# 63-00021_Worldcoin_Front_Unit_5_3.net
KiCad netlist of a schematic drawn in EAGLE
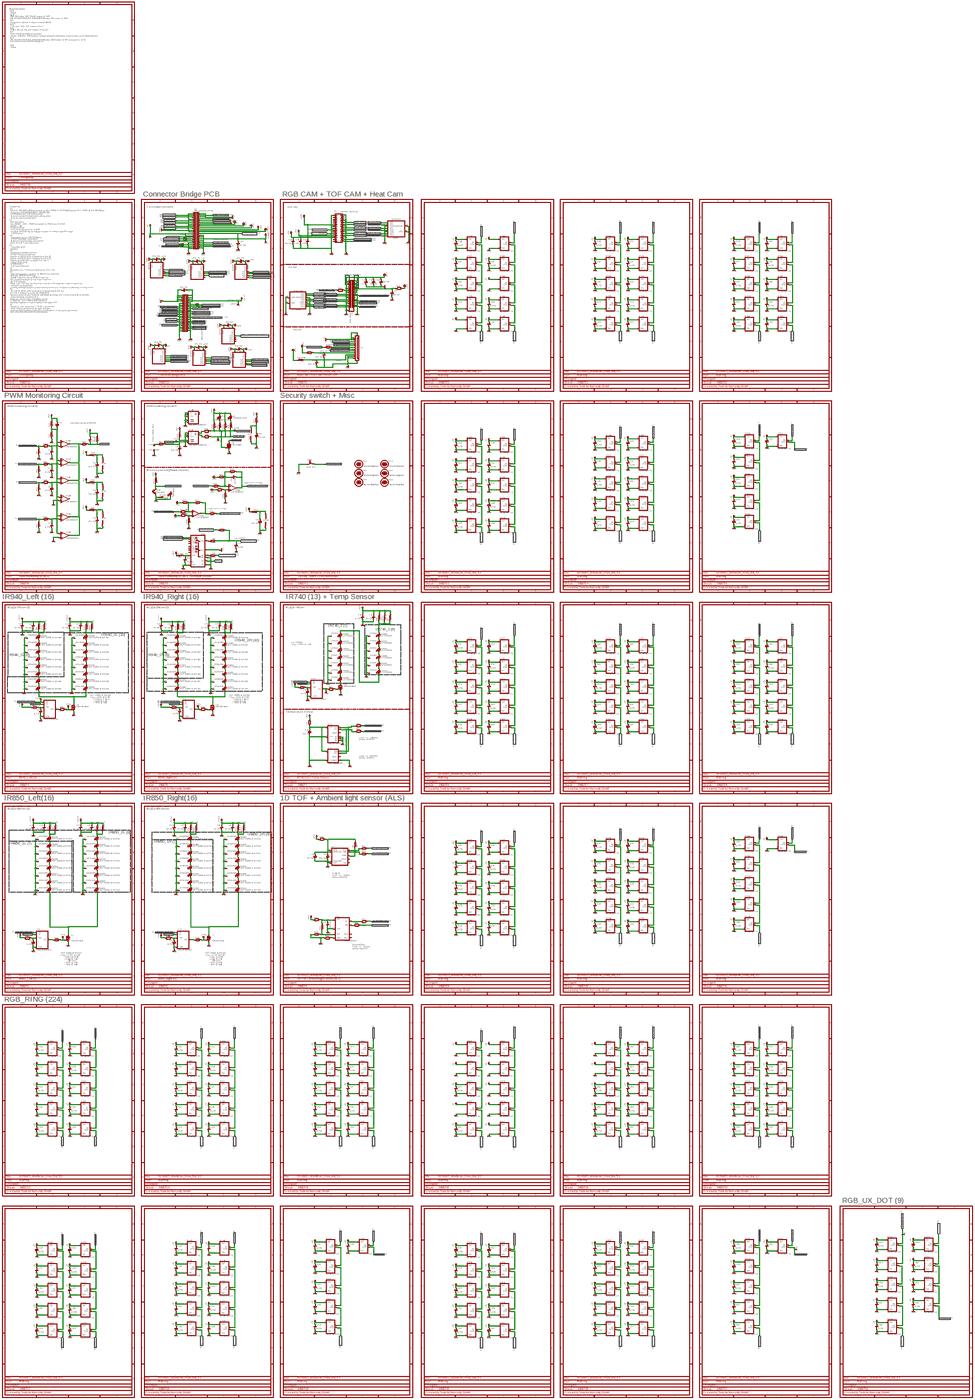
[diagram p0: schematic, sheet 1, overview]
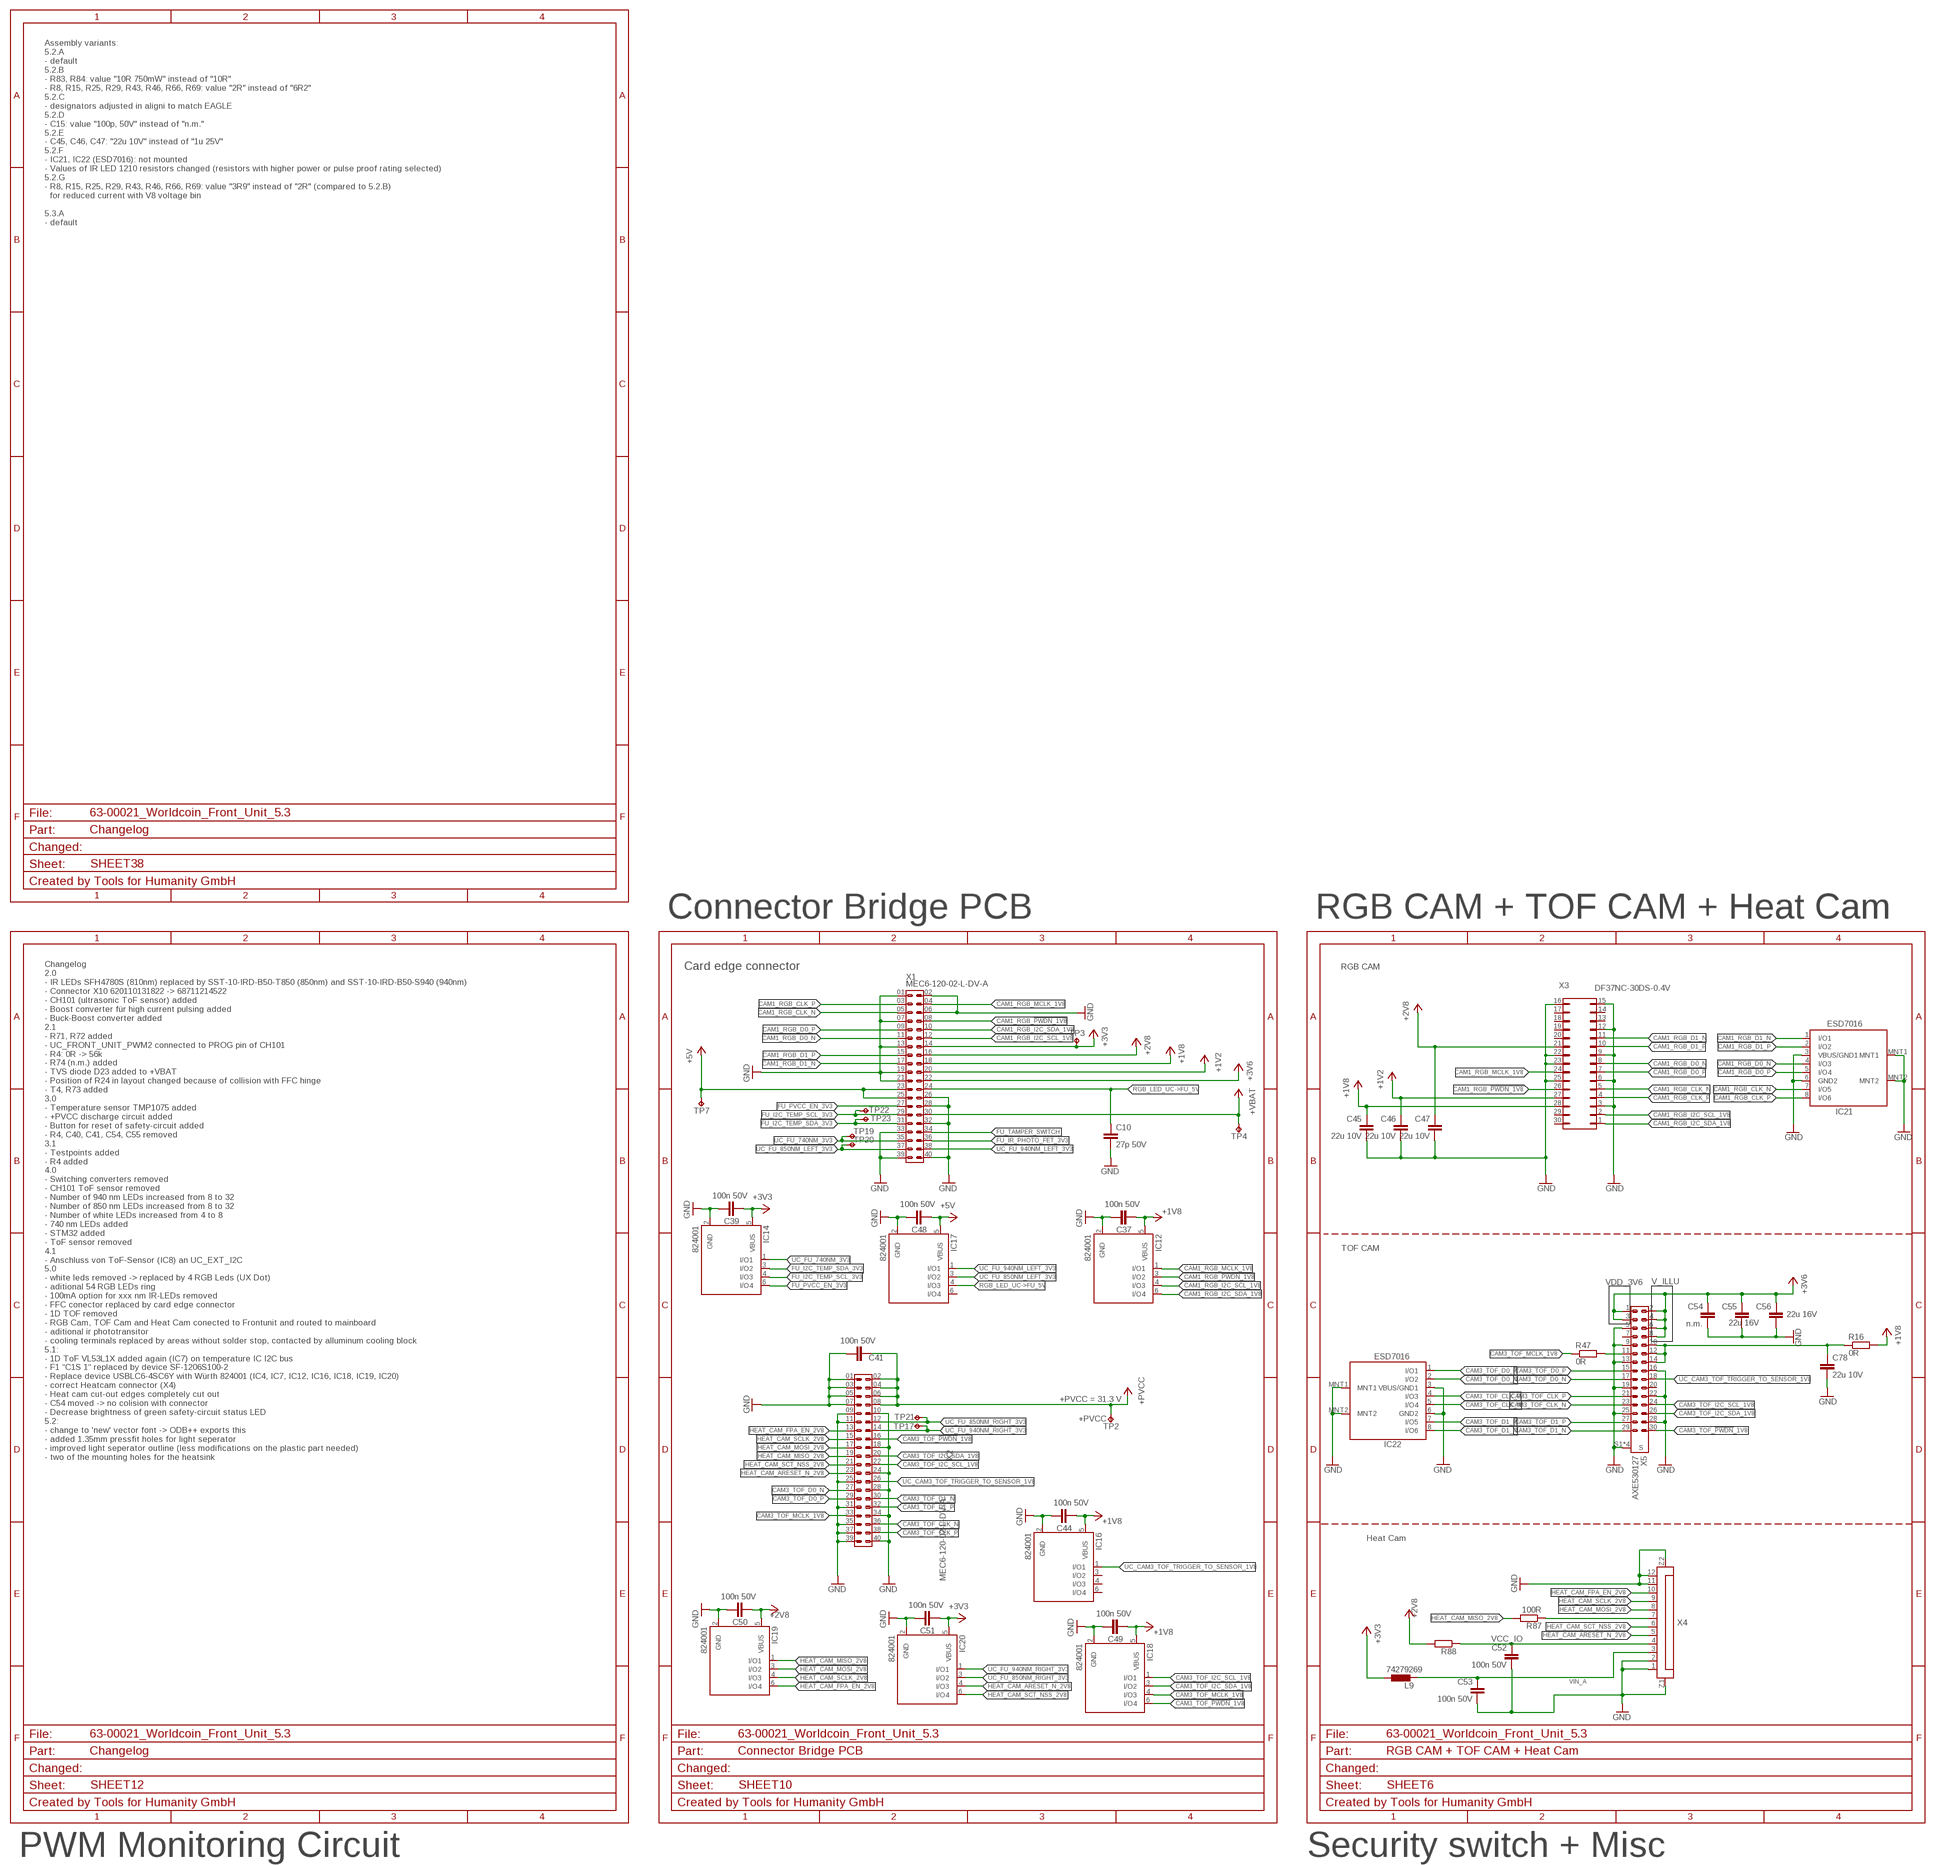
[diagram p1: schematic, sheet 1, part 1 of 8]
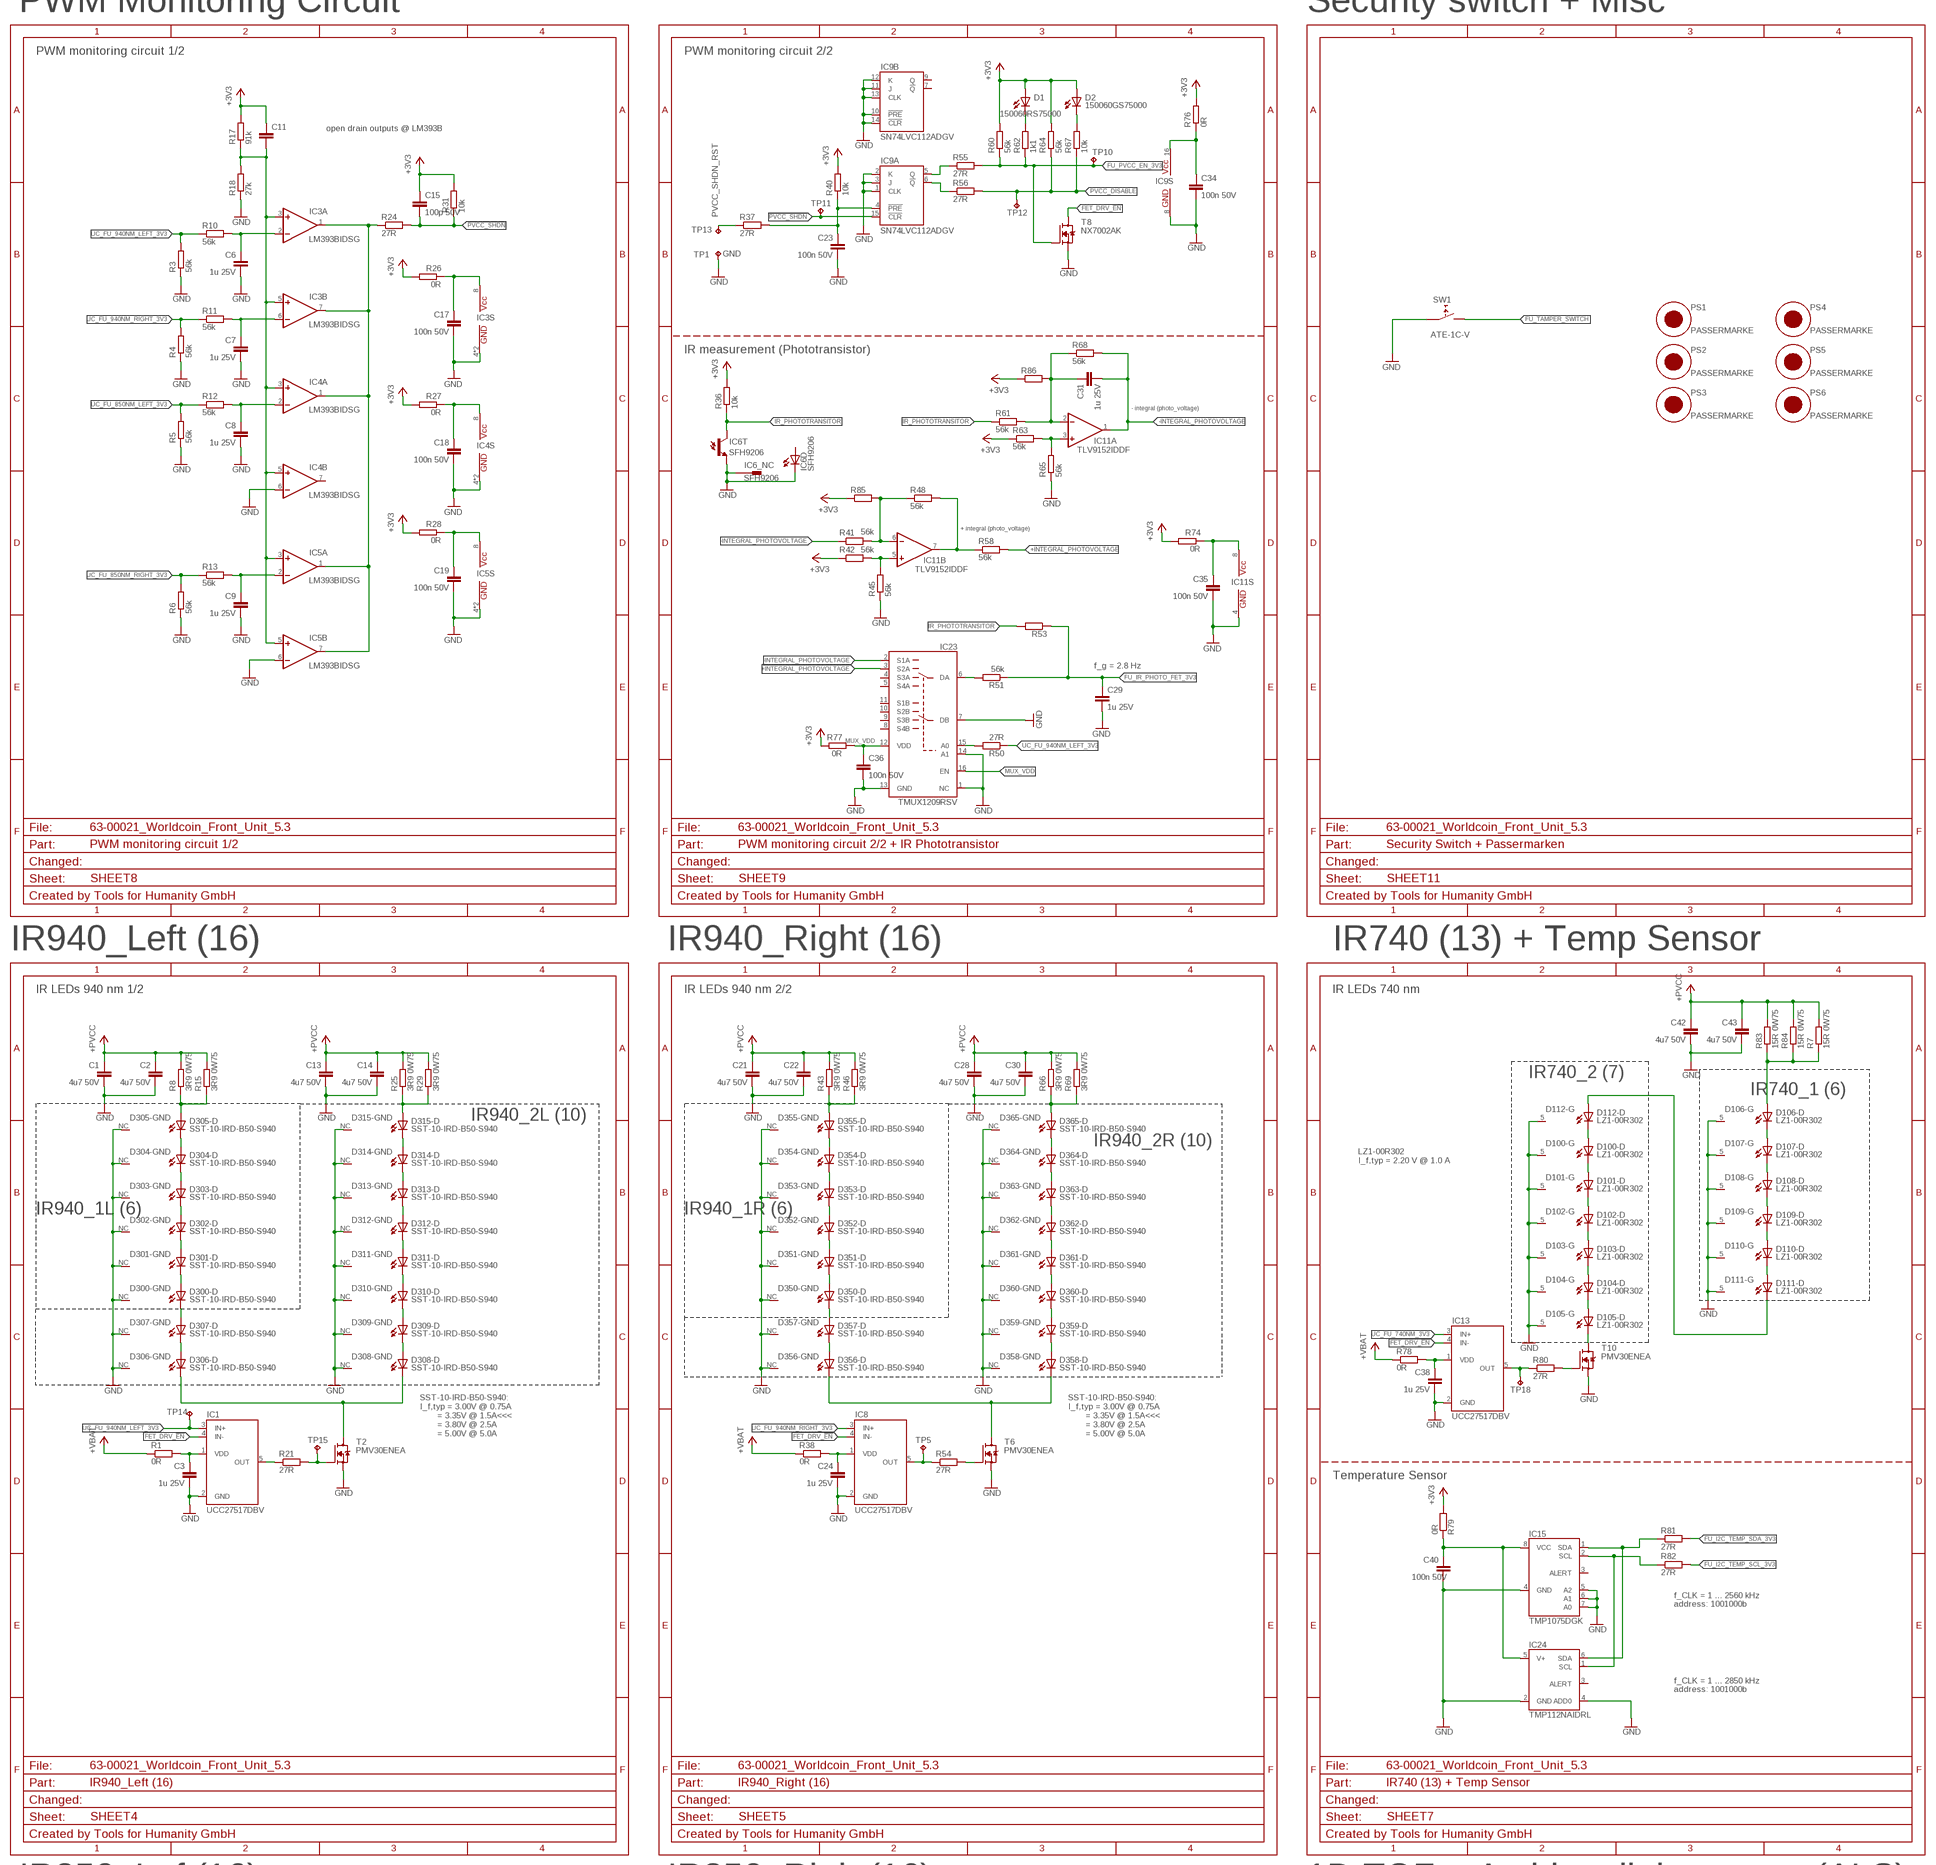
[diagram p2: schematic, sheet 1, part 2 of 8]
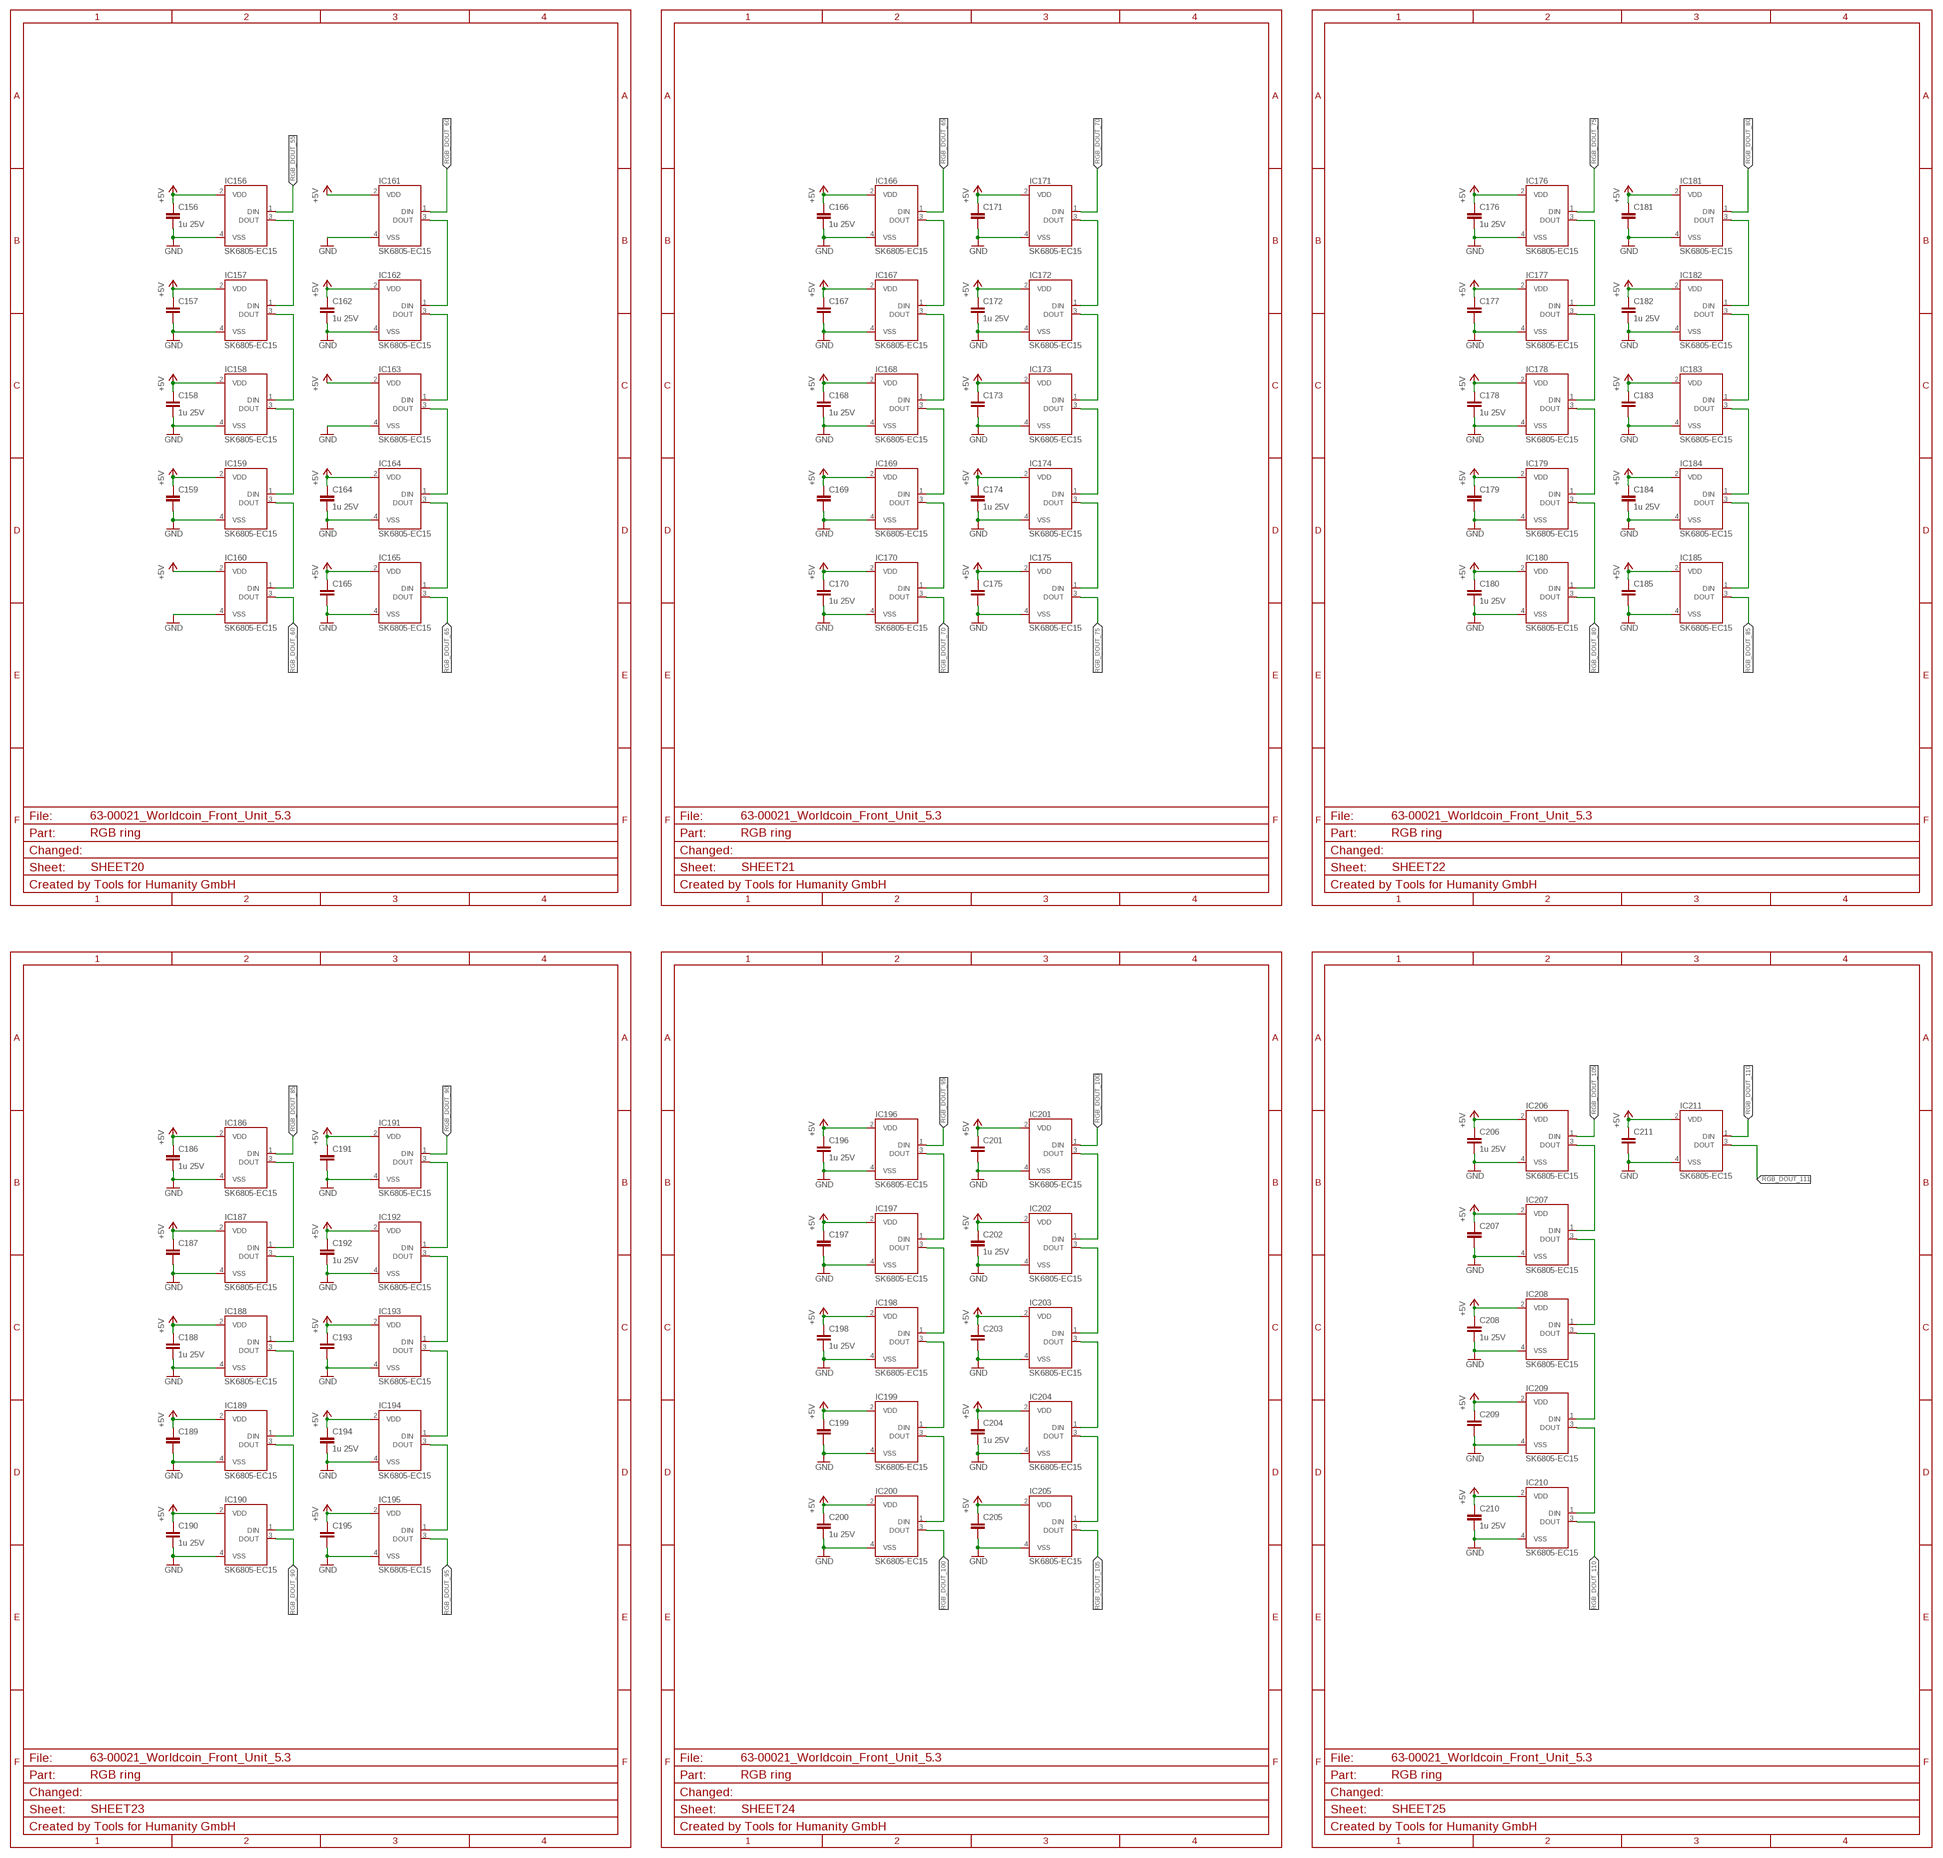
[diagram p3: schematic, sheet 1, part 3 of 8]
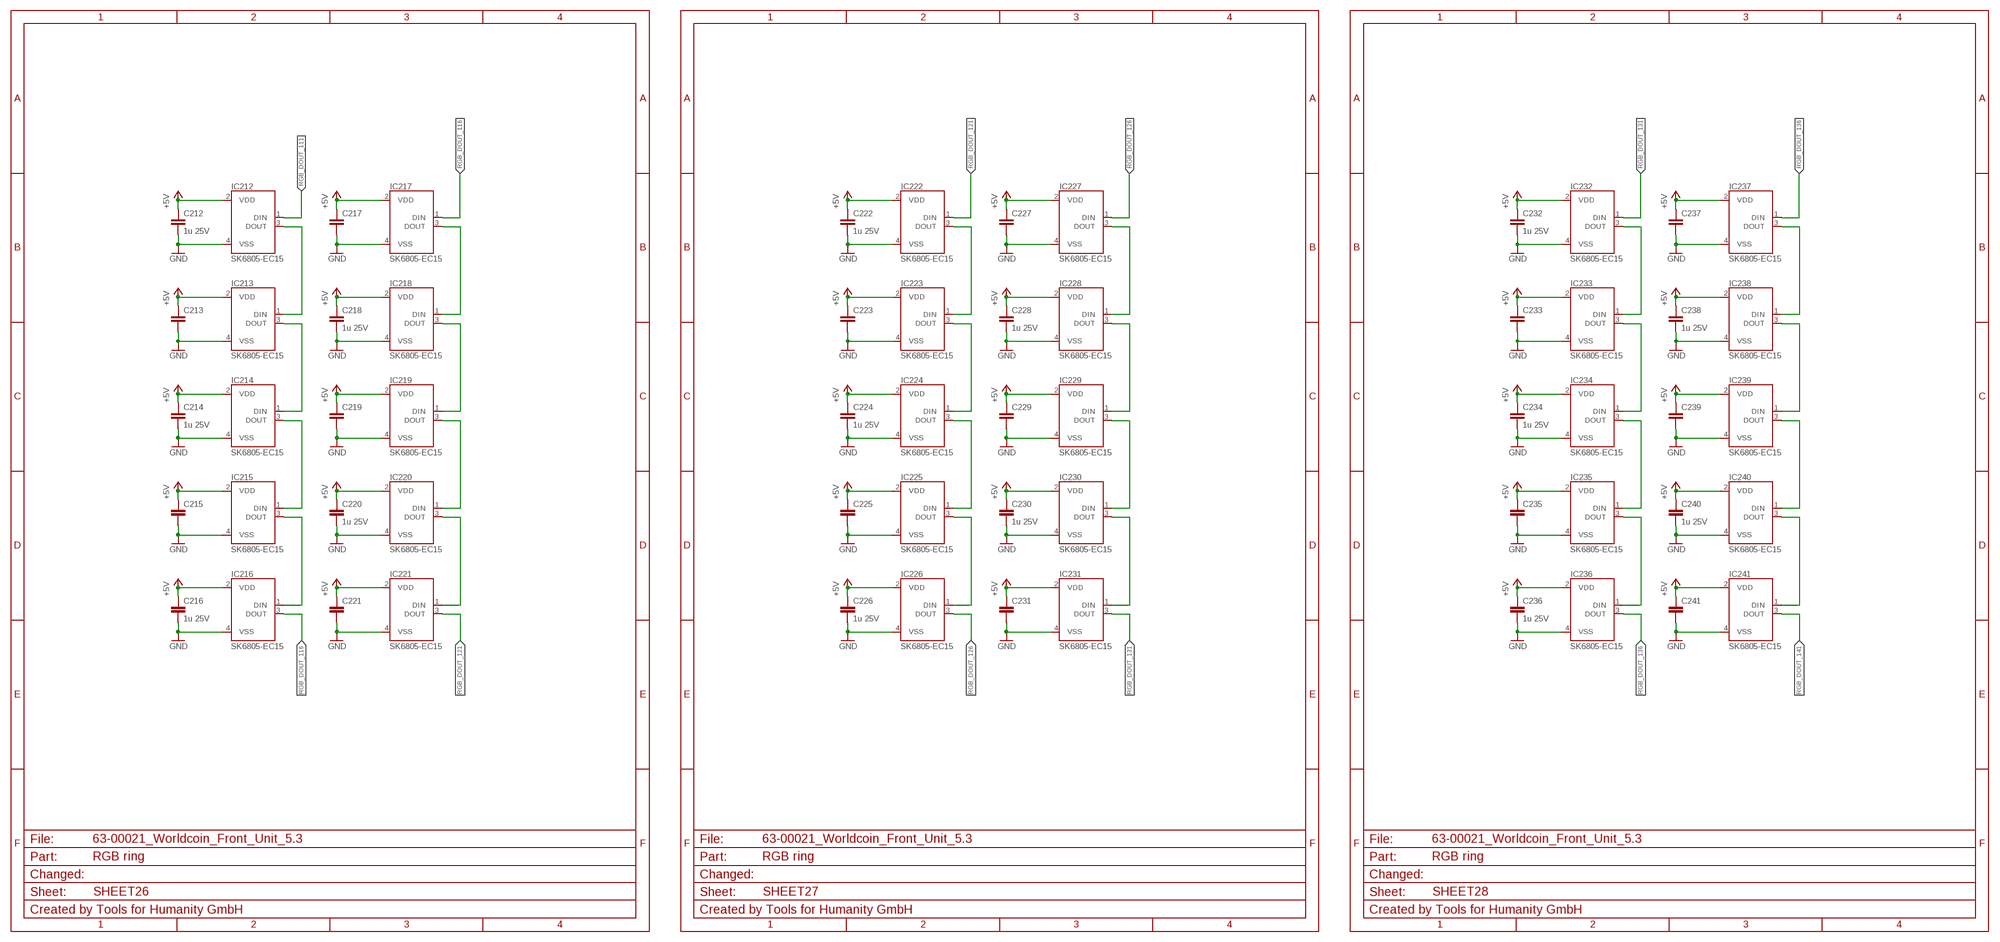
[diagram p4: schematic, sheet 1, part 4 of 8]
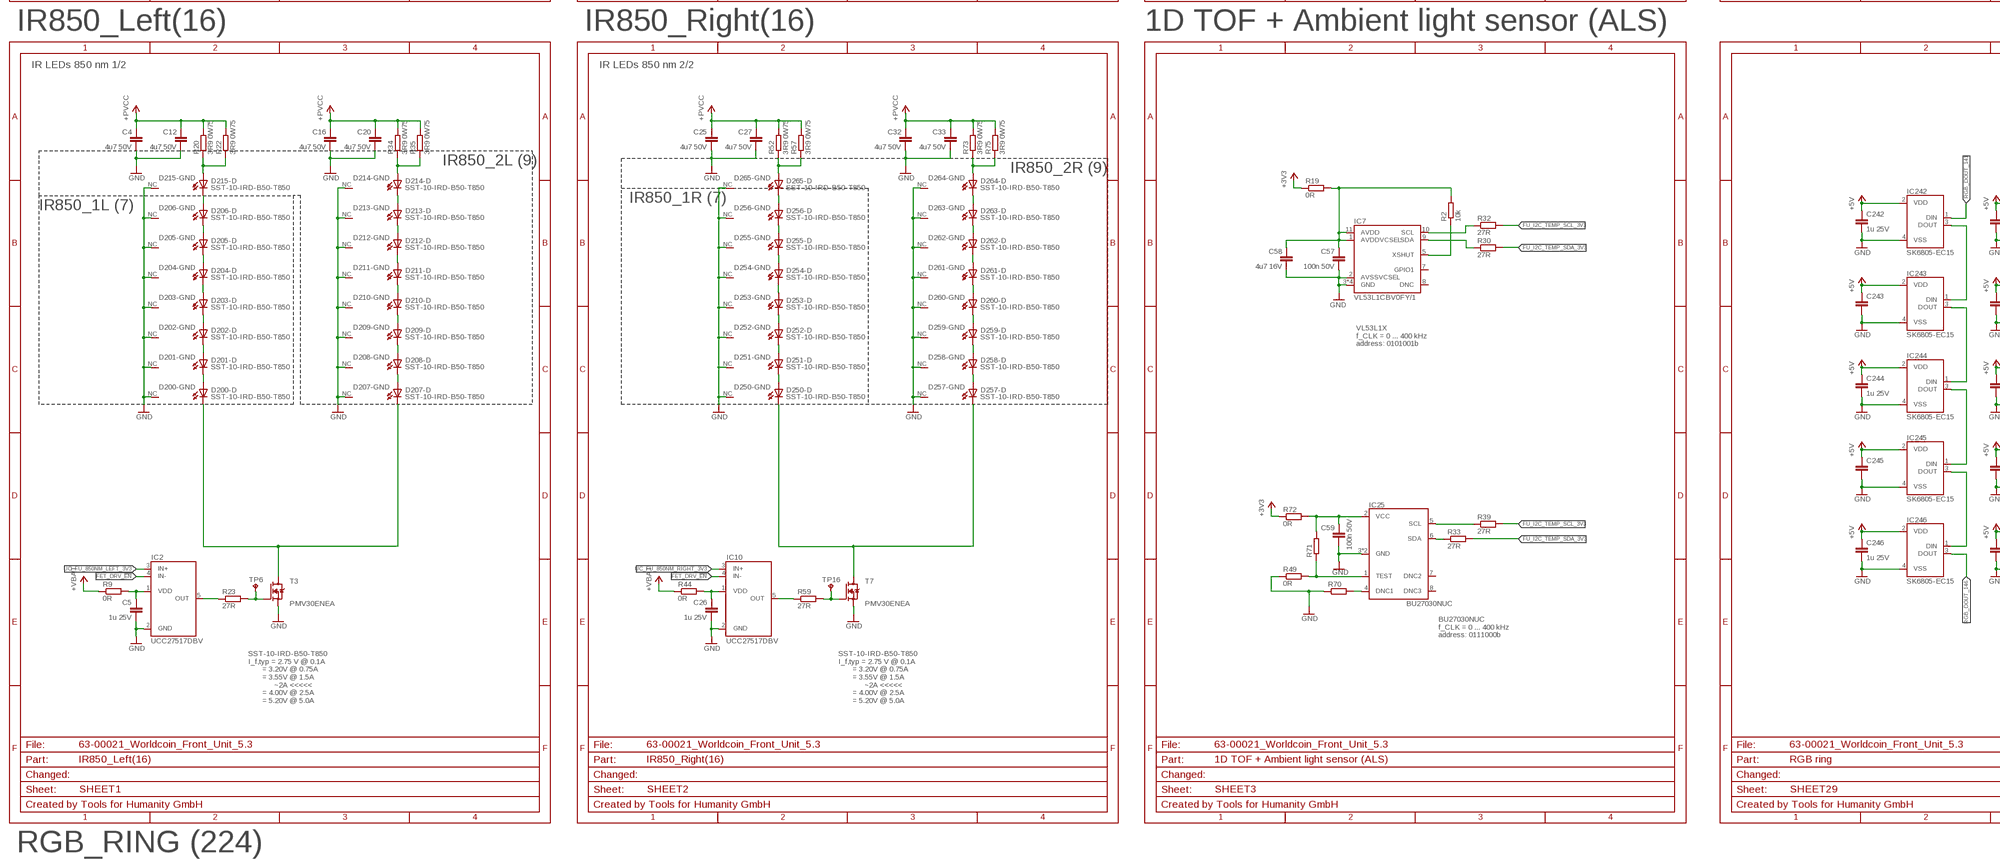
[diagram p5: schematic, sheet 1, part 5 of 8]
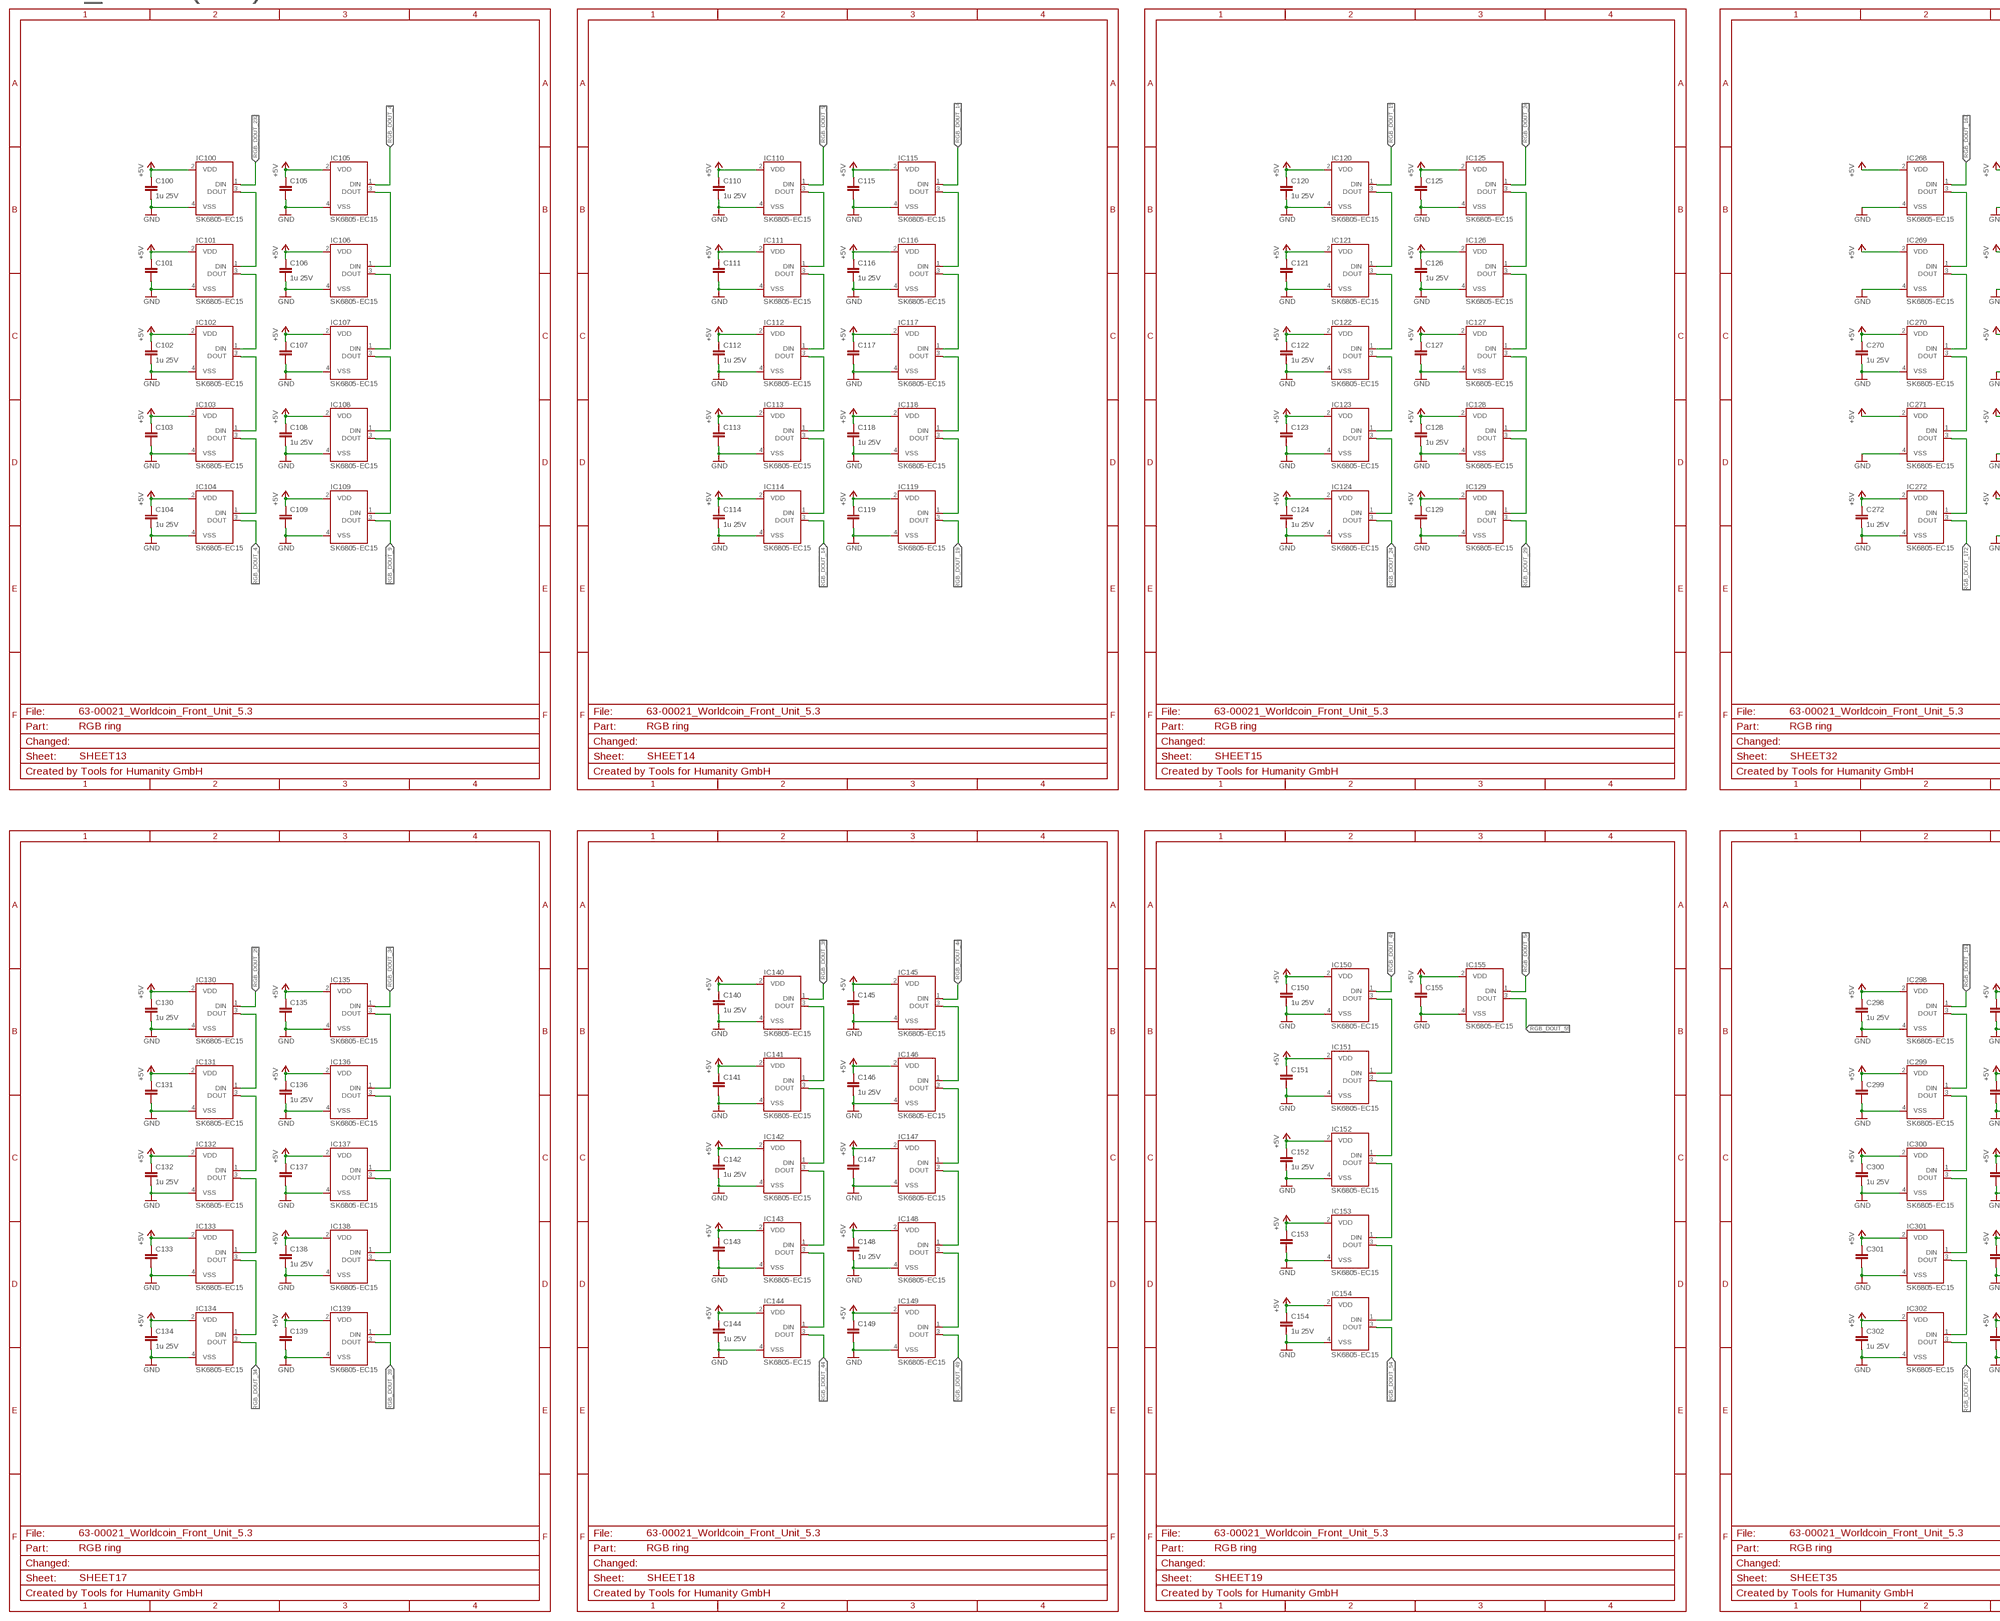
[diagram p6: schematic, sheet 1, part 6 of 8]
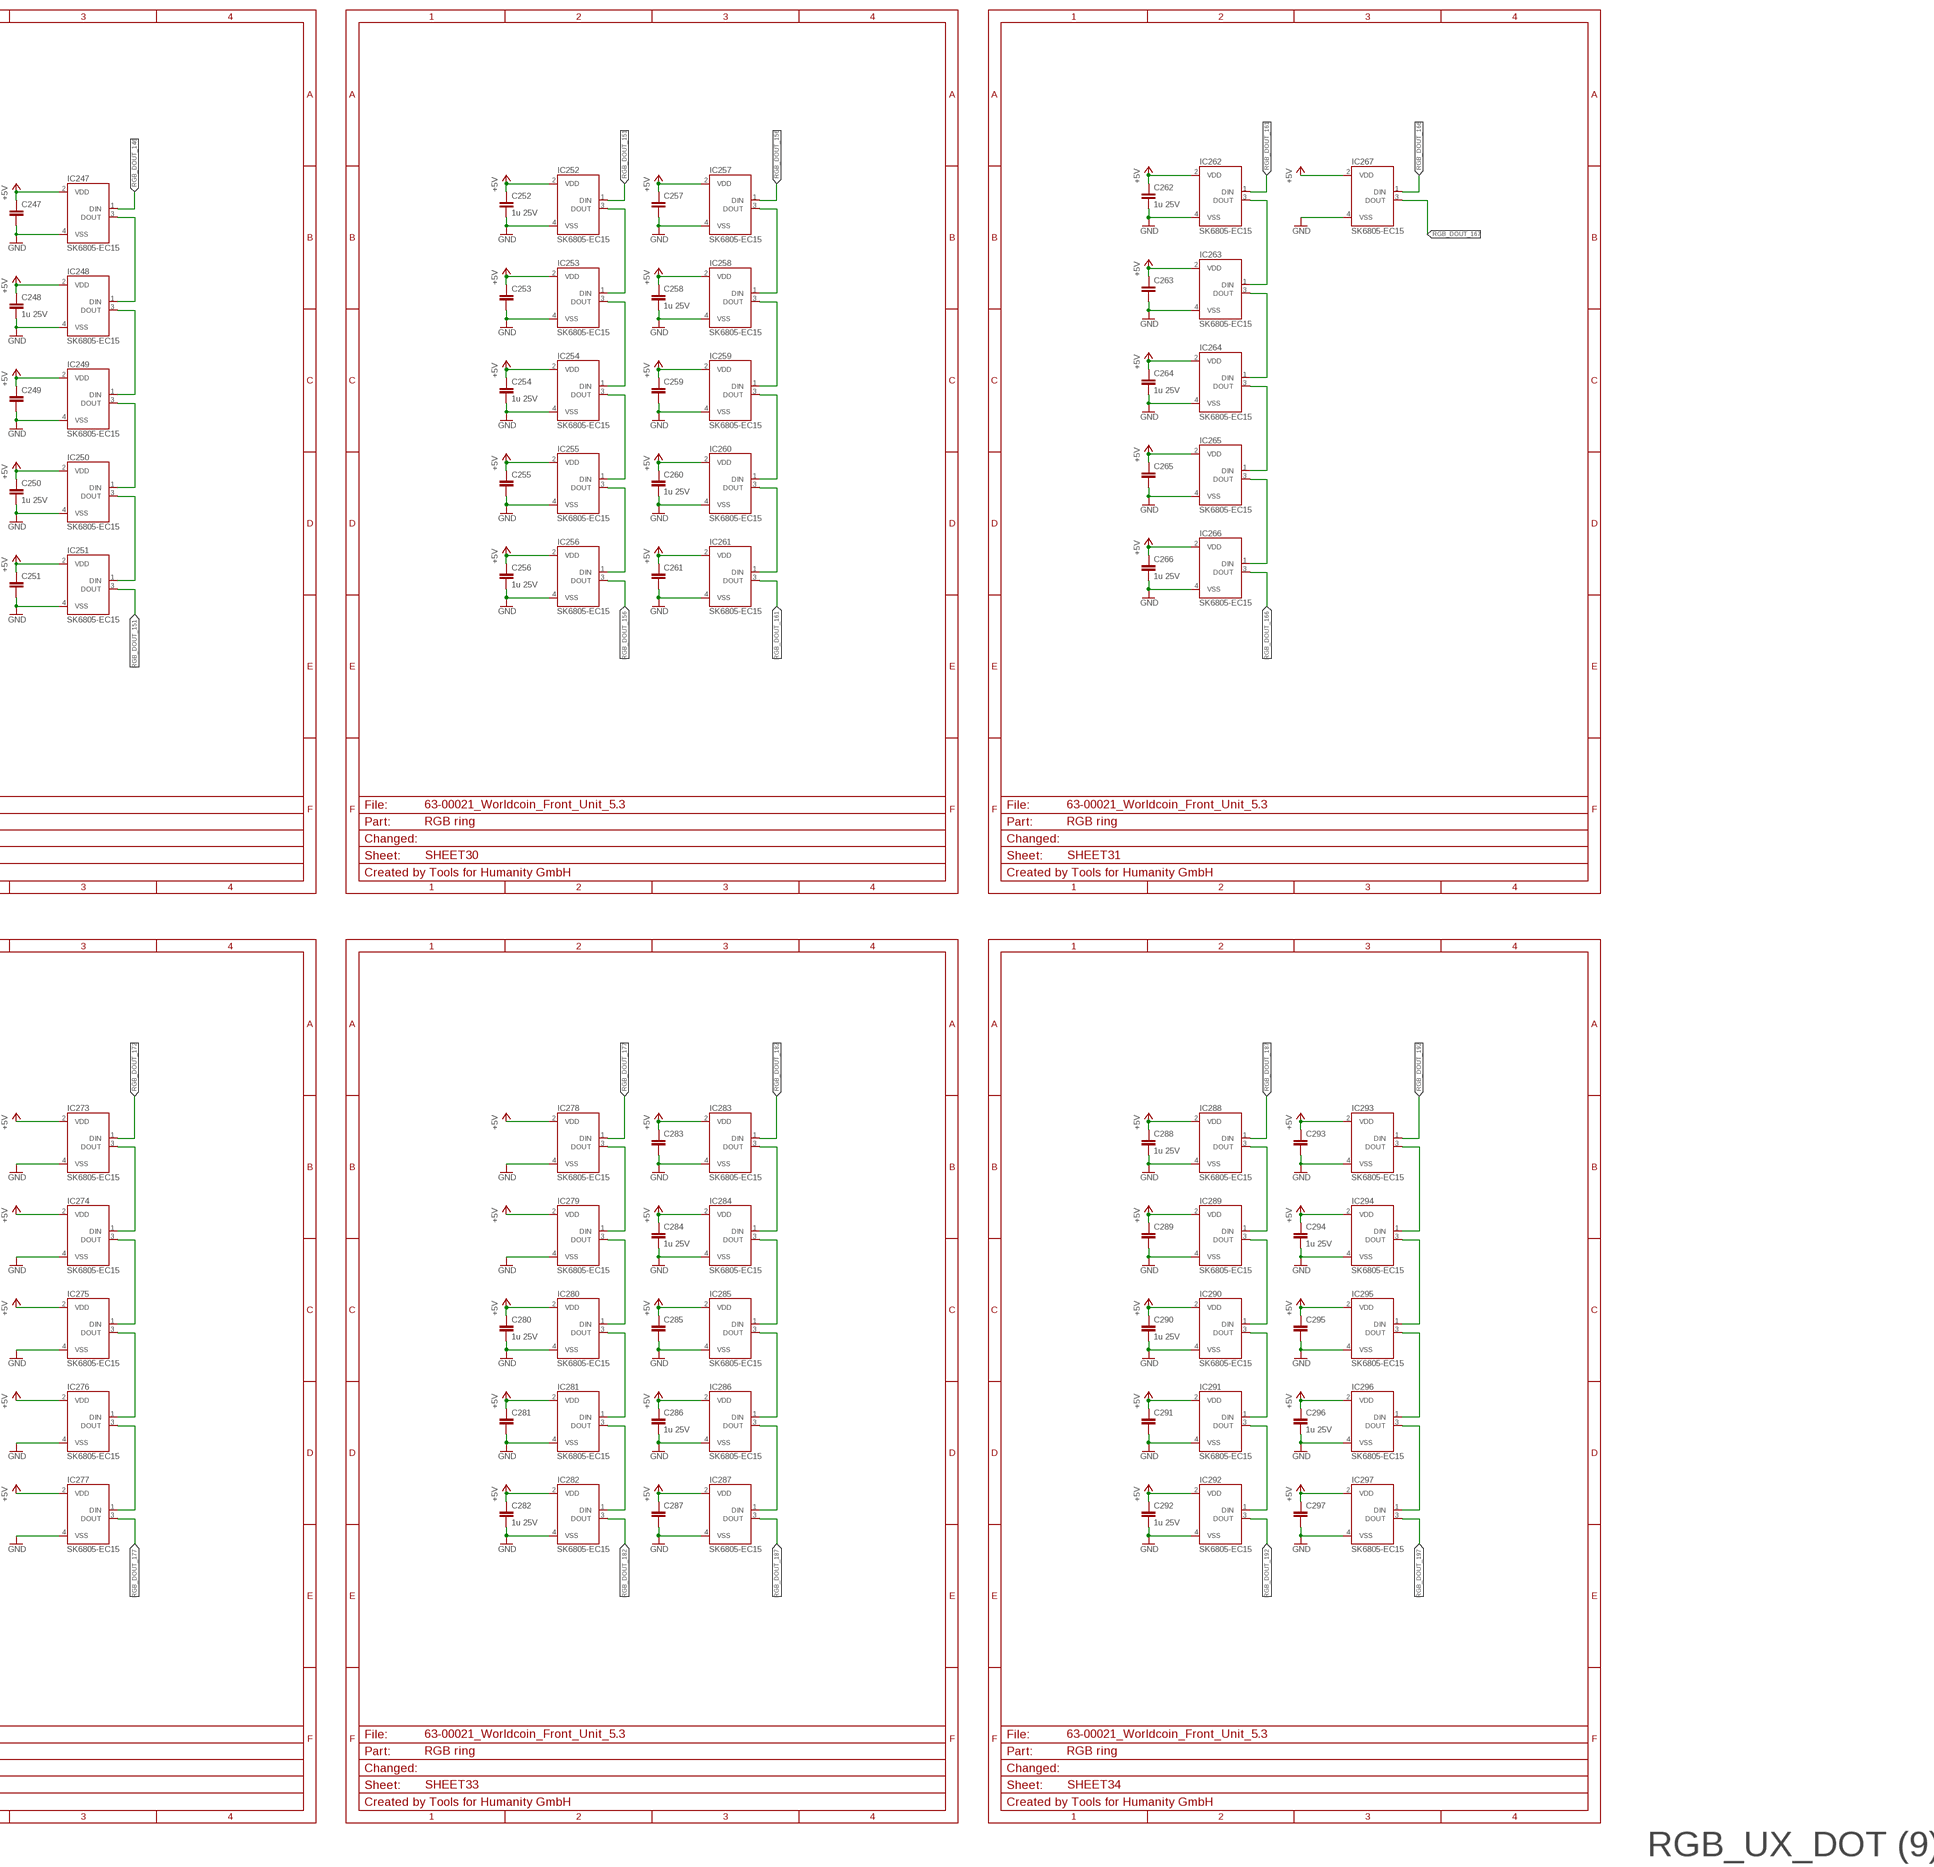
[diagram p7: schematic, sheet 1, part 7 of 8]
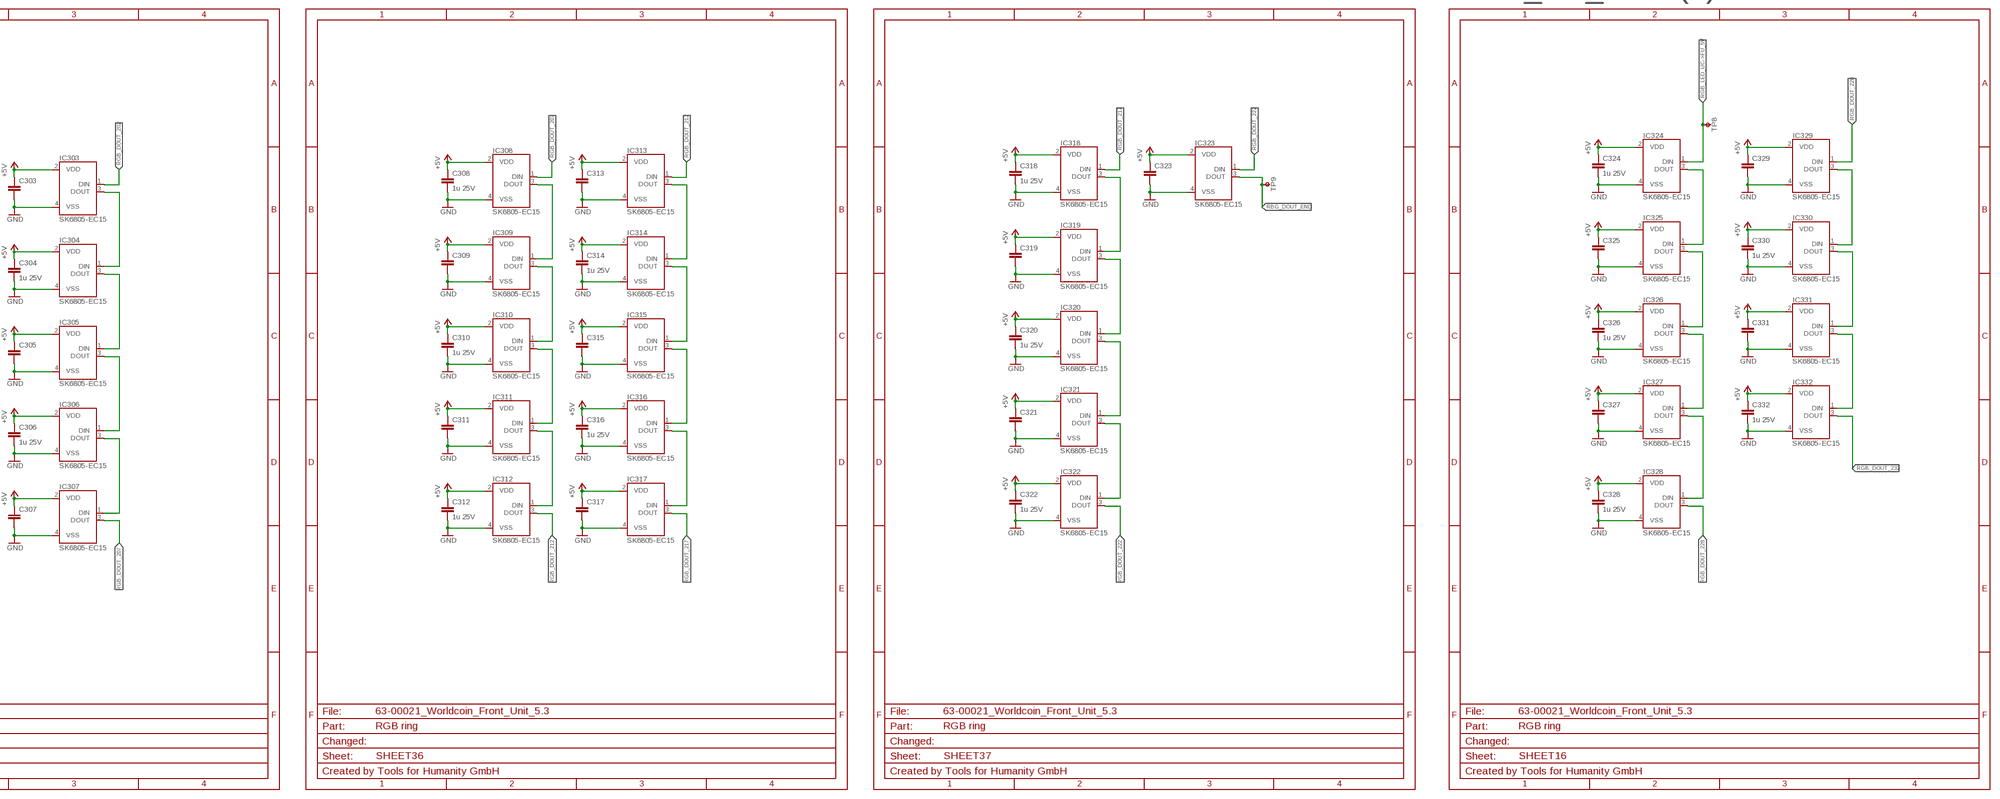
[diagram p8: schematic, sheet 1, part 8 of 8]

(export (version "E")
  (design (tool "Eeschema 10.0.6"))
  (components
    (comp (ref "C1")
      (value "4u7 50V")
      (footprint "eagle-import:C1210")
      (fields
        (field (name "MANUFACTURER") "free choice")
        (field (name "TOLERANCE") "±20 %")
        (field (name "VOLTAGE") "50.0 V")
      )
      (libsource (lib "eagle-import") (part "C-EU-C1210-4U7-50V"))
    )
    (comp (ref "C2")
      (value "4u7 50V")
      (footprint "eagle-import:C1210")
      (fields
        (field (name "MANUFACTURER") "free choice")
        (field (name "TOLERANCE") "±20 %")
        (field (name "VOLTAGE") "50.0 V")
      )
      (libsource (lib "eagle-import") (part "C-EU-C1210-4U7-50V"))
    )
    (comp (ref "C3")
      (value "1u 25V")
      (footprint "eagle-import:C0805")
      (fields
        (field (name "MANUFACTURER") "free choice")
        (field (name "TOLERANCE") "±20 %")
        (field (name "VOLTAGE") "25.0 V")
      )
      (libsource (lib "eagle-import") (part "C-EU-C0805-1U"))
    )
    (comp (ref "C4")
      (value "4u7 50V")
      (footprint "eagle-import:C1210")
      (fields
        (field (name "MANUFACTURER") "free choice")
        (field (name "TOLERANCE") "±20 %")
        (field (name "VOLTAGE") "50.0 V")
      )
      (libsource (lib "eagle-import") (part "C-EU-C1210-4U7-50V"))
    )
    (comp (ref "C5")
      (value "1u 25V")
      (footprint "eagle-import:C0805")
      (fields
        (field (name "MANUFACTURER") "free choice")
        (field (name "TOLERANCE") "±20 %")
        (field (name "VOLTAGE") "25.0 V")
      )
      (libsource (lib "eagle-import") (part "C-EU-C0805-1U"))
    )
    (comp (ref "C6")
      (value "1u 25V")
      (footprint "eagle-import:C0805")
      (fields
        (field (name "MANUFACTURER") "free choice")
        (field (name "TOLERANCE") "±20 %")
        (field (name "VOLTAGE") "25.0 V")
      )
      (libsource (lib "eagle-import") (part "C-EU-C0805-1U"))
    )
    (comp (ref "C7")
      (value "1u 25V")
      (footprint "eagle-import:C0805")
      (fields
        (field (name "MANUFACTURER") "free choice")
        (field (name "TOLERANCE") "±20 %")
        (field (name "VOLTAGE") "25.0 V")
      )
      (libsource (lib "eagle-import") (part "C-EU-C0805-1U"))
    )
    (comp (ref "C8")
      (value "1u 25V")
      (footprint "eagle-import:C0805")
      (fields
        (field (name "MANUFACTURER") "free choice")
        (field (name "TOLERANCE") "±20 %")
        (field (name "VOLTAGE") "25.0 V")
      )
      (libsource (lib "eagle-import") (part "C-EU-C0805-1U"))
    )
    (comp (ref "C9")
      (value "1u 25V")
      (footprint "eagle-import:C0805")
      (fields
        (field (name "MANUFACTURER") "free choice")
        (field (name "TOLERANCE") "±20 %")
        (field (name "VOLTAGE") "25.0 V")
      )
      (libsource (lib "eagle-import") (part "C-EU-C0805-1U"))
    )
    (comp (ref "C10")
      (value "27p 50V")
      (footprint "eagle-import:C0603")
      (fields
        (field (name "MANUFACTURER") "free choice")
        (field (name "TOLERANCE") "±20 %")
        (field (name "VOLTAGE") "50.0 V")
      )
      (libsource (lib "eagle-import") (part "C-EU-C0603-27P"))
    )
    (comp (ref "C11")
      (value "C-EU-C0603")
      (footprint "eagle-import:C0603")
      (fields (field (name "TOLERANCE") "±20 %") (field (name "VOLTAGE") "50.0 V"))
      (libsource (lib "eagle-import") (part "C-EU-C0603"))
    )
    (comp (ref "C12")
      (value "4u7 50V")
      (footprint "eagle-import:C1210")
      (fields
        (field (name "MANUFACTURER") "free choice")
        (field (name "TOLERANCE") "±20 %")
        (field (name "VOLTAGE") "50.0 V")
      )
      (libsource (lib "eagle-import") (part "C-EU-C1210-4U7-50V"))
    )
    (comp (ref "C13")
      (value "4u7 50V")
      (footprint "eagle-import:C1210")
      (fields
        (field (name "MANUFACTURER") "free choice")
        (field (name "TOLERANCE") "±20 %")
        (field (name "VOLTAGE") "50.0 V")
      )
      (libsource (lib "eagle-import") (part "C-EU-C1210-4U7-50V"))
    )
    (comp (ref "C14")
      (value "4u7 50V")
      (footprint "eagle-import:C1210")
      (fields
        (field (name "MANUFACTURER") "free choice")
        (field (name "TOLERANCE") "±20 %")
        (field (name "VOLTAGE") "50.0 V")
      )
      (libsource (lib "eagle-import") (part "C-EU-C1210-4U7-50V"))
    )
    (comp (ref "C15")
      (value "100p 50V")
      (footprint "eagle-import:C0603")
      (fields
        (field (name "MANUFACTURER") "free choice")
        (field (name "TOLERANCE") "±10 %")
        (field (name "VOLTAGE") "50.0 V")
      )
      (libsource (lib "eagle-import") (part "C-EU-C0603-100P"))
    )
    (comp (ref "C16")
      (value "4u7 50V")
      (footprint "eagle-import:C1210")
      (fields
        (field (name "MANUFACTURER") "free choice")
        (field (name "TOLERANCE") "±20 %")
        (field (name "VOLTAGE") "50.0 V")
      )
      (libsource (lib "eagle-import") (part "C-EU-C1210-4U7-50V"))
    )
    (comp (ref "C17")
      (value "100n 50V")
      (footprint "eagle-import:C0603")
      (fields
        (field (name "MANUFACTURER") "free choice")
        (field (name "TOLERANCE") "±20 %")
        (field (name "VOLTAGE") "50.0 V")
      )
      (libsource (lib "eagle-import") (part "C-EU-C0603-100N"))
    )
    (comp (ref "C18")
      (value "100n 50V")
      (footprint "eagle-import:C0603")
      (fields
        (field (name "MANUFACTURER") "free choice")
        (field (name "TOLERANCE") "±20 %")
        (field (name "VOLTAGE") "50.0 V")
      )
      (libsource (lib "eagle-import") (part "C-EU-C0603-100N"))
    )
    (comp (ref "C19")
      (value "100n 50V")
      (footprint "eagle-import:C0603")
      (fields
        (field (name "MANUFACTURER") "free choice")
        (field (name "TOLERANCE") "±20 %")
        (field (name "VOLTAGE") "50.0 V")
      )
      (libsource (lib "eagle-import") (part "C-EU-C0603-100N"))
    )
    (comp (ref "C20")
      (value "4u7 50V")
      (footprint "eagle-import:C1210")
      (fields
        (field (name "MANUFACTURER") "free choice")
        (field (name "TOLERANCE") "±20 %")
        (field (name "VOLTAGE") "50.0 V")
      )
      (libsource (lib "eagle-import") (part "C-EU-C1210-4U7-50V"))
    )
    (comp (ref "C21")
      (value "4u7 50V")
      (footprint "eagle-import:C1210")
      (fields
        (field (name "MANUFACTURER") "free choice")
        (field (name "TOLERANCE") "±20 %")
        (field (name "VOLTAGE") "50.0 V")
      )
      (libsource (lib "eagle-import") (part "C-EU-C1210-4U7-50V"))
    )
    (comp (ref "C22")
      (value "4u7 50V")
      (footprint "eagle-import:C1210")
      (fields
        (field (name "MANUFACTURER") "free choice")
        (field (name "TOLERANCE") "±20 %")
        (field (name "VOLTAGE") "50.0 V")
      )
      (libsource (lib "eagle-import") (part "C-EU-C1210-4U7-50V"))
    )
    (comp (ref "C23")
      (value "100n 50V")
      (footprint "eagle-import:C0603")
      (fields
        (field (name "MANUFACTURER") "free choice")
        (field (name "TOLERANCE") "±20 %")
        (field (name "VOLTAGE") "50.0 V")
      )
      (libsource (lib "eagle-import") (part "C-EU-C0603-100N"))
    )
    (comp (ref "C24")
      (value "1u 25V")
      (footprint "eagle-import:C0805")
      (fields
        (field (name "MANUFACTURER") "free choice")
        (field (name "TOLERANCE") "±20 %")
        (field (name "VOLTAGE") "25.0 V")
      )
      (libsource (lib "eagle-import") (part "C-EU-C0805-1U"))
    )
    (comp (ref "C25")
      (value "4u7 50V")
      (footprint "eagle-import:C1210")
      (fields
        (field (name "MANUFACTURER") "free choice")
        (field (name "TOLERANCE") "±20 %")
        (field (name "VOLTAGE") "50.0 V")
      )
      (libsource (lib "eagle-import") (part "C-EU-C1210-4U7-50V"))
    )
    (comp (ref "C26")
      (value "1u 25V")
      (footprint "eagle-import:C0805")
      (fields
        (field (name "MANUFACTURER") "free choice")
        (field (name "TOLERANCE") "±20 %")
        (field (name "VOLTAGE") "25.0 V")
      )
      (libsource (lib "eagle-import") (part "C-EU-C0805-1U"))
    )
    (comp (ref "C27")
      (value "4u7 50V")
      (footprint "eagle-import:C1210")
      (fields
        (field (name "MANUFACTURER") "free choice")
        (field (name "TOLERANCE") "±20 %")
        (field (name "VOLTAGE") "50.0 V")
      )
      (libsource (lib "eagle-import") (part "C-EU-C1210-4U7-50V"))
    )
    (comp (ref "C28")
      (value "4u7 50V")
      (footprint "eagle-import:C1210")
      (fields
        (field (name "MANUFACTURER") "free choice")
        (field (name "TOLERANCE") "±20 %")
        (field (name "VOLTAGE") "50.0 V")
      )
      (libsource (lib "eagle-import") (part "C-EU-C1210-4U7-50V"))
    )
    (comp (ref "C29")
      (value "1u 25V")
      (footprint "eagle-import:C0805")
      (fields
        (field (name "MANUFACTURER") "free choice")
        (field (name "TOLERANCE") "±20 %")
        (field (name "VOLTAGE") "25.0 V")
      )
      (libsource (lib "eagle-import") (part "C-EU-C0805-1U"))
    )
    (comp (ref "C30")
      (value "4u7 50V")
      (footprint "eagle-import:C1210")
      (fields
        (field (name "MANUFACTURER") "free choice")
        (field (name "TOLERANCE") "±20 %")
        (field (name "VOLTAGE") "50.0 V")
      )
      (libsource (lib "eagle-import") (part "C-EU-C1210-4U7-50V"))
    )
    (comp (ref "C31")
      (value "1u 25V")
      (footprint "eagle-import:C0805")
      (fields
        (field (name "MANUFACTURER") "free choice")
        (field (name "TOLERANCE") "±20 %")
        (field (name "VOLTAGE") "25.0 V")
      )
      (libsource (lib "eagle-import") (part "C-EU-C0805-1U"))
    )
    (comp (ref "C32")
      (value "4u7 50V")
      (footprint "eagle-import:C1210")
      (fields
        (field (name "MANUFACTURER") "free choice")
        (field (name "TOLERANCE") "±20 %")
        (field (name "VOLTAGE") "50.0 V")
      )
      (libsource (lib "eagle-import") (part "C-EU-C1210-4U7-50V"))
    )
    (comp (ref "C33")
      (value "4u7 50V")
      (footprint "eagle-import:C1210")
      (fields
        (field (name "MANUFACTURER") "free choice")
        (field (name "TOLERANCE") "±20 %")
        (field (name "VOLTAGE") "50.0 V")
      )
      (libsource (lib "eagle-import") (part "C-EU-C1210-4U7-50V"))
    )
    (comp (ref "C34")
      (value "100n 50V")
      (footprint "eagle-import:C0603")
      (fields
        (field (name "MANUFACTURER") "free choice")
        (field (name "TOLERANCE") "±20 %")
        (field (name "VOLTAGE") "50.0 V")
      )
      (libsource (lib "eagle-import") (part "C-EU-C0603-100N"))
    )
    (comp (ref "C35")
      (value "100n 50V")
      (footprint "eagle-import:C0603")
      (fields
        (field (name "MANUFACTURER") "free choice")
        (field (name "TOLERANCE") "±20 %")
        (field (name "VOLTAGE") "50.0 V")
      )
      (libsource (lib "eagle-import") (part "C-EU-C0603-100N"))
    )
    (comp (ref "C36")
      (value "100n 50V")
      (footprint "eagle-import:C0603")
      (fields
        (field (name "MANUFACTURER") "free choice")
        (field (name "TOLERANCE") "±20 %")
        (field (name "VOLTAGE") "50.0 V")
      )
      (libsource (lib "eagle-import") (part "C-EU-C0603-100N"))
    )
    (comp (ref "C37")
      (value "100n 50V")
      (footprint "eagle-import:C0603")
      (fields
        (field (name "MANUFACTURER") "free choice")
        (field (name "TOLERANCE") "±20 %")
        (field (name "VOLTAGE") "50.0 V")
      )
      (libsource (lib "eagle-import") (part "C-EU-C0603-100N"))
    )
    (comp (ref "C38")
      (value "1u 25V")
      (footprint "eagle-import:C0805")
      (fields
        (field (name "MANUFACTURER") "free choice")
        (field (name "TOLERANCE") "±20 %")
        (field (name "VOLTAGE") "25.0 V")
      )
      (libsource (lib "eagle-import") (part "C-EU-C0805-1U"))
    )
    (comp (ref "C39")
      (value "100n 50V")
      (footprint "eagle-import:C0603")
      (fields
        (field (name "MANUFACTURER") "free choice")
        (field (name "TOLERANCE") "±20 %")
        (field (name "VOLTAGE") "50.0 V")
      )
      (libsource (lib "eagle-import") (part "C-EU-C0603-100N"))
    )
    (comp (ref "C40")
      (value "100n 50V")
      (footprint "eagle-import:C0603")
      (fields
        (field (name "MANUFACTURER") "free choice")
        (field (name "TOLERANCE") "±20 %")
        (field (name "VOLTAGE") "50.0 V")
      )
      (libsource (lib "eagle-import") (part "C-EU-C0603-100N"))
    )
    (comp (ref "C41")
      (value "100n 50V")
      (footprint "eagle-import:C0603")
      (fields
        (field (name "MANUFACTURER") "free choice")
        (field (name "TOLERANCE") "±20 %")
        (field (name "VOLTAGE") "50.0 V")
      )
      (libsource (lib "eagle-import") (part "C-EU-C0603-100N"))
    )
    (comp (ref "C42")
      (value "4u7 50V")
      (footprint "eagle-import:C1210")
      (fields
        (field (name "MANUFACTURER") "free choice")
        (field (name "TOLERANCE") "±20 %")
        (field (name "VOLTAGE") "50.0 V")
      )
      (libsource (lib "eagle-import") (part "C-EU-C1210-4U7-50V"))
    )
    (comp (ref "C43")
      (value "4u7 50V")
      (footprint "eagle-import:C1210")
      (fields
        (field (name "MANUFACTURER") "free choice")
        (field (name "TOLERANCE") "±20 %")
        (field (name "VOLTAGE") "50.0 V")
      )
      (libsource (lib "eagle-import") (part "C-EU-C1210-4U7-50V"))
    )
    (comp (ref "C44")
      (value "100n 50V")
      (footprint "eagle-import:C0603")
      (fields
        (field (name "MANUFACTURER") "free choice")
        (field (name "TOLERANCE") "±20 %")
        (field (name "VOLTAGE") "50.0 V")
      )
      (libsource (lib "eagle-import") (part "C-EU-C0603-100N"))
    )
    (comp (ref "C45")
      (value "22u 10V")
      (footprint "eagle-import:C0805")
      (fields
        (field (name "MANUFACTURER") "free choice")
        (field (name "TOLERANCE") "±20 %")
        (field (name "VOLTAGE") "10.0 V")
      )
      (libsource (lib "eagle-import") (part "C-EU-C0805-22U"))
    )
    (comp (ref "C46")
      (value "22u 10V")
      (footprint "eagle-import:C0805")
      (fields
        (field (name "MANUFACTURER") "free choice")
        (field (name "TOLERANCE") "±20 %")
        (field (name "VOLTAGE") "10.0 V")
      )
      (libsource (lib "eagle-import") (part "C-EU-C0805-22U"))
    )
    (comp (ref "C47")
      (value "22u 10V")
      (footprint "eagle-import:C0805")
      (fields
        (field (name "MANUFACTURER") "free choice")
        (field (name "TOLERANCE") "±20 %")
        (field (name "VOLTAGE") "10.0 V")
      )
      (libsource (lib "eagle-import") (part "C-EU-C0805-22U"))
    )
    (comp (ref "C48")
      (value "100n 50V")
      (footprint "eagle-import:C0603")
      (fields
        (field (name "MANUFACTURER") "free choice")
        (field (name "TOLERANCE") "±20 %")
        (field (name "VOLTAGE") "50.0 V")
      )
      (libsource (lib "eagle-import") (part "C-EU-C0603-100N"))
    )
    (comp (ref "C49")
      (value "100n 50V")
      (footprint "eagle-import:C0603")
      (fields
        (field (name "MANUFACTURER") "free choice")
        (field (name "TOLERANCE") "±20 %")
        (field (name "VOLTAGE") "50.0 V")
      )
      (libsource (lib "eagle-import") (part "C-EU-C0603-100N"))
    )
    (comp (ref "C50")
      (value "100n 50V")
      (footprint "eagle-import:C0603")
      (fields
        (field (name "MANUFACTURER") "free choice")
        (field (name "TOLERANCE") "±20 %")
        (field (name "VOLTAGE") "50.0 V")
      )
      (libsource (lib "eagle-import") (part "C-EU-C0603-100N"))
    )
    (comp (ref "C51")
      (value "100n 50V")
      (footprint "eagle-import:C0603")
      (fields
        (field (name "MANUFACTURER") "free choice")
        (field (name "TOLERANCE") "±20 %")
        (field (name "VOLTAGE") "50.0 V")
      )
      (libsource (lib "eagle-import") (part "C-EU-C0603-100N"))
    )
    (comp (ref "C52")
      (value "100n 50V")
      (footprint "eagle-import:C0603")
      (fields
        (field (name "MANUFACTURER") "free choice")
        (field (name "TOLERANCE") "±20 %")
        (field (name "VOLTAGE") "50.0 V")
      )
      (libsource (lib "eagle-import") (part "C-EU-C0603-100N"))
    )
    (comp (ref "C53")
      (value "100n 50V")
      (footprint "eagle-import:C0603")
      (fields
        (field (name "MANUFACTURER") "free choice")
        (field (name "TOLERANCE") "±20 %")
        (field (name "VOLTAGE") "50.0 V")
      )
      (libsource (lib "eagle-import") (part "C-EU-C0603-100N"))
    )
    (comp (ref "C54")
      (value "n.m.")
      (footprint "eagle-import:C1206")
      (fields (field (name "TOLERANCE") "±20 %") (field (name "VOLTAGE") "6V3"))
      (libsource (lib "eagle-import") (part "C-EU-C1206"))
    )
    (comp (ref "C55")
      (value "22u 16V")
      (footprint "eagle-import:C1206")
      (fields
        (field (name "MANUFACTURER") "free choice")
        (field (name "TOLERANCE") "±20 %")
        (field (name "VOLTAGE") "16.0 V")
      )
      (libsource (lib "eagle-import") (part "C-EU-C1206-22U"))
    )
    (comp (ref "C56")
      (value "22u 16V")
      (footprint "eagle-import:C1206")
      (fields
        (field (name "MANUFACTURER") "free choice")
        (field (name "TOLERANCE") "±20 %")
        (field (name "VOLTAGE") "16.0 V")
      )
      (libsource (lib "eagle-import") (part "C-EU-C1206-22U"))
    )
    (comp (ref "C57")
      (value "100n 50V")
      (footprint "eagle-import:C0603")
      (fields
        (field (name "MANUFACTURER") "free choice")
        (field (name "TOLERANCE") "±20 %")
        (field (name "VOLTAGE") "50.0 V")
      )
      (libsource (lib "eagle-import") (part "C-EU-C0603-100N"))
    )
    (comp (ref "C58")
      (value "4u7 16V")
      (footprint "eagle-import:C0805")
      (fields
        (field (name "MANUFACTURER") "free choice")
        (field (name "TOLERANCE") "±20 %")
        (field (name "VOLTAGE") "16.0 V")
      )
      (libsource (lib "eagle-import") (part "C-EU-C0805-4U7"))
    )
    (comp (ref "C59")
      (value "100n 50V")
      (footprint "eagle-import:C0603")
      (fields
        (field (name "MANUFACTURER") "free choice")
        (field (name "TOLERANCE") "±20 %")
        (field (name "VOLTAGE") "50.0 V")
      )
      (libsource (lib "eagle-import") (part "C-EU-C0603-100N"))
    )
    (comp (ref "C78")
      (value "22u 10V")
      (footprint "eagle-import:C0805")
      (fields
        (field (name "MANUFACTURER") "free choice")
        (field (name "TOLERANCE") "±20 %")
        (field (name "VOLTAGE") "10.0 V")
      )
      (libsource (lib "eagle-import") (part "C-EU-C0805-22U"))
    )
    (comp (ref "C100")
      (value "1u 25V")
      (footprint "eagle-import:C0603")
      (fields
        (field (name "MANUFACTURER") "free choice")
        (field (name "TOLERANCE") "±20 %")
        (field (name "VOLTAGE") "25.0 V")
      )
      (libsource (lib "eagle-import") (part "C-EU-C0603-1U"))
    )
    (comp (ref "C101")
      (value "C-EU-C0603")
      (footprint "eagle-import:C0603")
      (fields (field (name "TOLERANCE") "±20 %") (field (name "VOLTAGE") "25.0 V"))
      (libsource (lib "eagle-import") (part "C-EU-C0603"))
    )
    (comp (ref "C102")
      (value "1u 25V")
      (footprint "eagle-import:C0603")
      (fields
        (field (name "MANUFACTURER") "free choice")
        (field (name "TOLERANCE") "±20 %")
        (field (name "VOLTAGE") "25.0 V")
      )
      (libsource (lib "eagle-import") (part "C-EU-C0603-1U"))
    )
    (comp (ref "C103")
      (value "C-EU-C0603")
      (footprint "eagle-import:C0603")
      (fields (field (name "TOLERANCE") "±20 %") (field (name "VOLTAGE") "25.0 V"))
      (libsource (lib "eagle-import") (part "C-EU-C0603"))
    )
    (comp (ref "C104")
      (value "1u 25V")
      (footprint "eagle-import:C0603")
      (fields
        (field (name "MANUFACTURER") "free choice")
        (field (name "TOLERANCE") "±20 %")
        (field (name "VOLTAGE") "25.0 V")
      )
      (libsource (lib "eagle-import") (part "C-EU-C0603-1U"))
    )
    (comp (ref "C105")
      (value "C-EU-C0603")
      (footprint "eagle-import:C0603")
      (fields (field (name "TOLERANCE") "±20 %") (field (name "VOLTAGE") "25.0 V"))
      (libsource (lib "eagle-import") (part "C-EU-C0603"))
    )
    (comp (ref "C106")
      (value "1u 25V")
      (footprint "eagle-import:C0603")
      (fields
        (field (name "MANUFACTURER") "free choice")
        (field (name "TOLERANCE") "±20 %")
        (field (name "VOLTAGE") "25.0 V")
      )
      (libsource (lib "eagle-import") (part "C-EU-C0603-1U"))
    )
    (comp (ref "C107")
      (value "C-EU-C0603")
      (footprint "eagle-import:C0603")
      (fields (field (name "TOLERANCE") "±20 %") (field (name "VOLTAGE") "25.0 V"))
      (libsource (lib "eagle-import") (part "C-EU-C0603"))
    )
    (comp (ref "C108")
      (value "1u 25V")
      (footprint "eagle-import:C0603")
      (fields
        (field (name "MANUFACTURER") "free choice")
        (field (name "TOLERANCE") "±20 %")
        (field (name "VOLTAGE") "25.0 V")
      )
      (libsource (lib "eagle-import") (part "C-EU-C0603-1U"))
    )
    (comp (ref "C109")
      (value "C-EU-C0603")
      (footprint "eagle-import:C0603")
      (fields (field (name "TOLERANCE") "±20 %") (field (name "VOLTAGE") "25.0 V"))
      (libsource (lib "eagle-import") (part "C-EU-C0603"))
    )
    (comp (ref "C110")
      (value "1u 25V")
      (footprint "eagle-import:C0603")
      (fields
        (field (name "MANUFACTURER") "free choice")
        (field (name "TOLERANCE") "±20 %")
        (field (name "VOLTAGE") "25.0 V")
      )
      (libsource (lib "eagle-import") (part "C-EU-C0603-1U"))
    )
    (comp (ref "C111")
      (value "C-EU-C0603")
      (footprint "eagle-import:C0603")
      (fields (field (name "TOLERANCE") "±20 %") (field (name "VOLTAGE") "25.0 V"))
      (libsource (lib "eagle-import") (part "C-EU-C0603"))
    )
    (comp (ref "C112")
      (value "1u 25V")
      (footprint "eagle-import:C0603")
      (fields
        (field (name "MANUFACTURER") "free choice")
        (field (name "TOLERANCE") "±20 %")
        (field (name "VOLTAGE") "25.0 V")
      )
      (libsource (lib "eagle-import") (part "C-EU-C0603-1U"))
    )
    (comp (ref "C113")
      (value "C-EU-C0603")
      (footprint "eagle-import:C0603")
      (fields (field (name "TOLERANCE") "±20 %") (field (name "VOLTAGE") "25.0 V"))
      (libsource (lib "eagle-import") (part "C-EU-C0603"))
    )
    (comp (ref "C114")
      (value "1u 25V")
      (footprint "eagle-import:C0603")
      (fields
        (field (name "MANUFACTURER") "free choice")
        (field (name "TOLERANCE") "±20 %")
        (field (name "VOLTAGE") "25.0 V")
      )
      (libsource (lib "eagle-import") (part "C-EU-C0603-1U"))
    )
    (comp (ref "C115")
      (value "C-EU-C0603")
      (footprint "eagle-import:C0603")
      (fields (field (name "TOLERANCE") "±20 %") (field (name "VOLTAGE") "25.0 V"))
      (libsource (lib "eagle-import") (part "C-EU-C0603"))
    )
    (comp (ref "C116")
      (value "1u 25V")
      (footprint "eagle-import:C0603")
      (fields
        (field (name "MANUFACTURER") "free choice")
        (field (name "TOLERANCE") "±20 %")
        (field (name "VOLTAGE") "25.0 V")
      )
      (libsource (lib "eagle-import") (part "C-EU-C0603-1U"))
    )
    (comp (ref "C117")
      (value "C-EU-C0603")
      (footprint "eagle-import:C0603")
      (fields (field (name "TOLERANCE") "±20 %") (field (name "VOLTAGE") "25.0 V"))
      (libsource (lib "eagle-import") (part "C-EU-C0603"))
    )
    (comp (ref "C118")
      (value "1u 25V")
      (footprint "eagle-import:C0603")
      (fields
        (field (name "MANUFACTURER") "free choice")
        (field (name "TOLERANCE") "±20 %")
        (field (name "VOLTAGE") "25.0 V")
      )
      (libsource (lib "eagle-import") (part "C-EU-C0603-1U"))
    )
    (comp (ref "C119")
      (value "C-EU-C0603")
      (footprint "eagle-import:C0603")
      (fields (field (name "TOLERANCE") "±20 %") (field (name "VOLTAGE") "25.0 V"))
      (libsource (lib "eagle-import") (part "C-EU-C0603"))
    )
    (comp (ref "C120")
      (value "1u 25V")
      (footprint "eagle-import:C0603")
      (fields
        (field (name "MANUFACTURER") "free choice")
        (field (name "TOLERANCE") "±20 %")
        (field (name "VOLTAGE") "25.0 V")
      )
      (libsource (lib "eagle-import") (part "C-EU-C0603-1U"))
    )
    (comp (ref "C121")
      (value "C-EU-C0603")
      (footprint "eagle-import:C0603")
      (fields (field (name "TOLERANCE") "±20 %") (field (name "VOLTAGE") "25.0 V"))
      (libsource (lib "eagle-import") (part "C-EU-C0603"))
    )
    (comp (ref "C122")
      (value "1u 25V")
      (footprint "eagle-import:C0603")
      (fields
        (field (name "MANUFACTURER") "free choice")
        (field (name "TOLERANCE") "±20 %")
        (field (name "VOLTAGE") "25.0 V")
      )
      (libsource (lib "eagle-import") (part "C-EU-C0603-1U"))
    )
    (comp (ref "C123")
      (value "C-EU-C0603")
      (footprint "eagle-import:C0603")
      (fields (field (name "TOLERANCE") "±20 %") (field (name "VOLTAGE") "25.0 V"))
      (libsource (lib "eagle-import") (part "C-EU-C0603"))
    )
    (comp (ref "C124")
      (value "1u 25V")
      (footprint "eagle-import:C0603")
      (fields
        (field (name "MANUFACTURER") "free choice")
        (field (name "TOLERANCE") "±20 %")
        (field (name "VOLTAGE") "25.0 V")
      )
      (libsource (lib "eagle-import") (part "C-EU-C0603-1U"))
    )
    (comp (ref "C125")
      (value "C-EU-C0603")
      (footprint "eagle-import:C0603")
      (fields (field (name "TOLERANCE") "±20 %") (field (name "VOLTAGE") "25.0 V"))
      (libsource (lib "eagle-import") (part "C-EU-C0603"))
    )
    (comp (ref "C126")
      (value "1u 25V")
      (footprint "eagle-import:C0603")
      (fields
        (field (name "MANUFACTURER") "free choice")
        (field (name "TOLERANCE") "±20 %")
        (field (name "VOLTAGE") "25.0 V")
      )
      (libsource (lib "eagle-import") (part "C-EU-C0603-1U"))
    )
    (comp (ref "C127")
      (value "C-EU-C0603")
      (footprint "eagle-import:C0603")
      (fields (field (name "TOLERANCE") "±20 %") (field (name "VOLTAGE") "25.0 V"))
      (libsource (lib "eagle-import") (part "C-EU-C0603"))
    )
    (comp (ref "C128")
      (value "1u 25V")
      (footprint "eagle-import:C0603")
      (fields
        (field (name "MANUFACTURER") "free choice")
        (field (name "TOLERANCE") "±20 %")
        (field (name "VOLTAGE") "25.0 V")
      )
      (libsource (lib "eagle-import") (part "C-EU-C0603-1U"))
    )
    (comp (ref "C129")
      (value "C-EU-C0603")
      (footprint "eagle-import:C0603")
      (fields (field (name "TOLERANCE") "±20 %") (field (name "VOLTAGE") "25.0 V"))
      (libsource (lib "eagle-import") (part "C-EU-C0603"))
    )
    (comp (ref "C130")
      (value "1u 25V")
      (footprint "eagle-import:C0603")
      (fields
        (field (name "MANUFACTURER") "free choice")
        (field (name "TOLERANCE") "±20 %")
        (field (name "VOLTAGE") "25.0 V")
      )
      (libsource (lib "eagle-import") (part "C-EU-C0603-1U"))
    )
    (comp (ref "C131")
      (value "C-EU-C0603")
      (footprint "eagle-import:C0603")
      (fields (field (name "TOLERANCE") "±20 %") (field (name "VOLTAGE") "25.0 V"))
      (libsource (lib "eagle-import") (part "C-EU-C0603"))
    )
    (comp (ref "C132")
      (value "1u 25V")
      (footprint "eagle-import:C0603")
      (fields
        (field (name "MANUFACTURER") "free choice")
        (field (name "TOLERANCE") "±20 %")
        (field (name "VOLTAGE") "25.0 V")
      )
      (libsource (lib "eagle-import") (part "C-EU-C0603-1U"))
    )
    (comp (ref "C133")
      (value "C-EU-C0603")
      (footprint "eagle-import:C0603")
      (fields (field (name "TOLERANCE") "±20 %") (field (name "VOLTAGE") "25.0 V"))
      (libsource (lib "eagle-import") (part "C-EU-C0603"))
    )
    (comp (ref "C134")
      (value "1u 25V")
      (footprint "eagle-import:C0603")
      (fields
        (field (name "MANUFACTURER") "free choice")
        (field (name "TOLERANCE") "±20 %")
        (field (name "VOLTAGE") "25.0 V")
      )
      (libsource (lib "eagle-import") (part "C-EU-C0603-1U"))
    )
    (comp (ref "C135")
      (value "C-EU-C0603")
      (footprint "eagle-import:C0603")
      (fields (field (name "TOLERANCE") "±20 %") (field (name "VOLTAGE") "25.0 V"))
      (libsource (lib "eagle-import") (part "C-EU-C0603"))
    )
    (comp (ref "C136")
      (value "1u 25V")
      (footprint "eagle-import:C0603")
      (fields
        (field (name "MANUFACTURER") "free choice")
        (field (name "TOLERANCE") "±20 %")
        (field (name "VOLTAGE") "25.0 V")
      )
      (libsource (lib "eagle-import") (part "C-EU-C0603-1U"))
    )
    (comp (ref "C137")
      (value "C-EU-C0603")
      (footprint "eagle-import:C0603")
      (fields (field (name "TOLERANCE") "±20 %") (field (name "VOLTAGE") "25.0 V"))
      (libsource (lib "eagle-import") (part "C-EU-C0603"))
    )
    (comp (ref "C138")
      (value "1u 25V")
      (footprint "eagle-import:C0603")
      (fields
        (field (name "MANUFACTURER") "free choice")
        (field (name "TOLERANCE") "±20 %")
        (field (name "VOLTAGE") "25.0 V")
      )
      (libsource (lib "eagle-import") (part "C-EU-C0603-1U"))
    )
    (comp (ref "C139")
      (value "C-EU-C0603")
      (footprint "eagle-import:C0603")
      (fields (field (name "TOLERANCE") "±20 %") (field (name "VOLTAGE") "25.0 V"))
      (libsource (lib "eagle-import") (part "C-EU-C0603"))
    )
    (comp (ref "C140")
      (value "1u 25V")
      (footprint "eagle-import:C0603")
      (fields
        (field (name "MANUFACTURER") "free choice")
        (field (name "TOLERANCE") "±20 %")
        (field (name "VOLTAGE") "25.0 V")
      )
      (libsource (lib "eagle-import") (part "C-EU-C0603-1U"))
    )
    (comp (ref "C141")
      (value "C-EU-C0603")
      (footprint "eagle-import:C0603")
      (fields (field (name "TOLERANCE") "±20 %") (field (name "VOLTAGE") "25.0 V"))
      (libsource (lib "eagle-import") (part "C-EU-C0603"))
    )
    (comp (ref "C142")
      (value "1u 25V")
      (footprint "eagle-import:C0603")
      (fields
        (field (name "MANUFACTURER") "free choice")
        (field (name "TOLERANCE") "±20 %")
        (field (name "VOLTAGE") "25.0 V")
      )
      (libsource (lib "eagle-import") (part "C-EU-C0603-1U"))
    )
    (comp (ref "C143")
      (value "C-EU-C0603")
      (footprint "eagle-import:C0603")
      (fields (field (name "TOLERANCE") "±20 %") (field (name "VOLTAGE") "25.0 V"))
      (libsource (lib "eagle-import") (part "C-EU-C0603"))
    )
    (comp (ref "C144")
      (value "1u 25V")
      (footprint "eagle-import:C0603")
      (fields
        (field (name "MANUFACTURER") "free choice")
        (field (name "TOLERANCE") "±20 %")
        (field (name "VOLTAGE") "25.0 V")
      )
      (libsource (lib "eagle-import") (part "C-EU-C0603-1U"))
    )
    (comp (ref "C145")
      (value "C-EU-C0603")
      (footprint "eagle-import:C0603")
      (fields (field (name "TOLERANCE") "±20 %") (field (name "VOLTAGE") "25.0 V"))
      (libsource (lib "eagle-import") (part "C-EU-C0603"))
    )
    (comp (ref "C146")
      (value "1u 25V")
      (footprint "eagle-import:C0603")
      (fields
        (field (name "MANUFACTURER") "free choice")
        (field (name "TOLERANCE") "±20 %")
        (field (name "VOLTAGE") "25.0 V")
      )
      (libsource (lib "eagle-import") (part "C-EU-C0603-1U"))
    )
    (comp (ref "C147")
      (value "C-EU-C0603")
      (footprint "eagle-import:C0603")
      (fields (field (name "TOLERANCE") "±20 %") (field (name "VOLTAGE") "25.0 V"))
      (libsource (lib "eagle-import") (part "C-EU-C0603"))
    )
    (comp (ref "C148")
      (value "1u 25V")
      (footprint "eagle-import:C0603")
      (fields
        (field (name "MANUFACTURER") "free choice")
        (field (name "TOLERANCE") "±20 %")
        (field (name "VOLTAGE") "25.0 V")
      )
      (libsource (lib "eagle-import") (part "C-EU-C0603-1U"))
    )
    (comp (ref "C149")
      (value "C-EU-C0603")
      (footprint "eagle-import:C0603")
      (fields (field (name "TOLERANCE") "±20 %") (field (name "VOLTAGE") "25.0 V"))
      (libsource (lib "eagle-import") (part "C-EU-C0603"))
    )
    (comp (ref "C150")
      (value "1u 25V")
      (footprint "eagle-import:C0603")
      (fields
        (field (name "MANUFACTURER") "free choice")
        (field (name "TOLERANCE") "±20 %")
        (field (name "VOLTAGE") "25.0 V")
      )
      (libsource (lib "eagle-import") (part "C-EU-C0603-1U"))
    )
    (comp (ref "C151")
      (value "C-EU-C0603")
      (footprint "eagle-import:C0603")
      (fields (field (name "TOLERANCE") "±20 %") (field (name "VOLTAGE") "25.0 V"))
      (libsource (lib "eagle-import") (part "C-EU-C0603"))
    )
    (comp (ref "C152")
      (value "1u 25V")
      (footprint "eagle-import:C0603")
      (fields
        (field (name "MANUFACTURER") "free choice")
        (field (name "TOLERANCE") "±20 %")
        (field (name "VOLTAGE") "25.0 V")
      )
      (libsource (lib "eagle-import") (part "C-EU-C0603-1U"))
    )
    (comp (ref "C153")
      (value "C-EU-C0603")
      (footprint "eagle-import:C0603")
      (fields (field (name "TOLERANCE") "±20 %") (field (name "VOLTAGE") "25.0 V"))
      (libsource (lib "eagle-import") (part "C-EU-C0603"))
    )
    (comp (ref "C154")
      (value "1u 25V")
      (footprint "eagle-import:C0603")
      (fields
        (field (name "MANUFACTURER") "free choice")
        (field (name "TOLERANCE") "±20 %")
        (field (name "VOLTAGE") "25.0 V")
      )
      (libsource (lib "eagle-import") (part "C-EU-C0603-1U"))
    )
    (comp (ref "C155")
      (value "C-EU-C0603")
      (footprint "eagle-import:C0603")
      (fields (field (name "TOLERANCE") "±20 %") (field (name "VOLTAGE") "25.0 V"))
      (libsource (lib "eagle-import") (part "C-EU-C0603"))
    )
    (comp (ref "C156")
      (value "1u 25V")
      (footprint "eagle-import:C0603")
      (fields
        (field (name "MANUFACTURER") "free choice")
        (field (name "TOLERANCE") "±20 %")
        (field (name "VOLTAGE") "25.0 V")
      )
      (libsource (lib "eagle-import") (part "C-EU-C0603-1U"))
    )
    (comp (ref "C157")
      (value "C-EU-C0603")
      (footprint "eagle-import:C0603")
      (fields (field (name "TOLERANCE") "±20 %") (field (name "VOLTAGE") "25.0 V"))
      (libsource (lib "eagle-import") (part "C-EU-C0603"))
    )
    (comp (ref "C158")
      (value "1u 25V")
      (footprint "eagle-import:C0603")
      (fields
        (field (name "MANUFACTURER") "free choice")
        (field (name "TOLERANCE") "±20 %")
        (field (name "VOLTAGE") "25.0 V")
      )
      (libsource (lib "eagle-import") (part "C-EU-C0603-1U"))
    )
    (comp (ref "C159")
      (value "C-EU-C0603")
      (footprint "eagle-import:C0603")
      (fields (field (name "TOLERANCE") "±20 %") (field (name "VOLTAGE") "25.0 V"))
      (libsource (lib "eagle-import") (part "C-EU-C0603"))
    )
    (comp (ref "C162")
      (value "1u 25V")
      (footprint "eagle-import:C0603")
      (fields
        (field (name "MANUFACTURER") "free choice")
        (field (name "TOLERANCE") "±20 %")
        (field (name "VOLTAGE") "25.0 V")
      )
      (libsource (lib "eagle-import") (part "C-EU-C0603-1U"))
    )
    (comp (ref "C164")
      (value "1u 25V")
      (footprint "eagle-import:C0603")
      (fields
        (field (name "MANUFACTURER") "free choice")
        (field (name "TOLERANCE") "±20 %")
        (field (name "VOLTAGE") "25.0 V")
      )
      (libsource (lib "eagle-import") (part "C-EU-C0603-1U"))
    )
    (comp (ref "C165")
      (value "C-EU-C0603")
      (footprint "eagle-import:C0603")
      (fields (field (name "TOLERANCE") "±20 %") (field (name "VOLTAGE") "25.0 V"))
      (libsource (lib "eagle-import") (part "C-EU-C0603"))
    )
    (comp (ref "C166")
      (value "1u 25V")
      (footprint "eagle-import:C0603")
      (fields
        (field (name "MANUFACTURER") "free choice")
        (field (name "TOLERANCE") "±20 %")
        (field (name "VOLTAGE") "25.0 V")
      )
      (libsource (lib "eagle-import") (part "C-EU-C0603-1U"))
    )
    (comp (ref "C167")
      (value "C-EU-C0603")
      (footprint "eagle-import:C0603")
      (fields (field (name "TOLERANCE") "±20 %") (field (name "VOLTAGE") "25.0 V"))
      (libsource (lib "eagle-import") (part "C-EU-C0603"))
    )
    (comp (ref "C168")
      (value "1u 25V")
      (footprint "eagle-import:C0603")
      (fields
        (field (name "MANUFACTURER") "free choice")
        (field (name "TOLERANCE") "±20 %")
        (field (name "VOLTAGE") "25.0 V")
      )
      (libsource (lib "eagle-import") (part "C-EU-C0603-1U"))
    )
    (comp (ref "C169")
      (value "C-EU-C0603")
      (footprint "eagle-import:C0603")
      (fields (field (name "TOLERANCE") "±20 %") (field (name "VOLTAGE") "25.0 V"))
      (libsource (lib "eagle-import") (part "C-EU-C0603"))
    )
    (comp (ref "C170")
      (value "1u 25V")
      (footprint "eagle-import:C0603")
      (fields
        (field (name "MANUFACTURER") "free choice")
        (field (name "TOLERANCE") "±20 %")
        (field (name "VOLTAGE") "25.0 V")
      )
      (libsource (lib "eagle-import") (part "C-EU-C0603-1U"))
    )
    (comp (ref "C171")
      (value "C-EU-C0603")
      (footprint "eagle-import:C0603")
      (fields (field (name "TOLERANCE") "±20 %") (field (name "VOLTAGE") "25.0 V"))
      (libsource (lib "eagle-import") (part "C-EU-C0603"))
    )
    (comp (ref "C172")
      (value "1u 25V")
      (footprint "eagle-import:C0603")
      (fields
        (field (name "MANUFACTURER") "free choice")
        (field (name "TOLERANCE") "±20 %")
        (field (name "VOLTAGE") "25.0 V")
      )
      (libsource (lib "eagle-import") (part "C-EU-C0603-1U"))
    )
    (comp (ref "C173")
      (value "C-EU-C0603")
      (footprint "eagle-import:C0603")
      (fields (field (name "TOLERANCE") "±20 %") (field (name "VOLTAGE") "25.0 V"))
      (libsource (lib "eagle-import") (part "C-EU-C0603"))
    )
    (comp (ref "C174")
      (value "1u 25V")
      (footprint "eagle-import:C0603")
      (fields
        (field (name "MANUFACTURER") "free choice")
        (field (name "TOLERANCE") "±20 %")
        (field (name "VOLTAGE") "25.0 V")
      )
      (libsource (lib "eagle-import") (part "C-EU-C0603-1U"))
    )
    (comp (ref "C175")
      (value "C-EU-C0603")
      (footprint "eagle-import:C0603")
      (fields (field (name "TOLERANCE") "±20 %") (field (name "VOLTAGE") "25.0 V"))
      (libsource (lib "eagle-import") (part "C-EU-C0603"))
    )
    (comp (ref "C176")
      (value "1u 25V")
      (footprint "eagle-import:C0603")
      (fields
        (field (name "MANUFACTURER") "free choice")
        (field (name "TOLERANCE") "±20 %")
        (field (name "VOLTAGE") "25.0 V")
      )
      (libsource (lib "eagle-import") (part "C-EU-C0603-1U"))
    )
    (comp (ref "C177")
      (value "C-EU-C0603")
      (footprint "eagle-import:C0603")
      (fields (field (name "TOLERANCE") "±20 %") (field (name "VOLTAGE") "25.0 V"))
      (libsource (lib "eagle-import") (part "C-EU-C0603"))
    )
    (comp (ref "C178")
      (value "1u 25V")
      (footprint "eagle-import:C0603")
      (fields
        (field (name "MANUFACTURER") "free choice")
        (field (name "TOLERANCE") "±20 %")
        (field (name "VOLTAGE") "25.0 V")
      )
      (libsource (lib "eagle-import") (part "C-EU-C0603-1U"))
    )
    (comp (ref "C179")
      (value "C-EU-C0603")
      (footprint "eagle-import:C0603")
      (fields (field (name "TOLERANCE") "±20 %") (field (name "VOLTAGE") "25.0 V"))
      (libsource (lib "eagle-import") (part "C-EU-C0603"))
    )
    (comp (ref "C180")
      (value "1u 25V")
      (footprint "eagle-import:C0603")
      (fields
        (field (name "MANUFACTURER") "free choice")
        (field (name "TOLERANCE") "±20 %")
        (field (name "VOLTAGE") "25.0 V")
      )
      (libsource (lib "eagle-import") (part "C-EU-C0603-1U"))
    )
    (comp (ref "C181")
      (value "C-EU-C0603")
      (footprint "eagle-import:C0603")
      (fields (field (name "TOLERANCE") "±20 %") (field (name "VOLTAGE") "25.0 V"))
      (libsource (lib "eagle-import") (part "C-EU-C0603"))
    )
    (comp (ref "C182")
      (value "1u 25V")
      (footprint "eagle-import:C0603")
      (fields
        (field (name "MANUFACTURER") "free choice")
        (field (name "TOLERANCE") "±20 %")
        (field (name "VOLTAGE") "25.0 V")
      )
      (libsource (lib "eagle-import") (part "C-EU-C0603-1U"))
    )
    (comp (ref "C183")
      (value "C-EU-C0603")
      (footprint "eagle-import:C0603")
      (fields (field (name "TOLERANCE") "±20 %") (field (name "VOLTAGE") "25.0 V"))
      (libsource (lib "eagle-import") (part "C-EU-C0603"))
    )
    (comp (ref "C184")
      (value "1u 25V")
      (footprint "eagle-import:C0603")
      (fields
        (field (name "MANUFACTURER") "free choice")
        (field (name "TOLERANCE") "±20 %")
        (field (name "VOLTAGE") "25.0 V")
      )
      (libsource (lib "eagle-import") (part "C-EU-C0603-1U"))
    )
    (comp (ref "C185")
      (value "C-EU-C0603")
      (footprint "eagle-import:C0603")
      (fields (field (name "TOLERANCE") "±20 %") (field (name "VOLTAGE") "25.0 V"))
      (libsource (lib "eagle-import") (part "C-EU-C0603"))
    )
    (comp (ref "C186")
      (value "1u 25V")
      (footprint "eagle-import:C0603")
      (fields
        (field (name "MANUFACTURER") "free choice")
        (field (name "TOLERANCE") "±20 %")
        (field (name "VOLTAGE") "25.0 V")
      )
      (libsource (lib "eagle-import") (part "C-EU-C0603-1U"))
    )
    (comp (ref "C187")
      (value "C-EU-C0603")
      (footprint "eagle-import:C0603")
      (fields (field (name "TOLERANCE") "±20 %") (field (name "VOLTAGE") "25.0 V"))
      (libsource (lib "eagle-import") (part "C-EU-C0603"))
    )
    (comp (ref "C188")
      (value "1u 25V")
      (footprint "eagle-import:C0603")
      (fields
        (field (name "MANUFACTURER") "free choice")
        (field (name "TOLERANCE") "±20 %")
        (field (name "VOLTAGE") "25.0 V")
      )
      (libsource (lib "eagle-import") (part "C-EU-C0603-1U"))
    )
    (comp (ref "C189")
      (value "C-EU-C0603")
      (footprint "eagle-import:C0603")
      (fields (field (name "TOLERANCE") "±20 %") (field (name "VOLTAGE") "25.0 V"))
      (libsource (lib "eagle-import") (part "C-EU-C0603"))
    )
    (comp (ref "C190")
      (value "1u 25V")
      (footprint "eagle-import:C0603")
      (fields
        (field (name "MANUFACTURER") "free choice")
        (field (name "TOLERANCE") "±20 %")
        (field (name "VOLTAGE") "25.0 V")
      )
      (libsource (lib "eagle-import") (part "C-EU-C0603-1U"))
    )
    (comp (ref "C191")
      (value "C-EU-C0603")
      (footprint "eagle-import:C0603")
      (fields (field (name "TOLERANCE") "±20 %") (field (name "VOLTAGE") "25.0 V"))
      (libsource (lib "eagle-import") (part "C-EU-C0603"))
    )
    (comp (ref "C192")
      (value "1u 25V")
      (footprint "eagle-import:C0603")
      (fields
        (field (name "MANUFACTURER") "free choice")
        (field (name "TOLERANCE") "±20 %")
        (field (name "VOLTAGE") "25.0 V")
      )
      (libsource (lib "eagle-import") (part "C-EU-C0603-1U"))
    )
    (comp (ref "C193")
      (value "C-EU-C0603")
      (footprint "eagle-import:C0603")
      (fields (field (name "TOLERANCE") "±20 %") (field (name "VOLTAGE") "25.0 V"))
      (libsource (lib "eagle-import") (part "C-EU-C0603"))
    )
    (comp (ref "C194")
      (value "1u 25V")
      (footprint "eagle-import:C0603")
      (fields
        (field (name "MANUFACTURER") "free choice")
        (field (name "TOLERANCE") "±20 %")
        (field (name "VOLTAGE") "25.0 V")
      )
      (libsource (lib "eagle-import") (part "C-EU-C0603-1U"))
    )
    (comp (ref "C195")
      (value "C-EU-C0603")
      (footprint "eagle-import:C0603")
      (fields (field (name "TOLERANCE") "±20 %") (field (name "VOLTAGE") "25.0 V"))
      (libsource (lib "eagle-import") (part "C-EU-C0603"))
    )
    (comp (ref "C196")
      (value "1u 25V")
      (footprint "eagle-import:C0603")
      (fields
        (field (name "MANUFACTURER") "free choice")
        (field (name "TOLERANCE") "±20 %")
        (field (name "VOLTAGE") "25.0 V")
      )
      (libsource (lib "eagle-import") (part "C-EU-C0603-1U"))
    )
    (comp (ref "C197")
      (value "C-EU-C0603")
      (footprint "eagle-import:C0603")
      (fields (field (name "TOLERANCE") "±20 %") (field (name "VOLTAGE") "25.0 V"))
      (libsource (lib "eagle-import") (part "C-EU-C0603"))
    )
    (comp (ref "C198")
      (value "1u 25V")
      (footprint "eagle-import:C0603")
      (fields
        (field (name "MANUFACTURER") "free choice")
        (field (name "TOLERANCE") "±20 %")
        (field (name "VOLTAGE") "25.0 V")
      )
      (libsource (lib "eagle-import") (part "C-EU-C0603-1U"))
    )
    (comp (ref "C199")
      (value "C-EU-C0603")
      (footprint "eagle-import:C0603")
      (fields (field (name "TOLERANCE") "±20 %") (field (name "VOLTAGE") "25.0 V"))
      (libsource (lib "eagle-import") (part "C-EU-C0603"))
    )
    (comp (ref "C200")
      (value "1u 25V")
      (footprint "eagle-import:C0603")
      (fields
        (field (name "MANUFACTURER") "free choice")
        (field (name "TOLERANCE") "±20 %")
        (field (name "VOLTAGE") "25.0 V")
      )
      (libsource (lib "eagle-import") (part "C-EU-C0603-1U"))
    )
    (comp (ref "C201")
      (value "C-EU-C0603")
      (footprint "eagle-import:C0603")
      (fields (field (name "TOLERANCE") "±20 %") (field (name "VOLTAGE") "25.0 V"))
      (libsource (lib "eagle-import") (part "C-EU-C0603"))
    )
    (comp (ref "C202")
      (value "1u 25V")
      (footprint "eagle-import:C0603")
      (fields
        (field (name "MANUFACTURER") "free choice")
        (field (name "TOLERANCE") "±20 %")
        (field (name "VOLTAGE") "25.0 V")
      )
      (libsource (lib "eagle-import") (part "C-EU-C0603-1U"))
    )
    (comp (ref "C203")
      (value "C-EU-C0603")
      (footprint "eagle-import:C0603")
      (fields (field (name "TOLERANCE") "±20 %") (field (name "VOLTAGE") "25.0 V"))
      (libsource (lib "eagle-import") (part "C-EU-C0603"))
    )
    (comp (ref "C204")
      (value "1u 25V")
      (footprint "eagle-import:C0603")
      (fields
        (field (name "MANUFACTURER") "free choice")
        (field (name "TOLERANCE") "±20 %")
        (field (name "VOLTAGE") "25.0 V")
      )
      (libsource (lib "eagle-import") (part "C-EU-C0603-1U"))
    )
    (comp (ref "C205")
      (value "C-EU-C0603")
      (footprint "eagle-import:C0603")
      (fields (field (name "TOLERANCE") "±20 %") (field (name "VOLTAGE") "25.0 V"))
      (libsource (lib "eagle-import") (part "C-EU-C0603"))
    )
    (comp (ref "C206")
      (value "1u 25V")
      (footprint "eagle-import:C0603")
      (fields
        (field (name "MANUFACTURER") "free choice")
        (field (name "TOLERANCE") "±20 %")
        (field (name "VOLTAGE") "25.0 V")
      )
      (libsource (lib "eagle-import") (part "C-EU-C0603-1U"))
    )
    (comp (ref "C207")
      (value "C-EU-C0603")
      (footprint "eagle-import:C0603")
      (fields (field (name "TOLERANCE") "±20 %") (field (name "VOLTAGE") "25.0 V"))
      (libsource (lib "eagle-import") (part "C-EU-C0603"))
    )
    (comp (ref "C208")
      (value "1u 25V")
      (footprint "eagle-import:C0603")
      (fields
        (field (name "MANUFACTURER") "free choice")
        (field (name "TOLERANCE") "±20 %")
        (field (name "VOLTAGE") "25.0 V")
      )
      (libsource (lib "eagle-import") (part "C-EU-C0603-1U"))
    )
    (comp (ref "C209")
      (value "C-EU-C0603")
      (footprint "eagle-import:C0603")
      (fields (field (name "TOLERANCE") "±20 %") (field (name "VOLTAGE") "25.0 V"))
      (libsource (lib "eagle-import") (part "C-EU-C0603"))
    )
    (comp (ref "C210")
      (value "1u 25V")
      (footprint "eagle-import:C0603")
      (fields
        (field (name "MANUFACTURER") "free choice")
        (field (name "TOLERANCE") "±20 %")
        (field (name "VOLTAGE") "25.0 V")
      )
      (libsource (lib "eagle-import") (part "C-EU-C0603-1U"))
    )
    (comp (ref "C211")
      (value "C-EU-C0603")
      (footprint "eagle-import:C0603")
      (fields (field (name "TOLERANCE") "±20 %") (field (name "VOLTAGE") "25.0 V"))
      (libsource (lib "eagle-import") (part "C-EU-C0603"))
    )
    (comp (ref "C212")
      (value "1u 25V")
      (footprint "eagle-import:C0603")
      (fields
        (field (name "MANUFACTURER") "free choice")
        (field (name "TOLERANCE") "±20 %")
        (field (name "VOLTAGE") "25.0 V")
      )
      (libsource (lib "eagle-import") (part "C-EU-C0603-1U"))
    )
    (comp (ref "C213")
      (value "C-EU-C0603")
      (footprint "eagle-import:C0603")
      (fields (field (name "TOLERANCE") "±20 %") (field (name "VOLTAGE") "25.0 V"))
      (libsource (lib "eagle-import") (part "C-EU-C0603"))
    )
    (comp (ref "C214")
      (value "1u 25V")
      (footprint "eagle-import:C0603")
      (fields
        (field (name "MANUFACTURER") "free choice")
        (field (name "TOLERANCE") "±20 %")
        (field (name "VOLTAGE") "25.0 V")
      )
      (libsource (lib "eagle-import") (part "C-EU-C0603-1U"))
    )
    (comp (ref "C215")
      (value "C-EU-C0603")
      (footprint "eagle-import:C0603")
      (fields (field (name "TOLERANCE") "±20 %") (field (name "VOLTAGE") "25.0 V"))
      (libsource (lib "eagle-import") (part "C-EU-C0603"))
    )
    (comp (ref "C216")
      (value "1u 25V")
      (footprint "eagle-import:C0603")
      (fields
        (field (name "MANUFACTURER") "free choice")
        (field (name "TOLERANCE") "±20 %")
        (field (name "VOLTAGE") "25.0 V")
      )
      (libsource (lib "eagle-import") (part "C-EU-C0603-1U"))
    )
    (comp (ref "C217")
      (value "C-EU-C0603")
      (footprint "eagle-import:C0603")
      (fields (field (name "TOLERANCE") "±20 %") (field (name "VOLTAGE") "25.0 V"))
      (libsource (lib "eagle-import") (part "C-EU-C0603"))
    )
    (comp (ref "C218")
      (value "1u 25V")
      (footprint "eagle-import:C0603")
      (fields
        (field (name "MANUFACTURER") "free choice")
        (field (name "TOLERANCE") "±20 %")
        (field (name "VOLTAGE") "25.0 V")
      )
      (libsource (lib "eagle-import") (part "C-EU-C0603-1U"))
    )
    (comp (ref "C219")
      (value "C-EU-C0603")
      (footprint "eagle-import:C0603")
      (fields (field (name "TOLERANCE") "±20 %") (field (name "VOLTAGE") "25.0 V"))
      (libsource (lib "eagle-import") (part "C-EU-C0603"))
    )
    (comp (ref "C220")
      (value "1u 25V")
      (footprint "eagle-import:C0603")
      (fields
        (field (name "MANUFACTURER") "free choice")
        (field (name "TOLERANCE") "±20 %")
        (field (name "VOLTAGE") "25.0 V")
      )
      (libsource (lib "eagle-import") (part "C-EU-C0603-1U"))
    )
    (comp (ref "C221")
      (value "C-EU-C0603")
      (footprint "eagle-import:C0603")
      (fields (field (name "TOLERANCE") "±20 %") (field (name "VOLTAGE") "25.0 V"))
      (libsource (lib "eagle-import") (part "C-EU-C0603"))
    )
    (comp (ref "C222")
      (value "1u 25V")
      (footprint "eagle-import:C0603")
      (fields
        (field (name "MANUFACTURER") "free choice")
        (field (name "TOLERANCE") "±20 %")
        (field (name "VOLTAGE") "25.0 V")
      )
      (libsource (lib "eagle-import") (part "C-EU-C0603-1U"))
    )
    (comp (ref "C223")
      (value "C-EU-C0603")
      (footprint "eagle-import:C0603")
      (fields (field (name "TOLERANCE") "±20 %") (field (name "VOLTAGE") "25.0 V"))
      (libsource (lib "eagle-import") (part "C-EU-C0603"))
    )
    (comp (ref "C224")
      (value "1u 25V")
      (footprint "eagle-import:C0603")
      (fields
        (field (name "MANUFACTURER") "free choice")
        (field (name "TOLERANCE") "±20 %")
        (field (name "VOLTAGE") "25.0 V")
      )
      (libsource (lib "eagle-import") (part "C-EU-C0603-1U"))
    )
    (comp (ref "C225")
      (value "C-EU-C0603")
      (footprint "eagle-import:C0603")
      (fields (field (name "TOLERANCE") "±20 %") (field (name "VOLTAGE") "25.0 V"))
      (libsource (lib "eagle-import") (part "C-EU-C0603"))
    )
    (comp (ref "C226")
      (value "1u 25V")
      (footprint "eagle-import:C0603")
      (fields
        (field (name "MANUFACTURER") "free choice")
        (field (name "TOLERANCE") "±20 %")
        (field (name "VOLTAGE") "25.0 V")
      )
      (libsource (lib "eagle-import") (part "C-EU-C0603-1U"))
    )
    (comp (ref "C227")
      (value "C-EU-C0603")
      (footprint "eagle-import:C0603")
      (fields (field (name "TOLERANCE") "±20 %") (field (name "VOLTAGE") "25.0 V"))
      (libsource (lib "eagle-import") (part "C-EU-C0603"))
    )
    (comp (ref "C228")
      (value "1u 25V")
      (footprint "eagle-import:C0603")
      (fields
        (field (name "MANUFACTURER") "free choice")
        (field (name "TOLERANCE") "±20 %")
        (field (name "VOLTAGE") "25.0 V")
      )
      (libsource (lib "eagle-import") (part "C-EU-C0603-1U"))
    )
    (comp (ref "C229")
      (value "C-EU-C0603")
      (footprint "eagle-import:C0603")
      (fields (field (name "TOLERANCE") "±20 %") (field (name "VOLTAGE") "25.0 V"))
      (libsource (lib "eagle-import") (part "C-EU-C0603"))
    )
    (comp (ref "C230")
      (value "1u 25V")
      (footprint "eagle-import:C0603")
      (fields
        (field (name "MANUFACTURER") "free choice")
        (field (name "TOLERANCE") "±20 %")
        (field (name "VOLTAGE") "25.0 V")
      )
      (libsource (lib "eagle-import") (part "C-EU-C0603-1U"))
    )
    (comp (ref "C231")
      (value "C-EU-C0603")
      (footprint "eagle-import:C0603")
      (fields (field (name "TOLERANCE") "±20 %") (field (name "VOLTAGE") "25.0 V"))
      (libsource (lib "eagle-import") (part "C-EU-C0603"))
    )
    (comp (ref "C232")
      (value "1u 25V")
      (footprint "eagle-import:C0603")
      (fields
        (field (name "MANUFACTURER") "free choice")
        (field (name "TOLERANCE") "±20 %")
        (field (name "VOLTAGE") "25.0 V")
      )
      (libsource (lib "eagle-import") (part "C-EU-C0603-1U"))
    )
    (comp (ref "C233")
      (value "C-EU-C0603")
      (footprint "eagle-import:C0603")
      (fields (field (name "TOLERANCE") "±20 %") (field (name "VOLTAGE") "25.0 V"))
      (libsource (lib "eagle-import") (part "C-EU-C0603"))
    )
    (comp (ref "C234")
      (value "1u 25V")
      (footprint "eagle-import:C0603")
      (fields
        (field (name "MANUFACTURER") "free choice")
        (field (name "TOLERANCE") "±20 %")
        (field (name "VOLTAGE") "25.0 V")
      )
      (libsource (lib "eagle-import") (part "C-EU-C0603-1U"))
    )
    (comp (ref "C235")
      (value "C-EU-C0603")
      (footprint "eagle-import:C0603")
      (fields (field (name "TOLERANCE") "±20 %") (field (name "VOLTAGE") "25.0 V"))
      (libsource (lib "eagle-import") (part "C-EU-C0603"))
    )
    (comp (ref "C236")
      (value "1u 25V")
      (footprint "eagle-import:C0603")
      (fields
        (field (name "MANUFACTURER") "free choice")
        (field (name "TOLERANCE") "±20 %")
        (field (name "VOLTAGE") "25.0 V")
      )
      (libsource (lib "eagle-import") (part "C-EU-C0603-1U"))
    )
    (comp (ref "C237")
      (value "C-EU-C0603")
      (footprint "eagle-import:C0603")
      (fields (field (name "TOLERANCE") "±20 %") (field (name "VOLTAGE") "25.0 V"))
      (libsource (lib "eagle-import") (part "C-EU-C0603"))
    )
    (comp (ref "C238")
      (value "1u 25V")
      (footprint "eagle-import:C0603")
      (fields
        (field (name "MANUFACTURER") "free choice")
        (field (name "TOLERANCE") "±20 %")
        (field (name "VOLTAGE") "25.0 V")
      )
      (libsource (lib "eagle-import") (part "C-EU-C0603-1U"))
    )
    (comp (ref "C239")
      (value "C-EU-C0603")
      (footprint "eagle-import:C0603")
      (fields (field (name "TOLERANCE") "±20 %") (field (name "VOLTAGE") "25.0 V"))
      (libsource (lib "eagle-import") (part "C-EU-C0603"))
    )
    (comp (ref "C240")
      (value "1u 25V")
      (footprint "eagle-import:C0603")
      (fields
        (field (name "MANUFACTURER") "free choice")
        (field (name "TOLERANCE") "±20 %")
        (field (name "VOLTAGE") "25.0 V")
      )
      (libsource (lib "eagle-import") (part "C-EU-C0603-1U"))
    )
    (comp (ref "C241")
      (value "C-EU-C0603")
      (footprint "eagle-import:C0603")
      (fields (field (name "TOLERANCE") "±20 %") (field (name "VOLTAGE") "25.0 V"))
      (libsource (lib "eagle-import") (part "C-EU-C0603"))
    )
    (comp (ref "C242")
      (value "1u 25V")
      (footprint "eagle-import:C0603")
      (fields
        (field (name "MANUFACTURER") "free choice")
        (field (name "TOLERANCE") "±20 %")
        (field (name "VOLTAGE") "25.0 V")
      )
      (libsource (lib "eagle-import") (part "C-EU-C0603-1U"))
    )
    (comp (ref "C243")
      (value "C-EU-C0603")
      (footprint "eagle-import:C0603")
      (fields (field (name "TOLERANCE") "±20 %") (field (name "VOLTAGE") "25.0 V"))
      (libsource (lib "eagle-import") (part "C-EU-C0603"))
    )
    (comp (ref "C244")
      (value "1u 25V")
      (footprint "eagle-import:C0603")
      (fields
        (field (name "MANUFACTURER") "free choice")
        (field (name "TOLERANCE") "±20 %")
        (field (name "VOLTAGE") "25.0 V")
      )
      (libsource (lib "eagle-import") (part "C-EU-C0603-1U"))
    )
    (comp (ref "C245")
      (value "C-EU-C0603")
      (footprint "eagle-import:C0603")
      (fields (field (name "TOLERANCE") "±20 %") (field (name "VOLTAGE") "25.0 V"))
      (libsource (lib "eagle-import") (part "C-EU-C0603"))
    )
    (comp (ref "C246")
      (value "1u 25V")
      (footprint "eagle-import:C0603")
      (fields
        (field (name "MANUFACTURER") "free choice")
        (field (name "TOLERANCE") "±20 %")
        (field (name "VOLTAGE") "25.0 V")
      )
      (libsource (lib "eagle-import") (part "C-EU-C0603-1U"))
    )
    (comp (ref "C247")
      (value "C-EU-C0603")
      (footprint "eagle-import:C0603")
      (fields (field (name "TOLERANCE") "±20 %") (field (name "VOLTAGE") "25.0 V"))
      (libsource (lib "eagle-import") (part "C-EU-C0603"))
    )
    (comp (ref "C248")
      (value "1u 25V")
      (footprint "eagle-import:C0603")
      (fields
        (field (name "MANUFACTURER") "free choice")
        (field (name "TOLERANCE") "±20 %")
        (field (name "VOLTAGE") "25.0 V")
      )
      (libsource (lib "eagle-import") (part "C-EU-C0603-1U"))
    )
    (comp (ref "C249")
      (value "C-EU-C0603")
      (footprint "eagle-import:C0603")
      (fields (field (name "TOLERANCE") "±20 %") (field (name "VOLTAGE") "25.0 V"))
      (libsource (lib "eagle-import") (part "C-EU-C0603"))
    )
    (comp (ref "C250")
      (value "1u 25V")
      (footprint "eagle-import:C0603")
      (fields
        (field (name "MANUFACTURER") "free choice")
        (field (name "TOLERANCE") "±20 %")
        (field (name "VOLTAGE") "25.0 V")
      )
      (libsource (lib "eagle-import") (part "C-EU-C0603-1U"))
    )
    (comp (ref "C251")
      (value "C-EU-C0603")
      (footprint "eagle-import:C0603")
      (fields (field (name "TOLERANCE") "±20 %") (field (name "VOLTAGE") "25.0 V"))
      (libsource (lib "eagle-import") (part "C-EU-C0603"))
    )
    (comp (ref "C252")
      (value "1u 25V")
      (footprint "eagle-import:C0603")
      (fields
        (field (name "MANUFACTURER") "free choice")
        (field (name "TOLERANCE") "±20 %")
        (field (name "VOLTAGE") "25.0 V")
      )
      (libsource (lib "eagle-import") (part "C-EU-C0603-1U"))
    )
    (comp (ref "C253")
      (value "C-EU-C0603")
      (footprint "eagle-import:C0603")
      (fields (field (name "TOLERANCE") "±20 %") (field (name "VOLTAGE") "25.0 V"))
      (libsource (lib "eagle-import") (part "C-EU-C0603"))
    )
    (comp (ref "C254")
      (value "1u 25V")
      (footprint "eagle-import:C0603")
      (fields
        (field (name "MANUFACTURER") "free choice")
        (field (name "TOLERANCE") "±20 %")
        (field (name "VOLTAGE") "25.0 V")
      )
      (libsource (lib "eagle-import") (part "C-EU-C0603-1U"))
    )
    (comp (ref "C255")
      (value "C-EU-C0603")
      (footprint "eagle-import:C0603")
      (fields (field (name "TOLERANCE") "±20 %") (field (name "VOLTAGE") "25.0 V"))
      (libsource (lib "eagle-import") (part "C-EU-C0603"))
    )
    (comp (ref "C256")
      (value "1u 25V")
      (footprint "eagle-import:C0603")
      (fields
        (field (name "MANUFACTURER") "free choice")
        (field (name "TOLERANCE") "±20 %")
        (field (name "VOLTAGE") "25.0 V")
      )
      (libsource (lib "eagle-import") (part "C-EU-C0603-1U"))
    )
    (comp (ref "C257")
      (value "C-EU-C0603")
      (footprint "eagle-import:C0603")
      (fields (field (name "TOLERANCE") "±20 %") (field (name "VOLTAGE") "25.0 V"))
      (libsource (lib "eagle-import") (part "C-EU-C0603"))
    )
    (comp (ref "C258")
      (value "1u 25V")
      (footprint "eagle-import:C0603")
      (fields
        (field (name "MANUFACTURER") "free choice")
        (field (name "TOLERANCE") "±20 %")
        (field (name "VOLTAGE") "25.0 V")
      )
      (libsource (lib "eagle-import") (part "C-EU-C0603-1U"))
    )
    (comp (ref "C259")
      (value "C-EU-C0603")
      (footprint "eagle-import:C0603")
      (fields (field (name "TOLERANCE") "±20 %") (field (name "VOLTAGE") "25.0 V"))
      (libsource (lib "eagle-import") (part "C-EU-C0603"))
    )
    (comp (ref "C260")
      (value "1u 25V")
      (footprint "eagle-import:C0603")
      (fields
        (field (name "MANUFACTURER") "free choice")
        (field (name "TOLERANCE") "±20 %")
        (field (name "VOLTAGE") "25.0 V")
      )
      (libsource (lib "eagle-import") (part "C-EU-C0603-1U"))
    )
    (comp (ref "C261")
      (value "C-EU-C0603")
      (footprint "eagle-import:C0603")
      (fields (field (name "TOLERANCE") "±20 %") (field (name "VOLTAGE") "25.0 V"))
      (libsource (lib "eagle-import") (part "C-EU-C0603"))
    )
    (comp (ref "C262")
      (value "1u 25V")
      (footprint "eagle-import:C0603")
      (fields
        (field (name "MANUFACTURER") "free choice")
        (field (name "TOLERANCE") "±20 %")
        (field (name "VOLTAGE") "25.0 V")
      )
      (libsource (lib "eagle-import") (part "C-EU-C0603-1U"))
    )
    (comp (ref "C263")
      (value "C-EU-C0603")
      (footprint "eagle-import:C0603")
      (fields (field (name "TOLERANCE") "±20 %") (field (name "VOLTAGE") "25.0 V"))
      (libsource (lib "eagle-import") (part "C-EU-C0603"))
    )
    (comp (ref "C264")
      (value "1u 25V")
      (footprint "eagle-import:C0603")
      (fields
        (field (name "MANUFACTURER") "free choice")
        (field (name "TOLERANCE") "±20 %")
        (field (name "VOLTAGE") "25.0 V")
      )
      (libsource (lib "eagle-import") (part "C-EU-C0603-1U"))
    )
    (comp (ref "C265")
      (value "C-EU-C0603")
      (footprint "eagle-import:C0603")
      (fields (field (name "TOLERANCE") "±20 %") (field (name "VOLTAGE") "25.0 V"))
      (libsource (lib "eagle-import") (part "C-EU-C0603"))
    )
    (comp (ref "C266")
      (value "1u 25V")
      (footprint "eagle-import:C0603")
      (fields
        (field (name "MANUFACTURER") "free choice")
        (field (name "TOLERANCE") "±20 %")
        (field (name "VOLTAGE") "25.0 V")
      )
      (libsource (lib "eagle-import") (part "C-EU-C0603-1U"))
    )
    (comp (ref "C270")
      (value "1u 25V")
      (footprint "eagle-import:C0603")
      (fields
        (field (name "MANUFACTURER") "free choice")
        (field (name "TOLERANCE") "±20 %")
        (field (name "VOLTAGE") "25.0 V")
      )
      (libsource (lib "eagle-import") (part "C-EU-C0603-1U"))
    )
    (comp (ref "C272")
      (value "1u 25V")
      (footprint "eagle-import:C0603")
      (fields
        (field (name "MANUFACTURER") "free choice")
        (field (name "TOLERANCE") "±20 %")
        (field (name "VOLTAGE") "25.0 V")
      )
      (libsource (lib "eagle-import") (part "C-EU-C0603-1U"))
    )
    (comp (ref "C280")
      (value "1u 25V")
      (footprint "eagle-import:C0603")
      (fields
        (field (name "MANUFACTURER") "free choice")
        (field (name "TOLERANCE") "±20 %")
        (field (name "VOLTAGE") "25.0 V")
      )
      (libsource (lib "eagle-import") (part "C-EU-C0603-1U"))
    )
    (comp (ref "C281")
      (value "C-EU-C0603")
      (footprint "eagle-import:C0603")
      (fields (field (name "TOLERANCE") "±20 %") (field (name "VOLTAGE") "25.0 V"))
      (libsource (lib "eagle-import") (part "C-EU-C0603"))
    )
    (comp (ref "C282")
      (value "1u 25V")
      (footprint "eagle-import:C0603")
      (fields
        (field (name "MANUFACTURER") "free choice")
        (field (name "TOLERANCE") "±20 %")
        (field (name "VOLTAGE") "25.0 V")
      )
      (libsource (lib "eagle-import") (part "C-EU-C0603-1U"))
    )
    (comp (ref "C283")
      (value "C-EU-C0603")
      (footprint "eagle-import:C0603")
      (fields (field (name "TOLERANCE") "±20 %") (field (name "VOLTAGE") "25.0 V"))
      (libsource (lib "eagle-import") (part "C-EU-C0603"))
    )
    (comp (ref "C284")
      (value "1u 25V")
      (footprint "eagle-import:C0603")
      (fields
        (field (name "MANUFACTURER") "free choice")
        (field (name "TOLERANCE") "±20 %")
        (field (name "VOLTAGE") "25.0 V")
      )
      (libsource (lib "eagle-import") (part "C-EU-C0603-1U"))
    )
    (comp (ref "C285")
      (value "C-EU-C0603")
      (footprint "eagle-import:C0603")
      (fields (field (name "TOLERANCE") "±20 %") (field (name "VOLTAGE") "25.0 V"))
      (libsource (lib "eagle-import") (part "C-EU-C0603"))
    )
    (comp (ref "C286")
      (value "1u 25V")
      (footprint "eagle-import:C0603")
      (fields
        (field (name "MANUFACTURER") "free choice")
        (field (name "TOLERANCE") "±20 %")
        (field (name "VOLTAGE") "25.0 V")
      )
      (libsource (lib "eagle-import") (part "C-EU-C0603-1U"))
    )
    (comp (ref "C287")
      (value "C-EU-C0603")
      (footprint "eagle-import:C0603")
      (fields (field (name "TOLERANCE") "±20 %") (field (name "VOLTAGE") "25.0 V"))
      (libsource (lib "eagle-import") (part "C-EU-C0603"))
    )
    (comp (ref "C288")
      (value "1u 25V")
      (footprint "eagle-import:C0603")
      (fields
        (field (name "MANUFACTURER") "free choice")
        (field (name "TOLERANCE") "±20 %")
        (field (name "VOLTAGE") "25.0 V")
      )
      (libsource (lib "eagle-import") (part "C-EU-C0603-1U"))
    )
    (comp (ref "C289")
      (value "C-EU-C0603")
      (footprint "eagle-import:C0603")
      (fields (field (name "TOLERANCE") "±20 %") (field (name "VOLTAGE") "25.0 V"))
      (libsource (lib "eagle-import") (part "C-EU-C0603"))
    )
    (comp (ref "C290")
      (value "1u 25V")
      (footprint "eagle-import:C0603")
      (fields
        (field (name "MANUFACTURER") "free choice")
        (field (name "TOLERANCE") "±20 %")
        (field (name "VOLTAGE") "25.0 V")
      )
      (libsource (lib "eagle-import") (part "C-EU-C0603-1U"))
    )
    (comp (ref "C291")
      (value "C-EU-C0603")
      (footprint "eagle-import:C0603")
      (fields (field (name "TOLERANCE") "±20 %") (field (name "VOLTAGE") "25.0 V"))
      (libsource (lib "eagle-import") (part "C-EU-C0603"))
    )
    (comp (ref "C292")
      (value "1u 25V")
      (footprint "eagle-import:C0603")
      (fields
        (field (name "MANUFACTURER") "free choice")
        (field (name "TOLERANCE") "±20 %")
        (field (name "VOLTAGE") "25.0 V")
      )
      (libsource (lib "eagle-import") (part "C-EU-C0603-1U"))
    )
    (comp (ref "C293")
      (value "C-EU-C0603")
      (footprint "eagle-import:C0603")
      (fields (field (name "TOLERANCE") "±20 %") (field (name "VOLTAGE") "25.0 V"))
      (libsource (lib "eagle-import") (part "C-EU-C0603"))
    )
    (comp (ref "C294")
      (value "1u 25V")
      (footprint "eagle-import:C0603")
      (fields
        (field (name "MANUFACTURER") "free choice")
        (field (name "TOLERANCE") "±20 %")
        (field (name "VOLTAGE") "25.0 V")
      )
      (libsource (lib "eagle-import") (part "C-EU-C0603-1U"))
    )
    (comp (ref "C295")
      (value "C-EU-C0603")
      (footprint "eagle-import:C0603")
      (fields (field (name "TOLERANCE") "±20 %") (field (name "VOLTAGE") "25.0 V"))
      (libsource (lib "eagle-import") (part "C-EU-C0603"))
    )
    (comp (ref "C296")
      (value "1u 25V")
      (footprint "eagle-import:C0603")
      (fields
        (field (name "MANUFACTURER") "free choice")
        (field (name "TOLERANCE") "±20 %")
        (field (name "VOLTAGE") "25.0 V")
      )
      (libsource (lib "eagle-import") (part "C-EU-C0603-1U"))
    )
    (comp (ref "C297")
      (value "C-EU-C0603")
      (footprint "eagle-import:C0603")
      (fields (field (name "TOLERANCE") "±20 %") (field (name "VOLTAGE") "25.0 V"))
      (libsource (lib "eagle-import") (part "C-EU-C0603"))
    )
    (comp (ref "C298")
      (value "1u 25V")
      (footprint "eagle-import:C0603")
      (fields
        (field (name "MANUFACTURER") "free choice")
        (field (name "TOLERANCE") "±20 %")
        (field (name "VOLTAGE") "25.0 V")
      )
      (libsource (lib "eagle-import") (part "C-EU-C0603-1U"))
    )
    (comp (ref "C299")
      (value "C-EU-C0603")
      (footprint "eagle-import:C0603")
      (fields (field (name "TOLERANCE") "±20 %") (field (name "VOLTAGE") "25.0 V"))
      (libsource (lib "eagle-import") (part "C-EU-C0603"))
    )
    (comp (ref "C300")
      (value "1u 25V")
      (footprint "eagle-import:C0603")
      (fields
        (field (name "MANUFACTURER") "free choice")
        (field (name "TOLERANCE") "±20 %")
        (field (name "VOLTAGE") "25.0 V")
      )
      (libsource (lib "eagle-import") (part "C-EU-C0603-1U"))
    )
    (comp (ref "C301")
      (value "C-EU-C0603")
      (footprint "eagle-import:C0603")
      (fields (field (name "TOLERANCE") "±20 %") (field (name "VOLTAGE") "25.0 V"))
      (libsource (lib "eagle-import") (part "C-EU-C0603"))
    )
    (comp (ref "C302")
      (value "1u 25V")
      (footprint "eagle-import:C0603")
      (fields
        (field (name "MANUFACTURER") "free choice")
        (field (name "TOLERANCE") "±20 %")
        (field (name "VOLTAGE") "25.0 V")
      )
      (libsource (lib "eagle-import") (part "C-EU-C0603-1U"))
    )
    (comp (ref "C303")
      (value "C-EU-C0603")
      (footprint "eagle-import:C0603")
      (fields (field (name "TOLERANCE") "±20 %") (field (name "VOLTAGE") "25.0 V"))
      (libsource (lib "eagle-import") (part "C-EU-C0603"))
    )
    (comp (ref "C304")
      (value "1u 25V")
      (footprint "eagle-import:C0603")
      (fields
        (field (name "MANUFACTURER") "free choice")
        (field (name "TOLERANCE") "±20 %")
        (field (name "VOLTAGE") "25.0 V")
      )
      (libsource (lib "eagle-import") (part "C-EU-C0603-1U"))
    )
    (comp (ref "C305")
      (value "C-EU-C0603")
      (footprint "eagle-import:C0603")
      (fields (field (name "TOLERANCE") "±20 %") (field (name "VOLTAGE") "25.0 V"))
      (libsource (lib "eagle-import") (part "C-EU-C0603"))
    )
    (comp (ref "C306")
      (value "1u 25V")
      (footprint "eagle-import:C0603")
      (fields
        (field (name "MANUFACTURER") "free choice")
        (field (name "TOLERANCE") "±20 %")
        (field (name "VOLTAGE") "25.0 V")
      )
      (libsource (lib "eagle-import") (part "C-EU-C0603-1U"))
    )
    (comp (ref "C307")
      (value "C-EU-C0603")
      (footprint "eagle-import:C0603")
      (fields (field (name "TOLERANCE") "±20 %") (field (name "VOLTAGE") "25.0 V"))
      (libsource (lib "eagle-import") (part "C-EU-C0603"))
    )
    (comp (ref "C308")
      (value "1u 25V")
      (footprint "eagle-import:C0603")
      (fields
        (field (name "MANUFACTURER") "free choice")
        (field (name "TOLERANCE") "±20 %")
        (field (name "VOLTAGE") "25.0 V")
      )
      (libsource (lib "eagle-import") (part "C-EU-C0603-1U"))
    )
    (comp (ref "C309")
      (value "C-EU-C0603")
      (footprint "eagle-import:C0603")
      (fields (field (name "TOLERANCE") "±20 %") (field (name "VOLTAGE") "25.0 V"))
      (libsource (lib "eagle-import") (part "C-EU-C0603"))
    )
    (comp (ref "C310")
      (value "1u 25V")
      (footprint "eagle-import:C0603")
      (fields
        (field (name "MANUFACTURER") "free choice")
        (field (name "TOLERANCE") "±20 %")
        (field (name "VOLTAGE") "25.0 V")
      )
      (libsource (lib "eagle-import") (part "C-EU-C0603-1U"))
    )
    (comp (ref "C311")
      (value "C-EU-C0603")
      (footprint "eagle-import:C0603")
      (fields (field (name "TOLERANCE") "±20 %") (field (name "VOLTAGE") "25.0 V"))
      (libsource (lib "eagle-import") (part "C-EU-C0603"))
    )
    (comp (ref "C312")
      (value "1u 25V")
      (footprint "eagle-import:C0603")
      (fields
        (field (name "MANUFACTURER") "free choice")
        (field (name "TOLERANCE") "±20 %")
        (field (name "VOLTAGE") "25.0 V")
      )
      (libsource (lib "eagle-import") (part "C-EU-C0603-1U"))
    )
    (comp (ref "C313")
      (value "C-EU-C0603")
      (footprint "eagle-import:C0603")
      (fields (field (name "TOLERANCE") "±20 %") (field (name "VOLTAGE") "25.0 V"))
      (libsource (lib "eagle-import") (part "C-EU-C0603"))
    )
    (comp (ref "C314")
      (value "1u 25V")
      (footprint "eagle-import:C0603")
      (fields
        (field (name "MANUFACTURER") "free choice")
        (field (name "TOLERANCE") "±20 %")
        (field (name "VOLTAGE") "25.0 V")
      )
      (libsource (lib "eagle-import") (part "C-EU-C0603-1U"))
    )
    (comp (ref "C315")
      (value "C-EU-C0603")
      (footprint "eagle-import:C0603")
      (fields (field (name "TOLERANCE") "±20 %") (field (name "VOLTAGE") "25.0 V"))
      (libsource (lib "eagle-import") (part "C-EU-C0603"))
    )
    (comp (ref "C316")
      (value "1u 25V")
      (footprint "eagle-import:C0603")
      (fields
        (field (name "MANUFACTURER") "free choice")
        (field (name "TOLERANCE") "±20 %")
        (field (name "VOLTAGE") "25.0 V")
      )
      (libsource (lib "eagle-import") (part "C-EU-C0603-1U"))
    )
    (comp (ref "C317")
      (value "C-EU-C0603")
      (footprint "eagle-import:C0603")
      (fields (field (name "TOLERANCE") "±20 %") (field (name "VOLTAGE") "25.0 V"))
      (libsource (lib "eagle-import") (part "C-EU-C0603"))
    )
    (comp (ref "C318")
      (value "1u 25V")
      (footprint "eagle-import:C0603")
      (fields
        (field (name "MANUFACTURER") "free choice")
        (field (name "TOLERANCE") "±20 %")
        (field (name "VOLTAGE") "25.0 V")
      )
      (libsource (lib "eagle-import") (part "C-EU-C0603-1U"))
    )
    (comp (ref "C319")
      (value "C-EU-C0603")
      (footprint "eagle-import:C0603")
      (fields (field (name "TOLERANCE") "±20 %") (field (name "VOLTAGE") "25.0 V"))
      (libsource (lib "eagle-import") (part "C-EU-C0603"))
    )
    (comp (ref "C320")
      (value "1u 25V")
      (footprint "eagle-import:C0603")
      (fields
        (field (name "MANUFACTURER") "free choice")
        (field (name "TOLERANCE") "±20 %")
        (field (name "VOLTAGE") "25.0 V")
      )
      (libsource (lib "eagle-import") (part "C-EU-C0603-1U"))
    )
    (comp (ref "C321")
      (value "C-EU-C0603")
      (footprint "eagle-import:C0603")
      (fields (field (name "TOLERANCE") "±20 %") (field (name "VOLTAGE") "25.0 V"))
      (libsource (lib "eagle-import") (part "C-EU-C0603"))
    )
    (comp (ref "C322")
      (value "1u 25V")
      (footprint "eagle-import:C0603")
      (fields
        (field (name "MANUFACTURER") "free choice")
        (field (name "TOLERANCE") "±20 %")
        (field (name "VOLTAGE") "25.0 V")
      )
      (libsource (lib "eagle-import") (part "C-EU-C0603-1U"))
    )
    (comp (ref "C323")
      (value "C-EU-C0603")
      (footprint "eagle-import:C0603")
      (fields (field (name "TOLERANCE") "±20 %") (field (name "VOLTAGE") "25.0 V"))
      (libsource (lib "eagle-import") (part "C-EU-C0603"))
    )
    (comp (ref "C324")
      (value "1u 25V")
      (footprint "eagle-import:C0603")
      (fields
        (field (name "MANUFACTURER") "free choice")
        (field (name "TOLERANCE") "±20 %")
        (field (name "VOLTAGE") "25.0 V")
      )
      (libsource (lib "eagle-import") (part "C-EU-C0603-1U"))
    )
    (comp (ref "C325")
      (value "C-EU-C0603")
      (footprint "eagle-import:C0603")
      (fields (field (name "TOLERANCE") "±20 %") (field (name "VOLTAGE") "25.0 V"))
      (libsource (lib "eagle-import") (part "C-EU-C0603"))
    )
    (comp (ref "C326")
      (value "1u 25V")
      (footprint "eagle-import:C0603")
      (fields
        (field (name "MANUFACTURER") "free choice")
        (field (name "TOLERANCE") "±20 %")
        (field (name "VOLTAGE") "25.0 V")
      )
      (libsource (lib "eagle-import") (part "C-EU-C0603-1U"))
    )
    (comp (ref "C327")
      (value "C-EU-C0603")
      (footprint "eagle-import:C0603")
      (fields (field (name "TOLERANCE") "±20 %") (field (name "VOLTAGE") "25.0 V"))
      (libsource (lib "eagle-import") (part "C-EU-C0603"))
    )
    (comp (ref "C328")
      (value "1u 25V")
      (footprint "eagle-import:C0603")
      (fields
        (field (name "MANUFACTURER") "free choice")
        (field (name "TOLERANCE") "±20 %")
        (field (name "VOLTAGE") "25.0 V")
      )
      (libsource (lib "eagle-import") (part "C-EU-C0603-1U"))
    )
    (comp (ref "C329")
      (value "C-EU-C0603")
      (footprint "eagle-import:C0603")
      (fields (field (name "TOLERANCE") "±20 %") (field (name "VOLTAGE") "25.0 V"))
      (libsource (lib "eagle-import") (part "C-EU-C0603"))
    )
    (comp (ref "C330")
      (value "1u 25V")
      (footprint "eagle-import:C0603")
      (fields
        (field (name "MANUFACTURER") "free choice")
        (field (name "TOLERANCE") "±20 %")
        (field (name "VOLTAGE") "25.0 V")
      )
      (libsource (lib "eagle-import") (part "C-EU-C0603-1U"))
    )
    (comp (ref "C331")
      (value "C-EU-C0603")
      (footprint "eagle-import:C0603")
      (fields (field (name "TOLERANCE") "±20 %") (field (name "VOLTAGE") "25.0 V"))
      (libsource (lib "eagle-import") (part "C-EU-C0603"))
    )
    (comp (ref "C332")
      (value "1u 25V")
      (footprint "eagle-import:C0603")
      (fields
        (field (name "MANUFACTURER") "free choice")
        (field (name "TOLERANCE") "±20 %")
        (field (name "VOLTAGE") "25.0 V")
      )
      (libsource (lib "eagle-import") (part "C-EU-C0603-1U"))
    )
    (comp (ref "D1")
      (value "150060RS75000")
      (footprint "eagle-import:WL-SMCW_0603_WE")
      (fields (field (name "MANUFACTURER") "Wuerth") (field (name "VOLTAGE") "5.0 V"))
      (libsource (lib "eagle-import") (part "150060RS75000"))
    )
    (comp (ref "D2")
      (value "150060GS75000")
      (footprint "eagle-import:WL-SMCW_0603_WE")
      (fields (field (name "MANUFACTURER") "Wuerth") (field (name "VOLTAGE") "5.0 V"))
      (libsource (lib "eagle-import") (part "150060GS75000"))
    )
    (comp (ref "D100")
      (value "LZ1-00R302")
      (footprint "eagle-import:LZ1_SMALL_LEDENGIN")
      (fields (field (name "MANUFACTURER") "Osram"))
      (libsource (lib "eagle-import") (part "LZ1-00R302-SMALL"))
    )
    (comp (ref "D101")
      (value "LZ1-00R302")
      (footprint "eagle-import:LZ1_SMALL_LEDENGIN")
      (fields (field (name "MANUFACTURER") "Osram"))
      (libsource (lib "eagle-import") (part "LZ1-00R302-SMALL"))
    )
    (comp (ref "D102")
      (value "LZ1-00R302")
      (footprint "eagle-import:LZ1_SMALL_LEDENGIN")
      (fields (field (name "MANUFACTURER") "Osram"))
      (libsource (lib "eagle-import") (part "LZ1-00R302-SMALL"))
    )
    (comp (ref "D103")
      (value "LZ1-00R302")
      (footprint "eagle-import:LZ1_SMALL_LEDENGIN")
      (fields (field (name "MANUFACTURER") "Osram"))
      (libsource (lib "eagle-import") (part "LZ1-00R302-SMALL"))
    )
    (comp (ref "D104")
      (value "LZ1-00R302")
      (footprint "eagle-import:LZ1_SMALL_LEDENGIN")
      (fields (field (name "MANUFACTURER") "Osram"))
      (libsource (lib "eagle-import") (part "LZ1-00R302-SMALL"))
    )
    (comp (ref "D105")
      (value "LZ1-00R302")
      (footprint "eagle-import:LZ1_SMALL_LEDENGIN")
      (fields (field (name "MANUFACTURER") "Osram"))
      (libsource (lib "eagle-import") (part "LZ1-00R302-SMALL"))
    )
    (comp (ref "D106")
      (value "LZ1-00R302")
      (footprint "eagle-import:LZ1_SMALL_LEDENGIN")
      (fields (field (name "MANUFACTURER") "Osram"))
      (libsource (lib "eagle-import") (part "LZ1-00R302-SMALL"))
    )
    (comp (ref "D107")
      (value "LZ1-00R302")
      (footprint "eagle-import:LZ1_SMALL_LEDENGIN")
      (fields (field (name "MANUFACTURER") "Osram"))
      (libsource (lib "eagle-import") (part "LZ1-00R302-SMALL"))
    )
    (comp (ref "D108")
      (value "LZ1-00R302")
      (footprint "eagle-import:LZ1_SMALL_LEDENGIN")
      (fields (field (name "MANUFACTURER") "Osram"))
      (libsource (lib "eagle-import") (part "LZ1-00R302-SMALL"))
    )
    (comp (ref "D109")
      (value "LZ1-00R302")
      (footprint "eagle-import:LZ1_SMALL_LEDENGIN")
      (fields (field (name "MANUFACTURER") "Osram"))
      (libsource (lib "eagle-import") (part "LZ1-00R302-SMALL"))
    )
    (comp (ref "D110")
      (value "LZ1-00R302")
      (footprint "eagle-import:LZ1_SMALL_LEDENGIN")
      (fields (field (name "MANUFACTURER") "Osram"))
      (libsource (lib "eagle-import") (part "LZ1-00R302-SMALL"))
    )
    (comp (ref "D111")
      (value "LZ1-00R302")
      (footprint "eagle-import:LZ1_SMALL_LEDENGIN")
      (fields (field (name "MANUFACTURER") "Osram"))
      (libsource (lib "eagle-import") (part "LZ1-00R302-SMALL"))
    )
    (comp (ref "D112")
      (value "LZ1-00R302")
      (footprint "eagle-import:LZ1_SMALL_LEDENGIN")
      (fields (field (name "MANUFACTURER") "Osram"))
      (libsource (lib "eagle-import") (part "LZ1-00R302-SMALL"))
    )
    (comp (ref "D200")
      (value "SST-10-IRD-B50-T850")
      (footprint "eagle-import:B50_LUMINUS")
      (fields (field (name "MANUFACTURER") "Luminus") (field (name "VOLTAGE") "5.0 V"))
      (libsource (lib "eagle-import") (part "SST-10-IRD-B50-T850"))
    )
    (comp (ref "D201")
      (value "SST-10-IRD-B50-T850")
      (footprint "eagle-import:B50_LUMINUS")
      (fields (field (name "MANUFACTURER") "Luminus") (field (name "VOLTAGE") "5.0 V"))
      (libsource (lib "eagle-import") (part "SST-10-IRD-B50-T850"))
    )
    (comp (ref "D202")
      (value "SST-10-IRD-B50-T850")
      (footprint "eagle-import:B50_LUMINUS")
      (fields (field (name "MANUFACTURER") "Luminus") (field (name "VOLTAGE") "5.0 V"))
      (libsource (lib "eagle-import") (part "SST-10-IRD-B50-T850"))
    )
    (comp (ref "D203")
      (value "SST-10-IRD-B50-T850")
      (footprint "eagle-import:B50_LUMINUS")
      (fields (field (name "MANUFACTURER") "Luminus") (field (name "VOLTAGE") "5.0 V"))
      (libsource (lib "eagle-import") (part "SST-10-IRD-B50-T850"))
    )
    (comp (ref "D204")
      (value "SST-10-IRD-B50-T850")
      (footprint "eagle-import:B50_LUMINUS")
      (fields (field (name "MANUFACTURER") "Luminus") (field (name "VOLTAGE") "5.0 V"))
      (libsource (lib "eagle-import") (part "SST-10-IRD-B50-T850"))
    )
    (comp (ref "D205")
      (value "SST-10-IRD-B50-T850")
      (footprint "eagle-import:B50_LUMINUS")
      (fields (field (name "MANUFACTURER") "Luminus") (field (name "VOLTAGE") "5.0 V"))
      (libsource (lib "eagle-import") (part "SST-10-IRD-B50-T850"))
    )
    (comp (ref "D206")
      (value "SST-10-IRD-B50-T850")
      (footprint "eagle-import:B50_LUMINUS")
      (fields (field (name "MANUFACTURER") "Luminus") (field (name "VOLTAGE") "5.0 V"))
      (libsource (lib "eagle-import") (part "SST-10-IRD-B50-T850"))
    )
    (comp (ref "D207")
      (value "SST-10-IRD-B50-T850")
      (footprint "eagle-import:B50_LUMINUS")
      (fields (field (name "MANUFACTURER") "Luminus") (field (name "VOLTAGE") "5.0 V"))
      (libsource (lib "eagle-import") (part "SST-10-IRD-B50-T850"))
    )
    (comp (ref "D208")
      (value "SST-10-IRD-B50-T850")
      (footprint "eagle-import:B50_LUMINUS")
      (fields (field (name "MANUFACTURER") "Luminus") (field (name "VOLTAGE") "5.0 V"))
      (libsource (lib "eagle-import") (part "SST-10-IRD-B50-T850"))
    )
    (comp (ref "D209")
      (value "SST-10-IRD-B50-T850")
      (footprint "eagle-import:B50_LUMINUS")
      (fields (field (name "MANUFACTURER") "Luminus") (field (name "VOLTAGE") "5.0 V"))
      (libsource (lib "eagle-import") (part "SST-10-IRD-B50-T850"))
    )
    (comp (ref "D210")
      (value "SST-10-IRD-B50-T850")
      (footprint "eagle-import:B50_LUMINUS")
      (fields (field (name "MANUFACTURER") "Luminus") (field (name "VOLTAGE") "5.0 V"))
      (libsource (lib "eagle-import") (part "SST-10-IRD-B50-T850"))
    )
    (comp (ref "D211")
      (value "SST-10-IRD-B50-T850")
      (footprint "eagle-import:B50_LUMINUS")
      (fields (field (name "MANUFACTURER") "Luminus") (field (name "VOLTAGE") "5.0 V"))
      (libsource (lib "eagle-import") (part "SST-10-IRD-B50-T850"))
    )
    (comp (ref "D212")
      (value "SST-10-IRD-B50-T850")
      (footprint "eagle-import:B50_LUMINUS")
      (fields (field (name "MANUFACTURER") "Luminus") (field (name "VOLTAGE") "5.0 V"))
      (libsource (lib "eagle-import") (part "SST-10-IRD-B50-T850"))
    )
    (comp (ref "D213")
      (value "SST-10-IRD-B50-T850")
      (footprint "eagle-import:B50_LUMINUS")
      (fields (field (name "MANUFACTURER") "Luminus") (field (name "VOLTAGE") "5.0 V"))
      (libsource (lib "eagle-import") (part "SST-10-IRD-B50-T850"))
    )
    (comp (ref "D214")
      (value "SST-10-IRD-B50-T850")
      (footprint "eagle-import:B50_LUMINUS")
      (fields (field (name "MANUFACTURER") "Luminus") (field (name "VOLTAGE") "5.0 V"))
      (libsource (lib "eagle-import") (part "SST-10-IRD-B50-T850"))
    )
    (comp (ref "D215")
      (value "SST-10-IRD-B50-T850")
      (footprint "eagle-import:B50_LUMINUS")
      (fields (field (name "MANUFACTURER") "Luminus") (field (name "VOLTAGE") "5.0 V"))
      (libsource (lib "eagle-import") (part "SST-10-IRD-B50-T850"))
    )
    (comp (ref "D250")
      (value "SST-10-IRD-B50-T850")
      (footprint "eagle-import:B50_LUMINUS")
      (fields (field (name "MANUFACTURER") "Luminus") (field (name "VOLTAGE") "5.0 V"))
      (libsource (lib "eagle-import") (part "SST-10-IRD-B50-T850"))
    )
    (comp (ref "D251")
      (value "SST-10-IRD-B50-T850")
      (footprint "eagle-import:B50_LUMINUS")
      (fields (field (name "MANUFACTURER") "Luminus") (field (name "VOLTAGE") "5.0 V"))
      (libsource (lib "eagle-import") (part "SST-10-IRD-B50-T850"))
    )
    (comp (ref "D252")
      (value "SST-10-IRD-B50-T850")
      (footprint "eagle-import:B50_LUMINUS")
      (fields (field (name "MANUFACTURER") "Luminus") (field (name "VOLTAGE") "5.0 V"))
      (libsource (lib "eagle-import") (part "SST-10-IRD-B50-T850"))
    )
    (comp (ref "D253")
      (value "SST-10-IRD-B50-T850")
      (footprint "eagle-import:B50_LUMINUS")
      (fields (field (name "MANUFACTURER") "Luminus") (field (name "VOLTAGE") "5.0 V"))
      (libsource (lib "eagle-import") (part "SST-10-IRD-B50-T850"))
    )
    (comp (ref "D254")
      (value "SST-10-IRD-B50-T850")
      (footprint "eagle-import:B50_LUMINUS")
      (fields (field (name "MANUFACTURER") "Luminus") (field (name "VOLTAGE") "5.0 V"))
      (libsource (lib "eagle-import") (part "SST-10-IRD-B50-T850"))
    )
    (comp (ref "D255")
      (value "SST-10-IRD-B50-T850")
      (footprint "eagle-import:B50_LUMINUS")
      (fields (field (name "MANUFACTURER") "Luminus") (field (name "VOLTAGE") "5.0 V"))
      (libsource (lib "eagle-import") (part "SST-10-IRD-B50-T850"))
    )
    (comp (ref "D256")
      (value "SST-10-IRD-B50-T850")
      (footprint "eagle-import:B50_LUMINUS")
      (fields (field (name "MANUFACTURER") "Luminus") (field (name "VOLTAGE") "5.0 V"))
      (libsource (lib "eagle-import") (part "SST-10-IRD-B50-T850"))
    )
    (comp (ref "D257")
      (value "SST-10-IRD-B50-T850")
      (footprint "eagle-import:B50_LUMINUS")
      (fields (field (name "MANUFACTURER") "Luminus") (field (name "VOLTAGE") "5.0 V"))
      (libsource (lib "eagle-import") (part "SST-10-IRD-B50-T850"))
    )
    (comp (ref "D258")
      (value "SST-10-IRD-B50-T850")
      (footprint "eagle-import:B50_LUMINUS")
      (fields (field (name "MANUFACTURER") "Luminus") (field (name "VOLTAGE") "5.0 V"))
      (libsource (lib "eagle-import") (part "SST-10-IRD-B50-T850"))
    )
    (comp (ref "D259")
      (value "SST-10-IRD-B50-T850")
      (footprint "eagle-import:B50_LUMINUS")
      (fields (field (name "MANUFACTURER") "Luminus") (field (name "VOLTAGE") "5.0 V"))
      (libsource (lib "eagle-import") (part "SST-10-IRD-B50-T850"))
    )
    (comp (ref "D260")
      (value "SST-10-IRD-B50-T850")
      (footprint "eagle-import:B50_LUMINUS")
      (fields (field (name "MANUFACTURER") "Luminus") (field (name "VOLTAGE") "5.0 V"))
      (libsource (lib "eagle-import") (part "SST-10-IRD-B50-T850"))
    )
    (comp (ref "D261")
      (value "SST-10-IRD-B50-T850")
      (footprint "eagle-import:B50_LUMINUS")
      (fields (field (name "MANUFACTURER") "Luminus") (field (name "VOLTAGE") "5.0 V"))
      (libsource (lib "eagle-import") (part "SST-10-IRD-B50-T850"))
    )
    (comp (ref "D262")
      (value "SST-10-IRD-B50-T850")
      (footprint "eagle-import:B50_LUMINUS")
      (fields (field (name "MANUFACTURER") "Luminus") (field (name "VOLTAGE") "5.0 V"))
      (libsource (lib "eagle-import") (part "SST-10-IRD-B50-T850"))
    )
    (comp (ref "D263")
      (value "SST-10-IRD-B50-T850")
      (footprint "eagle-import:B50_LUMINUS")
      (fields (field (name "MANUFACTURER") "Luminus") (field (name "VOLTAGE") "5.0 V"))
      (libsource (lib "eagle-import") (part "SST-10-IRD-B50-T850"))
    )
    (comp (ref "D264")
      (value "SST-10-IRD-B50-T850")
      (footprint "eagle-import:B50_LUMINUS")
      (fields (field (name "MANUFACTURER") "Luminus") (field (name "VOLTAGE") "5.0 V"))
      (libsource (lib "eagle-import") (part "SST-10-IRD-B50-T850"))
    )
    (comp (ref "D265")
      (value "SST-10-IRD-B50-T850")
      (footprint "eagle-import:B50_LUMINUS")
      (fields (field (name "MANUFACTURER") "Luminus") (field (name "VOLTAGE") "5.0 V"))
      (libsource (lib "eagle-import") (part "SST-10-IRD-B50-T850"))
    )
    (comp (ref "D300")
      (value "SST-10-IRD-B50-S940")
      (footprint "eagle-import:B50_LUMINUS")
      (fields (field (name "MANUFACTURER") "Luminus") (field (name "VOLTAGE") "5.0 V"))
      (libsource (lib "eagle-import") (part "SST-10-IRD-B50-S940"))
    )
    (comp (ref "D301")
      (value "SST-10-IRD-B50-S940")
      (footprint "eagle-import:B50_LUMINUS")
      (fields (field (name "MANUFACTURER") "Luminus") (field (name "VOLTAGE") "5.0 V"))
      (libsource (lib "eagle-import") (part "SST-10-IRD-B50-S940"))
    )
    (comp (ref "D302")
      (value "SST-10-IRD-B50-S940")
      (footprint "eagle-import:B50_LUMINUS")
      (fields (field (name "MANUFACTURER") "Luminus") (field (name "VOLTAGE") "5.0 V"))
      (libsource (lib "eagle-import") (part "SST-10-IRD-B50-S940"))
    )
    (comp (ref "D303")
      (value "SST-10-IRD-B50-S940")
      (footprint "eagle-import:B50_LUMINUS")
      (fields (field (name "MANUFACTURER") "Luminus") (field (name "VOLTAGE") "5.0 V"))
      (libsource (lib "eagle-import") (part "SST-10-IRD-B50-S940"))
    )
    (comp (ref "D304")
      (value "SST-10-IRD-B50-S940")
      (footprint "eagle-import:B50_LUMINUS")
      (fields (field (name "MANUFACTURER") "Luminus") (field (name "VOLTAGE") "5.0 V"))
      (libsource (lib "eagle-import") (part "SST-10-IRD-B50-S940"))
    )
    (comp (ref "D305")
      (value "SST-10-IRD-B50-S940")
      (footprint "eagle-import:B50_LUMINUS")
      (fields (field (name "MANUFACTURER") "Luminus") (field (name "VOLTAGE") "5.0 V"))
      (libsource (lib "eagle-import") (part "SST-10-IRD-B50-S940"))
    )
    (comp (ref "D306")
      (value "SST-10-IRD-B50-S940")
      (footprint "eagle-import:B50_LUMINUS")
      (fields (field (name "MANUFACTURER") "Luminus") (field (name "VOLTAGE") "5.0 V"))
      (libsource (lib "eagle-import") (part "SST-10-IRD-B50-S940"))
    )
    (comp (ref "D307")
      (value "SST-10-IRD-B50-S940")
      (footprint "eagle-import:B50_LUMINUS")
      (fields (field (name "MANUFACTURER") "Luminus") (field (name "VOLTAGE") "5.0 V"))
      (libsource (lib "eagle-import") (part "SST-10-IRD-B50-S940"))
    )
    (comp (ref "D308")
      (value "SST-10-IRD-B50-S940")
      (footprint "eagle-import:B50_LUMINUS")
      (fields (field (name "MANUFACTURER") "Luminus") (field (name "VOLTAGE") "5.0 V"))
      (libsource (lib "eagle-import") (part "SST-10-IRD-B50-S940"))
    )
    (comp (ref "D309")
      (value "SST-10-IRD-B50-S940")
      (footprint "eagle-import:B50_LUMINUS")
      (fields (field (name "MANUFACTURER") "Luminus") (field (name "VOLTAGE") "5.0 V"))
      (libsource (lib "eagle-import") (part "SST-10-IRD-B50-S940"))
    )
    (comp (ref "D310")
      (value "SST-10-IRD-B50-S940")
      (footprint "eagle-import:B50_LUMINUS")
      (fields (field (name "MANUFACTURER") "Luminus") (field (name "VOLTAGE") "5.0 V"))
      (libsource (lib "eagle-import") (part "SST-10-IRD-B50-S940"))
    )
    (comp (ref "D311")
      (value "SST-10-IRD-B50-S940")
      (footprint "eagle-import:B50_LUMINUS")
      (fields (field (name "MANUFACTURER") "Luminus") (field (name "VOLTAGE") "5.0 V"))
      (libsource (lib "eagle-import") (part "SST-10-IRD-B50-S940"))
    )
    (comp (ref "D312")
      (value "SST-10-IRD-B50-S940")
      (footprint "eagle-import:B50_LUMINUS")
      (fields (field (name "MANUFACTURER") "Luminus") (field (name "VOLTAGE") "5.0 V"))
      (libsource (lib "eagle-import") (part "SST-10-IRD-B50-S940"))
    )
    (comp (ref "D313")
      (value "SST-10-IRD-B50-S940")
      (footprint "eagle-import:B50_LUMINUS")
      (fields (field (name "MANUFACTURER") "Luminus") (field (name "VOLTAGE") "5.0 V"))
      (libsource (lib "eagle-import") (part "SST-10-IRD-B50-S940"))
    )
    (comp (ref "D314")
      (value "SST-10-IRD-B50-S940")
      (footprint "eagle-import:B50_LUMINUS")
      (fields (field (name "MANUFACTURER") "Luminus") (field (name "VOLTAGE") "5.0 V"))
      (libsource (lib "eagle-import") (part "SST-10-IRD-B50-S940"))
    )
    (comp (ref "D315")
      (value "SST-10-IRD-B50-S940")
      (footprint "eagle-import:B50_LUMINUS")
      (fields (field (name "MANUFACTURER") "Luminus") (field (name "VOLTAGE") "5.0 V"))
      (libsource (lib "eagle-import") (part "SST-10-IRD-B50-S940"))
    )
    (comp (ref "D350")
      (value "SST-10-IRD-B50-S940")
      (footprint "eagle-import:B50_LUMINUS")
      (fields (field (name "MANUFACTURER") "Luminus") (field (name "VOLTAGE") "5.0 V"))
      (libsource (lib "eagle-import") (part "SST-10-IRD-B50-S940"))
    )
    (comp (ref "D351")
      (value "SST-10-IRD-B50-S940")
      (footprint "eagle-import:B50_LUMINUS")
      (fields (field (name "MANUFACTURER") "Luminus") (field (name "VOLTAGE") "5.0 V"))
      (libsource (lib "eagle-import") (part "SST-10-IRD-B50-S940"))
    )
    (comp (ref "D352")
      (value "SST-10-IRD-B50-S940")
      (footprint "eagle-import:B50_LUMINUS")
      (fields (field (name "MANUFACTURER") "Luminus") (field (name "VOLTAGE") "5.0 V"))
      (libsource (lib "eagle-import") (part "SST-10-IRD-B50-S940"))
    )
    (comp (ref "D353")
      (value "SST-10-IRD-B50-S940")
      (footprint "eagle-import:B50_LUMINUS")
      (fields (field (name "MANUFACTURER") "Luminus") (field (name "VOLTAGE") "5.0 V"))
      (libsource (lib "eagle-import") (part "SST-10-IRD-B50-S940"))
    )
    (comp (ref "D354")
      (value "SST-10-IRD-B50-S940")
      (footprint "eagle-import:B50_LUMINUS")
      (fields (field (name "MANUFACTURER") "Luminus") (field (name "VOLTAGE") "5.0 V"))
      (libsource (lib "eagle-import") (part "SST-10-IRD-B50-S940"))
    )
    (comp (ref "D355")
      (value "SST-10-IRD-B50-S940")
      (footprint "eagle-import:B50_LUMINUS")
      (fields (field (name "MANUFACTURER") "Luminus") (field (name "VOLTAGE") "5.0 V"))
      (libsource (lib "eagle-import") (part "SST-10-IRD-B50-S940"))
    )
    (comp (ref "D356")
      (value "SST-10-IRD-B50-S940")
      (footprint "eagle-import:B50_LUMINUS")
      (fields (field (name "MANUFACTURER") "Luminus") (field (name "VOLTAGE") "5.0 V"))
      (libsource (lib "eagle-import") (part "SST-10-IRD-B50-S940"))
    )
    (comp (ref "D357")
      (value "SST-10-IRD-B50-S940")
      (footprint "eagle-import:B50_LUMINUS")
      (fields (field (name "MANUFACTURER") "Luminus") (field (name "VOLTAGE") "5.0 V"))
      (libsource (lib "eagle-import") (part "SST-10-IRD-B50-S940"))
    )
    (comp (ref "D358")
      (value "SST-10-IRD-B50-S940")
      (footprint "eagle-import:B50_LUMINUS")
      (fields (field (name "MANUFACTURER") "Luminus") (field (name "VOLTAGE") "5.0 V"))
      (libsource (lib "eagle-import") (part "SST-10-IRD-B50-S940"))
    )
    (comp (ref "D359")
      (value "SST-10-IRD-B50-S940")
      (footprint "eagle-import:B50_LUMINUS")
      (fields (field (name "MANUFACTURER") "Luminus") (field (name "VOLTAGE") "5.0 V"))
      (libsource (lib "eagle-import") (part "SST-10-IRD-B50-S940"))
    )
    (comp (ref "D360")
      (value "SST-10-IRD-B50-S940")
      (footprint "eagle-import:B50_LUMINUS")
      (fields (field (name "MANUFACTURER") "Luminus") (field (name "VOLTAGE") "5.0 V"))
      (libsource (lib "eagle-import") (part "SST-10-IRD-B50-S940"))
    )
    (comp (ref "D361")
      (value "SST-10-IRD-B50-S940")
      (footprint "eagle-import:B50_LUMINUS")
      (fields (field (name "MANUFACTURER") "Luminus") (field (name "VOLTAGE") "5.0 V"))
      (libsource (lib "eagle-import") (part "SST-10-IRD-B50-S940"))
    )
    (comp (ref "D362")
      (value "SST-10-IRD-B50-S940")
      (footprint "eagle-import:B50_LUMINUS")
      (fields (field (name "MANUFACTURER") "Luminus") (field (name "VOLTAGE") "5.0 V"))
      (libsource (lib "eagle-import") (part "SST-10-IRD-B50-S940"))
    )
    (comp (ref "D363")
      (value "SST-10-IRD-B50-S940")
      (footprint "eagle-import:B50_LUMINUS")
      (fields (field (name "MANUFACTURER") "Luminus") (field (name "VOLTAGE") "5.0 V"))
      (libsource (lib "eagle-import") (part "SST-10-IRD-B50-S940"))
    )
    (comp (ref "D364")
      (value "SST-10-IRD-B50-S940")
      (footprint "eagle-import:B50_LUMINUS")
      (fields (field (name "MANUFACTURER") "Luminus") (field (name "VOLTAGE") "5.0 V"))
      (libsource (lib "eagle-import") (part "SST-10-IRD-B50-S940"))
    )
    (comp (ref "D365")
      (value "SST-10-IRD-B50-S940")
      (footprint "eagle-import:B50_LUMINUS")
      (fields (field (name "MANUFACTURER") "Luminus") (field (name "VOLTAGE") "5.0 V"))
      (libsource (lib "eagle-import") (part "SST-10-IRD-B50-S940"))
    )
    (comp (ref "IC1")
      (value "UCC27517DBV")
      (footprint "eagle-import:DBV0005A_TI")
      (fields (field (name "MANUFACTURER") "TI") (field (name "VOLTAGE") "18.0 V"))
      (libsource (lib "eagle-import") (part "UCC27517DBV"))
    )
    (comp (ref "IC2")
      (value "UCC27517DBV")
      (footprint "eagle-import:DBV0005A_TI")
      (fields (field (name "MANUFACTURER") "TI") (field (name "VOLTAGE") "18.0 V"))
      (libsource (lib "eagle-import") (part "UCC27517DBV"))
    )
    (comp (ref "IC3")
      (value "LM393BIDSG")
      (footprint "eagle-import:DSG0008A_WSON_TI_NO_VIA")
      (fields (field (name "MANUFACTURER") "TI") (field (name "VOLTAGE") "36.0 V"))
      (libsource (lib "eagle-import") (part "LM393BIDSG_NO_VIA"))
    )
    (comp (ref "IC4")
      (value "LM393BIDSG")
      (footprint "eagle-import:DSG0008A_WSON_TI_NO_VIA")
      (fields (field (name "MANUFACTURER") "TI") (field (name "VOLTAGE") "36.0 V"))
      (libsource (lib "eagle-import") (part "LM393BIDSG_NO_VIA"))
    )
    (comp (ref "IC5")
      (value "LM393BIDSG")
      (footprint "eagle-import:DSG0008A_WSON_TI_NO_VIA")
      (fields (field (name "MANUFACTURER") "TI") (field (name "VOLTAGE") "36.0 V"))
      (libsource (lib "eagle-import") (part "LM393BIDSG_NO_VIA"))
    )
    (comp (ref "IC6")
      (value "SFH9206")
      (footprint "eagle-import:SO6_OSRAM")
      (fields (field (name "MANUFACTURER") "Osram"))
      (libsource (lib "eagle-import") (part "SFH9206"))
    )
    (comp (ref "IC7")
      (value "VL53L1CBV0FY/1")
      (footprint "eagle-import:VL53L1X_STM")
      (fields (field (name "MANUFACTURER") "STM") (field (name "VOLTAGE") "3.5 V"))
      (libsource (lib "eagle-import") (part "VL53L1CBV0FY/1"))
    )
    (comp (ref "IC8")
      (value "UCC27517DBV")
      (footprint "eagle-import:DBV0005A_TI")
      (fields (field (name "MANUFACTURER") "TI") (field (name "VOLTAGE") "18.0 V"))
      (libsource (lib "eagle-import") (part "UCC27517DBV"))
    )
    (comp (ref "IC9")
      (value "SN74LVC112ADGV")
      (footprint "eagle-import:TVSOP-16_TI")
      (fields (field (name "MANUFACTURER") "TI") (field (name "VOLTAGE") "3.6 V"))
      (libsource (lib "eagle-import") (part "SN74LVC112ADGV"))
    )
    (comp (ref "IC10")
      (value "UCC27517DBV")
      (footprint "eagle-import:DBV0005A_TI")
      (fields (field (name "MANUFACTURER") "TI") (field (name "VOLTAGE") "18.0 V"))
      (libsource (lib "eagle-import") (part "UCC27517DBV"))
    )
    (comp (ref "IC11")
      (value "TLV9152IDDF")
      (footprint "eagle-import:DDF0008A_TI")
      (fields (field (name "MANUFACTURER") "TI") (field (name "VOLTAGE") "16.0 V"))
      (libsource (lib "eagle-import") (part "TLV9152DDFI"))
    )
    (comp (ref "IC12")
      (value "824001")
      (footprint "eagle-import:SOT23-6L_WE")
      (fields (field (name "MANUFACTURER") "Wuerth") (field (name "VOLTAGE") "5.0 V"))
      (libsource (lib "eagle-import") (part "824001"))
    )
    (comp (ref "IC13")
      (value "UCC27517DBV")
      (footprint "eagle-import:DBV0005A_TI")
      (fields (field (name "MANUFACTURER") "TI") (field (name "VOLTAGE") "18.0 V"))
      (libsource (lib "eagle-import") (part "UCC27517DBV"))
    )
    (comp (ref "IC14")
      (value "824001")
      (footprint "eagle-import:SOT23-6L_WE")
      (fields (field (name "MANUFACTURER") "Wuerth") (field (name "VOLTAGE") "5.0 V"))
      (libsource (lib "eagle-import") (part "824001"))
    )
    (comp (ref "IC15")
      (value "TMP1075DGK")
      (footprint "eagle-import:S-PDSO-G8_DGK_VSSOP_TI")
      (fields (field (name "MANUFACTURER") "TI") (field (name "VOLTAGE") "5.5 V"))
      (libsource (lib "eagle-import") (part "TMP1075DGK"))
    )
    (comp (ref "IC16")
      (value "824001")
      (footprint "eagle-import:SOT23-6L_WE")
      (fields (field (name "MANUFACTURER") "Wuerth") (field (name "VOLTAGE") "5.0 V"))
      (libsource (lib "eagle-import") (part "824001"))
    )
    (comp (ref "IC17")
      (value "824001")
      (footprint "eagle-import:SOT23-6L_WE")
      (fields (field (name "MANUFACTURER") "Wuerth") (field (name "VOLTAGE") "5.0 V"))
      (libsource (lib "eagle-import") (part "824001"))
    )
    (comp (ref "IC18")
      (value "824001")
      (footprint "eagle-import:SOT23-6L_WE")
      (fields (field (name "MANUFACTURER") "Wuerth") (field (name "VOLTAGE") "5.0 V"))
      (libsource (lib "eagle-import") (part "824001"))
    )
    (comp (ref "IC19")
      (value "824001")
      (footprint "eagle-import:SOT23-6L_WE")
      (fields (field (name "MANUFACTURER") "Wuerth") (field (name "VOLTAGE") "5.0 V"))
      (libsource (lib "eagle-import") (part "824001"))
    )
    (comp (ref "IC20")
      (value "824001")
      (footprint "eagle-import:SOT23-6L_WE")
      (fields (field (name "MANUFACTURER") "Wuerth") (field (name "VOLTAGE") "5.0 V"))
      (libsource (lib "eagle-import") (part "824001"))
    )
    (comp (ref "IC21")
      (value "ESD7016")
      (footprint "eagle-import:UDFN8_3.3X1.0_0.4_ONSEMI")
      (fields (field (name "MANUFACTURER") "Onsemi"))
      (libsource (lib "eagle-import") (part "ESD7016"))
    )
    (comp (ref "IC22")
      (value "ESD7016")
      (footprint "eagle-import:UDFN8_3.3X1.0_0.4_ONSEMI")
      (fields (field (name "MANUFACTURER") "Onsemi"))
      (libsource (lib "eagle-import") (part "ESD7016"))
    )
    (comp (ref "IC23")
      (value "TMUX1209RSV")
      (footprint "eagle-import:RSV0016A_TI")
      (fields (field (name "MANUFACTURER") "TI") (field (name "VOLTAGE") "5.5 V"))
      (libsource (lib "eagle-import") (part "TMUX1209RSV"))
    )
    (comp (ref "IC24")
      (value "TMP112NAIDRL")
      (footprint "eagle-import:DRL0006A_TI")
      (fields (field (name "MANUFACTURER") "TI") (field (name "VOLTAGE") "3.6 V"))
      (libsource (lib "eagle-import") (part "TMP112DRLNAI"))
    )
    (comp (ref "IC25")
      (value "BU27030NUC")
      (footprint "eagle-import:WSON008X2120_ROHM")
      (fields (field (name "MANUFACTURER") "Rohm") (field (name "VOLTAGE") "3.6 V"))
      (libsource (lib "eagle-import") (part "BU27030NUC"))
    )
    (comp (ref "IC100")
      (value "SK6805-EC15")
      (footprint "eagle-import:SK6805-EC_IPIXEL")
      (fields (field (name "MANUFACTURER") "iPixel") (field (name "VOLTAGE") "5.5 V"))
      (libsource (lib "eagle-import") (part "SK6805-EC15"))
    )
    (comp (ref "IC101")
      (value "SK6805-EC15")
      (footprint "eagle-import:SK6805-EC_IPIXEL")
      (fields (field (name "MANUFACTURER") "iPixel") (field (name "VOLTAGE") "5.5 V"))
      (libsource (lib "eagle-import") (part "SK6805-EC15"))
    )
    (comp (ref "IC102")
      (value "SK6805-EC15")
      (footprint "eagle-import:SK6805-EC_IPIXEL")
      (fields (field (name "MANUFACTURER") "iPixel") (field (name "VOLTAGE") "5.5 V"))
      (libsource (lib "eagle-import") (part "SK6805-EC15"))
    )
    (comp (ref "IC103")
      (value "SK6805-EC15")
      (footprint "eagle-import:SK6805-EC_IPIXEL")
      (fields (field (name "MANUFACTURER") "iPixel") (field (name "VOLTAGE") "5.5 V"))
      (libsource (lib "eagle-import") (part "SK6805-EC15"))
    )
    (comp (ref "IC104")
      (value "SK6805-EC15")
      (footprint "eagle-import:SK6805-EC_IPIXEL")
      (fields (field (name "MANUFACTURER") "iPixel") (field (name "VOLTAGE") "5.5 V"))
      (libsource (lib "eagle-import") (part "SK6805-EC15"))
    )
    (comp (ref "IC105")
      (value "SK6805-EC15")
      (footprint "eagle-import:SK6805-EC_IPIXEL")
      (fields (field (name "MANUFACTURER") "iPixel") (field (name "VOLTAGE") "5.5 V"))
      (libsource (lib "eagle-import") (part "SK6805-EC15"))
    )
    (comp (ref "IC106")
      (value "SK6805-EC15")
      (footprint "eagle-import:SK6805-EC_IPIXEL")
      (fields (field (name "MANUFACTURER") "iPixel") (field (name "VOLTAGE") "5.5 V"))
      (libsource (lib "eagle-import") (part "SK6805-EC15"))
    )
    (comp (ref "IC107")
      (value "SK6805-EC15")
      (footprint "eagle-import:SK6805-EC_IPIXEL")
      (fields (field (name "MANUFACTURER") "iPixel") (field (name "VOLTAGE") "5.5 V"))
      (libsource (lib "eagle-import") (part "SK6805-EC15"))
    )
    (comp (ref "IC108")
      (value "SK6805-EC15")
      (footprint "eagle-import:SK6805-EC_IPIXEL")
      (fields (field (name "MANUFACTURER") "iPixel") (field (name "VOLTAGE") "5.5 V"))
      (libsource (lib "eagle-import") (part "SK6805-EC15"))
    )
    (comp (ref "IC109")
      (value "SK6805-EC15")
      (footprint "eagle-import:SK6805-EC_IPIXEL")
      (fields (field (name "MANUFACTURER") "iPixel") (field (name "VOLTAGE") "5.5 V"))
      (libsource (lib "eagle-import") (part "SK6805-EC15"))
    )
    (comp (ref "IC110")
      (value "SK6805-EC15")
      (footprint "eagle-import:SK6805-EC_IPIXEL")
      (fields (field (name "MANUFACTURER") "iPixel") (field (name "VOLTAGE") "5.5 V"))
      (libsource (lib "eagle-import") (part "SK6805-EC15"))
    )
    (comp (ref "IC111")
      (value "SK6805-EC15")
      (footprint "eagle-import:SK6805-EC_IPIXEL")
      (fields (field (name "MANUFACTURER") "iPixel") (field (name "VOLTAGE") "5.5 V"))
      (libsource (lib "eagle-import") (part "SK6805-EC15"))
    )
    (comp (ref "IC112")
      (value "SK6805-EC15")
      (footprint "eagle-import:SK6805-EC_IPIXEL")
      (fields (field (name "MANUFACTURER") "iPixel") (field (name "VOLTAGE") "5.5 V"))
      (libsource (lib "eagle-import") (part "SK6805-EC15"))
    )
    (comp (ref "IC113")
      (value "SK6805-EC15")
      (footprint "eagle-import:SK6805-EC_IPIXEL")
      (fields (field (name "MANUFACTURER") "iPixel") (field (name "VOLTAGE") "5.5 V"))
      (libsource (lib "eagle-import") (part "SK6805-EC15"))
    )
    (comp (ref "IC114")
      (value "SK6805-EC15")
      (footprint "eagle-import:SK6805-EC_IPIXEL")
      (fields (field (name "MANUFACTURER") "iPixel") (field (name "VOLTAGE") "5.5 V"))
      (libsource (lib "eagle-import") (part "SK6805-EC15"))
    )
    (comp (ref "IC115")
      (value "SK6805-EC15")
      (footprint "eagle-import:SK6805-EC_IPIXEL")
      (fields (field (name "MANUFACTURER") "iPixel") (field (name "VOLTAGE") "5.5 V"))
      (libsource (lib "eagle-import") (part "SK6805-EC15"))
    )
    (comp (ref "IC116")
      (value "SK6805-EC15")
      (footprint "eagle-import:SK6805-EC_IPIXEL")
      (fields (field (name "MANUFACTURER") "iPixel") (field (name "VOLTAGE") "5.5 V"))
      (libsource (lib "eagle-import") (part "SK6805-EC15"))
    )
    (comp (ref "IC117")
      (value "SK6805-EC15")
      (footprint "eagle-import:SK6805-EC_IPIXEL")
      (fields (field (name "MANUFACTURER") "iPixel") (field (name "VOLTAGE") "5.5 V"))
      (libsource (lib "eagle-import") (part "SK6805-EC15"))
    )
    (comp (ref "IC118")
      (value "SK6805-EC15")
      (footprint "eagle-import:SK6805-EC_IPIXEL")
      (fields (field (name "MANUFACTURER") "iPixel") (field (name "VOLTAGE") "5.5 V"))
      (libsource (lib "eagle-import") (part "SK6805-EC15"))
    )
    (comp (ref "IC119")
      (value "SK6805-EC15")
      (footprint "eagle-import:SK6805-EC_IPIXEL")
      (fields (field (name "MANUFACTURER") "iPixel") (field (name "VOLTAGE") "5.5 V"))
      (libsource (lib "eagle-import") (part "SK6805-EC15"))
    )
    (comp (ref "IC120")
      (value "SK6805-EC15")
      (footprint "eagle-import:SK6805-EC_IPIXEL")
      (fields (field (name "MANUFACTURER") "iPixel") (field (name "VOLTAGE") "5.5 V"))
      (libsource (lib "eagle-import") (part "SK6805-EC15"))
    )
    (comp (ref "IC121")
      (value "SK6805-EC15")
      (footprint "eagle-import:SK6805-EC_IPIXEL")
      (fields (field (name "MANUFACTURER") "iPixel") (field (name "VOLTAGE") "5.5 V"))
      (libsource (lib "eagle-import") (part "SK6805-EC15"))
    )
    (comp (ref "IC122")
      (value "SK6805-EC15")
      (footprint "eagle-import:SK6805-EC_IPIXEL")
      (fields (field (name "MANUFACTURER") "iPixel") (field (name "VOLTAGE") "5.5 V"))
      (libsource (lib "eagle-import") (part "SK6805-EC15"))
    )
    (comp (ref "IC123")
      (value "SK6805-EC15")
      (footprint "eagle-import:SK6805-EC_IPIXEL")
      (fields (field (name "MANUFACTURER") "iPixel") (field (name "VOLTAGE") "5.5 V"))
      (libsource (lib "eagle-import") (part "SK6805-EC15"))
    )
    (comp (ref "IC124")
      (value "SK6805-EC15")
      (footprint "eagle-import:SK6805-EC_IPIXEL")
      (fields (field (name "MANUFACTURER") "iPixel") (field (name "VOLTAGE") "5.5 V"))
      (libsource (lib "eagle-import") (part "SK6805-EC15"))
    )
    (comp (ref "IC125")
      (value "SK6805-EC15")
      (footprint "eagle-import:SK6805-EC_IPIXEL")
      (fields (field (name "MANUFACTURER") "iPixel") (field (name "VOLTAGE") "5.5 V"))
      (libsource (lib "eagle-import") (part "SK6805-EC15"))
    )
    (comp (ref "IC126")
      (value "SK6805-EC15")
      (footprint "eagle-import:SK6805-EC_IPIXEL")
      (fields (field (name "MANUFACTURER") "iPixel") (field (name "VOLTAGE") "5.5 V"))
      (libsource (lib "eagle-import") (part "SK6805-EC15"))
    )
    (comp (ref "IC127")
      (value "SK6805-EC15")
      (footprint "eagle-import:SK6805-EC_IPIXEL")
      (fields (field (name "MANUFACTURER") "iPixel") (field (name "VOLTAGE") "5.5 V"))
      (libsource (lib "eagle-import") (part "SK6805-EC15"))
    )
    (comp (ref "IC128")
      (value "SK6805-EC15")
      (footprint "eagle-import:SK6805-EC_IPIXEL")
      (fields (field (name "MANUFACTURER") "iPixel") (field (name "VOLTAGE") "5.5 V"))
      (libsource (lib "eagle-import") (part "SK6805-EC15"))
    )
    (comp (ref "IC129")
      (value "SK6805-EC15")
      (footprint "eagle-import:SK6805-EC_IPIXEL")
      (fields (field (name "MANUFACTURER") "iPixel") (field (name "VOLTAGE") "5.5 V"))
      (libsource (lib "eagle-import") (part "SK6805-EC15"))
    )
    (comp (ref "IC130")
      (value "SK6805-EC15")
      (footprint "eagle-import:SK6805-EC_IPIXEL")
      (fields (field (name "MANUFACTURER") "iPixel") (field (name "VOLTAGE") "5.5 V"))
      (libsource (lib "eagle-import") (part "SK6805-EC15"))
    )
    (comp (ref "IC131")
      (value "SK6805-EC15")
      (footprint "eagle-import:SK6805-EC_IPIXEL")
      (fields (field (name "MANUFACTURER") "iPixel") (field (name "VOLTAGE") "5.5 V"))
      (libsource (lib "eagle-import") (part "SK6805-EC15"))
    )
    (comp (ref "IC132")
      (value "SK6805-EC15")
      (footprint "eagle-import:SK6805-EC_IPIXEL")
      (fields (field (name "MANUFACTURER") "iPixel") (field (name "VOLTAGE") "5.5 V"))
      (libsource (lib "eagle-import") (part "SK6805-EC15"))
    )
    (comp (ref "IC133")
      (value "SK6805-EC15")
      (footprint "eagle-import:SK6805-EC_IPIXEL")
      (fields (field (name "MANUFACTURER") "iPixel") (field (name "VOLTAGE") "5.5 V"))
      (libsource (lib "eagle-import") (part "SK6805-EC15"))
    )
    (comp (ref "IC134")
      (value "SK6805-EC15")
      (footprint "eagle-import:SK6805-EC_IPIXEL")
      (fields (field (name "MANUFACTURER") "iPixel") (field (name "VOLTAGE") "5.5 V"))
      (libsource (lib "eagle-import") (part "SK6805-EC15"))
    )
    (comp (ref "IC135")
      (value "SK6805-EC15")
      (footprint "eagle-import:SK6805-EC_IPIXEL")
      (fields (field (name "MANUFACTURER") "iPixel") (field (name "VOLTAGE") "5.5 V"))
      (libsource (lib "eagle-import") (part "SK6805-EC15"))
    )
    (comp (ref "IC136")
      (value "SK6805-EC15")
      (footprint "eagle-import:SK6805-EC_IPIXEL")
      (fields (field (name "MANUFACTURER") "iPixel") (field (name "VOLTAGE") "5.5 V"))
      (libsource (lib "eagle-import") (part "SK6805-EC15"))
    )
    (comp (ref "IC137")
      (value "SK6805-EC15")
      (footprint "eagle-import:SK6805-EC_IPIXEL")
      (fields (field (name "MANUFACTURER") "iPixel") (field (name "VOLTAGE") "5.5 V"))
      (libsource (lib "eagle-import") (part "SK6805-EC15"))
    )
    (comp (ref "IC138")
      (value "SK6805-EC15")
      (footprint "eagle-import:SK6805-EC_IPIXEL")
      (fields (field (name "MANUFACTURER") "iPixel") (field (name "VOLTAGE") "5.5 V"))
      (libsource (lib "eagle-import") (part "SK6805-EC15"))
    )
    (comp (ref "IC139")
      (value "SK6805-EC15")
      (footprint "eagle-import:SK6805-EC_IPIXEL")
      (fields (field (name "MANUFACTURER") "iPixel") (field (name "VOLTAGE") "5.5 V"))
      (libsource (lib "eagle-import") (part "SK6805-EC15"))
    )
    (comp (ref "IC140")
      (value "SK6805-EC15")
      (footprint "eagle-import:SK6805-EC_IPIXEL")
      (fields (field (name "MANUFACTURER") "iPixel") (field (name "VOLTAGE") "5.5 V"))
      (libsource (lib "eagle-import") (part "SK6805-EC15"))
    )
    (comp (ref "IC141")
      (value "SK6805-EC15")
      (footprint "eagle-import:SK6805-EC_IPIXEL")
      (fields (field (name "MANUFACTURER") "iPixel") (field (name "VOLTAGE") "5.5 V"))
      (libsource (lib "eagle-import") (part "SK6805-EC15"))
    )
    (comp (ref "IC142")
      (value "SK6805-EC15")
      (footprint "eagle-import:SK6805-EC_IPIXEL")
      (fields (field (name "MANUFACTURER") "iPixel") (field (name "VOLTAGE") "5.5 V"))
      (libsource (lib "eagle-import") (part "SK6805-EC15"))
    )
    (comp (ref "IC143")
      (value "SK6805-EC15")
      (footprint "eagle-import:SK6805-EC_IPIXEL")
      (fields (field (name "MANUFACTURER") "iPixel") (field (name "VOLTAGE") "5.5 V"))
      (libsource (lib "eagle-import") (part "SK6805-EC15"))
    )
    (comp (ref "IC144")
      (value "SK6805-EC15")
      (footprint "eagle-import:SK6805-EC_IPIXEL")
      (fields (field (name "MANUFACTURER") "iPixel") (field (name "VOLTAGE") "5.5 V"))
      (libsource (lib "eagle-import") (part "SK6805-EC15"))
    )
    (comp (ref "IC145")
      (value "SK6805-EC15")
      (footprint "eagle-import:SK6805-EC_IPIXEL")
      (fields (field (name "MANUFACTURER") "iPixel") (field (name "VOLTAGE") "5.5 V"))
      (libsource (lib "eagle-import") (part "SK6805-EC15"))
    )
    (comp (ref "IC146")
      (value "SK6805-EC15")
      (footprint "eagle-import:SK6805-EC_IPIXEL")
      (fields (field (name "MANUFACTURER") "iPixel") (field (name "VOLTAGE") "5.5 V"))
      (libsource (lib "eagle-import") (part "SK6805-EC15"))
    )
    (comp (ref "IC147")
      (value "SK6805-EC15")
      (footprint "eagle-import:SK6805-EC_IPIXEL")
      (fields (field (name "MANUFACTURER") "iPixel") (field (name "VOLTAGE") "5.5 V"))
      (libsource (lib "eagle-import") (part "SK6805-EC15"))
    )
    (comp (ref "IC148")
      (value "SK6805-EC15")
      (footprint "eagle-import:SK6805-EC_IPIXEL")
      (fields (field (name "MANUFACTURER") "iPixel") (field (name "VOLTAGE") "5.5 V"))
      (libsource (lib "eagle-import") (part "SK6805-EC15"))
    )
    (comp (ref "IC149")
      (value "SK6805-EC15")
      (footprint "eagle-import:SK6805-EC_IPIXEL")
      (fields (field (name "MANUFACTURER") "iPixel") (field (name "VOLTAGE") "5.5 V"))
      (libsource (lib "eagle-import") (part "SK6805-EC15"))
    )
    (comp (ref "IC150")
      (value "SK6805-EC15")
      (footprint "eagle-import:SK6805-EC_IPIXEL")
      (fields (field (name "MANUFACTURER") "iPixel") (field (name "VOLTAGE") "5.5 V"))
      (libsource (lib "eagle-import") (part "SK6805-EC15"))
    )
    (comp (ref "IC151")
      (value "SK6805-EC15")
      (footprint "eagle-import:SK6805-EC_IPIXEL")
      (fields (field (name "MANUFACTURER") "iPixel") (field (name "VOLTAGE") "5.5 V"))
      (libsource (lib "eagle-import") (part "SK6805-EC15"))
    )
    (comp (ref "IC152")
      (value "SK6805-EC15")
      (footprint "eagle-import:SK6805-EC_IPIXEL")
      (fields (field (name "MANUFACTURER") "iPixel") (field (name "VOLTAGE") "5.5 V"))
      (libsource (lib "eagle-import") (part "SK6805-EC15"))
    )
    (comp (ref "IC153")
      (value "SK6805-EC15")
      (footprint "eagle-import:SK6805-EC_IPIXEL")
      (fields (field (name "MANUFACTURER") "iPixel") (field (name "VOLTAGE") "5.5 V"))
      (libsource (lib "eagle-import") (part "SK6805-EC15"))
    )
    (comp (ref "IC154")
      (value "SK6805-EC15")
      (footprint "eagle-import:SK6805-EC_IPIXEL")
      (fields (field (name "MANUFACTURER") "iPixel") (field (name "VOLTAGE") "5.5 V"))
      (libsource (lib "eagle-import") (part "SK6805-EC15"))
    )
    (comp (ref "IC155")
      (value "SK6805-EC15")
      (footprint "eagle-import:SK6805-EC_IPIXEL")
      (fields (field (name "MANUFACTURER") "iPixel") (field (name "VOLTAGE") "5.5 V"))
      (libsource (lib "eagle-import") (part "SK6805-EC15"))
    )
    (comp (ref "IC156")
      (value "SK6805-EC15")
      (footprint "eagle-import:SK6805-EC_IPIXEL")
      (fields (field (name "MANUFACTURER") "iPixel") (field (name "VOLTAGE") "5.5 V"))
      (libsource (lib "eagle-import") (part "SK6805-EC15"))
    )
    (comp (ref "IC157")
      (value "SK6805-EC15")
      (footprint "eagle-import:SK6805-EC_IPIXEL")
      (fields (field (name "MANUFACTURER") "iPixel") (field (name "VOLTAGE") "5.5 V"))
      (libsource (lib "eagle-import") (part "SK6805-EC15"))
    )
    (comp (ref "IC158")
      (value "SK6805-EC15")
      (footprint "eagle-import:SK6805-EC_IPIXEL")
      (fields (field (name "MANUFACTURER") "iPixel") (field (name "VOLTAGE") "5.5 V"))
      (libsource (lib "eagle-import") (part "SK6805-EC15"))
    )
    (comp (ref "IC159")
      (value "SK6805-EC15")
      (footprint "eagle-import:SK6805-EC_IPIXEL")
      (fields (field (name "MANUFACTURER") "iPixel") (field (name "VOLTAGE") "5.5 V"))
      (libsource (lib "eagle-import") (part "SK6805-EC15"))
    )
    (comp (ref "IC160")
      (value "SK6805-EC15")
      (footprint "eagle-import:SK6805-EC_IPIXEL")
      (fields (field (name "MANUFACTURER") "iPixel") (field (name "VOLTAGE") "5.5 V"))
      (libsource (lib "eagle-import") (part "SK6805-EC15"))
    )
    (comp (ref "IC161")
      (value "SK6805-EC15")
      (footprint "eagle-import:SK6805-EC_IPIXEL")
      (fields (field (name "MANUFACTURER") "iPixel") (field (name "VOLTAGE") "5.5 V"))
      (libsource (lib "eagle-import") (part "SK6805-EC15"))
    )
    (comp (ref "IC162")
      (value "SK6805-EC15")
      (footprint "eagle-import:SK6805-EC_IPIXEL")
      (fields (field (name "MANUFACTURER") "iPixel") (field (name "VOLTAGE") "5.5 V"))
      (libsource (lib "eagle-import") (part "SK6805-EC15"))
    )
    (comp (ref "IC163")
      (value "SK6805-EC15")
      (footprint "eagle-import:SK6805-EC_IPIXEL")
      (fields (field (name "MANUFACTURER") "iPixel") (field (name "VOLTAGE") "5.5 V"))
      (libsource (lib "eagle-import") (part "SK6805-EC15"))
    )
    (comp (ref "IC164")
      (value "SK6805-EC15")
      (footprint "eagle-import:SK6805-EC_IPIXEL")
      (fields (field (name "MANUFACTURER") "iPixel") (field (name "VOLTAGE") "5.5 V"))
      (libsource (lib "eagle-import") (part "SK6805-EC15"))
    )
    (comp (ref "IC165")
      (value "SK6805-EC15")
      (footprint "eagle-import:SK6805-EC_IPIXEL")
      (fields (field (name "MANUFACTURER") "iPixel") (field (name "VOLTAGE") "5.5 V"))
      (libsource (lib "eagle-import") (part "SK6805-EC15"))
    )
    (comp (ref "IC166")
      (value "SK6805-EC15")
      (footprint "eagle-import:SK6805-EC_IPIXEL")
      (fields (field (name "MANUFACTURER") "iPixel") (field (name "VOLTAGE") "5.5 V"))
      (libsource (lib "eagle-import") (part "SK6805-EC15"))
    )
    (comp (ref "IC167")
      (value "SK6805-EC15")
      (footprint "eagle-import:SK6805-EC_IPIXEL")
      (fields (field (name "MANUFACTURER") "iPixel") (field (name "VOLTAGE") "5.5 V"))
      (libsource (lib "eagle-import") (part "SK6805-EC15"))
    )
    (comp (ref "IC168")
      (value "SK6805-EC15")
      (footprint "eagle-import:SK6805-EC_IPIXEL")
      (fields (field (name "MANUFACTURER") "iPixel") (field (name "VOLTAGE") "5.5 V"))
      (libsource (lib "eagle-import") (part "SK6805-EC15"))
    )
    (comp (ref "IC169")
      (value "SK6805-EC15")
      (footprint "eagle-import:SK6805-EC_IPIXEL")
      (fields (field (name "MANUFACTURER") "iPixel") (field (name "VOLTAGE") "5.5 V"))
      (libsource (lib "eagle-import") (part "SK6805-EC15"))
    )
    (comp (ref "IC170")
      (value "SK6805-EC15")
      (footprint "eagle-import:SK6805-EC_IPIXEL")
      (fields (field (name "MANUFACTURER") "iPixel") (field (name "VOLTAGE") "5.5 V"))
      (libsource (lib "eagle-import") (part "SK6805-EC15"))
    )
    (comp (ref "IC171")
      (value "SK6805-EC15")
      (footprint "eagle-import:SK6805-EC_IPIXEL")
      (fields (field (name "MANUFACTURER") "iPixel") (field (name "VOLTAGE") "5.5 V"))
      (libsource (lib "eagle-import") (part "SK6805-EC15"))
    )
    (comp (ref "IC172")
      (value "SK6805-EC15")
      (footprint "eagle-import:SK6805-EC_IPIXEL")
      (fields (field (name "MANUFACTURER") "iPixel") (field (name "VOLTAGE") "5.5 V"))
      (libsource (lib "eagle-import") (part "SK6805-EC15"))
    )
    (comp (ref "IC173")
      (value "SK6805-EC15")
      (footprint "eagle-import:SK6805-EC_IPIXEL")
      (fields (field (name "MANUFACTURER") "iPixel") (field (name "VOLTAGE") "5.5 V"))
      (libsource (lib "eagle-import") (part "SK6805-EC15"))
    )
    (comp (ref "IC174")
      (value "SK6805-EC15")
      (footprint "eagle-import:SK6805-EC_IPIXEL")
      (fields (field (name "MANUFACTURER") "iPixel") (field (name "VOLTAGE") "5.5 V"))
      (libsource (lib "eagle-import") (part "SK6805-EC15"))
    )
    (comp (ref "IC175")
      (value "SK6805-EC15")
      (footprint "eagle-import:SK6805-EC_IPIXEL")
      (fields (field (name "MANUFACTURER") "iPixel") (field (name "VOLTAGE") "5.5 V"))
      (libsource (lib "eagle-import") (part "SK6805-EC15"))
    )
    (comp (ref "IC176")
      (value "SK6805-EC15")
      (footprint "eagle-import:SK6805-EC_IPIXEL")
      (fields (field (name "MANUFACTURER") "iPixel") (field (name "VOLTAGE") "5.5 V"))
      (libsource (lib "eagle-import") (part "SK6805-EC15"))
    )
    (comp (ref "IC177")
      (value "SK6805-EC15")
      (footprint "eagle-import:SK6805-EC_IPIXEL")
      (fields (field (name "MANUFACTURER") "iPixel") (field (name "VOLTAGE") "5.5 V"))
      (libsource (lib "eagle-import") (part "SK6805-EC15"))
    )
    (comp (ref "IC178")
      (value "SK6805-EC15")
      (footprint "eagle-import:SK6805-EC_IPIXEL")
      (fields (field (name "MANUFACTURER") "iPixel") (field (name "VOLTAGE") "5.5 V"))
      (libsource (lib "eagle-import") (part "SK6805-EC15"))
    )
    (comp (ref "IC179")
      (value "SK6805-EC15")
      (footprint "eagle-import:SK6805-EC_IPIXEL")
      (fields (field (name "MANUFACTURER") "iPixel") (field (name "VOLTAGE") "5.5 V"))
      (libsource (lib "eagle-import") (part "SK6805-EC15"))
    )
    (comp (ref "IC180")
      (value "SK6805-EC15")
      (footprint "eagle-import:SK6805-EC_IPIXEL")
      (fields (field (name "MANUFACTURER") "iPixel") (field (name "VOLTAGE") "5.5 V"))
      (libsource (lib "eagle-import") (part "SK6805-EC15"))
    )
    (comp (ref "IC181")
      (value "SK6805-EC15")
      (footprint "eagle-import:SK6805-EC_IPIXEL")
      (fields (field (name "MANUFACTURER") "iPixel") (field (name "VOLTAGE") "5.5 V"))
      (libsource (lib "eagle-import") (part "SK6805-EC15"))
    )
    (comp (ref "IC182")
      (value "SK6805-EC15")
      (footprint "eagle-import:SK6805-EC_IPIXEL")
      (fields (field (name "MANUFACTURER") "iPixel") (field (name "VOLTAGE") "5.5 V"))
      (libsource (lib "eagle-import") (part "SK6805-EC15"))
    )
    (comp (ref "IC183")
      (value "SK6805-EC15")
      (footprint "eagle-import:SK6805-EC_IPIXEL")
      (fields (field (name "MANUFACTURER") "iPixel") (field (name "VOLTAGE") "5.5 V"))
      (libsource (lib "eagle-import") (part "SK6805-EC15"))
    )
    (comp (ref "IC184")
      (value "SK6805-EC15")
      (footprint "eagle-import:SK6805-EC_IPIXEL")
      (fields (field (name "MANUFACTURER") "iPixel") (field (name "VOLTAGE") "5.5 V"))
      (libsource (lib "eagle-import") (part "SK6805-EC15"))
    )
    (comp (ref "IC185")
      (value "SK6805-EC15")
      (footprint "eagle-import:SK6805-EC_IPIXEL")
      (fields (field (name "MANUFACTURER") "iPixel") (field (name "VOLTAGE") "5.5 V"))
      (libsource (lib "eagle-import") (part "SK6805-EC15"))
    )
    (comp (ref "IC186")
      (value "SK6805-EC15")
      (footprint "eagle-import:SK6805-EC_IPIXEL")
      (fields (field (name "MANUFACTURER") "iPixel") (field (name "VOLTAGE") "5.5 V"))
      (libsource (lib "eagle-import") (part "SK6805-EC15"))
    )
    (comp (ref "IC187")
      (value "SK6805-EC15")
      (footprint "eagle-import:SK6805-EC_IPIXEL")
      (fields (field (name "MANUFACTURER") "iPixel") (field (name "VOLTAGE") "5.5 V"))
      (libsource (lib "eagle-import") (part "SK6805-EC15"))
    )
    (comp (ref "IC188")
      (value "SK6805-EC15")
      (footprint "eagle-import:SK6805-EC_IPIXEL")
      (fields (field (name "MANUFACTURER") "iPixel") (field (name "VOLTAGE") "5.5 V"))
      (libsource (lib "eagle-import") (part "SK6805-EC15"))
    )
    (comp (ref "IC189")
      (value "SK6805-EC15")
      (footprint "eagle-import:SK6805-EC_IPIXEL")
      (fields (field (name "MANUFACTURER") "iPixel") (field (name "VOLTAGE") "5.5 V"))
      (libsource (lib "eagle-import") (part "SK6805-EC15"))
    )
    (comp (ref "IC190")
      (value "SK6805-EC15")
      (footprint "eagle-import:SK6805-EC_IPIXEL")
      (fields (field (name "MANUFACTURER") "iPixel") (field (name "VOLTAGE") "5.5 V"))
      (libsource (lib "eagle-import") (part "SK6805-EC15"))
    )
    (comp (ref "IC191")
      (value "SK6805-EC15")
      (footprint "eagle-import:SK6805-EC_IPIXEL")
      (fields (field (name "MANUFACTURER") "iPixel") (field (name "VOLTAGE") "5.5 V"))
      (libsource (lib "eagle-import") (part "SK6805-EC15"))
    )
    (comp (ref "IC192")
      (value "SK6805-EC15")
      (footprint "eagle-import:SK6805-EC_IPIXEL")
      (fields (field (name "MANUFACTURER") "iPixel") (field (name "VOLTAGE") "5.5 V"))
      (libsource (lib "eagle-import") (part "SK6805-EC15"))
    )
    (comp (ref "IC193")
      (value "SK6805-EC15")
      (footprint "eagle-import:SK6805-EC_IPIXEL")
      (fields (field (name "MANUFACTURER") "iPixel") (field (name "VOLTAGE") "5.5 V"))
      (libsource (lib "eagle-import") (part "SK6805-EC15"))
    )
    (comp (ref "IC194")
      (value "SK6805-EC15")
      (footprint "eagle-import:SK6805-EC_IPIXEL")
      (fields (field (name "MANUFACTURER") "iPixel") (field (name "VOLTAGE") "5.5 V"))
      (libsource (lib "eagle-import") (part "SK6805-EC15"))
    )
    (comp (ref "IC195")
      (value "SK6805-EC15")
      (footprint "eagle-import:SK6805-EC_IPIXEL")
      (fields (field (name "MANUFACTURER") "iPixel") (field (name "VOLTAGE") "5.5 V"))
      (libsource (lib "eagle-import") (part "SK6805-EC15"))
    )
    (comp (ref "IC196")
      (value "SK6805-EC15")
      (footprint "eagle-import:SK6805-EC_IPIXEL")
      (fields (field (name "MANUFACTURER") "iPixel") (field (name "VOLTAGE") "5.5 V"))
      (libsource (lib "eagle-import") (part "SK6805-EC15"))
    )
    (comp (ref "IC197")
      (value "SK6805-EC15")
      (footprint "eagle-import:SK6805-EC_IPIXEL")
      (fields (field (name "MANUFACTURER") "iPixel") (field (name "VOLTAGE") "5.5 V"))
      (libsource (lib "eagle-import") (part "SK6805-EC15"))
    )
    (comp (ref "IC198")
      (value "SK6805-EC15")
      (footprint "eagle-import:SK6805-EC_IPIXEL")
      (fields (field (name "MANUFACTURER") "iPixel") (field (name "VOLTAGE") "5.5 V"))
      (libsource (lib "eagle-import") (part "SK6805-EC15"))
    )
    (comp (ref "IC199")
      (value "SK6805-EC15")
      (footprint "eagle-import:SK6805-EC_IPIXEL")
      (fields (field (name "MANUFACTURER") "iPixel") (field (name "VOLTAGE") "5.5 V"))
      (libsource (lib "eagle-import") (part "SK6805-EC15"))
    )
    (comp (ref "IC200")
      (value "SK6805-EC15")
      (footprint "eagle-import:SK6805-EC_IPIXEL")
      (fields (field (name "MANUFACTURER") "iPixel") (field (name "VOLTAGE") "5.5 V"))
      (libsource (lib "eagle-import") (part "SK6805-EC15"))
    )
    (comp (ref "IC201")
      (value "SK6805-EC15")
      (footprint "eagle-import:SK6805-EC_IPIXEL")
      (fields (field (name "MANUFACTURER") "iPixel") (field (name "VOLTAGE") "5.5 V"))
      (libsource (lib "eagle-import") (part "SK6805-EC15"))
    )
    (comp (ref "IC202")
      (value "SK6805-EC15")
      (footprint "eagle-import:SK6805-EC_IPIXEL")
      (fields (field (name "MANUFACTURER") "iPixel") (field (name "VOLTAGE") "5.5 V"))
      (libsource (lib "eagle-import") (part "SK6805-EC15"))
    )
    (comp (ref "IC203")
      (value "SK6805-EC15")
      (footprint "eagle-import:SK6805-EC_IPIXEL")
      (fields (field (name "MANUFACTURER") "iPixel") (field (name "VOLTAGE") "5.5 V"))
      (libsource (lib "eagle-import") (part "SK6805-EC15"))
    )
    (comp (ref "IC204")
      (value "SK6805-EC15")
      (footprint "eagle-import:SK6805-EC_IPIXEL")
      (fields (field (name "MANUFACTURER") "iPixel") (field (name "VOLTAGE") "5.5 V"))
      (libsource (lib "eagle-import") (part "SK6805-EC15"))
    )
    (comp (ref "IC205")
      (value "SK6805-EC15")
      (footprint "eagle-import:SK6805-EC_IPIXEL")
      (fields (field (name "MANUFACTURER") "iPixel") (field (name "VOLTAGE") "5.5 V"))
      (libsource (lib "eagle-import") (part "SK6805-EC15"))
    )
    (comp (ref "IC206")
      (value "SK6805-EC15")
      (footprint "eagle-import:SK6805-EC_IPIXEL")
      (fields (field (name "MANUFACTURER") "iPixel") (field (name "VOLTAGE") "5.5 V"))
      (libsource (lib "eagle-import") (part "SK6805-EC15"))
    )
    (comp (ref "IC207")
      (value "SK6805-EC15")
      (footprint "eagle-import:SK6805-EC_IPIXEL")
      (fields (field (name "MANUFACTURER") "iPixel") (field (name "VOLTAGE") "5.5 V"))
      (libsource (lib "eagle-import") (part "SK6805-EC15"))
    )
    (comp (ref "IC208")
      (value "SK6805-EC15")
      (footprint "eagle-import:SK6805-EC_IPIXEL")
      (fields (field (name "MANUFACTURER") "iPixel") (field (name "VOLTAGE") "5.5 V"))
      (libsource (lib "eagle-import") (part "SK6805-EC15"))
    )
    (comp (ref "IC209")
      (value "SK6805-EC15")
      (footprint "eagle-import:SK6805-EC_IPIXEL")
      (fields (field (name "MANUFACTURER") "iPixel") (field (name "VOLTAGE") "5.5 V"))
      (libsource (lib "eagle-import") (part "SK6805-EC15"))
    )
    (comp (ref "IC210")
      (value "SK6805-EC15")
      (footprint "eagle-import:SK6805-EC_IPIXEL")
      (fields (field (name "MANUFACTURER") "iPixel") (field (name "VOLTAGE") "5.5 V"))
      (libsource (lib "eagle-import") (part "SK6805-EC15"))
    )
    (comp (ref "IC211")
      (value "SK6805-EC15")
      (footprint "eagle-import:SK6805-EC_IPIXEL")
      (fields (field (name "MANUFACTURER") "iPixel") (field (name "VOLTAGE") "5.5 V"))
      (libsource (lib "eagle-import") (part "SK6805-EC15"))
    )
    (comp (ref "IC212")
      (value "SK6805-EC15")
      (footprint "eagle-import:SK6805-EC_IPIXEL")
      (fields (field (name "MANUFACTURER") "iPixel") (field (name "VOLTAGE") "5.5 V"))
      (libsource (lib "eagle-import") (part "SK6805-EC15"))
    )
    (comp (ref "IC213")
      (value "SK6805-EC15")
      (footprint "eagle-import:SK6805-EC_IPIXEL")
      (fields (field (name "MANUFACTURER") "iPixel") (field (name "VOLTAGE") "5.5 V"))
      (libsource (lib "eagle-import") (part "SK6805-EC15"))
    )
    (comp (ref "IC214")
      (value "SK6805-EC15")
      (footprint "eagle-import:SK6805-EC_IPIXEL")
      (fields (field (name "MANUFACTURER") "iPixel") (field (name "VOLTAGE") "5.5 V"))
      (libsource (lib "eagle-import") (part "SK6805-EC15"))
    )
    (comp (ref "IC215")
      (value "SK6805-EC15")
      (footprint "eagle-import:SK6805-EC_IPIXEL")
      (fields (field (name "MANUFACTURER") "iPixel") (field (name "VOLTAGE") "5.5 V"))
      (libsource (lib "eagle-import") (part "SK6805-EC15"))
    )
    (comp (ref "IC216")
      (value "SK6805-EC15")
      (footprint "eagle-import:SK6805-EC_IPIXEL")
      (fields (field (name "MANUFACTURER") "iPixel") (field (name "VOLTAGE") "5.5 V"))
      (libsource (lib "eagle-import") (part "SK6805-EC15"))
    )
    (comp (ref "IC217")
      (value "SK6805-EC15")
      (footprint "eagle-import:SK6805-EC_IPIXEL")
      (fields (field (name "MANUFACTURER") "iPixel") (field (name "VOLTAGE") "5.5 V"))
      (libsource (lib "eagle-import") (part "SK6805-EC15"))
    )
    (comp (ref "IC218")
      (value "SK6805-EC15")
      (footprint "eagle-import:SK6805-EC_IPIXEL")
      (fields (field (name "MANUFACTURER") "iPixel") (field (name "VOLTAGE") "5.5 V"))
      (libsource (lib "eagle-import") (part "SK6805-EC15"))
    )
    (comp (ref "IC219")
      (value "SK6805-EC15")
      (footprint "eagle-import:SK6805-EC_IPIXEL")
      (fields (field (name "MANUFACTURER") "iPixel") (field (name "VOLTAGE") "5.5 V"))
      (libsource (lib "eagle-import") (part "SK6805-EC15"))
    )
    (comp (ref "IC220")
      (value "SK6805-EC15")
      (footprint "eagle-import:SK6805-EC_IPIXEL")
      (fields (field (name "MANUFACTURER") "iPixel") (field (name "VOLTAGE") "5.5 V"))
      (libsource (lib "eagle-import") (part "SK6805-EC15"))
    )
    (comp (ref "IC221")
      (value "SK6805-EC15")
      (footprint "eagle-import:SK6805-EC_IPIXEL")
      (fields (field (name "MANUFACTURER") "iPixel") (field (name "VOLTAGE") "5.5 V"))
      (libsource (lib "eagle-import") (part "SK6805-EC15"))
    )
    (comp (ref "IC222")
      (value "SK6805-EC15")
      (footprint "eagle-import:SK6805-EC_IPIXEL")
      (fields (field (name "MANUFACTURER") "iPixel") (field (name "VOLTAGE") "5.5 V"))
      (libsource (lib "eagle-import") (part "SK6805-EC15"))
    )
    (comp (ref "IC223")
      (value "SK6805-EC15")
      (footprint "eagle-import:SK6805-EC_IPIXEL")
      (fields (field (name "MANUFACTURER") "iPixel") (field (name "VOLTAGE") "5.5 V"))
      (libsource (lib "eagle-import") (part "SK6805-EC15"))
    )
    (comp (ref "IC224")
      (value "SK6805-EC15")
      (footprint "eagle-import:SK6805-EC_IPIXEL")
      (fields (field (name "MANUFACTURER") "iPixel") (field (name "VOLTAGE") "5.5 V"))
      (libsource (lib "eagle-import") (part "SK6805-EC15"))
    )
    (comp (ref "IC225")
      (value "SK6805-EC15")
      (footprint "eagle-import:SK6805-EC_IPIXEL")
      (fields (field (name "MANUFACTURER") "iPixel") (field (name "VOLTAGE") "5.5 V"))
      (libsource (lib "eagle-import") (part "SK6805-EC15"))
    )
    (comp (ref "IC226")
      (value "SK6805-EC15")
      (footprint "eagle-import:SK6805-EC_IPIXEL")
      (fields (field (name "MANUFACTURER") "iPixel") (field (name "VOLTAGE") "5.5 V"))
      (libsource (lib "eagle-import") (part "SK6805-EC15"))
    )
    (comp (ref "IC227")
      (value "SK6805-EC15")
      (footprint "eagle-import:SK6805-EC_IPIXEL")
      (fields (field (name "MANUFACTURER") "iPixel") (field (name "VOLTAGE") "5.5 V"))
      (libsource (lib "eagle-import") (part "SK6805-EC15"))
    )
    (comp (ref "IC228")
      (value "SK6805-EC15")
      (footprint "eagle-import:SK6805-EC_IPIXEL")
      (fields (field (name "MANUFACTURER") "iPixel") (field (name "VOLTAGE") "5.5 V"))
      (libsource (lib "eagle-import") (part "SK6805-EC15"))
    )
    (comp (ref "IC229")
      (value "SK6805-EC15")
      (footprint "eagle-import:SK6805-EC_IPIXEL")
      (fields (field (name "MANUFACTURER") "iPixel") (field (name "VOLTAGE") "5.5 V"))
      (libsource (lib "eagle-import") (part "SK6805-EC15"))
    )
    (comp (ref "IC230")
      (value "SK6805-EC15")
      (footprint "eagle-import:SK6805-EC_IPIXEL")
      (fields (field (name "MANUFACTURER") "iPixel") (field (name "VOLTAGE") "5.5 V"))
      (libsource (lib "eagle-import") (part "SK6805-EC15"))
    )
    (comp (ref "IC231")
      (value "SK6805-EC15")
      (footprint "eagle-import:SK6805-EC_IPIXEL")
      (fields (field (name "MANUFACTURER") "iPixel") (field (name "VOLTAGE") "5.5 V"))
      (libsource (lib "eagle-import") (part "SK6805-EC15"))
    )
    (comp (ref "IC232")
      (value "SK6805-EC15")
      (footprint "eagle-import:SK6805-EC_IPIXEL")
      (fields (field (name "MANUFACTURER") "iPixel") (field (name "VOLTAGE") "5.5 V"))
      (libsource (lib "eagle-import") (part "SK6805-EC15"))
    )
    (comp (ref "IC233")
      (value "SK6805-EC15")
      (footprint "eagle-import:SK6805-EC_IPIXEL")
      (fields (field (name "MANUFACTURER") "iPixel") (field (name "VOLTAGE") "5.5 V"))
      (libsource (lib "eagle-import") (part "SK6805-EC15"))
    )
    (comp (ref "IC234")
      (value "SK6805-EC15")
      (footprint "eagle-import:SK6805-EC_IPIXEL")
      (fields (field (name "MANUFACTURER") "iPixel") (field (name "VOLTAGE") "5.5 V"))
      (libsource (lib "eagle-import") (part "SK6805-EC15"))
    )
    (comp (ref "IC235")
      (value "SK6805-EC15")
      (footprint "eagle-import:SK6805-EC_IPIXEL")
      (fields (field (name "MANUFACTURER") "iPixel") (field (name "VOLTAGE") "5.5 V"))
      (libsource (lib "eagle-import") (part "SK6805-EC15"))
    )
    (comp (ref "IC236")
      (value "SK6805-EC15")
      (footprint "eagle-import:SK6805-EC_IPIXEL")
      (fields (field (name "MANUFACTURER") "iPixel") (field (name "VOLTAGE") "5.5 V"))
      (libsource (lib "eagle-import") (part "SK6805-EC15"))
    )
    (comp (ref "IC237")
      (value "SK6805-EC15")
      (footprint "eagle-import:SK6805-EC_IPIXEL")
      (fields (field (name "MANUFACTURER") "iPixel") (field (name "VOLTAGE") "5.5 V"))
      (libsource (lib "eagle-import") (part "SK6805-EC15"))
    )
    (comp (ref "IC238")
      (value "SK6805-EC15")
      (footprint "eagle-import:SK6805-EC_IPIXEL")
      (fields (field (name "MANUFACTURER") "iPixel") (field (name "VOLTAGE") "5.5 V"))
      (libsource (lib "eagle-import") (part "SK6805-EC15"))
    )
    (comp (ref "IC239")
      (value "SK6805-EC15")
      (footprint "eagle-import:SK6805-EC_IPIXEL")
      (fields (field (name "MANUFACTURER") "iPixel") (field (name "VOLTAGE") "5.5 V"))
      (libsource (lib "eagle-import") (part "SK6805-EC15"))
    )
    (comp (ref "IC240")
      (value "SK6805-EC15")
      (footprint "eagle-import:SK6805-EC_IPIXEL")
      (fields (field (name "MANUFACTURER") "iPixel") (field (name "VOLTAGE") "5.5 V"))
      (libsource (lib "eagle-import") (part "SK6805-EC15"))
    )
    (comp (ref "IC241")
      (value "SK6805-EC15")
      (footprint "eagle-import:SK6805-EC_IPIXEL")
      (fields (field (name "MANUFACTURER") "iPixel") (field (name "VOLTAGE") "5.5 V"))
      (libsource (lib "eagle-import") (part "SK6805-EC15"))
    )
    (comp (ref "IC242")
      (value "SK6805-EC15")
      (footprint "eagle-import:SK6805-EC_IPIXEL")
      (fields (field (name "MANUFACTURER") "iPixel") (field (name "VOLTAGE") "5.5 V"))
      (libsource (lib "eagle-import") (part "SK6805-EC15"))
    )
    (comp (ref "IC243")
      (value "SK6805-EC15")
      (footprint "eagle-import:SK6805-EC_IPIXEL")
      (fields (field (name "MANUFACTURER") "iPixel") (field (name "VOLTAGE") "5.5 V"))
      (libsource (lib "eagle-import") (part "SK6805-EC15"))
    )
    (comp (ref "IC244")
      (value "SK6805-EC15")
      (footprint "eagle-import:SK6805-EC_IPIXEL")
      (fields (field (name "MANUFACTURER") "iPixel") (field (name "VOLTAGE") "5.5 V"))
      (libsource (lib "eagle-import") (part "SK6805-EC15"))
    )
    (comp (ref "IC245")
      (value "SK6805-EC15")
      (footprint "eagle-import:SK6805-EC_IPIXEL")
      (fields (field (name "MANUFACTURER") "iPixel") (field (name "VOLTAGE") "5.5 V"))
      (libsource (lib "eagle-import") (part "SK6805-EC15"))
    )
    (comp (ref "IC246")
      (value "SK6805-EC15")
      (footprint "eagle-import:SK6805-EC_IPIXEL")
      (fields (field (name "MANUFACTURER") "iPixel") (field (name "VOLTAGE") "5.5 V"))
      (libsource (lib "eagle-import") (part "SK6805-EC15"))
    )
    (comp (ref "IC247")
      (value "SK6805-EC15")
      (footprint "eagle-import:SK6805-EC_IPIXEL")
      (fields (field (name "MANUFACTURER") "iPixel") (field (name "VOLTAGE") "5.5 V"))
      (libsource (lib "eagle-import") (part "SK6805-EC15"))
    )
    (comp (ref "IC248")
      (value "SK6805-EC15")
      (footprint "eagle-import:SK6805-EC_IPIXEL")
      (fields (field (name "MANUFACTURER") "iPixel") (field (name "VOLTAGE") "5.5 V"))
      (libsource (lib "eagle-import") (part "SK6805-EC15"))
    )
    (comp (ref "IC249")
      (value "SK6805-EC15")
      (footprint "eagle-import:SK6805-EC_IPIXEL")
      (fields (field (name "MANUFACTURER") "iPixel") (field (name "VOLTAGE") "5.5 V"))
      (libsource (lib "eagle-import") (part "SK6805-EC15"))
    )
    (comp (ref "IC250")
      (value "SK6805-EC15")
      (footprint "eagle-import:SK6805-EC_IPIXEL")
      (fields (field (name "MANUFACTURER") "iPixel") (field (name "VOLTAGE") "5.5 V"))
      (libsource (lib "eagle-import") (part "SK6805-EC15"))
    )
    (comp (ref "IC251")
      (value "SK6805-EC15")
      (footprint "eagle-import:SK6805-EC_IPIXEL")
      (fields (field (name "MANUFACTURER") "iPixel") (field (name "VOLTAGE") "5.5 V"))
      (libsource (lib "eagle-import") (part "SK6805-EC15"))
    )
    (comp (ref "IC252")
      (value "SK6805-EC15")
      (footprint "eagle-import:SK6805-EC_IPIXEL")
      (fields (field (name "MANUFACTURER") "iPixel") (field (name "VOLTAGE") "5.5 V"))
      (libsource (lib "eagle-import") (part "SK6805-EC15"))
    )
    (comp (ref "IC253")
      (value "SK6805-EC15")
      (footprint "eagle-import:SK6805-EC_IPIXEL")
      (fields (field (name "MANUFACTURER") "iPixel") (field (name "VOLTAGE") "5.5 V"))
      (libsource (lib "eagle-import") (part "SK6805-EC15"))
    )
    (comp (ref "IC254")
      (value "SK6805-EC15")
      (footprint "eagle-import:SK6805-EC_IPIXEL")
      (fields (field (name "MANUFACTURER") "iPixel") (field (name "VOLTAGE") "5.5 V"))
      (libsource (lib "eagle-import") (part "SK6805-EC15"))
    )
    (comp (ref "IC255")
      (value "SK6805-EC15")
      (footprint "eagle-import:SK6805-EC_IPIXEL")
      (fields (field (name "MANUFACTURER") "iPixel") (field (name "VOLTAGE") "5.5 V"))
      (libsource (lib "eagle-import") (part "SK6805-EC15"))
    )
    (comp (ref "IC256")
      (value "SK6805-EC15")
      (footprint "eagle-import:SK6805-EC_IPIXEL")
      (fields (field (name "MANUFACTURER") "iPixel") (field (name "VOLTAGE") "5.5 V"))
      (libsource (lib "eagle-import") (part "SK6805-EC15"))
    )
    (comp (ref "IC257")
      (value "SK6805-EC15")
      (footprint "eagle-import:SK6805-EC_IPIXEL")
      (fields (field (name "MANUFACTURER") "iPixel") (field (name "VOLTAGE") "5.5 V"))
      (libsource (lib "eagle-import") (part "SK6805-EC15"))
    )
    (comp (ref "IC258")
      (value "SK6805-EC15")
      (footprint "eagle-import:SK6805-EC_IPIXEL")
      (fields (field (name "MANUFACTURER") "iPixel") (field (name "VOLTAGE") "5.5 V"))
      (libsource (lib "eagle-import") (part "SK6805-EC15"))
    )
    (comp (ref "IC259")
      (value "SK6805-EC15")
      (footprint "eagle-import:SK6805-EC_IPIXEL")
      (fields (field (name "MANUFACTURER") "iPixel") (field (name "VOLTAGE") "5.5 V"))
      (libsource (lib "eagle-import") (part "SK6805-EC15"))
    )
    (comp (ref "IC260")
      (value "SK6805-EC15")
      (footprint "eagle-import:SK6805-EC_IPIXEL")
      (fields (field (name "MANUFACTURER") "iPixel") (field (name "VOLTAGE") "5.5 V"))
      (libsource (lib "eagle-import") (part "SK6805-EC15"))
    )
    (comp (ref "IC261")
      (value "SK6805-EC15")
      (footprint "eagle-import:SK6805-EC_IPIXEL")
      (fields (field (name "MANUFACTURER") "iPixel") (field (name "VOLTAGE") "5.5 V"))
      (libsource (lib "eagle-import") (part "SK6805-EC15"))
    )
    (comp (ref "IC262")
      (value "SK6805-EC15")
      (footprint "eagle-import:SK6805-EC_IPIXEL")
      (fields (field (name "MANUFACTURER") "iPixel") (field (name "VOLTAGE") "5.5 V"))
      (libsource (lib "eagle-import") (part "SK6805-EC15"))
    )
    (comp (ref "IC263")
      (value "SK6805-EC15")
      (footprint "eagle-import:SK6805-EC_IPIXEL")
      (fields (field (name "MANUFACTURER") "iPixel") (field (name "VOLTAGE") "5.5 V"))
      (libsource (lib "eagle-import") (part "SK6805-EC15"))
    )
    (comp (ref "IC264")
      (value "SK6805-EC15")
      (footprint "eagle-import:SK6805-EC_IPIXEL")
      (fields (field (name "MANUFACTURER") "iPixel") (field (name "VOLTAGE") "5.5 V"))
      (libsource (lib "eagle-import") (part "SK6805-EC15"))
    )
    (comp (ref "IC265")
      (value "SK6805-EC15")
      (footprint "eagle-import:SK6805-EC_IPIXEL")
      (fields (field (name "MANUFACTURER") "iPixel") (field (name "VOLTAGE") "5.5 V"))
      (libsource (lib "eagle-import") (part "SK6805-EC15"))
    )
    (comp (ref "IC266")
      (value "SK6805-EC15")
      (footprint "eagle-import:SK6805-EC_IPIXEL")
      (fields (field (name "MANUFACTURER") "iPixel") (field (name "VOLTAGE") "5.5 V"))
      (libsource (lib "eagle-import") (part "SK6805-EC15"))
    )
    (comp (ref "IC267")
      (value "SK6805-EC15")
      (footprint "eagle-import:SK6805-EC_IPIXEL")
      (fields (field (name "MANUFACTURER") "iPixel") (field (name "VOLTAGE") "5.5 V"))
      (libsource (lib "eagle-import") (part "SK6805-EC15"))
    )
    (comp (ref "IC268")
      (value "SK6805-EC15")
      (footprint "eagle-import:SK6805-EC_IPIXEL")
      (fields (field (name "MANUFACTURER") "iPixel") (field (name "VOLTAGE") "5.5 V"))
      (libsource (lib "eagle-import") (part "SK6805-EC15"))
    )
    (comp (ref "IC269")
      (value "SK6805-EC15")
      (footprint "eagle-import:SK6805-EC_IPIXEL")
      (fields (field (name "MANUFACTURER") "iPixel") (field (name "VOLTAGE") "5.5 V"))
      (libsource (lib "eagle-import") (part "SK6805-EC15"))
    )
    (comp (ref "IC270")
      (value "SK6805-EC15")
      (footprint "eagle-import:SK6805-EC_IPIXEL")
      (fields (field (name "MANUFACTURER") "iPixel") (field (name "VOLTAGE") "5.5 V"))
      (libsource (lib "eagle-import") (part "SK6805-EC15"))
    )
    (comp (ref "IC271")
      (value "SK6805-EC15")
      (footprint "eagle-import:SK6805-EC_IPIXEL")
      (fields (field (name "MANUFACTURER") "iPixel") (field (name "VOLTAGE") "5.5 V"))
      (libsource (lib "eagle-import") (part "SK6805-EC15"))
    )
    (comp (ref "IC272")
      (value "SK6805-EC15")
      (footprint "eagle-import:SK6805-EC_IPIXEL")
      (fields (field (name "MANUFACTURER") "iPixel") (field (name "VOLTAGE") "5.5 V"))
      (libsource (lib "eagle-import") (part "SK6805-EC15"))
    )
    (comp (ref "IC273")
      (value "SK6805-EC15")
      (footprint "eagle-import:SK6805-EC_IPIXEL")
      (fields (field (name "MANUFACTURER") "iPixel") (field (name "VOLTAGE") "5.5 V"))
      (libsource (lib "eagle-import") (part "SK6805-EC15"))
    )
    (comp (ref "IC274")
      (value "SK6805-EC15")
      (footprint "eagle-import:SK6805-EC_IPIXEL")
      (fields (field (name "MANUFACTURER") "iPixel") (field (name "VOLTAGE") "5.5 V"))
      (libsource (lib "eagle-import") (part "SK6805-EC15"))
    )
    (comp (ref "IC275")
      (value "SK6805-EC15")
      (footprint "eagle-import:SK6805-EC_IPIXEL")
      (fields (field (name "MANUFACTURER") "iPixel") (field (name "VOLTAGE") "5.5 V"))
      (libsource (lib "eagle-import") (part "SK6805-EC15"))
    )
    (comp (ref "IC276")
      (value "SK6805-EC15")
      (footprint "eagle-import:SK6805-EC_IPIXEL")
      (fields (field (name "MANUFACTURER") "iPixel") (field (name "VOLTAGE") "5.5 V"))
      (libsource (lib "eagle-import") (part "SK6805-EC15"))
    )
    (comp (ref "IC277")
      (value "SK6805-EC15")
      (footprint "eagle-import:SK6805-EC_IPIXEL")
      (fields (field (name "MANUFACTURER") "iPixel") (field (name "VOLTAGE") "5.5 V"))
      (libsource (lib "eagle-import") (part "SK6805-EC15"))
    )
    (comp (ref "IC278")
      (value "SK6805-EC15")
      (footprint "eagle-import:SK6805-EC_IPIXEL")
      (fields (field (name "MANUFACTURER") "iPixel") (field (name "VOLTAGE") "5.5 V"))
      (libsource (lib "eagle-import") (part "SK6805-EC15"))
    )
    (comp (ref "IC279")
      (value "SK6805-EC15")
      (footprint "eagle-import:SK6805-EC_IPIXEL")
      (fields (field (name "MANUFACTURER") "iPixel") (field (name "VOLTAGE") "5.5 V"))
      (libsource (lib "eagle-import") (part "SK6805-EC15"))
    )
    (comp (ref "IC280")
      (value "SK6805-EC15")
      (footprint "eagle-import:SK6805-EC_IPIXEL")
      (fields (field (name "MANUFACTURER") "iPixel") (field (name "VOLTAGE") "5.5 V"))
      (libsource (lib "eagle-import") (part "SK6805-EC15"))
    )
    (comp (ref "IC281")
      (value "SK6805-EC15")
      (footprint "eagle-import:SK6805-EC_IPIXEL")
      (fields (field (name "MANUFACTURER") "iPixel") (field (name "VOLTAGE") "5.5 V"))
      (libsource (lib "eagle-import") (part "SK6805-EC15"))
    )
    (comp (ref "IC282")
      (value "SK6805-EC15")
      (footprint "eagle-import:SK6805-EC_IPIXEL")
      (fields (field (name "MANUFACTURER") "iPixel") (field (name "VOLTAGE") "5.5 V"))
      (libsource (lib "eagle-import") (part "SK6805-EC15"))
    )
    (comp (ref "IC283")
      (value "SK6805-EC15")
      (footprint "eagle-import:SK6805-EC_IPIXEL")
      (fields (field (name "MANUFACTURER") "iPixel") (field (name "VOLTAGE") "5.5 V"))
      (libsource (lib "eagle-import") (part "SK6805-EC15"))
    )
    (comp (ref "IC284")
      (value "SK6805-EC15")
      (footprint "eagle-import:SK6805-EC_IPIXEL")
      (fields (field (name "MANUFACTURER") "iPixel") (field (name "VOLTAGE") "5.5 V"))
      (libsource (lib "eagle-import") (part "SK6805-EC15"))
    )
    (comp (ref "IC285")
      (value "SK6805-EC15")
      (footprint "eagle-import:SK6805-EC_IPIXEL")
      (fields (field (name "MANUFACTURER") "iPixel") (field (name "VOLTAGE") "5.5 V"))
      (libsource (lib "eagle-import") (part "SK6805-EC15"))
    )
    (comp (ref "IC286")
      (value "SK6805-EC15")
      (footprint "eagle-import:SK6805-EC_IPIXEL")
      (fields (field (name "MANUFACTURER") "iPixel") (field (name "VOLTAGE") "5.5 V"))
      (libsource (lib "eagle-import") (part "SK6805-EC15"))
    )
    (comp (ref "IC287")
      (value "SK6805-EC15")
      (footprint "eagle-import:SK6805-EC_IPIXEL")
      (fields (field (name "MANUFACTURER") "iPixel") (field (name "VOLTAGE") "5.5 V"))
      (libsource (lib "eagle-import") (part "SK6805-EC15"))
    )
    (comp (ref "IC288")
      (value "SK6805-EC15")
      (footprint "eagle-import:SK6805-EC_IPIXEL")
      (fields (field (name "MANUFACTURER") "iPixel") (field (name "VOLTAGE") "5.5 V"))
      (libsource (lib "eagle-import") (part "SK6805-EC15"))
    )
    (comp (ref "IC289")
      (value "SK6805-EC15")
      (footprint "eagle-import:SK6805-EC_IPIXEL")
      (fields (field (name "MANUFACTURER") "iPixel") (field (name "VOLTAGE") "5.5 V"))
      (libsource (lib "eagle-import") (part "SK6805-EC15"))
    )
    (comp (ref "IC290")
      (value "SK6805-EC15")
      (footprint "eagle-import:SK6805-EC_IPIXEL")
      (fields (field (name "MANUFACTURER") "iPixel") (field (name "VOLTAGE") "5.5 V"))
      (libsource (lib "eagle-import") (part "SK6805-EC15"))
    )
    (comp (ref "IC291")
      (value "SK6805-EC15")
      (footprint "eagle-import:SK6805-EC_IPIXEL")
      (fields (field (name "MANUFACTURER") "iPixel") (field (name "VOLTAGE") "5.5 V"))
      (libsource (lib "eagle-import") (part "SK6805-EC15"))
    )
    (comp (ref "IC292")
      (value "SK6805-EC15")
      (footprint "eagle-import:SK6805-EC_IPIXEL")
      (fields (field (name "MANUFACTURER") "iPixel") (field (name "VOLTAGE") "5.5 V"))
      (libsource (lib "eagle-import") (part "SK6805-EC15"))
    )
    (comp (ref "IC293")
      (value "SK6805-EC15")
      (footprint "eagle-import:SK6805-EC_IPIXEL")
      (fields (field (name "MANUFACTURER") "iPixel") (field (name "VOLTAGE") "5.5 V"))
      (libsource (lib "eagle-import") (part "SK6805-EC15"))
    )
    (comp (ref "IC294")
      (value "SK6805-EC15")
      (footprint "eagle-import:SK6805-EC_IPIXEL")
      (fields (field (name "MANUFACTURER") "iPixel") (field (name "VOLTAGE") "5.5 V"))
      (libsource (lib "eagle-import") (part "SK6805-EC15"))
    )
    (comp (ref "IC295")
      (value "SK6805-EC15")
      (footprint "eagle-import:SK6805-EC_IPIXEL")
      (fields (field (name "MANUFACTURER") "iPixel") (field (name "VOLTAGE") "5.5 V"))
      (libsource (lib "eagle-import") (part "SK6805-EC15"))
    )
    (comp (ref "IC296")
      (value "SK6805-EC15")
      (footprint "eagle-import:SK6805-EC_IPIXEL")
      (fields (field (name "MANUFACTURER") "iPixel") (field (name "VOLTAGE") "5.5 V"))
      (libsource (lib "eagle-import") (part "SK6805-EC15"))
    )
    (comp (ref "IC297")
      (value "SK6805-EC15")
      (footprint "eagle-import:SK6805-EC_IPIXEL")
      (fields (field (name "MANUFACTURER") "iPixel") (field (name "VOLTAGE") "5.5 V"))
      (libsource (lib "eagle-import") (part "SK6805-EC15"))
    )
    (comp (ref "IC298")
      (value "SK6805-EC15")
      (footprint "eagle-import:SK6805-EC_IPIXEL")
      (fields (field (name "MANUFACTURER") "iPixel") (field (name "VOLTAGE") "5.5 V"))
      (libsource (lib "eagle-import") (part "SK6805-EC15"))
    )
    (comp (ref "IC299")
      (value "SK6805-EC15")
      (footprint "eagle-import:SK6805-EC_IPIXEL")
      (fields (field (name "MANUFACTURER") "iPixel") (field (name "VOLTAGE") "5.5 V"))
      (libsource (lib "eagle-import") (part "SK6805-EC15"))
    )
    (comp (ref "IC300")
      (value "SK6805-EC15")
      (footprint "eagle-import:SK6805-EC_IPIXEL")
      (fields (field (name "MANUFACTURER") "iPixel") (field (name "VOLTAGE") "5.5 V"))
      (libsource (lib "eagle-import") (part "SK6805-EC15"))
    )
    (comp (ref "IC301")
      (value "SK6805-EC15")
      (footprint "eagle-import:SK6805-EC_IPIXEL")
      (fields (field (name "MANUFACTURER") "iPixel") (field (name "VOLTAGE") "5.5 V"))
      (libsource (lib "eagle-import") (part "SK6805-EC15"))
    )
    (comp (ref "IC302")
      (value "SK6805-EC15")
      (footprint "eagle-import:SK6805-EC_IPIXEL")
      (fields (field (name "MANUFACTURER") "iPixel") (field (name "VOLTAGE") "5.5 V"))
      (libsource (lib "eagle-import") (part "SK6805-EC15"))
    )
    (comp (ref "IC303")
      (value "SK6805-EC15")
      (footprint "eagle-import:SK6805-EC_IPIXEL")
      (fields (field (name "MANUFACTURER") "iPixel") (field (name "VOLTAGE") "5.5 V"))
      (libsource (lib "eagle-import") (part "SK6805-EC15"))
    )
    (comp (ref "IC304")
      (value "SK6805-EC15")
      (footprint "eagle-import:SK6805-EC_IPIXEL")
      (fields (field (name "MANUFACTURER") "iPixel") (field (name "VOLTAGE") "5.5 V"))
      (libsource (lib "eagle-import") (part "SK6805-EC15"))
    )
    (comp (ref "IC305")
      (value "SK6805-EC15")
      (footprint "eagle-import:SK6805-EC_IPIXEL")
      (fields (field (name "MANUFACTURER") "iPixel") (field (name "VOLTAGE") "5.5 V"))
      (libsource (lib "eagle-import") (part "SK6805-EC15"))
    )
    (comp (ref "IC306")
      (value "SK6805-EC15")
      (footprint "eagle-import:SK6805-EC_IPIXEL")
      (fields (field (name "MANUFACTURER") "iPixel") (field (name "VOLTAGE") "5.5 V"))
      (libsource (lib "eagle-import") (part "SK6805-EC15"))
    )
    (comp (ref "IC307")
      (value "SK6805-EC15")
      (footprint "eagle-import:SK6805-EC_IPIXEL")
      (fields (field (name "MANUFACTURER") "iPixel") (field (name "VOLTAGE") "5.5 V"))
      (libsource (lib "eagle-import") (part "SK6805-EC15"))
    )
    (comp (ref "IC308")
      (value "SK6805-EC15")
      (footprint "eagle-import:SK6805-EC_IPIXEL")
      (fields (field (name "MANUFACTURER") "iPixel") (field (name "VOLTAGE") "5.5 V"))
      (libsource (lib "eagle-import") (part "SK6805-EC15"))
    )
    (comp (ref "IC309")
      (value "SK6805-EC15")
      (footprint "eagle-import:SK6805-EC_IPIXEL")
      (fields (field (name "MANUFACTURER") "iPixel") (field (name "VOLTAGE") "5.5 V"))
      (libsource (lib "eagle-import") (part "SK6805-EC15"))
    )
    (comp (ref "IC310")
      (value "SK6805-EC15")
      (footprint "eagle-import:SK6805-EC_IPIXEL")
      (fields (field (name "MANUFACTURER") "iPixel") (field (name "VOLTAGE") "5.5 V"))
      (libsource (lib "eagle-import") (part "SK6805-EC15"))
    )
    (comp (ref "IC311")
      (value "SK6805-EC15")
      (footprint "eagle-import:SK6805-EC_IPIXEL")
      (fields (field (name "MANUFACTURER") "iPixel") (field (name "VOLTAGE") "5.5 V"))
      (libsource (lib "eagle-import") (part "SK6805-EC15"))
    )
    (comp (ref "IC312")
      (value "SK6805-EC15")
      (footprint "eagle-import:SK6805-EC_IPIXEL")
      (fields (field (name "MANUFACTURER") "iPixel") (field (name "VOLTAGE") "5.5 V"))
      (libsource (lib "eagle-import") (part "SK6805-EC15"))
    )
    (comp (ref "IC313")
      (value "SK6805-EC15")
      (footprint "eagle-import:SK6805-EC_IPIXEL")
      (fields (field (name "MANUFACTURER") "iPixel") (field (name "VOLTAGE") "5.5 V"))
      (libsource (lib "eagle-import") (part "SK6805-EC15"))
    )
    (comp (ref "IC314")
      (value "SK6805-EC15")
      (footprint "eagle-import:SK6805-EC_IPIXEL")
      (fields (field (name "MANUFACTURER") "iPixel") (field (name "VOLTAGE") "5.5 V"))
      (libsource (lib "eagle-import") (part "SK6805-EC15"))
    )
    (comp (ref "IC315")
      (value "SK6805-EC15")
      (footprint "eagle-import:SK6805-EC_IPIXEL")
      (fields (field (name "MANUFACTURER") "iPixel") (field (name "VOLTAGE") "5.5 V"))
      (libsource (lib "eagle-import") (part "SK6805-EC15"))
    )
    (comp (ref "IC316")
      (value "SK6805-EC15")
      (footprint "eagle-import:SK6805-EC_IPIXEL")
      (fields (field (name "MANUFACTURER") "iPixel") (field (name "VOLTAGE") "5.5 V"))
      (libsource (lib "eagle-import") (part "SK6805-EC15"))
    )
    (comp (ref "IC317")
      (value "SK6805-EC15")
      (footprint "eagle-import:SK6805-EC_IPIXEL")
      (fields (field (name "MANUFACTURER") "iPixel") (field (name "VOLTAGE") "5.5 V"))
      (libsource (lib "eagle-import") (part "SK6805-EC15"))
    )
    (comp (ref "IC318")
      (value "SK6805-EC15")
      (footprint "eagle-import:SK6805-EC_IPIXEL")
      (fields (field (name "MANUFACTURER") "iPixel") (field (name "VOLTAGE") "5.5 V"))
      (libsource (lib "eagle-import") (part "SK6805-EC15"))
    )
    (comp (ref "IC319")
      (value "SK6805-EC15")
      (footprint "eagle-import:SK6805-EC_IPIXEL")
      (fields (field (name "MANUFACTURER") "iPixel") (field (name "VOLTAGE") "5.5 V"))
      (libsource (lib "eagle-import") (part "SK6805-EC15"))
    )
    (comp (ref "IC320")
      (value "SK6805-EC15")
      (footprint "eagle-import:SK6805-EC_IPIXEL")
      (fields (field (name "MANUFACTURER") "iPixel") (field (name "VOLTAGE") "5.5 V"))
      (libsource (lib "eagle-import") (part "SK6805-EC15"))
    )
    (comp (ref "IC321")
      (value "SK6805-EC15")
      (footprint "eagle-import:SK6805-EC_IPIXEL")
      (fields (field (name "MANUFACTURER") "iPixel") (field (name "VOLTAGE") "5.5 V"))
      (libsource (lib "eagle-import") (part "SK6805-EC15"))
    )
    (comp (ref "IC322")
      (value "SK6805-EC15")
      (footprint "eagle-import:SK6805-EC_IPIXEL")
      (fields (field (name "MANUFACTURER") "iPixel") (field (name "VOLTAGE") "5.5 V"))
      (libsource (lib "eagle-import") (part "SK6805-EC15"))
    )
    (comp (ref "IC323")
      (value "SK6805-EC15")
      (footprint "eagle-import:SK6805-EC_IPIXEL")
      (fields (field (name "MANUFACTURER") "iPixel") (field (name "VOLTAGE") "5.5 V"))
      (libsource (lib "eagle-import") (part "SK6805-EC15"))
    )
    (comp (ref "IC324")
      (value "SK6805-EC15")
      (footprint "eagle-import:SK6805-EC_IPIXEL")
      (fields (field (name "MANUFACTURER") "iPixel") (field (name "VOLTAGE") "5.5 V"))
      (libsource (lib "eagle-import") (part "SK6805-EC15"))
    )
    (comp (ref "IC325")
      (value "SK6805-EC15")
      (footprint "eagle-import:SK6805-EC_IPIXEL")
      (fields (field (name "MANUFACTURER") "iPixel") (field (name "VOLTAGE") "5.5 V"))
      (libsource (lib "eagle-import") (part "SK6805-EC15"))
    )
    (comp (ref "IC326")
      (value "SK6805-EC15")
      (footprint "eagle-import:SK6805-EC_IPIXEL")
      (fields (field (name "MANUFACTURER") "iPixel") (field (name "VOLTAGE") "5.5 V"))
      (libsource (lib "eagle-import") (part "SK6805-EC15"))
    )
    (comp (ref "IC327")
      (value "SK6805-EC15")
      (footprint "eagle-import:SK6805-EC_IPIXEL")
      (fields (field (name "MANUFACTURER") "iPixel") (field (name "VOLTAGE") "5.5 V"))
      (libsource (lib "eagle-import") (part "SK6805-EC15"))
    )
    (comp (ref "IC328")
      (value "SK6805-EC15")
      (footprint "eagle-import:SK6805-EC_IPIXEL")
      (fields (field (name "MANUFACTURER") "iPixel") (field (name "VOLTAGE") "5.5 V"))
      (libsource (lib "eagle-import") (part "SK6805-EC15"))
    )
    (comp (ref "IC329")
      (value "SK6805-EC15")
      (footprint "eagle-import:SK6805-EC_IPIXEL")
      (fields (field (name "MANUFACTURER") "iPixel") (field (name "VOLTAGE") "5.5 V"))
      (libsource (lib "eagle-import") (part "SK6805-EC15"))
    )
    (comp (ref "IC330")
      (value "SK6805-EC15")
      (footprint "eagle-import:SK6805-EC_IPIXEL")
      (fields (field (name "MANUFACTURER") "iPixel") (field (name "VOLTAGE") "5.5 V"))
      (libsource (lib "eagle-import") (part "SK6805-EC15"))
    )
    (comp (ref "IC331")
      (value "SK6805-EC15")
      (footprint "eagle-import:SK6805-EC_IPIXEL")
      (fields (field (name "MANUFACTURER") "iPixel") (field (name "VOLTAGE") "5.5 V"))
      (libsource (lib "eagle-import") (part "SK6805-EC15"))
    )
    (comp (ref "IC332")
      (value "SK6805-EC15")
      (footprint "eagle-import:SK6805-EC_IPIXEL")
      (fields (field (name "MANUFACTURER") "iPixel") (field (name "VOLTAGE") "5.5 V"))
      (libsource (lib "eagle-import") (part "SK6805-EC15"))
    )
    (comp (ref "L9")
      (value "74279269")
      (footprint "eagle-import:FERRIT_0603_WIDE_BAND_WUERTH")
      (fields (field (name "MANUFACTURER") "Wuerth"))
      (libsource (lib "eagle-import") (part "74279269"))
    )
    (comp (ref "PS1")
      (value "PASSERMARKE")
      (footprint "eagle-import:PASSERMARKE")
      (libsource (lib "eagle-import") (part "PASSERMARKE"))
    )
    (comp (ref "PS2")
      (value "PASSERMARKE")
      (footprint "eagle-import:PASSERMARKE")
      (libsource (lib "eagle-import") (part "PASSERMARKE"))
    )
    (comp (ref "PS3")
      (value "PASSERMARKE")
      (footprint "eagle-import:PASSERMARKE")
      (libsource (lib "eagle-import") (part "PASSERMARKE"))
    )
    (comp (ref "PS4")
      (value "PASSERMARKE")
      (footprint "eagle-import:PASSERMARKE")
      (libsource (lib "eagle-import") (part "PASSERMARKE"))
    )
    (comp (ref "PS5")
      (value "PASSERMARKE")
      (footprint "eagle-import:PASSERMARKE")
      (libsource (lib "eagle-import") (part "PASSERMARKE"))
    )
    (comp (ref "PS6")
      (value "PASSERMARKE")
      (footprint "eagle-import:PASSERMARKE")
      (libsource (lib "eagle-import") (part "PASSERMARKE"))
    )
    (comp (ref "R1")
      (value "0R")
      (footprint "eagle-import:R0603")
      (fields
        (field (name "MANUFACTURER") "free choice")
        (field (name "POWER") "63 mW")
        (field (name "VOLTAGE") "50.0 V")
      )
      (libsource (lib "eagle-import") (part "R-EU-R0603-0R"))
    )
    (comp (ref "R2")
      (value "10k")
      (footprint "eagle-import:R0603")
      (fields
        (field (name "MANUFACTURER") "free choice")
        (field (name "POWER") "63 mW")
        (field (name "TOLERANCE") "±1 %")
      )
      (libsource (lib "eagle-import") (part "R-EU-R0603-10K"))
    )
    (comp (ref "R3")
      (value "56k")
      (footprint "eagle-import:R0603")
      (fields
        (field (name "MANUFACTURER") "free choice")
        (field (name "POWER") "63 mW")
        (field (name "TOLERANCE") "±1 %")
      )
      (libsource (lib "eagle-import") (part "R-EU-R0603-56K"))
    )
    (comp (ref "R4")
      (value "56k")
      (footprint "eagle-import:R0603")
      (fields
        (field (name "MANUFACTURER") "free choice")
        (field (name "POWER") "63 mW")
        (field (name "TOLERANCE") "±1 %")
      )
      (libsource (lib "eagle-import") (part "R-EU-R0603-56K"))
    )
    (comp (ref "R5")
      (value "56k")
      (footprint "eagle-import:R0603")
      (fields
        (field (name "MANUFACTURER") "free choice")
        (field (name "POWER") "63 mW")
        (field (name "TOLERANCE") "±1 %")
      )
      (libsource (lib "eagle-import") (part "R-EU-R0603-56K"))
    )
    (comp (ref "R6")
      (value "56k")
      (footprint "eagle-import:R0603")
      (fields
        (field (name "MANUFACTURER") "free choice")
        (field (name "POWER") "63 mW")
        (field (name "TOLERANCE") "±1 %")
      )
      (libsource (lib "eagle-import") (part "R-EU-R0603-56K"))
    )
    (comp (ref "R7")
      (value "15R 0W75")
      (footprint "eagle-import:R1210")
      (fields
        (field (name "MANUFACTURER") "Vishay")
        (field (name "POWER") "750 mW")
        (field (name "TOLERANCE") "±1 %")
      )
      (libsource (lib "eagle-import") (part "R-EU-R1210-CRCW121015R0FKEAHP"))
    )
    (comp (ref "R8")
      (value "3R9 0W75")
      (footprint "eagle-import:R1210")
      (fields
        (field (name "MANUFACTURER") "Vishay")
        (field (name "POWER") "750 mW")
        (field (name "TOLERANCE") "±1 %")
      )
      (libsource (lib "eagle-import") (part "R-EU-R1210-CRCW12103R90FKEAHP"))
    )
    (comp (ref "R9")
      (value "0R")
      (footprint "eagle-import:R0603")
      (fields
        (field (name "MANUFACTURER") "free choice")
        (field (name "POWER") "63 mW")
        (field (name "VOLTAGE") "50.0 V")
      )
      (libsource (lib "eagle-import") (part "R-EU-R0603-0R"))
    )
    (comp (ref "R10")
      (value "56k")
      (footprint "eagle-import:R0603")
      (fields
        (field (name "MANUFACTURER") "free choice")
        (field (name "POWER") "63 mW")
        (field (name "TOLERANCE") "±1 %")
      )
      (libsource (lib "eagle-import") (part "R-EU-R0603-56K"))
    )
    (comp (ref "R11")
      (value "56k")
      (footprint "eagle-import:R0603")
      (fields
        (field (name "MANUFACTURER") "free choice")
        (field (name "POWER") "63 mW")
        (field (name "TOLERANCE") "±1 %")
      )
      (libsource (lib "eagle-import") (part "R-EU-R0603-56K"))
    )
    (comp (ref "R12")
      (value "56k")
      (footprint "eagle-import:R0603")
      (fields
        (field (name "MANUFACTURER") "free choice")
        (field (name "POWER") "63 mW")
        (field (name "TOLERANCE") "±1 %")
      )
      (libsource (lib "eagle-import") (part "R-EU-R0603-56K"))
    )
    (comp (ref "R13")
      (value "56k")
      (footprint "eagle-import:R0603")
      (fields
        (field (name "MANUFACTURER") "free choice")
        (field (name "POWER") "63 mW")
        (field (name "TOLERANCE") "±1 %")
      )
      (libsource (lib "eagle-import") (part "R-EU-R0603-56K"))
    )
    (comp (ref "R15")
      (value "3R9 0W75")
      (footprint "eagle-import:R1210")
      (fields
        (field (name "MANUFACTURER") "Vishay")
        (field (name "POWER") "750 mW")
        (field (name "TOLERANCE") "±1 %")
      )
      (libsource (lib "eagle-import") (part "R-EU-R1210-CRCW12103R90FKEAHP"))
    )
    (comp (ref "R16")
      (value "0R")
      (footprint "eagle-import:R0603")
      (fields
        (field (name "MANUFACTURER") "free choice")
        (field (name "POWER") "63 mW")
        (field (name "VOLTAGE") "50.0 V")
      )
      (libsource (lib "eagle-import") (part "R-EU-R0603-0R"))
    )
    (comp (ref "R17")
      (value "91k")
      (footprint "eagle-import:R0603")
      (fields
        (field (name "MANUFACTURER") "free choice")
        (field (name "POWER") "63 mW")
        (field (name "TOLERANCE") "±1 %")
      )
      (libsource (lib "eagle-import") (part "R-EU-R0603-91K"))
    )
    (comp (ref "R18")
      (value "27k")
      (footprint "eagle-import:R0603")
      (fields
        (field (name "MANUFACTURER") "free choice")
        (field (name "POWER") "63 mW")
        (field (name "TOLERANCE") "±1 %")
      )
      (libsource (lib "eagle-import") (part "R-EU-R0603-27K"))
    )
    (comp (ref "R19")
      (value "0R")
      (footprint "eagle-import:R0603")
      (fields
        (field (name "MANUFACTURER") "free choice")
        (field (name "POWER") "63 mW")
        (field (name "VOLTAGE") "50.0 V")
      )
      (libsource (lib "eagle-import") (part "R-EU-R0603-0R"))
    )
    (comp (ref "R20")
      (value "3R9 0W75")
      (footprint "eagle-import:R1210")
      (fields
        (field (name "MANUFACTURER") "Vishay")
        (field (name "POWER") "750 mW")
        (field (name "TOLERANCE") "±1 %")
      )
      (libsource (lib "eagle-import") (part "R-EU-R1210-CRCW12103R90FKEAHP"))
    )
    (comp (ref "R21")
      (value "27R")
      (footprint "eagle-import:R0603")
      (fields
        (field (name "MANUFACTURER") "free choice")
        (field (name "POWER") "63 mW")
        (field (name "TOLERANCE") "±1 %")
      )
      (libsource (lib "eagle-import") (part "R-EU-R0603-27R"))
    )
    (comp (ref "R22")
      (value "3R9 0W75")
      (footprint "eagle-import:R1210")
      (fields
        (field (name "MANUFACTURER") "Vishay")
        (field (name "POWER") "750 mW")
        (field (name "TOLERANCE") "±1 %")
      )
      (libsource (lib "eagle-import") (part "R-EU-R1210-CRCW12103R90FKEAHP"))
    )
    (comp (ref "R23")
      (value "27R")
      (footprint "eagle-import:R0603")
      (fields
        (field (name "MANUFACTURER") "free choice")
        (field (name "POWER") "63 mW")
        (field (name "TOLERANCE") "±1 %")
      )
      (libsource (lib "eagle-import") (part "R-EU-R0603-27R"))
    )
    (comp (ref "R24")
      (value "27R")
      (footprint "eagle-import:R0603")
      (fields
        (field (name "MANUFACTURER") "free choice")
        (field (name "POWER") "63 mW")
        (field (name "TOLERANCE") "±1 %")
      )
      (libsource (lib "eagle-import") (part "R-EU-R0603-27R"))
    )
    (comp (ref "R25")
      (value "3R9 0W75")
      (footprint "eagle-import:R1210")
      (fields
        (field (name "MANUFACTURER") "Vishay")
        (field (name "POWER") "750 mW")
        (field (name "TOLERANCE") "±1 %")
      )
      (libsource (lib "eagle-import") (part "R-EU-R1210-CRCW12103R90FKEAHP"))
    )
    (comp (ref "R26")
      (value "0R")
      (footprint "eagle-import:R0603")
      (fields
        (field (name "MANUFACTURER") "free choice")
        (field (name "POWER") "63 mW")
        (field (name "VOLTAGE") "50.0 V")
      )
      (libsource (lib "eagle-import") (part "R-EU-R0603-0R"))
    )
    (comp (ref "R27")
      (value "0R")
      (footprint "eagle-import:R0603")
      (fields
        (field (name "MANUFACTURER") "free choice")
        (field (name "POWER") "63 mW")
        (field (name "VOLTAGE") "50.0 V")
      )
      (libsource (lib "eagle-import") (part "R-EU-R0603-0R"))
    )
    (comp (ref "R28")
      (value "0R")
      (footprint "eagle-import:R0603")
      (fields
        (field (name "MANUFACTURER") "free choice")
        (field (name "POWER") "63 mW")
        (field (name "VOLTAGE") "50.0 V")
      )
      (libsource (lib "eagle-import") (part "R-EU-R0603-0R"))
    )
    (comp (ref "R29")
      (value "3R9 0W75")
      (footprint "eagle-import:R1210")
      (fields
        (field (name "MANUFACTURER") "Vishay")
        (field (name "POWER") "750 mW")
        (field (name "TOLERANCE") "±1 %")
      )
      (libsource (lib "eagle-import") (part "R-EU-R1210-CRCW12103R90FKEAHP"))
    )
    (comp (ref "R30")
      (value "27R")
      (footprint "eagle-import:R0603")
      (fields
        (field (name "MANUFACTURER") "free choice")
        (field (name "POWER") "63 mW")
        (field (name "TOLERANCE") "±1 %")
      )
      (libsource (lib "eagle-import") (part "R-EU-R0603-27R"))
    )
    (comp (ref "R31")
      (value "10k")
      (footprint "eagle-import:R0603")
      (fields
        (field (name "MANUFACTURER") "free choice")
        (field (name "POWER") "63 mW")
        (field (name "TOLERANCE") "±1 %")
      )
      (libsource (lib "eagle-import") (part "R-EU-R0603-10K"))
    )
    (comp (ref "R32")
      (value "27R")
      (footprint "eagle-import:R0603")
      (fields
        (field (name "MANUFACTURER") "free choice")
        (field (name "POWER") "63 mW")
        (field (name "TOLERANCE") "±1 %")
      )
      (libsource (lib "eagle-import") (part "R-EU-R0603-27R"))
    )
    (comp (ref "R33")
      (value "27R")
      (footprint "eagle-import:R0603")
      (fields
        (field (name "MANUFACTURER") "free choice")
        (field (name "POWER") "63 mW")
        (field (name "TOLERANCE") "±1 %")
      )
      (libsource (lib "eagle-import") (part "R-EU-R0603-27R"))
    )
    (comp (ref "R34")
      (value "3R9 0W75")
      (footprint "eagle-import:R1210")
      (fields
        (field (name "MANUFACTURER") "Vishay")
        (field (name "POWER") "750 mW")
        (field (name "TOLERANCE") "±1 %")
      )
      (libsource (lib "eagle-import") (part "R-EU-R1210-CRCW12103R90FKEAHP"))
    )
    (comp (ref "R35")
      (value "3R9 0W75")
      (footprint "eagle-import:R1210")
      (fields
        (field (name "MANUFACTURER") "Vishay")
        (field (name "POWER") "750 mW")
        (field (name "TOLERANCE") "±1 %")
      )
      (libsource (lib "eagle-import") (part "R-EU-R1210-CRCW12103R90FKEAHP"))
    )
    (comp (ref "R36")
      (value "10k")
      (footprint "eagle-import:R0603")
      (fields
        (field (name "MANUFACTURER") "free choice")
        (field (name "POWER") "63 mW")
        (field (name "TOLERANCE") "±1 %")
      )
      (libsource (lib "eagle-import") (part "R-EU-R0603-10K"))
    )
    (comp (ref "R37")
      (value "27R")
      (footprint "eagle-import:R0603")
      (fields
        (field (name "MANUFACTURER") "free choice")
        (field (name "POWER") "63 mW")
        (field (name "TOLERANCE") "±1 %")
      )
      (libsource (lib "eagle-import") (part "R-EU-R0603-27R"))
    )
    (comp (ref "R38")
      (value "0R")
      (footprint "eagle-import:R0603")
      (fields
        (field (name "MANUFACTURER") "free choice")
        (field (name "POWER") "63 mW")
        (field (name "VOLTAGE") "50.0 V")
      )
      (libsource (lib "eagle-import") (part "R-EU-R0603-0R"))
    )
    (comp (ref "R39")
      (value "27R")
      (footprint "eagle-import:R0603")
      (fields
        (field (name "MANUFACTURER") "free choice")
        (field (name "POWER") "63 mW")
        (field (name "TOLERANCE") "±1 %")
      )
      (libsource (lib "eagle-import") (part "R-EU-R0603-27R"))
    )
    (comp (ref "R40")
      (value "10k")
      (footprint "eagle-import:R0603")
      (fields
        (field (name "MANUFACTURER") "free choice")
        (field (name "POWER") "63 mW")
        (field (name "TOLERANCE") "±1 %")
      )
      (libsource (lib "eagle-import") (part "R-EU-R0603-10K"))
    )
    (comp (ref "R41")
      (value "56k")
      (footprint "eagle-import:R0603")
      (fields
        (field (name "MANUFACTURER") "free choice")
        (field (name "POWER") "63 mW")
        (field (name "TOLERANCE") "±1 %")
      )
      (libsource (lib "eagle-import") (part "R-EU-R0603-56K"))
    )
    (comp (ref "R42")
      (value "56k")
      (footprint "eagle-import:R0603")
      (fields
        (field (name "MANUFACTURER") "free choice")
        (field (name "POWER") "63 mW")
        (field (name "TOLERANCE") "±1 %")
      )
      (libsource (lib "eagle-import") (part "R-EU-R0603-56K"))
    )
    (comp (ref "R43")
      (value "3R9 0W75")
      (footprint "eagle-import:R1210")
      (fields
        (field (name "MANUFACTURER") "Vishay")
        (field (name "POWER") "750 mW")
        (field (name "TOLERANCE") "±1 %")
      )
      (libsource (lib "eagle-import") (part "R-EU-R1210-CRCW12103R90FKEAHP"))
    )
    (comp (ref "R44")
      (value "0R")
      (footprint "eagle-import:R0603")
      (fields
        (field (name "MANUFACTURER") "free choice")
        (field (name "POWER") "63 mW")
        (field (name "VOLTAGE") "50.0 V")
      )
      (libsource (lib "eagle-import") (part "R-EU-R0603-0R"))
    )
    (comp (ref "R45")
      (value "56k")
      (footprint "eagle-import:R0603")
      (fields
        (field (name "MANUFACTURER") "free choice")
        (field (name "POWER") "63 mW")
        (field (name "TOLERANCE") "±1 %")
      )
      (libsource (lib "eagle-import") (part "R-EU-R0603-56K"))
    )
    (comp (ref "R46")
      (value "3R9 0W75")
      (footprint "eagle-import:R1210")
      (fields
        (field (name "MANUFACTURER") "Vishay")
        (field (name "POWER") "750 mW")
        (field (name "TOLERANCE") "±1 %")
      )
      (libsource (lib "eagle-import") (part "R-EU-R1210-CRCW12103R90FKEAHP"))
    )
    (comp (ref "R47")
      (value "0R")
      (footprint "eagle-import:R0603")
      (fields
        (field (name "MANUFACTURER") "free choice")
        (field (name "POWER") "63 mW")
        (field (name "VOLTAGE") "50.0 V")
      )
      (libsource (lib "eagle-import") (part "R-EU-R0603-0R"))
    )
    (comp (ref "R48")
      (value "56k")
      (footprint "eagle-import:R0603")
      (fields
        (field (name "MANUFACTURER") "free choice")
        (field (name "POWER") "63 mW")
        (field (name "TOLERANCE") "±1 %")
      )
      (libsource (lib "eagle-import") (part "R-EU-R0603-56K"))
    )
    (comp (ref "R49")
      (value "0R")
      (footprint "eagle-import:R0603")
      (fields
        (field (name "MANUFACTURER") "free choice")
        (field (name "POWER") "63 mW")
        (field (name "VOLTAGE") "50.0 V")
      )
      (libsource (lib "eagle-import") (part "R-EU-R0603-0R"))
    )
    (comp (ref "R50")
      (value "27R")
      (footprint "eagle-import:R0603")
      (fields
        (field (name "MANUFACTURER") "free choice")
        (field (name "POWER") "63 mW")
        (field (name "TOLERANCE") "±1 %")
      )
      (libsource (lib "eagle-import") (part "R-EU-R0603-27R"))
    )
    (comp (ref "R51")
      (value "56k")
      (footprint "eagle-import:R0603")
      (fields
        (field (name "MANUFACTURER") "free choice")
        (field (name "POWER") "63 mW")
        (field (name "TOLERANCE") "±1 %")
      )
      (libsource (lib "eagle-import") (part "R-EU-R0603-56K"))
    )
    (comp (ref "R52")
      (value "3R9 0W75")
      (footprint "eagle-import:R1210")
      (fields
        (field (name "MANUFACTURER") "Vishay")
        (field (name "POWER") "750 mW")
        (field (name "TOLERANCE") "±1 %")
      )
      (libsource (lib "eagle-import") (part "R-EU-R1210-CRCW12103R90FKEAHP"))
    )
    (comp (ref "R53")
      (value "R-EU-R0603")
      (footprint "eagle-import:R0603")
      (fields
        (field (name "POWER") "63 mW")
        (field (name "TOLERANCE") "±1 %")
        (field (name "VOLTAGE") "50 V")
      )
      (libsource (lib "eagle-import") (part "R-EU-R0603"))
    )
    (comp (ref "R54")
      (value "27R")
      (footprint "eagle-import:R0603")
      (fields
        (field (name "MANUFACTURER") "free choice")
        (field (name "POWER") "63 mW")
        (field (name "TOLERANCE") "±1 %")
      )
      (libsource (lib "eagle-import") (part "R-EU-R0603-27R"))
    )
    (comp (ref "R55")
      (value "27R")
      (footprint "eagle-import:R0603")
      (fields
        (field (name "MANUFACTURER") "free choice")
        (field (name "POWER") "63 mW")
        (field (name "TOLERANCE") "±1 %")
      )
      (libsource (lib "eagle-import") (part "R-EU-R0603-27R"))
    )
    (comp (ref "R56")
      (value "27R")
      (footprint "eagle-import:R0603")
      (fields
        (field (name "MANUFACTURER") "free choice")
        (field (name "POWER") "63 mW")
        (field (name "TOLERANCE") "±1 %")
      )
      (libsource (lib "eagle-import") (part "R-EU-R0603-27R"))
    )
    (comp (ref "R57")
      (value "3R9 0W75")
      (footprint "eagle-import:R1210")
      (fields
        (field (name "MANUFACTURER") "Vishay")
        (field (name "POWER") "750 mW")
        (field (name "TOLERANCE") "±1 %")
      )
      (libsource (lib "eagle-import") (part "R-EU-R1210-CRCW12103R90FKEAHP"))
    )
    (comp (ref "R58")
      (value "56k")
      (footprint "eagle-import:R0603")
      (fields
        (field (name "MANUFACTURER") "free choice")
        (field (name "POWER") "63 mW")
        (field (name "TOLERANCE") "±1 %")
      )
      (libsource (lib "eagle-import") (part "R-EU-R0603-56K"))
    )
    (comp (ref "R59")
      (value "27R")
      (footprint "eagle-import:R0603")
      (fields
        (field (name "MANUFACTURER") "free choice")
        (field (name "POWER") "63 mW")
        (field (name "TOLERANCE") "±1 %")
      )
      (libsource (lib "eagle-import") (part "R-EU-R0603-27R"))
    )
    (comp (ref "R60")
      (value "56k")
      (footprint "eagle-import:R0603")
      (fields
        (field (name "MANUFACTURER") "free choice")
        (field (name "POWER") "63 mW")
        (field (name "TOLERANCE") "±1 %")
      )
      (libsource (lib "eagle-import") (part "R-EU-R0603-56K"))
    )
    (comp (ref "R61")
      (value "56k")
      (footprint "eagle-import:R0603")
      (fields
        (field (name "MANUFACTURER") "free choice")
        (field (name "POWER") "63 mW")
        (field (name "TOLERANCE") "±1 %")
      )
      (libsource (lib "eagle-import") (part "R-EU-R0603-56K"))
    )
    (comp (ref "R62")
      (value "1k1")
      (footprint "eagle-import:R0603")
      (fields
        (field (name "MANUFACTURER") "free choice")
        (field (name "POWER") "63 mW")
        (field (name "TOLERANCE") "±1 %")
      )
      (libsource (lib "eagle-import") (part "R-EU-R0603-1K1"))
    )
    (comp (ref "R63")
      (value "56k")
      (footprint "eagle-import:R0603")
      (fields
        (field (name "MANUFACTURER") "free choice")
        (field (name "POWER") "63 mW")
        (field (name "TOLERANCE") "±1 %")
      )
      (libsource (lib "eagle-import") (part "R-EU-R0603-56K"))
    )
    (comp (ref "R64")
      (value "56k")
      (footprint "eagle-import:R0603")
      (fields
        (field (name "MANUFACTURER") "free choice")
        (field (name "POWER") "63 mW")
        (field (name "TOLERANCE") "±1 %")
      )
      (libsource (lib "eagle-import") (part "R-EU-R0603-56K"))
    )
    (comp (ref "R65")
      (value "56k")
      (footprint "eagle-import:R0603")
      (fields
        (field (name "MANUFACTURER") "free choice")
        (field (name "POWER") "63 mW")
        (field (name "TOLERANCE") "±1 %")
      )
      (libsource (lib "eagle-import") (part "R-EU-R0603-56K"))
    )
    (comp (ref "R66")
      (value "3R9 0W75")
      (footprint "eagle-import:R1210")
      (fields
        (field (name "MANUFACTURER") "Vishay")
        (field (name "POWER") "750 mW")
        (field (name "TOLERANCE") "±1 %")
      )
      (libsource (lib "eagle-import") (part "R-EU-R1210-CRCW12103R90FKEAHP"))
    )
    (comp (ref "R67")
      (value "10k")
      (footprint "eagle-import:R0603")
      (fields
        (field (name "MANUFACTURER") "free choice")
        (field (name "POWER") "63 mW")
        (field (name "TOLERANCE") "±1 %")
      )
      (libsource (lib "eagle-import") (part "R-EU-R0603-10K"))
    )
    (comp (ref "R68")
      (value "56k")
      (footprint "eagle-import:R0603")
      (fields
        (field (name "MANUFACTURER") "free choice")
        (field (name "POWER") "63 mW")
        (field (name "TOLERANCE") "±1 %")
      )
      (libsource (lib "eagle-import") (part "R-EU-R0603-56K"))
    )
    (comp (ref "R69")
      (value "3R9 0W75")
      (footprint "eagle-import:R1210")
      (fields
        (field (name "MANUFACTURER") "Vishay")
        (field (name "POWER") "750 mW")
        (field (name "TOLERANCE") "±1 %")
      )
      (libsource (lib "eagle-import") (part "R-EU-R1210-CRCW12103R90FKEAHP"))
    )
    (comp (ref "R70")
      (value "R-EU-R0603")
      (footprint "eagle-import:R0603")
      (fields
        (field (name "POWER") "63 mW")
        (field (name "TOLERANCE") "±1 %")
        (field (name "VOLTAGE") "50 V")
      )
      (libsource (lib "eagle-import") (part "R-EU-R0603"))
    )
    (comp (ref "R71")
      (value "R-EU-R0603")
      (footprint "eagle-import:R0603")
      (fields
        (field (name "POWER") "63 mW")
        (field (name "TOLERANCE") "±1 %")
        (field (name "VOLTAGE") "50 V")
      )
      (libsource (lib "eagle-import") (part "R-EU-R0603"))
    )
    (comp (ref "R72")
      (value "0R")
      (footprint "eagle-import:R0603")
      (fields
        (field (name "MANUFACTURER") "free choice")
        (field (name "POWER") "63 mW")
        (field (name "VOLTAGE") "50.0 V")
      )
      (libsource (lib "eagle-import") (part "R-EU-R0603-0R"))
    )
    (comp (ref "R73")
      (value "3R9 0W75")
      (footprint "eagle-import:R1210")
      (fields
        (field (name "MANUFACTURER") "Vishay")
        (field (name "POWER") "750 mW")
        (field (name "TOLERANCE") "±1 %")
      )
      (libsource (lib "eagle-import") (part "R-EU-R1210-CRCW12103R90FKEAHP"))
    )
    (comp (ref "R74")
      (value "0R")
      (footprint "eagle-import:R0603")
      (fields
        (field (name "MANUFACTURER") "free choice")
        (field (name "POWER") "63 mW")
        (field (name "VOLTAGE") "50.0 V")
      )
      (libsource (lib "eagle-import") (part "R-EU-R0603-0R"))
    )
    (comp (ref "R75")
      (value "3R9 0W75")
      (footprint "eagle-import:R1210")
      (fields
        (field (name "MANUFACTURER") "Vishay")
        (field (name "POWER") "750 mW")
        (field (name "TOLERANCE") "±1 %")
      )
      (libsource (lib "eagle-import") (part "R-EU-R1210-CRCW12103R90FKEAHP"))
    )
    (comp (ref "R76")
      (value "0R")
      (footprint "eagle-import:R0603")
      (fields
        (field (name "MANUFACTURER") "free choice")
        (field (name "POWER") "63 mW")
        (field (name "VOLTAGE") "50.0 V")
      )
      (libsource (lib "eagle-import") (part "R-EU-R0603-0R"))
    )
    (comp (ref "R77")
      (value "0R")
      (footprint "eagle-import:R0603")
      (fields
        (field (name "MANUFACTURER") "free choice")
        (field (name "POWER") "63 mW")
        (field (name "VOLTAGE") "50.0 V")
      )
      (libsource (lib "eagle-import") (part "R-EU-R0603-0R"))
    )
    (comp (ref "R78")
      (value "0R")
      (footprint "eagle-import:R0603")
      (fields
        (field (name "MANUFACTURER") "free choice")
        (field (name "POWER") "63 mW")
        (field (name "VOLTAGE") "50.0 V")
      )
      (libsource (lib "eagle-import") (part "R-EU-R0603-0R"))
    )
    (comp (ref "R79")
      (value "0R")
      (footprint "eagle-import:R0603")
      (fields
        (field (name "MANUFACTURER") "free choice")
        (field (name "POWER") "63 mW")
        (field (name "VOLTAGE") "50.0 V")
      )
      (libsource (lib "eagle-import") (part "R-EU-R0603-0R"))
    )
    (comp (ref "R80")
      (value "27R")
      (footprint "eagle-import:R0603")
      (fields
        (field (name "MANUFACTURER") "free choice")
        (field (name "POWER") "63 mW")
        (field (name "TOLERANCE") "±1 %")
      )
      (libsource (lib "eagle-import") (part "R-EU-R0603-27R"))
    )
    (comp (ref "R81")
      (value "27R")
      (footprint "eagle-import:R0603")
      (fields
        (field (name "MANUFACTURER") "free choice")
        (field (name "POWER") "63 mW")
        (field (name "TOLERANCE") "±1 %")
      )
      (libsource (lib "eagle-import") (part "R-EU-R0603-27R"))
    )
    (comp (ref "R82")
      (value "27R")
      (footprint "eagle-import:R0603")
      (fields
        (field (name "MANUFACTURER") "free choice")
        (field (name "POWER") "63 mW")
        (field (name "TOLERANCE") "±1 %")
      )
      (libsource (lib "eagle-import") (part "R-EU-R0603-27R"))
    )
    (comp (ref "R83")
      (value "15R 0W75")
      (footprint "eagle-import:R1210")
      (fields
        (field (name "MANUFACTURER") "Vishay")
        (field (name "POWER") "750 mW")
        (field (name "TOLERANCE") "±1 %")
      )
      (libsource (lib "eagle-import") (part "R-EU-R1210-CRCW121015R0FKEAHP"))
    )
    (comp (ref "R84")
      (value "15R 0W75")
      (footprint "eagle-import:R1210")
      (fields
        (field (name "MANUFACTURER") "Vishay")
        (field (name "POWER") "750 mW")
        (field (name "TOLERANCE") "±1 %")
      )
      (libsource (lib "eagle-import") (part "R-EU-R1210-CRCW121015R0FKEAHP"))
    )
    (comp (ref "R85")
      (value "R-EU-R0603")
      (footprint "eagle-import:R0603")
      (fields
        (field (name "POWER") "63 mW")
        (field (name "TOLERANCE") "±1 %")
        (field (name "VOLTAGE") "50 V")
      )
      (libsource (lib "eagle-import") (part "R-EU-R0603"))
    )
    (comp (ref "R86")
      (value "R-EU-R0603")
      (footprint "eagle-import:R0603")
      (fields
        (field (name "POWER") "63 mW")
        (field (name "TOLERANCE") "±1 %")
        (field (name "VOLTAGE") "50 V")
      )
      (libsource (lib "eagle-import") (part "R-EU-R0603"))
    )
    (comp (ref "R87")
      (value "100R")
      (footprint "eagle-import:R0603")
      (fields
        (field (name "MANUFACTURER") "free choice")
        (field (name "POWER") "63 mW")
        (field (name "TOLERANCE") "±1 %")
      )
      (libsource (lib "eagle-import") (part "R-EU-R0603-100R"))
    )
    (comp (ref "R88")
      (value "R-EU-R0603")
      (footprint "eagle-import:R0603")
      (fields
        (field (name "POWER") "63 mW")
        (field (name "TOLERANCE") "±1 %")
        (field (name "VOLTAGE") "50 V")
      )
      (libsource (lib "eagle-import") (part "R-EU-R0603"))
    )
    (comp (ref "SW1")
      (value "ATE-1C-V")
      (footprint "eagle-import:ATE-1C_DIPTRONICS")
      (fields (field (name "MANUFACTURER") "Diptronics"))
      (libsource (lib "eagle-import") (part "ATE-1C-V"))
    )
    (comp (ref "T2")
      (value "PMV30ENEA")
      (footprint "eagle-import:SOT-23_NXP")
      (fields (field (name "MANUFACTURER") "Nexperia"))
      (libsource (lib "eagle-import") (part "PMV30ENEA"))
    )
    (comp (ref "T3")
      (value "PMV30ENEA")
      (footprint "eagle-import:SOT-23_NXP")
      (fields (field (name "MANUFACTURER") "Nexperia"))
      (libsource (lib "eagle-import") (part "PMV30ENEA"))
    )
    (comp (ref "T6")
      (value "PMV30ENEA")
      (footprint "eagle-import:SOT-23_NXP")
      (fields (field (name "MANUFACTURER") "Nexperia"))
      (libsource (lib "eagle-import") (part "PMV30ENEA"))
    )
    (comp (ref "T7")
      (value "PMV30ENEA")
      (footprint "eagle-import:SOT-23_NXP")
      (fields (field (name "MANUFACTURER") "Nexperia"))
      (libsource (lib "eagle-import") (part "PMV30ENEA"))
    )
    (comp (ref "T8")
      (value "NX7002AK")
      (footprint "eagle-import:SOT-23_NXP")
      (fields (field (name "MANUFACTURER") "Nexperia"))
      (libsource (lib "eagle-import") (part "NX7002AK"))
    )
    (comp (ref "T10")
      (value "PMV30ENEA")
      (footprint "eagle-import:SOT-23_NXP")
      (fields (field (name "MANUFACTURER") "Nexperia"))
      (libsource (lib "eagle-import") (part "PMV30ENEA"))
    )
    (comp (ref "TP1")
      (value "GND")
      (footprint "eagle-import:TESTPAD_ROUND_1.5MM")
      (libsource (lib "eagle-import") (part "TESTPOINT_ROUND_1.5MM"))
    )
    (comp (ref "TP2")
      (value "+PVCC")
      (footprint "eagle-import:TESTPAD_ROUND_1.5MM")
      (libsource (lib "eagle-import") (part "TESTPOINT_ROUND_1.5MM"))
    )
    (comp (ref "TP3")
      (value "TESTPOINT_ROUND_1.5MM")
      (footprint "eagle-import:TESTPAD_ROUND_1.5MM")
      (libsource (lib "eagle-import") (part "TESTPOINT_ROUND_1.5MM"))
    )
    (comp (ref "TP4")
      (value "TESTPOINT_ROUND_1.5MM")
      (footprint "eagle-import:TESTPAD_ROUND_1.5MM")
      (libsource (lib "eagle-import") (part "TESTPOINT_ROUND_1.5MM"))
    )
    (comp (ref "TP5")
      (value "TESTPOINT_ROUND_1.5MM")
      (footprint "eagle-import:TESTPAD_ROUND_1.5MM")
      (libsource (lib "eagle-import") (part "TESTPOINT_ROUND_1.5MM"))
    )
    (comp (ref "TP6")
      (value "TESTPOINT_ROUND_1.5MM")
      (footprint "eagle-import:TESTPAD_ROUND_1.5MM")
      (libsource (lib "eagle-import") (part "TESTPOINT_ROUND_1.5MM"))
    )
    (comp (ref "TP7")
      (value "TESTPOINT_ROUND_1.5MM")
      (footprint "eagle-import:TESTPAD_ROUND_1.5MM")
      (libsource (lib "eagle-import") (part "TESTPOINT_ROUND_1.5MM"))
    )
    (comp (ref "TP8")
      (value "TESTPOINT_ROUND_1.5MM")
      (footprint "eagle-import:TESTPAD_ROUND_1.5MM")
      (libsource (lib "eagle-import") (part "TESTPOINT_ROUND_1.5MM"))
    )
    (comp (ref "TP9")
      (value "TESTPOINT_ROUND_1.5MM")
      (footprint "eagle-import:TESTPAD_ROUND_1.5MM")
      (libsource (lib "eagle-import") (part "TESTPOINT_ROUND_1.5MM"))
    )
    (comp (ref "TP10")
      (value "TESTPOINT_ROUND_1.5MM")
      (footprint "eagle-import:TESTPAD_ROUND_1.5MM")
      (libsource (lib "eagle-import") (part "TESTPOINT_ROUND_1.5MM"))
    )
    (comp (ref "TP11")
      (value "TESTPOINT_ROUND_1.5MM")
      (footprint "eagle-import:TESTPAD_ROUND_1.5MM")
      (libsource (lib "eagle-import") (part "TESTPOINT_ROUND_1.5MM"))
    )
    (comp (ref "TP12")
      (value "TESTPOINT_ROUND_1.5MM")
      (footprint "eagle-import:TESTPAD_ROUND_1.5MM")
      (libsource (lib "eagle-import") (part "TESTPOINT_ROUND_1.5MM"))
    )
    (comp (ref "TP13")
      (value "SAFETY_SHDN_RST")
      (footprint "eagle-import:TESTPAD_ROUND_1.5MM")
      (libsource (lib "eagle-import") (part "TESTPOINT_ROUND_1.5MM"))
    )
    (comp (ref "TP14")
      (value "TESTPOINT_ROUND_1.5MM")
      (footprint "eagle-import:TESTPAD_ROUND_1.5MM")
      (libsource (lib "eagle-import") (part "TESTPOINT_ROUND_1.5MM"))
    )
    (comp (ref "TP15")
      (value "TESTPOINT_ROUND_1.5MM")
      (footprint "eagle-import:TESTPAD_ROUND_1.5MM")
      (libsource (lib "eagle-import") (part "TESTPOINT_ROUND_1.5MM"))
    )
    (comp (ref "TP16")
      (value "TESTPOINT_ROUND_1.5MM")
      (footprint "eagle-import:TESTPAD_ROUND_1.5MM")
      (libsource (lib "eagle-import") (part "TESTPOINT_ROUND_1.5MM"))
    )
    (comp (ref "TP17")
      (value "TESTPOINT_ROUND_1.5MM")
      (footprint "eagle-import:TESTPAD_ROUND_1.5MM")
      (libsource (lib "eagle-import") (part "TESTPOINT_ROUND_1.5MM"))
    )
    (comp (ref "TP18")
      (value "TESTPOINT_ROUND_1.5MM")
      (footprint "eagle-import:TESTPAD_ROUND_1.5MM")
      (libsource (lib "eagle-import") (part "TESTPOINT_ROUND_1.5MM"))
    )
    (comp (ref "TP19")
      (value "TESTPOINT_ROUND_1.5MM")
      (footprint "eagle-import:TESTPAD_ROUND_1.5MM")
      (libsource (lib "eagle-import") (part "TESTPOINT_ROUND_1.5MM"))
    )
    (comp (ref "TP20")
      (value "TESTPOINT_ROUND_1.5MM")
      (footprint "eagle-import:TESTPAD_ROUND_1.5MM")
      (libsource (lib "eagle-import") (part "TESTPOINT_ROUND_1.5MM"))
    )
    (comp (ref "TP21")
      (value "TESTPOINT_ROUND_1.5MM")
      (footprint "eagle-import:TESTPAD_ROUND_1.5MM")
      (libsource (lib "eagle-import") (part "TESTPOINT_ROUND_1.5MM"))
    )
    (comp (ref "TP22")
      (value "TESTPOINT_ROUND_1.5MM")
      (footprint "eagle-import:TESTPAD_ROUND_1.5MM")
      (libsource (lib "eagle-import") (part "TESTPOINT_ROUND_1.5MM"))
    )
    (comp (ref "TP23")
      (value "TESTPOINT_ROUND_1.5MM")
      (footprint "eagle-import:TESTPAD_ROUND_1.5MM")
      (libsource (lib "eagle-import") (part "TESTPOINT_ROUND_1.5MM"))
    )
    (comp (ref "X1")
      (value "MEC6-120-02-L-DV-A")
      (footprint "eagle-import:MEC6-120-02")
      (fields (field (name "MANUFACTURER") "Samtec"))
      (libsource (lib "eagle-import") (part "MEC6-120-02-L-DV-A"))
    )
    (comp (ref "X2")
      (value "MEC6-120-02-L-DV-A")
      (footprint "eagle-import:MEC6-120-02")
      (fields (field (name "MANUFACTURER") "Samtec"))
      (libsource (lib "eagle-import") (part "MEC6-120-02-L-DV-A"))
    )
    (comp (ref "X3")
      (value "DF37NC-30DS-0.4V")
      (footprint "eagle-import:DF37NC-30DS-0.4V")
      (fields (field (name "MANUFACTURER") "Hirose"))
      (libsource (lib "eagle-import") (part "DF37NC-30DS-0.4V"))
    )
    (comp (ref "X4")
      (value "687112182122")
      (footprint "eagle-import:687112182122_WUERTH")
      (fields (field (name "MANUFACTURER") "Wuerth"))
      (libsource (lib "eagle-import") (part "687112182122"))
    )
    (comp (ref "X5")
      (value "AXE530127")
      (footprint "eagle-import:AXE530127_PANASONIC")
      (fields (field (name "MANUFACTURER") "Panasonic") (field (name "VOLTAGE") "60.0 V"))
      (libsource (lib "eagle-import") (part "AXE530127"))
    )
  )
  (nets
    (net (code "1") (name "+1V2") (class "Default")
      (node (ref "C46") (pin "1") (pinfunction "1_1") (pintype "passive"))
      (node (ref "X1") (pin "20") (pinfunction "20_20") (pintype "passive"))
      (node (ref "X3") (pin "27") (pinfunction "27_27") (pintype "bidirectional"))
    )
    (net (code "2") (name "+1V8") (class "Default")
      (node (ref "C37") (pin "1") (pinfunction "1_1") (pintype "passive"))
      (node (ref "C44") (pin "1") (pinfunction "1_1") (pintype "passive"))
      (node (ref "C45") (pin "1") (pinfunction "1_1") (pintype "passive"))
      (node (ref "C49") (pin "1") (pinfunction "1_1") (pintype "passive"))
      (node (ref "IC12") (pin "5") (pinfunction "VBUS_5") (pintype "input"))
      (node (ref "IC16") (pin "5") (pinfunction "VBUS_5") (pintype "input"))
      (node (ref "IC18") (pin "5") (pinfunction "VBUS_5") (pintype "input"))
      (node (ref "R16") (pin "2") (pinfunction "2_2") (pintype "passive"))
      (node (ref "X1") (pin "18") (pinfunction "18_18") (pintype "passive"))
      (node (ref "X3") (pin "28") (pinfunction "28_28") (pintype "bidirectional"))
    )
    (net (code "3") (name "+2V8") (class "Default")
      (node (ref "C47") (pin "1") (pinfunction "1_1") (pintype "passive"))
      (node (ref "C50") (pin "1") (pinfunction "1_1") (pintype "passive"))
      (node (ref "IC19") (pin "5") (pinfunction "VBUS_5") (pintype "input"))
      (node (ref "R88") (pin "2") (pinfunction "2_2") (pintype "passive"))
      (node (ref "X1") (pin "16") (pinfunction "16_16") (pintype "passive"))
      (node (ref "X3") (pin "21") (pinfunction "21_21") (pintype "bidirectional"))
    )
    (net (code "4") (name "+3V3") (class "Default")
      (node (ref "C11") (pin "1") (pinfunction "1_1") (pintype "passive"))
      (node (ref "C15") (pin "1") (pinfunction "1_1") (pintype "passive"))
      (node (ref "C39") (pin "1") (pinfunction "1_1") (pintype "passive"))
      (node (ref "C51") (pin "1") (pinfunction "1_1") (pintype "passive"))
      (node (ref "D1") (pin "A") (pinfunction "A_A") (pintype "passive"))
      (node (ref "D2") (pin "A") (pinfunction "A_A") (pintype "passive"))
      (node (ref "IC14") (pin "5") (pinfunction "VBUS_5") (pintype "input"))
      (node (ref "IC20") (pin "5") (pinfunction "VBUS_5") (pintype "input"))
      (node (ref "L9") (pin "1") (pinfunction "1_1") (pintype "passive"))
      (node (ref "R17") (pin "2") (pinfunction "2_2") (pintype "passive"))
      (node (ref "R19") (pin "1") (pinfunction "1_1") (pintype "passive"))
      (node (ref "R26") (pin "2") (pinfunction "2_2") (pintype "passive"))
      (node (ref "R27") (pin "2") (pinfunction "2_2") (pintype "passive"))
      (node (ref "R28") (pin "2") (pinfunction "2_2") (pintype "passive"))
      (node (ref "R31") (pin "2") (pinfunction "2_2") (pintype "passive"))
      (node (ref "R36") (pin "2") (pinfunction "2_2") (pintype "passive"))
      (node (ref "R40") (pin "2") (pinfunction "2_2") (pintype "passive"))
      (node (ref "R42") (pin "1") (pinfunction "1_1") (pintype "passive"))
      (node (ref "R60") (pin "2") (pinfunction "2_2") (pintype "passive"))
      (node (ref "R63") (pin "1") (pinfunction "1_1") (pintype "passive"))
      (node (ref "R64") (pin "2") (pinfunction "2_2") (pintype "passive"))
      (node (ref "R72") (pin "1") (pinfunction "1_1") (pintype "passive"))
      (node (ref "R74") (pin "2") (pinfunction "2_2") (pintype "passive"))
      (node (ref "R76") (pin "2") (pinfunction "2_2") (pintype "passive"))
      (node (ref "R77") (pin "2") (pinfunction "2_2") (pintype "passive"))
      (node (ref "R79") (pin "2") (pinfunction "2_2") (pintype "passive"))
      (node (ref "R85") (pin "1") (pinfunction "1_1") (pintype "passive"))
      (node (ref "R86") (pin "1") (pinfunction "1_1") (pintype "passive"))
      (node (ref "TP3") (pin "TP") (pinfunction "TP_TP") (pintype "input"))
      (node (ref "X1") (pin "14") (pinfunction "14_14") (pintype "passive"))
    )
    (net (code "5") (name "+3V6") (class "Default")
      (node (ref "C54") (pin "1") (pinfunction "1_1") (pintype "passive"))
      (node (ref "C55") (pin "1") (pinfunction "1_1") (pintype "passive"))
      (node (ref "C56") (pin "1") (pinfunction "1_1") (pintype "passive"))
      (node (ref "X1") (pin "22") (pinfunction "22_22") (pintype "passive"))
      (node (ref "X5") (pin "1") (pinfunction "1_1") (pintype "passive"))
      (node (ref "X5") (pin "2") (pinfunction "2_2") (pintype "passive"))
      (node (ref "X5") (pin "3") (pinfunction "3_3") (pintype "passive"))
      (node (ref "X5") (pin "4") (pinfunction "4_4") (pintype "passive"))
      (node (ref "X5") (pin "6") (pinfunction "6_6") (pintype "passive"))
      (node (ref "X5") (pin "8") (pinfunction "8_8") (pintype "passive"))
    )
    (net (code "6") (name "+5V") (class "Default")
      (node (ref "C100") (pin "1") (pinfunction "1_1") (pintype "passive"))
      (node (ref "C101") (pin "1") (pinfunction "1_1") (pintype "passive"))
      (node (ref "C102") (pin "1") (pinfunction "1_1") (pintype "passive"))
      (node (ref "C103") (pin "1") (pinfunction "1_1") (pintype "passive"))
      (node (ref "C104") (pin "1") (pinfunction "1_1") (pintype "passive"))
      (node (ref "C105") (pin "1") (pinfunction "1_1") (pintype "passive"))
      (node (ref "C106") (pin "1") (pinfunction "1_1") (pintype "passive"))
      (node (ref "C107") (pin "1") (pinfunction "1_1") (pintype "passive"))
      (node (ref "C108") (pin "1") (pinfunction "1_1") (pintype "passive"))
      (node (ref "C109") (pin "1") (pinfunction "1_1") (pintype "passive"))
      (node (ref "C110") (pin "1") (pinfunction "1_1") (pintype "passive"))
      (node (ref "C111") (pin "1") (pinfunction "1_1") (pintype "passive"))
      (node (ref "C112") (pin "1") (pinfunction "1_1") (pintype "passive"))
      (node (ref "C113") (pin "1") (pinfunction "1_1") (pintype "passive"))
      (node (ref "C114") (pin "1") (pinfunction "1_1") (pintype "passive"))
      (node (ref "C115") (pin "1") (pinfunction "1_1") (pintype "passive"))
      (node (ref "C116") (pin "1") (pinfunction "1_1") (pintype "passive"))
      (node (ref "C117") (pin "1") (pinfunction "1_1") (pintype "passive"))
      (node (ref "C118") (pin "1") (pinfunction "1_1") (pintype "passive"))
      (node (ref "C119") (pin "1") (pinfunction "1_1") (pintype "passive"))
      (node (ref "C120") (pin "1") (pinfunction "1_1") (pintype "passive"))
      (node (ref "C121") (pin "1") (pinfunction "1_1") (pintype "passive"))
      (node (ref "C122") (pin "1") (pinfunction "1_1") (pintype "passive"))
      (node (ref "C123") (pin "1") (pinfunction "1_1") (pintype "passive"))
      (node (ref "C124") (pin "1") (pinfunction "1_1") (pintype "passive"))
      (node (ref "C125") (pin "1") (pinfunction "1_1") (pintype "passive"))
      (node (ref "C126") (pin "1") (pinfunction "1_1") (pintype "passive"))
      (node (ref "C127") (pin "1") (pinfunction "1_1") (pintype "passive"))
      (node (ref "C128") (pin "1") (pinfunction "1_1") (pintype "passive"))
      (node (ref "C129") (pin "1") (pinfunction "1_1") (pintype "passive"))
      (node (ref "C130") (pin "1") (pinfunction "1_1") (pintype "passive"))
      (node (ref "C131") (pin "1") (pinfunction "1_1") (pintype "passive"))
      (node (ref "C132") (pin "1") (pinfunction "1_1") (pintype "passive"))
      (node (ref "C133") (pin "1") (pinfunction "1_1") (pintype "passive"))
      (node (ref "C134") (pin "1") (pinfunction "1_1") (pintype "passive"))
      (node (ref "C135") (pin "1") (pinfunction "1_1") (pintype "passive"))
      (node (ref "C136") (pin "1") (pinfunction "1_1") (pintype "passive"))
      (node (ref "C137") (pin "1") (pinfunction "1_1") (pintype "passive"))
      (node (ref "C138") (pin "1") (pinfunction "1_1") (pintype "passive"))
      (node (ref "C139") (pin "1") (pinfunction "1_1") (pintype "passive"))
      (node (ref "C140") (pin "1") (pinfunction "1_1") (pintype "passive"))
      (node (ref "C141") (pin "1") (pinfunction "1_1") (pintype "passive"))
      (node (ref "C142") (pin "1") (pinfunction "1_1") (pintype "passive"))
      (node (ref "C143") (pin "1") (pinfunction "1_1") (pintype "passive"))
      (node (ref "C144") (pin "1") (pinfunction "1_1") (pintype "passive"))
      (node (ref "C145") (pin "1") (pinfunction "1_1") (pintype "passive"))
      (node (ref "C146") (pin "1") (pinfunction "1_1") (pintype "passive"))
      (node (ref "C147") (pin "1") (pinfunction "1_1") (pintype "passive"))
      (node (ref "C148") (pin "1") (pinfunction "1_1") (pintype "passive"))
      (node (ref "C149") (pin "1") (pinfunction "1_1") (pintype "passive"))
      (node (ref "C150") (pin "1") (pinfunction "1_1") (pintype "passive"))
      (node (ref "C151") (pin "1") (pinfunction "1_1") (pintype "passive"))
      (node (ref "C152") (pin "1") (pinfunction "1_1") (pintype "passive"))
      (node (ref "C153") (pin "1") (pinfunction "1_1") (pintype "passive"))
      (node (ref "C154") (pin "1") (pinfunction "1_1") (pintype "passive"))
      (node (ref "C155") (pin "1") (pinfunction "1_1") (pintype "passive"))
      (node (ref "C156") (pin "1") (pinfunction "1_1") (pintype "passive"))
      (node (ref "C157") (pin "1") (pinfunction "1_1") (pintype "passive"))
      (node (ref "C158") (pin "1") (pinfunction "1_1") (pintype "passive"))
      (node (ref "C159") (pin "1") (pinfunction "1_1") (pintype "passive"))
      (node (ref "C162") (pin "1") (pinfunction "1_1") (pintype "passive"))
      (node (ref "C164") (pin "1") (pinfunction "1_1") (pintype "passive"))
      (node (ref "C165") (pin "1") (pinfunction "1_1") (pintype "passive"))
      (node (ref "C166") (pin "1") (pinfunction "1_1") (pintype "passive"))
      (node (ref "C167") (pin "1") (pinfunction "1_1") (pintype "passive"))
      (node (ref "C168") (pin "1") (pinfunction "1_1") (pintype "passive"))
      (node (ref "C169") (pin "1") (pinfunction "1_1") (pintype "passive"))
      (node (ref "C170") (pin "1") (pinfunction "1_1") (pintype "passive"))
      (node (ref "C171") (pin "1") (pinfunction "1_1") (pintype "passive"))
      (node (ref "C172") (pin "1") (pinfunction "1_1") (pintype "passive"))
      (node (ref "C173") (pin "1") (pinfunction "1_1") (pintype "passive"))
      (node (ref "C174") (pin "1") (pinfunction "1_1") (pintype "passive"))
      (node (ref "C175") (pin "1") (pinfunction "1_1") (pintype "passive"))
      (node (ref "C176") (pin "1") (pinfunction "1_1") (pintype "passive"))
      (node (ref "C177") (pin "1") (pinfunction "1_1") (pintype "passive"))
      (node (ref "C178") (pin "1") (pinfunction "1_1") (pintype "passive"))
      (node (ref "C179") (pin "1") (pinfunction "1_1") (pintype "passive"))
      (node (ref "C180") (pin "1") (pinfunction "1_1") (pintype "passive"))
      (node (ref "C181") (pin "1") (pinfunction "1_1") (pintype "passive"))
      (node (ref "C182") (pin "1") (pinfunction "1_1") (pintype "passive"))
      (node (ref "C183") (pin "1") (pinfunction "1_1") (pintype "passive"))
      (node (ref "C184") (pin "1") (pinfunction "1_1") (pintype "passive"))
      (node (ref "C185") (pin "1") (pinfunction "1_1") (pintype "passive"))
      (node (ref "C186") (pin "1") (pinfunction "1_1") (pintype "passive"))
      (node (ref "C187") (pin "1") (pinfunction "1_1") (pintype "passive"))
      (node (ref "C188") (pin "1") (pinfunction "1_1") (pintype "passive"))
      (node (ref "C189") (pin "1") (pinfunction "1_1") (pintype "passive"))
      (node (ref "C190") (pin "1") (pinfunction "1_1") (pintype "passive"))
      (node (ref "C191") (pin "1") (pinfunction "1_1") (pintype "passive"))
      (node (ref "C192") (pin "1") (pinfunction "1_1") (pintype "passive"))
      (node (ref "C193") (pin "1") (pinfunction "1_1") (pintype "passive"))
      (node (ref "C194") (pin "1") (pinfunction "1_1") (pintype "passive"))
      (node (ref "C195") (pin "1") (pinfunction "1_1") (pintype "passive"))
      (node (ref "C196") (pin "1") (pinfunction "1_1") (pintype "passive"))
      (node (ref "C197") (pin "1") (pinfunction "1_1") (pintype "passive"))
      (node (ref "C198") (pin "1") (pinfunction "1_1") (pintype "passive"))
      (node (ref "C199") (pin "1") (pinfunction "1_1") (pintype "passive"))
      (node (ref "C200") (pin "1") (pinfunction "1_1") (pintype "passive"))
      (node (ref "C201") (pin "1") (pinfunction "1_1") (pintype "passive"))
      (node (ref "C202") (pin "1") (pinfunction "1_1") (pintype "passive"))
      (node (ref "C203") (pin "1") (pinfunction "1_1") (pintype "passive"))
      (node (ref "C204") (pin "1") (pinfunction "1_1") (pintype "passive"))
      (node (ref "C205") (pin "1") (pinfunction "1_1") (pintype "passive"))
      (node (ref "C206") (pin "1") (pinfunction "1_1") (pintype "passive"))
      (node (ref "C207") (pin "1") (pinfunction "1_1") (pintype "passive"))
      (node (ref "C208") (pin "1") (pinfunction "1_1") (pintype "passive"))
      (node (ref "C209") (pin "1") (pinfunction "1_1") (pintype "passive"))
      (node (ref "C210") (pin "1") (pinfunction "1_1") (pintype "passive"))
      (node (ref "C211") (pin "1") (pinfunction "1_1") (pintype "passive"))
      (node (ref "C212") (pin "1") (pinfunction "1_1") (pintype "passive"))
      (node (ref "C213") (pin "1") (pinfunction "1_1") (pintype "passive"))
      (node (ref "C214") (pin "1") (pinfunction "1_1") (pintype "passive"))
      (node (ref "C215") (pin "1") (pinfunction "1_1") (pintype "passive"))
      (node (ref "C216") (pin "1") (pinfunction "1_1") (pintype "passive"))
      (node (ref "C217") (pin "1") (pinfunction "1_1") (pintype "passive"))
      (node (ref "C218") (pin "1") (pinfunction "1_1") (pintype "passive"))
      (node (ref "C219") (pin "1") (pinfunction "1_1") (pintype "passive"))
      (node (ref "C220") (pin "1") (pinfunction "1_1") (pintype "passive"))
      (node (ref "C221") (pin "1") (pinfunction "1_1") (pintype "passive"))
      (node (ref "C222") (pin "1") (pinfunction "1_1") (pintype "passive"))
      (node (ref "C223") (pin "1") (pinfunction "1_1") (pintype "passive"))
      (node (ref "C224") (pin "1") (pinfunction "1_1") (pintype "passive"))
      (node (ref "C225") (pin "1") (pinfunction "1_1") (pintype "passive"))
      (node (ref "C226") (pin "1") (pinfunction "1_1") (pintype "passive"))
      (node (ref "C227") (pin "1") (pinfunction "1_1") (pintype "passive"))
      (node (ref "C228") (pin "1") (pinfunction "1_1") (pintype "passive"))
      (node (ref "C229") (pin "1") (pinfunction "1_1") (pintype "passive"))
      (node (ref "C230") (pin "1") (pinfunction "1_1") (pintype "passive"))
      (node (ref "C231") (pin "1") (pinfunction "1_1") (pintype "passive"))
      (node (ref "C232") (pin "1") (pinfunction "1_1") (pintype "passive"))
      (node (ref "C233") (pin "1") (pinfunction "1_1") (pintype "passive"))
      (node (ref "C234") (pin "1") (pinfunction "1_1") (pintype "passive"))
      (node (ref "C235") (pin "1") (pinfunction "1_1") (pintype "passive"))
      (node (ref "C236") (pin "1") (pinfunction "1_1") (pintype "passive"))
      (node (ref "C237") (pin "1") (pinfunction "1_1") (pintype "passive"))
      (node (ref "C238") (pin "1") (pinfunction "1_1") (pintype "passive"))
      (node (ref "C239") (pin "1") (pinfunction "1_1") (pintype "passive"))
      (node (ref "C240") (pin "1") (pinfunction "1_1") (pintype "passive"))
      (node (ref "C241") (pin "1") (pinfunction "1_1") (pintype "passive"))
      (node (ref "C242") (pin "1") (pinfunction "1_1") (pintype "passive"))
      (node (ref "C243") (pin "1") (pinfunction "1_1") (pintype "passive"))
      (node (ref "C244") (pin "1") (pinfunction "1_1") (pintype "passive"))
      (node (ref "C245") (pin "1") (pinfunction "1_1") (pintype "passive"))
      (node (ref "C246") (pin "1") (pinfunction "1_1") (pintype "passive"))
      (node (ref "C247") (pin "1") (pinfunction "1_1") (pintype "passive"))
      (node (ref "C248") (pin "1") (pinfunction "1_1") (pintype "passive"))
      (node (ref "C249") (pin "1") (pinfunction "1_1") (pintype "passive"))
      (node (ref "C250") (pin "1") (pinfunction "1_1") (pintype "passive"))
      (node (ref "C251") (pin "1") (pinfunction "1_1") (pintype "passive"))
      (node (ref "C252") (pin "1") (pinfunction "1_1") (pintype "passive"))
      (node (ref "C253") (pin "1") (pinfunction "1_1") (pintype "passive"))
      (node (ref "C254") (pin "1") (pinfunction "1_1") (pintype "passive"))
      (node (ref "C255") (pin "1") (pinfunction "1_1") (pintype "passive"))
      (node (ref "C256") (pin "1") (pinfunction "1_1") (pintype "passive"))
      (node (ref "C257") (pin "1") (pinfunction "1_1") (pintype "passive"))
      (node (ref "C258") (pin "1") (pinfunction "1_1") (pintype "passive"))
      (node (ref "C259") (pin "1") (pinfunction "1_1") (pintype "passive"))
      (node (ref "C260") (pin "1") (pinfunction "1_1") (pintype "passive"))
      (node (ref "C261") (pin "1") (pinfunction "1_1") (pintype "passive"))
      (node (ref "C262") (pin "1") (pinfunction "1_1") (pintype "passive"))
      (node (ref "C263") (pin "1") (pinfunction "1_1") (pintype "passive"))
      (node (ref "C264") (pin "1") (pinfunction "1_1") (pintype "passive"))
      (node (ref "C265") (pin "1") (pinfunction "1_1") (pintype "passive"))
      (node (ref "C266") (pin "1") (pinfunction "1_1") (pintype "passive"))
      (node (ref "C270") (pin "1") (pinfunction "1_1") (pintype "passive"))
      (node (ref "C272") (pin "1") (pinfunction "1_1") (pintype "passive"))
      (node (ref "C280") (pin "1") (pinfunction "1_1") (pintype "passive"))
      (node (ref "C281") (pin "1") (pinfunction "1_1") (pintype "passive"))
      (node (ref "C282") (pin "1") (pinfunction "1_1") (pintype "passive"))
      (node (ref "C283") (pin "1") (pinfunction "1_1") (pintype "passive"))
      (node (ref "C284") (pin "1") (pinfunction "1_1") (pintype "passive"))
      (node (ref "C285") (pin "1") (pinfunction "1_1") (pintype "passive"))
      (node (ref "C286") (pin "1") (pinfunction "1_1") (pintype "passive"))
      (node (ref "C287") (pin "1") (pinfunction "1_1") (pintype "passive"))
      (node (ref "C288") (pin "1") (pinfunction "1_1") (pintype "passive"))
      (node (ref "C289") (pin "1") (pinfunction "1_1") (pintype "passive"))
      (node (ref "C290") (pin "1") (pinfunction "1_1") (pintype "passive"))
      (node (ref "C291") (pin "1") (pinfunction "1_1") (pintype "passive"))
      (node (ref "C292") (pin "1") (pinfunction "1_1") (pintype "passive"))
      (node (ref "C293") (pin "1") (pinfunction "1_1") (pintype "passive"))
      (node (ref "C294") (pin "1") (pinfunction "1_1") (pintype "passive"))
      (node (ref "C295") (pin "1") (pinfunction "1_1") (pintype "passive"))
      (node (ref "C296") (pin "1") (pinfunction "1_1") (pintype "passive"))
      (node (ref "C297") (pin "1") (pinfunction "1_1") (pintype "passive"))
      (node (ref "C298") (pin "1") (pinfunction "1_1") (pintype "passive"))
      (node (ref "C299") (pin "1") (pinfunction "1_1") (pintype "passive"))
      (node (ref "C300") (pin "1") (pinfunction "1_1") (pintype "passive"))
      (node (ref "C301") (pin "1") (pinfunction "1_1") (pintype "passive"))
      (node (ref "C302") (pin "1") (pinfunction "1_1") (pintype "passive"))
      (node (ref "C303") (pin "1") (pinfunction "1_1") (pintype "passive"))
      (node (ref "C304") (pin "1") (pinfunction "1_1") (pintype "passive"))
      (node (ref "C305") (pin "1") (pinfunction "1_1") (pintype "passive"))
      (node (ref "C306") (pin "1") (pinfunction "1_1") (pintype "passive"))
      (node (ref "C307") (pin "1") (pinfunction "1_1") (pintype "passive"))
      (node (ref "C308") (pin "1") (pinfunction "1_1") (pintype "passive"))
      (node (ref "C309") (pin "1") (pinfunction "1_1") (pintype "passive"))
      (node (ref "C310") (pin "1") (pinfunction "1_1") (pintype "passive"))
      (node (ref "C311") (pin "1") (pinfunction "1_1") (pintype "passive"))
      (node (ref "C312") (pin "1") (pinfunction "1_1") (pintype "passive"))
      (node (ref "C313") (pin "1") (pinfunction "1_1") (pintype "passive"))
      (node (ref "C314") (pin "1") (pinfunction "1_1") (pintype "passive"))
      (node (ref "C315") (pin "1") (pinfunction "1_1") (pintype "passive"))
      (node (ref "C316") (pin "1") (pinfunction "1_1") (pintype "passive"))
      (node (ref "C317") (pin "1") (pinfunction "1_1") (pintype "passive"))
      (node (ref "C318") (pin "1") (pinfunction "1_1") (pintype "passive"))
      (node (ref "C319") (pin "1") (pinfunction "1_1") (pintype "passive"))
      (node (ref "C320") (pin "1") (pinfunction "1_1") (pintype "passive"))
      (node (ref "C321") (pin "1") (pinfunction "1_1") (pintype "passive"))
      (node (ref "C322") (pin "1") (pinfunction "1_1") (pintype "passive"))
      (node (ref "C323") (pin "1") (pinfunction "1_1") (pintype "passive"))
      (node (ref "C324") (pin "1") (pinfunction "1_1") (pintype "passive"))
      (node (ref "C325") (pin "1") (pinfunction "1_1") (pintype "passive"))
      (node (ref "C326") (pin "1") (pinfunction "1_1") (pintype "passive"))
      (node (ref "C327") (pin "1") (pinfunction "1_1") (pintype "passive"))
      (node (ref "C328") (pin "1") (pinfunction "1_1") (pintype "passive"))
      (node (ref "C329") (pin "1") (pinfunction "1_1") (pintype "passive"))
      (node (ref "C330") (pin "1") (pinfunction "1_1") (pintype "passive"))
      (node (ref "C331") (pin "1") (pinfunction "1_1") (pintype "passive"))
      (node (ref "C332") (pin "1") (pinfunction "1_1") (pintype "passive"))
      (node (ref "C48") (pin "1") (pinfunction "1_1") (pintype "passive"))
      (node (ref "IC100") (pin "2") (pinfunction "VDD_2") (pintype "input"))
      (node (ref "IC101") (pin "2") (pinfunction "VDD_2") (pintype "input"))
      (node (ref "IC102") (pin "2") (pinfunction "VDD_2") (pintype "input"))
      (node (ref "IC103") (pin "2") (pinfunction "VDD_2") (pintype "input"))
      (node (ref "IC104") (pin "2") (pinfunction "VDD_2") (pintype "input"))
      (node (ref "IC105") (pin "2") (pinfunction "VDD_2") (pintype "input"))
      (node (ref "IC106") (pin "2") (pinfunction "VDD_2") (pintype "input"))
      (node (ref "IC107") (pin "2") (pinfunction "VDD_2") (pintype "input"))
      (node (ref "IC108") (pin "2") (pinfunction "VDD_2") (pintype "input"))
      (node (ref "IC109") (pin "2") (pinfunction "VDD_2") (pintype "input"))
      (node (ref "IC110") (pin "2") (pinfunction "VDD_2") (pintype "input"))
      (node (ref "IC111") (pin "2") (pinfunction "VDD_2") (pintype "input"))
      (node (ref "IC112") (pin "2") (pinfunction "VDD_2") (pintype "input"))
      (node (ref "IC113") (pin "2") (pinfunction "VDD_2") (pintype "input"))
      (node (ref "IC114") (pin "2") (pinfunction "VDD_2") (pintype "input"))
      (node (ref "IC115") (pin "2") (pinfunction "VDD_2") (pintype "input"))
      (node (ref "IC116") (pin "2") (pinfunction "VDD_2") (pintype "input"))
      (node (ref "IC117") (pin "2") (pinfunction "VDD_2") (pintype "input"))
      (node (ref "IC118") (pin "2") (pinfunction "VDD_2") (pintype "input"))
      (node (ref "IC119") (pin "2") (pinfunction "VDD_2") (pintype "input"))
      (node (ref "IC120") (pin "2") (pinfunction "VDD_2") (pintype "input"))
      (node (ref "IC121") (pin "2") (pinfunction "VDD_2") (pintype "input"))
      (node (ref "IC122") (pin "2") (pinfunction "VDD_2") (pintype "input"))
      (node (ref "IC123") (pin "2") (pinfunction "VDD_2") (pintype "input"))
      (node (ref "IC124") (pin "2") (pinfunction "VDD_2") (pintype "input"))
      (node (ref "IC125") (pin "2") (pinfunction "VDD_2") (pintype "input"))
      (node (ref "IC126") (pin "2") (pinfunction "VDD_2") (pintype "input"))
      (node (ref "IC127") (pin "2") (pinfunction "VDD_2") (pintype "input"))
      (node (ref "IC128") (pin "2") (pinfunction "VDD_2") (pintype "input"))
      (node (ref "IC129") (pin "2") (pinfunction "VDD_2") (pintype "input"))
      (node (ref "IC130") (pin "2") (pinfunction "VDD_2") (pintype "input"))
      (node (ref "IC131") (pin "2") (pinfunction "VDD_2") (pintype "input"))
      (node (ref "IC132") (pin "2") (pinfunction "VDD_2") (pintype "input"))
      (node (ref "IC133") (pin "2") (pinfunction "VDD_2") (pintype "input"))
      (node (ref "IC134") (pin "2") (pinfunction "VDD_2") (pintype "input"))
      (node (ref "IC135") (pin "2") (pinfunction "VDD_2") (pintype "input"))
      (node (ref "IC136") (pin "2") (pinfunction "VDD_2") (pintype "input"))
      (node (ref "IC137") (pin "2") (pinfunction "VDD_2") (pintype "input"))
      (node (ref "IC138") (pin "2") (pinfunction "VDD_2") (pintype "input"))
      (node (ref "IC139") (pin "2") (pinfunction "VDD_2") (pintype "input"))
      (node (ref "IC140") (pin "2") (pinfunction "VDD_2") (pintype "input"))
      (node (ref "IC141") (pin "2") (pinfunction "VDD_2") (pintype "input"))
      (node (ref "IC142") (pin "2") (pinfunction "VDD_2") (pintype "input"))
      (node (ref "IC143") (pin "2") (pinfunction "VDD_2") (pintype "input"))
      (node (ref "IC144") (pin "2") (pinfunction "VDD_2") (pintype "input"))
      (node (ref "IC145") (pin "2") (pinfunction "VDD_2") (pintype "input"))
      (node (ref "IC146") (pin "2") (pinfunction "VDD_2") (pintype "input"))
      (node (ref "IC147") (pin "2") (pinfunction "VDD_2") (pintype "input"))
      (node (ref "IC148") (pin "2") (pinfunction "VDD_2") (pintype "input"))
      (node (ref "IC149") (pin "2") (pinfunction "VDD_2") (pintype "input"))
      (node (ref "IC150") (pin "2") (pinfunction "VDD_2") (pintype "input"))
      (node (ref "IC151") (pin "2") (pinfunction "VDD_2") (pintype "input"))
      (node (ref "IC152") (pin "2") (pinfunction "VDD_2") (pintype "input"))
      (node (ref "IC153") (pin "2") (pinfunction "VDD_2") (pintype "input"))
      (node (ref "IC154") (pin "2") (pinfunction "VDD_2") (pintype "input"))
      (node (ref "IC155") (pin "2") (pinfunction "VDD_2") (pintype "input"))
      (node (ref "IC156") (pin "2") (pinfunction "VDD_2") (pintype "input"))
      (node (ref "IC157") (pin "2") (pinfunction "VDD_2") (pintype "input"))
      (node (ref "IC158") (pin "2") (pinfunction "VDD_2") (pintype "input"))
      (node (ref "IC159") (pin "2") (pinfunction "VDD_2") (pintype "input"))
      (node (ref "IC160") (pin "2") (pinfunction "VDD_2") (pintype "input"))
      (node (ref "IC161") (pin "2") (pinfunction "VDD_2") (pintype "input"))
      (node (ref "IC162") (pin "2") (pinfunction "VDD_2") (pintype "input"))
      (node (ref "IC163") (pin "2") (pinfunction "VDD_2") (pintype "input"))
      (node (ref "IC164") (pin "2") (pinfunction "VDD_2") (pintype "input"))
      (node (ref "IC165") (pin "2") (pinfunction "VDD_2") (pintype "input"))
      (node (ref "IC166") (pin "2") (pinfunction "VDD_2") (pintype "input"))
      (node (ref "IC167") (pin "2") (pinfunction "VDD_2") (pintype "input"))
      (node (ref "IC168") (pin "2") (pinfunction "VDD_2") (pintype "input"))
      (node (ref "IC169") (pin "2") (pinfunction "VDD_2") (pintype "input"))
      (node (ref "IC17") (pin "5") (pinfunction "VBUS_5") (pintype "input"))
      (node (ref "IC170") (pin "2") (pinfunction "VDD_2") (pintype "input"))
      (node (ref "IC171") (pin "2") (pinfunction "VDD_2") (pintype "input"))
      (node (ref "IC172") (pin "2") (pinfunction "VDD_2") (pintype "input"))
      (node (ref "IC173") (pin "2") (pinfunction "VDD_2") (pintype "input"))
      (node (ref "IC174") (pin "2") (pinfunction "VDD_2") (pintype "input"))
      (node (ref "IC175") (pin "2") (pinfunction "VDD_2") (pintype "input"))
      (node (ref "IC176") (pin "2") (pinfunction "VDD_2") (pintype "input"))
      (node (ref "IC177") (pin "2") (pinfunction "VDD_2") (pintype "input"))
      (node (ref "IC178") (pin "2") (pinfunction "VDD_2") (pintype "input"))
      (node (ref "IC179") (pin "2") (pinfunction "VDD_2") (pintype "input"))
      (node (ref "IC180") (pin "2") (pinfunction "VDD_2") (pintype "input"))
      (node (ref "IC181") (pin "2") (pinfunction "VDD_2") (pintype "input"))
      (node (ref "IC182") (pin "2") (pinfunction "VDD_2") (pintype "input"))
      (node (ref "IC183") (pin "2") (pinfunction "VDD_2") (pintype "input"))
      (node (ref "IC184") (pin "2") (pinfunction "VDD_2") (pintype "input"))
      (node (ref "IC185") (pin "2") (pinfunction "VDD_2") (pintype "input"))
      (node (ref "IC186") (pin "2") (pinfunction "VDD_2") (pintype "input"))
      (node (ref "IC187") (pin "2") (pinfunction "VDD_2") (pintype "input"))
      (node (ref "IC188") (pin "2") (pinfunction "VDD_2") (pintype "input"))
      (node (ref "IC189") (pin "2") (pinfunction "VDD_2") (pintype "input"))
      (node (ref "IC190") (pin "2") (pinfunction "VDD_2") (pintype "input"))
      (node (ref "IC191") (pin "2") (pinfunction "VDD_2") (pintype "input"))
      (node (ref "IC192") (pin "2") (pinfunction "VDD_2") (pintype "input"))
      (node (ref "IC193") (pin "2") (pinfunction "VDD_2") (pintype "input"))
      (node (ref "IC194") (pin "2") (pinfunction "VDD_2") (pintype "input"))
      (node (ref "IC195") (pin "2") (pinfunction "VDD_2") (pintype "input"))
      (node (ref "IC196") (pin "2") (pinfunction "VDD_2") (pintype "input"))
      (node (ref "IC197") (pin "2") (pinfunction "VDD_2") (pintype "input"))
      (node (ref "IC198") (pin "2") (pinfunction "VDD_2") (pintype "input"))
      (node (ref "IC199") (pin "2") (pinfunction "VDD_2") (pintype "input"))
      (node (ref "IC200") (pin "2") (pinfunction "VDD_2") (pintype "input"))
      (node (ref "IC201") (pin "2") (pinfunction "VDD_2") (pintype "input"))
      (node (ref "IC202") (pin "2") (pinfunction "VDD_2") (pintype "input"))
      (node (ref "IC203") (pin "2") (pinfunction "VDD_2") (pintype "input"))
      (node (ref "IC204") (pin "2") (pinfunction "VDD_2") (pintype "input"))
      (node (ref "IC205") (pin "2") (pinfunction "VDD_2") (pintype "input"))
      (node (ref "IC206") (pin "2") (pinfunction "VDD_2") (pintype "input"))
      (node (ref "IC207") (pin "2") (pinfunction "VDD_2") (pintype "input"))
      (node (ref "IC208") (pin "2") (pinfunction "VDD_2") (pintype "input"))
      (node (ref "IC209") (pin "2") (pinfunction "VDD_2") (pintype "input"))
      (node (ref "IC210") (pin "2") (pinfunction "VDD_2") (pintype "input"))
      (node (ref "IC211") (pin "2") (pinfunction "VDD_2") (pintype "input"))
      (node (ref "IC212") (pin "2") (pinfunction "VDD_2") (pintype "input"))
      (node (ref "IC213") (pin "2") (pinfunction "VDD_2") (pintype "input"))
      (node (ref "IC214") (pin "2") (pinfunction "VDD_2") (pintype "input"))
      (node (ref "IC215") (pin "2") (pinfunction "VDD_2") (pintype "input"))
      (node (ref "IC216") (pin "2") (pinfunction "VDD_2") (pintype "input"))
      (node (ref "IC217") (pin "2") (pinfunction "VDD_2") (pintype "input"))
      (node (ref "IC218") (pin "2") (pinfunction "VDD_2") (pintype "input"))
      (node (ref "IC219") (pin "2") (pinfunction "VDD_2") (pintype "input"))
      (node (ref "IC220") (pin "2") (pinfunction "VDD_2") (pintype "input"))
      (node (ref "IC221") (pin "2") (pinfunction "VDD_2") (pintype "input"))
      (node (ref "IC222") (pin "2") (pinfunction "VDD_2") (pintype "input"))
      (node (ref "IC223") (pin "2") (pinfunction "VDD_2") (pintype "input"))
      (node (ref "IC224") (pin "2") (pinfunction "VDD_2") (pintype "input"))
      (node (ref "IC225") (pin "2") (pinfunction "VDD_2") (pintype "input"))
      (node (ref "IC226") (pin "2") (pinfunction "VDD_2") (pintype "input"))
      (node (ref "IC227") (pin "2") (pinfunction "VDD_2") (pintype "input"))
      (node (ref "IC228") (pin "2") (pinfunction "VDD_2") (pintype "input"))
      (node (ref "IC229") (pin "2") (pinfunction "VDD_2") (pintype "input"))
      (node (ref "IC230") (pin "2") (pinfunction "VDD_2") (pintype "input"))
      (node (ref "IC231") (pin "2") (pinfunction "VDD_2") (pintype "input"))
      (node (ref "IC232") (pin "2") (pinfunction "VDD_2") (pintype "input"))
      (node (ref "IC233") (pin "2") (pinfunction "VDD_2") (pintype "input"))
      (node (ref "IC234") (pin "2") (pinfunction "VDD_2") (pintype "input"))
      (node (ref "IC235") (pin "2") (pinfunction "VDD_2") (pintype "input"))
      (node (ref "IC236") (pin "2") (pinfunction "VDD_2") (pintype "input"))
      (node (ref "IC237") (pin "2") (pinfunction "VDD_2") (pintype "input"))
      (node (ref "IC238") (pin "2") (pinfunction "VDD_2") (pintype "input"))
      (node (ref "IC239") (pin "2") (pinfunction "VDD_2") (pintype "input"))
      (node (ref "IC240") (pin "2") (pinfunction "VDD_2") (pintype "input"))
      (node (ref "IC241") (pin "2") (pinfunction "VDD_2") (pintype "input"))
      (node (ref "IC242") (pin "2") (pinfunction "VDD_2") (pintype "input"))
      (node (ref "IC243") (pin "2") (pinfunction "VDD_2") (pintype "input"))
      (node (ref "IC244") (pin "2") (pinfunction "VDD_2") (pintype "input"))
      (node (ref "IC245") (pin "2") (pinfunction "VDD_2") (pintype "input"))
      (node (ref "IC246") (pin "2") (pinfunction "VDD_2") (pintype "input"))
      (node (ref "IC247") (pin "2") (pinfunction "VDD_2") (pintype "input"))
      (node (ref "IC248") (pin "2") (pinfunction "VDD_2") (pintype "input"))
      (node (ref "IC249") (pin "2") (pinfunction "VDD_2") (pintype "input"))
      (node (ref "IC250") (pin "2") (pinfunction "VDD_2") (pintype "input"))
      (node (ref "IC251") (pin "2") (pinfunction "VDD_2") (pintype "input"))
      (node (ref "IC252") (pin "2") (pinfunction "VDD_2") (pintype "input"))
      (node (ref "IC253") (pin "2") (pinfunction "VDD_2") (pintype "input"))
      (node (ref "IC254") (pin "2") (pinfunction "VDD_2") (pintype "input"))
      (node (ref "IC255") (pin "2") (pinfunction "VDD_2") (pintype "input"))
      (node (ref "IC256") (pin "2") (pinfunction "VDD_2") (pintype "input"))
      (node (ref "IC257") (pin "2") (pinfunction "VDD_2") (pintype "input"))
      (node (ref "IC258") (pin "2") (pinfunction "VDD_2") (pintype "input"))
      (node (ref "IC259") (pin "2") (pinfunction "VDD_2") (pintype "input"))
      (node (ref "IC260") (pin "2") (pinfunction "VDD_2") (pintype "input"))
      (node (ref "IC261") (pin "2") (pinfunction "VDD_2") (pintype "input"))
      (node (ref "IC262") (pin "2") (pinfunction "VDD_2") (pintype "input"))
      (node (ref "IC263") (pin "2") (pinfunction "VDD_2") (pintype "input"))
      (node (ref "IC264") (pin "2") (pinfunction "VDD_2") (pintype "input"))
      (node (ref "IC265") (pin "2") (pinfunction "VDD_2") (pintype "input"))
      (node (ref "IC266") (pin "2") (pinfunction "VDD_2") (pintype "input"))
      (node (ref "IC267") (pin "2") (pinfunction "VDD_2") (pintype "input"))
      (node (ref "IC268") (pin "2") (pinfunction "VDD_2") (pintype "input"))
      (node (ref "IC269") (pin "2") (pinfunction "VDD_2") (pintype "input"))
      (node (ref "IC270") (pin "2") (pinfunction "VDD_2") (pintype "input"))
      (node (ref "IC271") (pin "2") (pinfunction "VDD_2") (pintype "input"))
      (node (ref "IC272") (pin "2") (pinfunction "VDD_2") (pintype "input"))
      (node (ref "IC273") (pin "2") (pinfunction "VDD_2") (pintype "input"))
      (node (ref "IC274") (pin "2") (pinfunction "VDD_2") (pintype "input"))
      (node (ref "IC275") (pin "2") (pinfunction "VDD_2") (pintype "input"))
      (node (ref "IC276") (pin "2") (pinfunction "VDD_2") (pintype "input"))
      (node (ref "IC277") (pin "2") (pinfunction "VDD_2") (pintype "input"))
      (node (ref "IC278") (pin "2") (pinfunction "VDD_2") (pintype "input"))
      (node (ref "IC279") (pin "2") (pinfunction "VDD_2") (pintype "input"))
      (node (ref "IC280") (pin "2") (pinfunction "VDD_2") (pintype "input"))
      (node (ref "IC281") (pin "2") (pinfunction "VDD_2") (pintype "input"))
      (node (ref "IC282") (pin "2") (pinfunction "VDD_2") (pintype "input"))
      (node (ref "IC283") (pin "2") (pinfunction "VDD_2") (pintype "input"))
      (node (ref "IC284") (pin "2") (pinfunction "VDD_2") (pintype "input"))
      (node (ref "IC285") (pin "2") (pinfunction "VDD_2") (pintype "input"))
      (node (ref "IC286") (pin "2") (pinfunction "VDD_2") (pintype "input"))
      (node (ref "IC287") (pin "2") (pinfunction "VDD_2") (pintype "input"))
      (node (ref "IC288") (pin "2") (pinfunction "VDD_2") (pintype "input"))
      (node (ref "IC289") (pin "2") (pinfunction "VDD_2") (pintype "input"))
      (node (ref "IC290") (pin "2") (pinfunction "VDD_2") (pintype "input"))
      (node (ref "IC291") (pin "2") (pinfunction "VDD_2") (pintype "input"))
      (node (ref "IC292") (pin "2") (pinfunction "VDD_2") (pintype "input"))
      (node (ref "IC293") (pin "2") (pinfunction "VDD_2") (pintype "input"))
      (node (ref "IC294") (pin "2") (pinfunction "VDD_2") (pintype "input"))
      (node (ref "IC295") (pin "2") (pinfunction "VDD_2") (pintype "input"))
      (node (ref "IC296") (pin "2") (pinfunction "VDD_2") (pintype "input"))
      (node (ref "IC297") (pin "2") (pinfunction "VDD_2") (pintype "input"))
      (node (ref "IC298") (pin "2") (pinfunction "VDD_2") (pintype "input"))
      (node (ref "IC299") (pin "2") (pinfunction "VDD_2") (pintype "input"))
      (node (ref "IC300") (pin "2") (pinfunction "VDD_2") (pintype "input"))
      (node (ref "IC301") (pin "2") (pinfunction "VDD_2") (pintype "input"))
      (node (ref "IC302") (pin "2") (pinfunction "VDD_2") (pintype "input"))
      (node (ref "IC303") (pin "2") (pinfunction "VDD_2") (pintype "input"))
      (node (ref "IC304") (pin "2") (pinfunction "VDD_2") (pintype "input"))
      (node (ref "IC305") (pin "2") (pinfunction "VDD_2") (pintype "input"))
      (node (ref "IC306") (pin "2") (pinfunction "VDD_2") (pintype "input"))
      (node (ref "IC307") (pin "2") (pinfunction "VDD_2") (pintype "input"))
      (node (ref "IC308") (pin "2") (pinfunction "VDD_2") (pintype "input"))
      (node (ref "IC309") (pin "2") (pinfunction "VDD_2") (pintype "input"))
      (node (ref "IC310") (pin "2") (pinfunction "VDD_2") (pintype "input"))
      (node (ref "IC311") (pin "2") (pinfunction "VDD_2") (pintype "input"))
      (node (ref "IC312") (pin "2") (pinfunction "VDD_2") (pintype "input"))
      (node (ref "IC313") (pin "2") (pinfunction "VDD_2") (pintype "input"))
      (node (ref "IC314") (pin "2") (pinfunction "VDD_2") (pintype "input"))
      (node (ref "IC315") (pin "2") (pinfunction "VDD_2") (pintype "input"))
      (node (ref "IC316") (pin "2") (pinfunction "VDD_2") (pintype "input"))
      (node (ref "IC317") (pin "2") (pinfunction "VDD_2") (pintype "input"))
      (node (ref "IC318") (pin "2") (pinfunction "VDD_2") (pintype "input"))
      (node (ref "IC319") (pin "2") (pinfunction "VDD_2") (pintype "input"))
      (node (ref "IC320") (pin "2") (pinfunction "VDD_2") (pintype "input"))
      (node (ref "IC321") (pin "2") (pinfunction "VDD_2") (pintype "input"))
      (node (ref "IC322") (pin "2") (pinfunction "VDD_2") (pintype "input"))
      (node (ref "IC323") (pin "2") (pinfunction "VDD_2") (pintype "input"))
      (node (ref "IC324") (pin "2") (pinfunction "VDD_2") (pintype "input"))
      (node (ref "IC325") (pin "2") (pinfunction "VDD_2") (pintype "input"))
      (node (ref "IC326") (pin "2") (pinfunction "VDD_2") (pintype "input"))
      (node (ref "IC327") (pin "2") (pinfunction "VDD_2") (pintype "input"))
      (node (ref "IC328") (pin "2") (pinfunction "VDD_2") (pintype "input"))
      (node (ref "IC329") (pin "2") (pinfunction "VDD_2") (pintype "input"))
      (node (ref "IC330") (pin "2") (pinfunction "VDD_2") (pintype "input"))
      (node (ref "IC331") (pin "2") (pinfunction "VDD_2") (pintype "input"))
      (node (ref "IC332") (pin "2") (pinfunction "VDD_2") (pintype "input"))
      (node (ref "TP7") (pin "TP") (pinfunction "TP_TP") (pintype "input"))
      (node (ref "X1") (pin "23") (pinfunction "23_23") (pintype "passive"))
      (node (ref "X1") (pin "25") (pinfunction "25_25") (pintype "passive"))
    )
    (net (code "7") (name "+INTEGRAL_PHOTOVOLTAGE") (class "Default")
      (node (ref "IC23") (pin "3") (pinfunction "S2A_3") (pintype "passive"))
      (node (ref "R58") (pin "2") (pinfunction "2_2") (pintype "passive"))
    )
    (net (code "8") (name "+PVCC") (class "Default")
      (node (ref "C1") (pin "1") (pinfunction "1_1") (pintype "passive"))
      (node (ref "C12") (pin "1") (pinfunction "1_1") (pintype "passive"))
      (node (ref "C13") (pin "1") (pinfunction "1_1") (pintype "passive"))
      (node (ref "C14") (pin "1") (pinfunction "1_1") (pintype "passive"))
      (node (ref "C16") (pin "1") (pinfunction "1_1") (pintype "passive"))
      (node (ref "C2") (pin "1") (pinfunction "1_1") (pintype "passive"))
      (node (ref "C20") (pin "1") (pinfunction "1_1") (pintype "passive"))
      (node (ref "C21") (pin "1") (pinfunction "1_1") (pintype "passive"))
      (node (ref "C22") (pin "1") (pinfunction "1_1") (pintype "passive"))
      (node (ref "C25") (pin "1") (pinfunction "1_1") (pintype "passive"))
      (node (ref "C27") (pin "1") (pinfunction "1_1") (pintype "passive"))
      (node (ref "C28") (pin "1") (pinfunction "1_1") (pintype "passive"))
      (node (ref "C30") (pin "1") (pinfunction "1_1") (pintype "passive"))
      (node (ref "C32") (pin "1") (pinfunction "1_1") (pintype "passive"))
      (node (ref "C33") (pin "1") (pinfunction "1_1") (pintype "passive"))
      (node (ref "C4") (pin "1") (pinfunction "1_1") (pintype "passive"))
      (node (ref "C41") (pin "1") (pinfunction "1_1") (pintype "passive"))
      (node (ref "C42") (pin "1") (pinfunction "1_1") (pintype "passive"))
      (node (ref "C43") (pin "1") (pinfunction "1_1") (pintype "passive"))
      (node (ref "R15") (pin "2") (pinfunction "2_2") (pintype "passive"))
      (node (ref "R20") (pin "2") (pinfunction "2_2") (pintype "passive"))
      (node (ref "R22") (pin "2") (pinfunction "2_2") (pintype "passive"))
      (node (ref "R25") (pin "2") (pinfunction "2_2") (pintype "passive"))
      (node (ref "R29") (pin "2") (pinfunction "2_2") (pintype "passive"))
      (node (ref "R34") (pin "2") (pinfunction "2_2") (pintype "passive"))
      (node (ref "R35") (pin "2") (pinfunction "2_2") (pintype "passive"))
      (node (ref "R43") (pin "2") (pinfunction "2_2") (pintype "passive"))
      (node (ref "R46") (pin "2") (pinfunction "2_2") (pintype "passive"))
      (node (ref "R52") (pin "2") (pinfunction "2_2") (pintype "passive"))
      (node (ref "R57") (pin "2") (pinfunction "2_2") (pintype "passive"))
      (node (ref "R66") (pin "2") (pinfunction "2_2") (pintype "passive"))
      (node (ref "R69") (pin "2") (pinfunction "2_2") (pintype "passive"))
      (node (ref "R7") (pin "2") (pinfunction "2_2") (pintype "passive"))
      (node (ref "R73") (pin "2") (pinfunction "2_2") (pintype "passive"))
      (node (ref "R75") (pin "2") (pinfunction "2_2") (pintype "passive"))
      (node (ref "R8") (pin "2") (pinfunction "2_2") (pintype "passive"))
      (node (ref "R83") (pin "2") (pinfunction "2_2") (pintype "passive"))
      (node (ref "R84") (pin "2") (pinfunction "2_2") (pintype "passive"))
      (node (ref "TP2") (pin "TP") (pinfunction "TP_TP") (pintype "input"))
      (node (ref "X2") (pin "02") (pinfunction "2_02") (pintype "passive"))
      (node (ref "X2") (pin "04") (pinfunction "4_04") (pintype "passive"))
      (node (ref "X2") (pin "06") (pinfunction "6_06") (pintype "passive"))
      (node (ref "X2") (pin "08") (pinfunction "8_08") (pintype "passive"))
    )
    (net (code "9") (name "+VBAT") (class "Default")
      (node (ref "R1") (pin "1") (pinfunction "1_1") (pintype "passive"))
      (node (ref "R38") (pin "1") (pinfunction "1_1") (pintype "passive"))
      (node (ref "R44") (pin "1") (pinfunction "1_1") (pintype "passive"))
      (node (ref "R78") (pin "1") (pinfunction "1_1") (pintype "passive"))
      (node (ref "R9") (pin "1") (pinfunction "1_1") (pintype "passive"))
      (node (ref "TP4") (pin "TP") (pinfunction "TP_TP") (pintype "input"))
      (node (ref "X1") (pin "30") (pinfunction "30_30") (pintype "passive"))
    )
    (net (code "10") (name "-INTEGRAL_PHOTOVOLTAGE") (class "Default")
      (node (ref "C31") (pin "2") (pinfunction "2_2") (pintype "passive"))
      (node (ref "IC11") (pin "1") (pinfunction "OUT_1") (pintype "output"))
      (node (ref "IC23") (pin "2") (pinfunction "S1A_2") (pintype "passive"))
      (node (ref "R41") (pin "1") (pinfunction "1_1") (pintype "passive"))
      (node (ref "R68") (pin "2") (pinfunction "2_2") (pintype "passive"))
    )
    (net (code "11") (name "/CAM1_RGB_~{PWDN_1V8}") (class "Default")
      (node (ref "IC12") (pin "3") (pinfunction "I/O2_3") (pintype "passive"))
      (node (ref "X1") (pin "08") (pinfunction "8_08") (pintype "passive"))
      (node (ref "X3") (pin "26") (pinfunction "26_26") (pintype "bidirectional"))
    )
    (net (code "12") (name "/CAM3_TOF_~{PWDN}_1V8") (class "Default")
      (node (ref "IC18") (pin "6") (pinfunction "I/O4_6") (pintype "passive"))
      (node (ref "X2") (pin "16") (pinfunction "16_16") (pintype "passive"))
      (node (ref "X5") (pin "30") (pinfunction "30_30") (pintype "passive"))
    )
    (net (code "13") (name "/FET_DRV_~{EN}") (class "Default")
      (node (ref "IC1") (pin "4") (pinfunction "IN-_4") (pintype "input"))
      (node (ref "IC10") (pin "4") (pinfunction "IN-_4") (pintype "input"))
      (node (ref "IC13") (pin "4") (pinfunction "IN-_4") (pintype "input"))
      (node (ref "IC2") (pin "4") (pinfunction "IN-_4") (pintype "input"))
      (node (ref "IC8") (pin "4") (pinfunction "IN-_4") (pintype "input"))
      (node (ref "T8") (pin "3") (pinfunction "D_3") (pintype "passive"))
    )
    (net (code "14") (name "/PVCC_SHDN_RST") (class "Default")
      (node (ref "R37") (pin "1") (pinfunction "1_1") (pintype "passive"))
      (node (ref "TP13") (pin "TP") (pinfunction "TP_TP") (pintype "input"))
    )
    (net (code "15") (name "/VCC_IO") (class "Default")
      (node (ref "C52") (pin "1") (pinfunction "1_1") (pintype "passive"))
      (node (ref "R88") (pin "1") (pinfunction "1_1") (pintype "passive"))
      (node (ref "X4") (pin "4") (pinfunction "4_4") (pintype "passive"))
    )
    (net (code "16") (name "/VIN_A") (class "Default")
      (node (ref "C53") (pin "1") (pinfunction "1_1") (pintype "passive"))
      (node (ref "L9") (pin "2") (pinfunction "2_2") (pintype "passive"))
      (node (ref "X4") (pin "3") (pinfunction "3_3") (pintype "passive"))
    )
    (net (code "17") (name "/~{PVCC_SHDN}") (class "Default")
      (node (ref "C15") (pin "2") (pinfunction "2_2") (pintype "passive"))
      (node (ref "IC9") (pin "15") (pinfunction "~{CLR}_15") (pintype "input"))
      (node (ref "R24") (pin "2") (pinfunction "2_2") (pintype "passive"))
      (node (ref "R31") (pin "1") (pinfunction "1_1") (pintype "passive"))
      (node (ref "TP11") (pin "TP") (pinfunction "TP_TP") (pintype "input"))
    )
    (net (code "18") (name "CAM1_RGB_CLK_N") (class "Default")
      (node (ref "IC21") (pin "7") (pinfunction "I/O5_7") (pintype "passive"))
      (node (ref "X1") (pin "05") (pinfunction "5_05") (pintype "passive"))
      (node (ref "X3") (pin "5") (pinfunction "5_5") (pintype "bidirectional"))
    )
    (net (code "19") (name "CAM1_RGB_CLK_P") (class "Default")
      (node (ref "IC21") (pin "8") (pinfunction "I/O6_8") (pintype "passive"))
      (node (ref "X1") (pin "03") (pinfunction "3_03") (pintype "passive"))
      (node (ref "X3") (pin "4") (pinfunction "4_4") (pintype "bidirectional"))
    )
    (net (code "20") (name "CAM1_RGB_D0_N") (class "Default")
      (node (ref "IC21") (pin "4") (pinfunction "I/O3_4") (pintype "passive"))
      (node (ref "X1") (pin "11") (pinfunction "11_11") (pintype "passive"))
      (node (ref "X3") (pin "8") (pinfunction "8_8") (pintype "bidirectional"))
    )
    (net (code "21") (name "CAM1_RGB_D0_P") (class "Default")
      (node (ref "IC21") (pin "5") (pinfunction "I/O4_5") (pintype "passive"))
      (node (ref "X1") (pin "09") (pinfunction "9_09") (pintype "passive"))
      (node (ref "X3") (pin "7") (pinfunction "7_7") (pintype "bidirectional"))
    )
    (net (code "22") (name "CAM1_RGB_D1_N") (class "Default")
      (node (ref "IC21") (pin "1") (pinfunction "I/O1_1") (pintype "passive"))
      (node (ref "X1") (pin "17") (pinfunction "17_17") (pintype "passive"))
      (node (ref "X3") (pin "11") (pinfunction "11_11") (pintype "bidirectional"))
    )
    (net (code "23") (name "CAM1_RGB_D1_P") (class "Default")
      (node (ref "IC21") (pin "2") (pinfunction "I/O2_2") (pintype "passive"))
      (node (ref "X1") (pin "15") (pinfunction "15_15") (pintype "passive"))
      (node (ref "X3") (pin "10") (pinfunction "10_10") (pintype "bidirectional"))
    )
    (net (code "24") (name "CAM1_RGB_I2C_SCL_1V8") (class "Default")
      (node (ref "IC12") (pin "4") (pinfunction "I/O3_4") (pintype "passive"))
      (node (ref "X1") (pin "12") (pinfunction "12_12") (pintype "passive"))
      (node (ref "X3") (pin "2") (pinfunction "2_2") (pintype "bidirectional"))
    )
    (net (code "25") (name "CAM1_RGB_I2C_SDA_1V8") (class "Default")
      (node (ref "IC12") (pin "6") (pinfunction "I/O4_6") (pintype "passive"))
      (node (ref "X1") (pin "10") (pinfunction "10_10") (pintype "passive"))
      (node (ref "X3") (pin "1") (pinfunction "1_1") (pintype "bidirectional"))
    )
    (net (code "26") (name "CAM1_RGB_MCLK_1V8") (class "Default")
      (node (ref "IC12") (pin "1") (pinfunction "I/O1_1") (pintype "passive"))
      (node (ref "X1") (pin "04") (pinfunction "4_04") (pintype "passive"))
      (node (ref "X3") (pin "24") (pinfunction "24_24") (pintype "bidirectional"))
    )
    (net (code "27") (name "CAM3_TOF_CLK_N") (class "Default")
      (node (ref "IC22") (pin "5") (pinfunction "I/O4_5") (pintype "passive"))
      (node (ref "X2") (pin "36") (pinfunction "36_36") (pintype "passive"))
      (node (ref "X5") (pin "23") (pinfunction "23_23") (pintype "passive"))
    )
    (net (code "28") (name "CAM3_TOF_CLK_P") (class "Default")
      (node (ref "IC22") (pin "4") (pinfunction "I/O3_4") (pintype "passive"))
      (node (ref "X2") (pin "38") (pinfunction "38_38") (pintype "passive"))
      (node (ref "X5") (pin "21") (pinfunction "21_21") (pintype "passive"))
    )
    (net (code "29") (name "CAM3_TOF_D0_N") (class "Default")
      (node (ref "IC22") (pin "2") (pinfunction "I/O2_2") (pintype "passive"))
      (node (ref "X2") (pin "27") (pinfunction "27_27") (pintype "passive"))
      (node (ref "X5") (pin "17") (pinfunction "17_17") (pintype "passive"))
    )
    (net (code "30") (name "CAM3_TOF_D0_P") (class "Default")
      (node (ref "IC22") (pin "1") (pinfunction "I/O1_1") (pintype "passive"))
      (node (ref "X2") (pin "29") (pinfunction "29_29") (pintype "passive"))
      (node (ref "X5") (pin "15") (pinfunction "15_15") (pintype "passive"))
    )
    (net (code "31") (name "CAM3_TOF_D1_N") (class "Default")
      (node (ref "IC22") (pin "8") (pinfunction "I/O6_8") (pintype "passive"))
      (node (ref "X2") (pin "30") (pinfunction "30_30") (pintype "passive"))
      (node (ref "X5") (pin "29") (pinfunction "29_29") (pintype "passive"))
    )
    (net (code "32") (name "CAM3_TOF_D1_P") (class "Default")
      (node (ref "IC22") (pin "7") (pinfunction "I/O5_7") (pintype "passive"))
      (node (ref "X2") (pin "32") (pinfunction "32_32") (pintype "passive"))
      (node (ref "X5") (pin "27") (pinfunction "27_27") (pintype "passive"))
    )
    (net (code "33") (name "CAM3_TOF_I2C_SCL_1V8") (class "Default")
      (node (ref "IC18") (pin "1") (pinfunction "I/O1_1") (pintype "passive"))
      (node (ref "X2") (pin "22") (pinfunction "22_22") (pintype "passive"))
      (node (ref "X5") (pin "24") (pinfunction "24_24") (pintype "passive"))
    )
    (net (code "34") (name "CAM3_TOF_I2C_SDA_1V8") (class "Default")
      (node (ref "IC18") (pin "3") (pinfunction "I/O2_3") (pintype "passive"))
      (node (ref "X2") (pin "20") (pinfunction "20_20") (pintype "passive"))
      (node (ref "X5") (pin "26") (pinfunction "26_26") (pintype "passive"))
    )
    (net (code "35") (name "CAM3_TOF_MCLK_1V8") (class "Default")
      (node (ref "IC18") (pin "4") (pinfunction "I/O3_4") (pintype "passive"))
      (node (ref "R47") (pin "1") (pinfunction "1_1") (pintype "passive"))
      (node (ref "X2") (pin "33") (pinfunction "33_33") (pintype "passive"))
    )
    (net (code "36") (name "FU_I2C_TEMP_SCL_3V3") (class "Default")
      (node (ref "IC14") (pin "4") (pinfunction "I/O3_4") (pintype "passive"))
      (node (ref "R32") (pin "2") (pinfunction "2_2") (pintype "passive"))
      (node (ref "R39") (pin "2") (pinfunction "2_2") (pintype "passive"))
      (node (ref "R82") (pin "2") (pinfunction "2_2") (pintype "passive"))
      (node (ref "TP22") (pin "TP") (pinfunction "TP_TP") (pintype "input"))
      (node (ref "X1") (pin "29") (pinfunction "29_29") (pintype "passive"))
    )
    (net (code "37") (name "FU_I2C_TEMP_SDA_3V3") (class "Default")
      (node (ref "IC14") (pin "3") (pinfunction "I/O2_3") (pintype "passive"))
      (node (ref "R30") (pin "2") (pinfunction "2_2") (pintype "passive"))
      (node (ref "R33") (pin "2") (pinfunction "2_2") (pintype "passive"))
      (node (ref "R81") (pin "2") (pinfunction "2_2") (pintype "passive"))
      (node (ref "TP23") (pin "TP") (pinfunction "TP_TP") (pintype "input"))
      (node (ref "X1") (pin "31") (pinfunction "31_31") (pintype "passive"))
    )
    (net (code "38") (name "FU_IR_PHOTO_FET_3V3") (class "Default")
      (node (ref "C29") (pin "1") (pinfunction "1_1") (pintype "passive"))
      (node (ref "R51") (pin "1") (pinfunction "1_1") (pintype "passive"))
      (node (ref "R53") (pin "1") (pinfunction "1_1") (pintype "passive"))
      (node (ref "X1") (pin "36") (pinfunction "36_36") (pintype "passive"))
    )
    (net (code "39") (name "FU_PVCC_EN_3V3") (class "Default")
      (node (ref "IC14") (pin "6") (pinfunction "I/O4_6") (pintype "passive"))
      (node (ref "R55") (pin "2") (pinfunction "2_2") (pintype "passive"))
      (node (ref "R60") (pin "1") (pinfunction "1_1") (pintype "passive"))
      (node (ref "R62") (pin "1") (pinfunction "1_1") (pintype "passive"))
      (node (ref "T8") (pin "1") (pinfunction "G_1") (pintype "passive"))
      (node (ref "TP10") (pin "TP") (pinfunction "TP_TP") (pintype "input"))
      (node (ref "X1") (pin "27") (pinfunction "27_27") (pintype "passive"))
    )
    (net (code "40") (name "FU_TAMPER_SWITCH") (class "Default")
      (node (ref "SW1") (pin "3") (pinfunction "NO_3") (pintype "passive"))
      (node (ref "SW1") (pin "4") (pinfunction "NO_4") (pintype "passive"))
      (node (ref "X1") (pin "34") (pinfunction "34_34") (pintype "passive"))
    )
    (net (code "41") (name "GND") (class "Default")
      (node (ref "C1") (pin "2") (pinfunction "2_2") (pintype "passive"))
      (node (ref "C10") (pin "2") (pinfunction "2_2") (pintype "passive"))
      (node (ref "C100") (pin "2") (pinfunction "2_2") (pintype "passive"))
      (node (ref "C101") (pin "2") (pinfunction "2_2") (pintype "passive"))
      (node (ref "C102") (pin "2") (pinfunction "2_2") (pintype "passive"))
      (node (ref "C103") (pin "2") (pinfunction "2_2") (pintype "passive"))
      (node (ref "C104") (pin "2") (pinfunction "2_2") (pintype "passive"))
      (node (ref "C105") (pin "2") (pinfunction "2_2") (pintype "passive"))
      (node (ref "C106") (pin "2") (pinfunction "2_2") (pintype "passive"))
      (node (ref "C107") (pin "2") (pinfunction "2_2") (pintype "passive"))
      (node (ref "C108") (pin "2") (pinfunction "2_2") (pintype "passive"))
      (node (ref "C109") (pin "2") (pinfunction "2_2") (pintype "passive"))
      (node (ref "C110") (pin "2") (pinfunction "2_2") (pintype "passive"))
      (node (ref "C111") (pin "2") (pinfunction "2_2") (pintype "passive"))
      (node (ref "C112") (pin "2") (pinfunction "2_2") (pintype "passive"))
      (node (ref "C113") (pin "2") (pinfunction "2_2") (pintype "passive"))
      (node (ref "C114") (pin "2") (pinfunction "2_2") (pintype "passive"))
      (node (ref "C115") (pin "2") (pinfunction "2_2") (pintype "passive"))
      (node (ref "C116") (pin "2") (pinfunction "2_2") (pintype "passive"))
      (node (ref "C117") (pin "2") (pinfunction "2_2") (pintype "passive"))
      (node (ref "C118") (pin "2") (pinfunction "2_2") (pintype "passive"))
      (node (ref "C119") (pin "2") (pinfunction "2_2") (pintype "passive"))
      (node (ref "C12") (pin "2") (pinfunction "2_2") (pintype "passive"))
      (node (ref "C120") (pin "2") (pinfunction "2_2") (pintype "passive"))
      (node (ref "C121") (pin "2") (pinfunction "2_2") (pintype "passive"))
      (node (ref "C122") (pin "2") (pinfunction "2_2") (pintype "passive"))
      (node (ref "C123") (pin "2") (pinfunction "2_2") (pintype "passive"))
      (node (ref "C124") (pin "2") (pinfunction "2_2") (pintype "passive"))
      (node (ref "C125") (pin "2") (pinfunction "2_2") (pintype "passive"))
      (node (ref "C126") (pin "2") (pinfunction "2_2") (pintype "passive"))
      (node (ref "C127") (pin "2") (pinfunction "2_2") (pintype "passive"))
      (node (ref "C128") (pin "2") (pinfunction "2_2") (pintype "passive"))
      (node (ref "C129") (pin "2") (pinfunction "2_2") (pintype "passive"))
      (node (ref "C13") (pin "2") (pinfunction "2_2") (pintype "passive"))
      (node (ref "C130") (pin "2") (pinfunction "2_2") (pintype "passive"))
      (node (ref "C131") (pin "2") (pinfunction "2_2") (pintype "passive"))
      (node (ref "C132") (pin "2") (pinfunction "2_2") (pintype "passive"))
      (node (ref "C133") (pin "2") (pinfunction "2_2") (pintype "passive"))
      (node (ref "C134") (pin "2") (pinfunction "2_2") (pintype "passive"))
      (node (ref "C135") (pin "2") (pinfunction "2_2") (pintype "passive"))
      (node (ref "C136") (pin "2") (pinfunction "2_2") (pintype "passive"))
      (node (ref "C137") (pin "2") (pinfunction "2_2") (pintype "passive"))
      (node (ref "C138") (pin "2") (pinfunction "2_2") (pintype "passive"))
      (node (ref "C139") (pin "2") (pinfunction "2_2") (pintype "passive"))
      (node (ref "C14") (pin "2") (pinfunction "2_2") (pintype "passive"))
      (node (ref "C140") (pin "2") (pinfunction "2_2") (pintype "passive"))
      (node (ref "C141") (pin "2") (pinfunction "2_2") (pintype "passive"))
      (node (ref "C142") (pin "2") (pinfunction "2_2") (pintype "passive"))
      (node (ref "C143") (pin "2") (pinfunction "2_2") (pintype "passive"))
      (node (ref "C144") (pin "2") (pinfunction "2_2") (pintype "passive"))
      (node (ref "C145") (pin "2") (pinfunction "2_2") (pintype "passive"))
      (node (ref "C146") (pin "2") (pinfunction "2_2") (pintype "passive"))
      (node (ref "C147") (pin "2") (pinfunction "2_2") (pintype "passive"))
      (node (ref "C148") (pin "2") (pinfunction "2_2") (pintype "passive"))
      (node (ref "C149") (pin "2") (pinfunction "2_2") (pintype "passive"))
      (node (ref "C150") (pin "2") (pinfunction "2_2") (pintype "passive"))
      (node (ref "C151") (pin "2") (pinfunction "2_2") (pintype "passive"))
      (node (ref "C152") (pin "2") (pinfunction "2_2") (pintype "passive"))
      (node (ref "C153") (pin "2") (pinfunction "2_2") (pintype "passive"))
      (node (ref "C154") (pin "2") (pinfunction "2_2") (pintype "passive"))
      (node (ref "C155") (pin "2") (pinfunction "2_2") (pintype "passive"))
      (node (ref "C156") (pin "2") (pinfunction "2_2") (pintype "passive"))
      (node (ref "C157") (pin "2") (pinfunction "2_2") (pintype "passive"))
      (node (ref "C158") (pin "2") (pinfunction "2_2") (pintype "passive"))
      (node (ref "C159") (pin "2") (pinfunction "2_2") (pintype "passive"))
      (node (ref "C16") (pin "2") (pinfunction "2_2") (pintype "passive"))
      (node (ref "C162") (pin "2") (pinfunction "2_2") (pintype "passive"))
      (node (ref "C164") (pin "2") (pinfunction "2_2") (pintype "passive"))
      (node (ref "C165") (pin "2") (pinfunction "2_2") (pintype "passive"))
      (node (ref "C166") (pin "2") (pinfunction "2_2") (pintype "passive"))
      (node (ref "C167") (pin "2") (pinfunction "2_2") (pintype "passive"))
      (node (ref "C168") (pin "2") (pinfunction "2_2") (pintype "passive"))
      (node (ref "C169") (pin "2") (pinfunction "2_2") (pintype "passive"))
      (node (ref "C17") (pin "2") (pinfunction "2_2") (pintype "passive"))
      (node (ref "C170") (pin "2") (pinfunction "2_2") (pintype "passive"))
      (node (ref "C171") (pin "2") (pinfunction "2_2") (pintype "passive"))
      (node (ref "C172") (pin "2") (pinfunction "2_2") (pintype "passive"))
      (node (ref "C173") (pin "2") (pinfunction "2_2") (pintype "passive"))
      (node (ref "C174") (pin "2") (pinfunction "2_2") (pintype "passive"))
      (node (ref "C175") (pin "2") (pinfunction "2_2") (pintype "passive"))
      (node (ref "C176") (pin "2") (pinfunction "2_2") (pintype "passive"))
      (node (ref "C177") (pin "2") (pinfunction "2_2") (pintype "passive"))
      (node (ref "C178") (pin "2") (pinfunction "2_2") (pintype "passive"))
      (node (ref "C179") (pin "2") (pinfunction "2_2") (pintype "passive"))
      (node (ref "C18") (pin "2") (pinfunction "2_2") (pintype "passive"))
      (node (ref "C180") (pin "2") (pinfunction "2_2") (pintype "passive"))
      (node (ref "C181") (pin "2") (pinfunction "2_2") (pintype "passive"))
      (node (ref "C182") (pin "2") (pinfunction "2_2") (pintype "passive"))
      (node (ref "C183") (pin "2") (pinfunction "2_2") (pintype "passive"))
      (node (ref "C184") (pin "2") (pinfunction "2_2") (pintype "passive"))
      (node (ref "C185") (pin "2") (pinfunction "2_2") (pintype "passive"))
      (node (ref "C186") (pin "2") (pinfunction "2_2") (pintype "passive"))
      (node (ref "C187") (pin "2") (pinfunction "2_2") (pintype "passive"))
      (node (ref "C188") (pin "2") (pinfunction "2_2") (pintype "passive"))
      (node (ref "C189") (pin "2") (pinfunction "2_2") (pintype "passive"))
      (node (ref "C19") (pin "2") (pinfunction "2_2") (pintype "passive"))
      (node (ref "C190") (pin "2") (pinfunction "2_2") (pintype "passive"))
      (node (ref "C191") (pin "2") (pinfunction "2_2") (pintype "passive"))
      (node (ref "C192") (pin "2") (pinfunction "2_2") (pintype "passive"))
      (node (ref "C193") (pin "2") (pinfunction "2_2") (pintype "passive"))
      (node (ref "C194") (pin "2") (pinfunction "2_2") (pintype "passive"))
      (node (ref "C195") (pin "2") (pinfunction "2_2") (pintype "passive"))
      (node (ref "C196") (pin "2") (pinfunction "2_2") (pintype "passive"))
      (node (ref "C197") (pin "2") (pinfunction "2_2") (pintype "passive"))
      (node (ref "C198") (pin "2") (pinfunction "2_2") (pintype "passive"))
      (node (ref "C199") (pin "2") (pinfunction "2_2") (pintype "passive"))
      (node (ref "C2") (pin "2") (pinfunction "2_2") (pintype "passive"))
      (node (ref "C20") (pin "2") (pinfunction "2_2") (pintype "passive"))
      (node (ref "C200") (pin "2") (pinfunction "2_2") (pintype "passive"))
      (node (ref "C201") (pin "2") (pinfunction "2_2") (pintype "passive"))
      (node (ref "C202") (pin "2") (pinfunction "2_2") (pintype "passive"))
      (node (ref "C203") (pin "2") (pinfunction "2_2") (pintype "passive"))
      (node (ref "C204") (pin "2") (pinfunction "2_2") (pintype "passive"))
      (node (ref "C205") (pin "2") (pinfunction "2_2") (pintype "passive"))
      (node (ref "C206") (pin "2") (pinfunction "2_2") (pintype "passive"))
      (node (ref "C207") (pin "2") (pinfunction "2_2") (pintype "passive"))
      (node (ref "C208") (pin "2") (pinfunction "2_2") (pintype "passive"))
      (node (ref "C209") (pin "2") (pinfunction "2_2") (pintype "passive"))
      (node (ref "C21") (pin "2") (pinfunction "2_2") (pintype "passive"))
      (node (ref "C210") (pin "2") (pinfunction "2_2") (pintype "passive"))
      (node (ref "C211") (pin "2") (pinfunction "2_2") (pintype "passive"))
      (node (ref "C212") (pin "2") (pinfunction "2_2") (pintype "passive"))
      (node (ref "C213") (pin "2") (pinfunction "2_2") (pintype "passive"))
      (node (ref "C214") (pin "2") (pinfunction "2_2") (pintype "passive"))
      (node (ref "C215") (pin "2") (pinfunction "2_2") (pintype "passive"))
      (node (ref "C216") (pin "2") (pinfunction "2_2") (pintype "passive"))
      (node (ref "C217") (pin "2") (pinfunction "2_2") (pintype "passive"))
      (node (ref "C218") (pin "2") (pinfunction "2_2") (pintype "passive"))
      (node (ref "C219") (pin "2") (pinfunction "2_2") (pintype "passive"))
      (node (ref "C22") (pin "2") (pinfunction "2_2") (pintype "passive"))
      (node (ref "C220") (pin "2") (pinfunction "2_2") (pintype "passive"))
      (node (ref "C221") (pin "2") (pinfunction "2_2") (pintype "passive"))
      (node (ref "C222") (pin "2") (pinfunction "2_2") (pintype "passive"))
      (node (ref "C223") (pin "2") (pinfunction "2_2") (pintype "passive"))
      (node (ref "C224") (pin "2") (pinfunction "2_2") (pintype "passive"))
      (node (ref "C225") (pin "2") (pinfunction "2_2") (pintype "passive"))
      (node (ref "C226") (pin "2") (pinfunction "2_2") (pintype "passive"))
      (node (ref "C227") (pin "2") (pinfunction "2_2") (pintype "passive"))
      (node (ref "C228") (pin "2") (pinfunction "2_2") (pintype "passive"))
      (node (ref "C229") (pin "2") (pinfunction "2_2") (pintype "passive"))
      (node (ref "C23") (pin "2") (pinfunction "2_2") (pintype "passive"))
      (node (ref "C230") (pin "2") (pinfunction "2_2") (pintype "passive"))
      (node (ref "C231") (pin "2") (pinfunction "2_2") (pintype "passive"))
      (node (ref "C232") (pin "2") (pinfunction "2_2") (pintype "passive"))
      (node (ref "C233") (pin "2") (pinfunction "2_2") (pintype "passive"))
      (node (ref "C234") (pin "2") (pinfunction "2_2") (pintype "passive"))
      (node (ref "C235") (pin "2") (pinfunction "2_2") (pintype "passive"))
      (node (ref "C236") (pin "2") (pinfunction "2_2") (pintype "passive"))
      (node (ref "C237") (pin "2") (pinfunction "2_2") (pintype "passive"))
      (node (ref "C238") (pin "2") (pinfunction "2_2") (pintype "passive"))
      (node (ref "C239") (pin "2") (pinfunction "2_2") (pintype "passive"))
      (node (ref "C24") (pin "2") (pinfunction "2_2") (pintype "passive"))
      (node (ref "C240") (pin "2") (pinfunction "2_2") (pintype "passive"))
      (node (ref "C241") (pin "2") (pinfunction "2_2") (pintype "passive"))
      (node (ref "C242") (pin "2") (pinfunction "2_2") (pintype "passive"))
      (node (ref "C243") (pin "2") (pinfunction "2_2") (pintype "passive"))
      (node (ref "C244") (pin "2") (pinfunction "2_2") (pintype "passive"))
      (node (ref "C245") (pin "2") (pinfunction "2_2") (pintype "passive"))
      (node (ref "C246") (pin "2") (pinfunction "2_2") (pintype "passive"))
      (node (ref "C247") (pin "2") (pinfunction "2_2") (pintype "passive"))
      (node (ref "C248") (pin "2") (pinfunction "2_2") (pintype "passive"))
      (node (ref "C249") (pin "2") (pinfunction "2_2") (pintype "passive"))
      (node (ref "C25") (pin "2") (pinfunction "2_2") (pintype "passive"))
      (node (ref "C250") (pin "2") (pinfunction "2_2") (pintype "passive"))
      (node (ref "C251") (pin "2") (pinfunction "2_2") (pintype "passive"))
      (node (ref "C252") (pin "2") (pinfunction "2_2") (pintype "passive"))
      (node (ref "C253") (pin "2") (pinfunction "2_2") (pintype "passive"))
      (node (ref "C254") (pin "2") (pinfunction "2_2") (pintype "passive"))
      (node (ref "C255") (pin "2") (pinfunction "2_2") (pintype "passive"))
      (node (ref "C256") (pin "2") (pinfunction "2_2") (pintype "passive"))
      (node (ref "C257") (pin "2") (pinfunction "2_2") (pintype "passive"))
      (node (ref "C258") (pin "2") (pinfunction "2_2") (pintype "passive"))
      (node (ref "C259") (pin "2") (pinfunction "2_2") (pintype "passive"))
      (node (ref "C26") (pin "2") (pinfunction "2_2") (pintype "passive"))
      (node (ref "C260") (pin "2") (pinfunction "2_2") (pintype "passive"))
      (node (ref "C261") (pin "2") (pinfunction "2_2") (pintype "passive"))
      (node (ref "C262") (pin "2") (pinfunction "2_2") (pintype "passive"))
      (node (ref "C263") (pin "2") (pinfunction "2_2") (pintype "passive"))
      (node (ref "C264") (pin "2") (pinfunction "2_2") (pintype "passive"))
      (node (ref "C265") (pin "2") (pinfunction "2_2") (pintype "passive"))
      (node (ref "C266") (pin "2") (pinfunction "2_2") (pintype "passive"))
      (node (ref "C27") (pin "2") (pinfunction "2_2") (pintype "passive"))
      (node (ref "C270") (pin "2") (pinfunction "2_2") (pintype "passive"))
      (node (ref "C272") (pin "2") (pinfunction "2_2") (pintype "passive"))
      (node (ref "C28") (pin "2") (pinfunction "2_2") (pintype "passive"))
      (node (ref "C280") (pin "2") (pinfunction "2_2") (pintype "passive"))
      (node (ref "C281") (pin "2") (pinfunction "2_2") (pintype "passive"))
      (node (ref "C282") (pin "2") (pinfunction "2_2") (pintype "passive"))
      (node (ref "C283") (pin "2") (pinfunction "2_2") (pintype "passive"))
      (node (ref "C284") (pin "2") (pinfunction "2_2") (pintype "passive"))
      (node (ref "C285") (pin "2") (pinfunction "2_2") (pintype "passive"))
      (node (ref "C286") (pin "2") (pinfunction "2_2") (pintype "passive"))
      (node (ref "C287") (pin "2") (pinfunction "2_2") (pintype "passive"))
      (node (ref "C288") (pin "2") (pinfunction "2_2") (pintype "passive"))
      (node (ref "C289") (pin "2") (pinfunction "2_2") (pintype "passive"))
      (node (ref "C29") (pin "2") (pinfunction "2_2") (pintype "passive"))
      (node (ref "C290") (pin "2") (pinfunction "2_2") (pintype "passive"))
      (node (ref "C291") (pin "2") (pinfunction "2_2") (pintype "passive"))
      (node (ref "C292") (pin "2") (pinfunction "2_2") (pintype "passive"))
      (node (ref "C293") (pin "2") (pinfunction "2_2") (pintype "passive"))
      (node (ref "C294") (pin "2") (pinfunction "2_2") (pintype "passive"))
      (node (ref "C295") (pin "2") (pinfunction "2_2") (pintype "passive"))
      (node (ref "C296") (pin "2") (pinfunction "2_2") (pintype "passive"))
      (node (ref "C297") (pin "2") (pinfunction "2_2") (pintype "passive"))
      (node (ref "C298") (pin "2") (pinfunction "2_2") (pintype "passive"))
      (node (ref "C299") (pin "2") (pinfunction "2_2") (pintype "passive"))
      (node (ref "C3") (pin "2") (pinfunction "2_2") (pintype "passive"))
      (node (ref "C30") (pin "2") (pinfunction "2_2") (pintype "passive"))
      (node (ref "C300") (pin "2") (pinfunction "2_2") (pintype "passive"))
      (node (ref "C301") (pin "2") (pinfunction "2_2") (pintype "passive"))
      (node (ref "C302") (pin "2") (pinfunction "2_2") (pintype "passive"))
      (node (ref "C303") (pin "2") (pinfunction "2_2") (pintype "passive"))
      (node (ref "C304") (pin "2") (pinfunction "2_2") (pintype "passive"))
      (node (ref "C305") (pin "2") (pinfunction "2_2") (pintype "passive"))
      (node (ref "C306") (pin "2") (pinfunction "2_2") (pintype "passive"))
      (node (ref "C307") (pin "2") (pinfunction "2_2") (pintype "passive"))
      (node (ref "C308") (pin "2") (pinfunction "2_2") (pintype "passive"))
      (node (ref "C309") (pin "2") (pinfunction "2_2") (pintype "passive"))
      (node (ref "C310") (pin "2") (pinfunction "2_2") (pintype "passive"))
      (node (ref "C311") (pin "2") (pinfunction "2_2") (pintype "passive"))
      (node (ref "C312") (pin "2") (pinfunction "2_2") (pintype "passive"))
      (node (ref "C313") (pin "2") (pinfunction "2_2") (pintype "passive"))
      (node (ref "C314") (pin "2") (pinfunction "2_2") (pintype "passive"))
      (node (ref "C315") (pin "2") (pinfunction "2_2") (pintype "passive"))
      (node (ref "C316") (pin "2") (pinfunction "2_2") (pintype "passive"))
      (node (ref "C317") (pin "2") (pinfunction "2_2") (pintype "passive"))
      (node (ref "C318") (pin "2") (pinfunction "2_2") (pintype "passive"))
      (node (ref "C319") (pin "2") (pinfunction "2_2") (pintype "passive"))
      (node (ref "C32") (pin "2") (pinfunction "2_2") (pintype "passive"))
      (node (ref "C320") (pin "2") (pinfunction "2_2") (pintype "passive"))
      (node (ref "C321") (pin "2") (pinfunction "2_2") (pintype "passive"))
      (node (ref "C322") (pin "2") (pinfunction "2_2") (pintype "passive"))
      (node (ref "C323") (pin "2") (pinfunction "2_2") (pintype "passive"))
      (node (ref "C324") (pin "2") (pinfunction "2_2") (pintype "passive"))
      (node (ref "C325") (pin "2") (pinfunction "2_2") (pintype "passive"))
      (node (ref "C326") (pin "2") (pinfunction "2_2") (pintype "passive"))
      (node (ref "C327") (pin "2") (pinfunction "2_2") (pintype "passive"))
      (node (ref "C328") (pin "2") (pinfunction "2_2") (pintype "passive"))
      (node (ref "C329") (pin "2") (pinfunction "2_2") (pintype "passive"))
      (node (ref "C33") (pin "2") (pinfunction "2_2") (pintype "passive"))
      (node (ref "C330") (pin "2") (pinfunction "2_2") (pintype "passive"))
      (node (ref "C331") (pin "2") (pinfunction "2_2") (pintype "passive"))
      (node (ref "C332") (pin "2") (pinfunction "2_2") (pintype "passive"))
      (node (ref "C34") (pin "2") (pinfunction "2_2") (pintype "passive"))
      (node (ref "C35") (pin "2") (pinfunction "2_2") (pintype "passive"))
      (node (ref "C36") (pin "2") (pinfunction "2_2") (pintype "passive"))
      (node (ref "C37") (pin "2") (pinfunction "2_2") (pintype "passive"))
      (node (ref "C38") (pin "2") (pinfunction "2_2") (pintype "passive"))
      (node (ref "C39") (pin "2") (pinfunction "2_2") (pintype "passive"))
      (node (ref "C4") (pin "2") (pinfunction "2_2") (pintype "passive"))
      (node (ref "C40") (pin "2") (pinfunction "2_2") (pintype "passive"))
      (node (ref "C41") (pin "2") (pinfunction "2_2") (pintype "passive"))
      (node (ref "C42") (pin "2") (pinfunction "2_2") (pintype "passive"))
      (node (ref "C43") (pin "2") (pinfunction "2_2") (pintype "passive"))
      (node (ref "C44") (pin "2") (pinfunction "2_2") (pintype "passive"))
      (node (ref "C45") (pin "2") (pinfunction "2_2") (pintype "passive"))
      (node (ref "C46") (pin "2") (pinfunction "2_2") (pintype "passive"))
      (node (ref "C47") (pin "2") (pinfunction "2_2") (pintype "passive"))
      (node (ref "C48") (pin "2") (pinfunction "2_2") (pintype "passive"))
      (node (ref "C49") (pin "2") (pinfunction "2_2") (pintype "passive"))
      (node (ref "C5") (pin "2") (pinfunction "2_2") (pintype "passive"))
      (node (ref "C50") (pin "2") (pinfunction "2_2") (pintype "passive"))
      (node (ref "C51") (pin "2") (pinfunction "2_2") (pintype "passive"))
      (node (ref "C52") (pin "2") (pinfunction "2_2") (pintype "passive"))
      (node (ref "C53") (pin "2") (pinfunction "2_2") (pintype "passive"))
      (node (ref "C54") (pin "2") (pinfunction "2_2") (pintype "passive"))
      (node (ref "C55") (pin "2") (pinfunction "2_2") (pintype "passive"))
      (node (ref "C56") (pin "2") (pinfunction "2_2") (pintype "passive"))
      (node (ref "C57") (pin "2") (pinfunction "2_2") (pintype "passive"))
      (node (ref "C58") (pin "2") (pinfunction "2_2") (pintype "passive"))
      (node (ref "C59") (pin "2") (pinfunction "2_2") (pintype "passive"))
      (node (ref "C6") (pin "2") (pinfunction "2_2") (pintype "passive"))
      (node (ref "C7") (pin "2") (pinfunction "2_2") (pintype "passive"))
      (node (ref "C78") (pin "2") (pinfunction "2_2") (pintype "passive"))
      (node (ref "C8") (pin "2") (pinfunction "2_2") (pintype "passive"))
      (node (ref "C9") (pin "2") (pinfunction "2_2") (pintype "passive"))
      (node (ref "D100") (pin "5") (pinfunction "P$1_5") (pintype "passive"))
      (node (ref "D101") (pin "5") (pinfunction "P$1_5") (pintype "passive"))
      (node (ref "D102") (pin "5") (pinfunction "P$1_5") (pintype "passive"))
      (node (ref "D103") (pin "5") (pinfunction "P$1_5") (pintype "passive"))
      (node (ref "D104") (pin "5") (pinfunction "P$1_5") (pintype "passive"))
      (node (ref "D105") (pin "5") (pinfunction "P$1_5") (pintype "passive"))
      (node (ref "D106") (pin "5") (pinfunction "P$1_5") (pintype "passive"))
      (node (ref "D107") (pin "5") (pinfunction "P$1_5") (pintype "passive"))
      (node (ref "D108") (pin "5") (pinfunction "P$1_5") (pintype "passive"))
      (node (ref "D109") (pin "5") (pinfunction "P$1_5") (pintype "passive"))
      (node (ref "D110") (pin "5") (pinfunction "P$1_5") (pintype "passive"))
      (node (ref "D111") (pin "5") (pinfunction "P$1_5") (pintype "passive"))
      (node (ref "D112") (pin "5") (pinfunction "P$1_5") (pintype "passive"))
      (node (ref "D200") (pin "NC") (pinfunction "P$1_NC") (pintype "passive"))
      (node (ref "D201") (pin "NC") (pinfunction "P$1_NC") (pintype "passive"))
      (node (ref "D202") (pin "NC") (pinfunction "P$1_NC") (pintype "passive"))
      (node (ref "D203") (pin "NC") (pinfunction "P$1_NC") (pintype "passive"))
      (node (ref "D204") (pin "NC") (pinfunction "P$1_NC") (pintype "passive"))
      (node (ref "D205") (pin "NC") (pinfunction "P$1_NC") (pintype "passive"))
      (node (ref "D206") (pin "NC") (pinfunction "P$1_NC") (pintype "passive"))
      (node (ref "D207") (pin "NC") (pinfunction "P$1_NC") (pintype "passive"))
      (node (ref "D208") (pin "NC") (pinfunction "P$1_NC") (pintype "passive"))
      (node (ref "D209") (pin "NC") (pinfunction "P$1_NC") (pintype "passive"))
      (node (ref "D210") (pin "NC") (pinfunction "P$1_NC") (pintype "passive"))
      (node (ref "D211") (pin "NC") (pinfunction "P$1_NC") (pintype "passive"))
      (node (ref "D212") (pin "NC") (pinfunction "P$1_NC") (pintype "passive"))
      (node (ref "D213") (pin "NC") (pinfunction "P$1_NC") (pintype "passive"))
      (node (ref "D214") (pin "NC") (pinfunction "P$1_NC") (pintype "passive"))
      (node (ref "D215") (pin "NC") (pinfunction "P$1_NC") (pintype "passive"))
      (node (ref "D250") (pin "NC") (pinfunction "P$1_NC") (pintype "passive"))
      (node (ref "D251") (pin "NC") (pinfunction "P$1_NC") (pintype "passive"))
      (node (ref "D252") (pin "NC") (pinfunction "P$1_NC") (pintype "passive"))
      (node (ref "D253") (pin "NC") (pinfunction "P$1_NC") (pintype "passive"))
      (node (ref "D254") (pin "NC") (pinfunction "P$1_NC") (pintype "passive"))
      (node (ref "D255") (pin "NC") (pinfunction "P$1_NC") (pintype "passive"))
      (node (ref "D256") (pin "NC") (pinfunction "P$1_NC") (pintype "passive"))
      (node (ref "D257") (pin "NC") (pinfunction "P$1_NC") (pintype "passive"))
      (node (ref "D258") (pin "NC") (pinfunction "P$1_NC") (pintype "passive"))
      (node (ref "D259") (pin "NC") (pinfunction "P$1_NC") (pintype "passive"))
      (node (ref "D260") (pin "NC") (pinfunction "P$1_NC") (pintype "passive"))
      (node (ref "D261") (pin "NC") (pinfunction "P$1_NC") (pintype "passive"))
      (node (ref "D262") (pin "NC") (pinfunction "P$1_NC") (pintype "passive"))
      (node (ref "D263") (pin "NC") (pinfunction "P$1_NC") (pintype "passive"))
      (node (ref "D264") (pin "NC") (pinfunction "P$1_NC") (pintype "passive"))
      (node (ref "D265") (pin "NC") (pinfunction "P$1_NC") (pintype "passive"))
      (node (ref "D300") (pin "NC") (pinfunction "P$1_NC") (pintype "passive"))
      (node (ref "D301") (pin "NC") (pinfunction "P$1_NC") (pintype "passive"))
      (node (ref "D302") (pin "NC") (pinfunction "P$1_NC") (pintype "passive"))
      (node (ref "D303") (pin "NC") (pinfunction "P$1_NC") (pintype "passive"))
      (node (ref "D304") (pin "NC") (pinfunction "P$1_NC") (pintype "passive"))
      (node (ref "D305") (pin "NC") (pinfunction "P$1_NC") (pintype "passive"))
      (node (ref "D306") (pin "NC") (pinfunction "P$1_NC") (pintype "passive"))
      (node (ref "D307") (pin "NC") (pinfunction "P$1_NC") (pintype "passive"))
      (node (ref "D308") (pin "NC") (pinfunction "P$1_NC") (pintype "passive"))
      (node (ref "D309") (pin "NC") (pinfunction "P$1_NC") (pintype "passive"))
      (node (ref "D310") (pin "NC") (pinfunction "P$1_NC") (pintype "passive"))
      (node (ref "D311") (pin "NC") (pinfunction "P$1_NC") (pintype "passive"))
      (node (ref "D312") (pin "NC") (pinfunction "P$1_NC") (pintype "passive"))
      (node (ref "D313") (pin "NC") (pinfunction "P$1_NC") (pintype "passive"))
      (node (ref "D314") (pin "NC") (pinfunction "P$1_NC") (pintype "passive"))
      (node (ref "D315") (pin "NC") (pinfunction "P$1_NC") (pintype "passive"))
      (node (ref "D350") (pin "NC") (pinfunction "P$1_NC") (pintype "passive"))
      (node (ref "D351") (pin "NC") (pinfunction "P$1_NC") (pintype "passive"))
      (node (ref "D352") (pin "NC") (pinfunction "P$1_NC") (pintype "passive"))
      (node (ref "D353") (pin "NC") (pinfunction "P$1_NC") (pintype "passive"))
      (node (ref "D354") (pin "NC") (pinfunction "P$1_NC") (pintype "passive"))
      (node (ref "D355") (pin "NC") (pinfunction "P$1_NC") (pintype "passive"))
      (node (ref "D356") (pin "NC") (pinfunction "P$1_NC") (pintype "passive"))
      (node (ref "D357") (pin "NC") (pinfunction "P$1_NC") (pintype "passive"))
      (node (ref "D358") (pin "NC") (pinfunction "P$1_NC") (pintype "passive"))
      (node (ref "D359") (pin "NC") (pinfunction "P$1_NC") (pintype "passive"))
      (node (ref "D360") (pin "NC") (pinfunction "P$1_NC") (pintype "passive"))
      (node (ref "D361") (pin "NC") (pinfunction "P$1_NC") (pintype "passive"))
      (node (ref "D362") (pin "NC") (pinfunction "P$1_NC") (pintype "passive"))
      (node (ref "D363") (pin "NC") (pinfunction "P$1_NC") (pintype "passive"))
      (node (ref "D364") (pin "NC") (pinfunction "P$1_NC") (pintype "passive"))
      (node (ref "D365") (pin "NC") (pinfunction "P$1_NC") (pintype "passive"))
      (node (ref "IC1") (pin "2") (pinfunction "GND_2") (pintype "input"))
      (node (ref "IC10") (pin "2") (pinfunction "GND_2") (pintype "input"))
      (node (ref "IC100") (pin "4") (pinfunction "VSS_4") (pintype "input"))
      (node (ref "IC101") (pin "4") (pinfunction "VSS_4") (pintype "input"))
      (node (ref "IC102") (pin "4") (pinfunction "VSS_4") (pintype "input"))
      (node (ref "IC103") (pin "4") (pinfunction "VSS_4") (pintype "input"))
      (node (ref "IC104") (pin "4") (pinfunction "VSS_4") (pintype "input"))
      (node (ref "IC105") (pin "4") (pinfunction "VSS_4") (pintype "input"))
      (node (ref "IC106") (pin "4") (pinfunction "VSS_4") (pintype "input"))
      (node (ref "IC107") (pin "4") (pinfunction "VSS_4") (pintype "input"))
      (node (ref "IC108") (pin "4") (pinfunction "VSS_4") (pintype "input"))
      (node (ref "IC109") (pin "4") (pinfunction "VSS_4") (pintype "input"))
      (node (ref "IC11") (pin "4") (pinfunction "GND_4") (pintype "input"))
      (node (ref "IC110") (pin "4") (pinfunction "VSS_4") (pintype "input"))
      (node (ref "IC111") (pin "4") (pinfunction "VSS_4") (pintype "input"))
      (node (ref "IC112") (pin "4") (pinfunction "VSS_4") (pintype "input"))
      (node (ref "IC113") (pin "4") (pinfunction "VSS_4") (pintype "input"))
      (node (ref "IC114") (pin "4") (pinfunction "VSS_4") (pintype "input"))
      (node (ref "IC115") (pin "4") (pinfunction "VSS_4") (pintype "input"))
      (node (ref "IC116") (pin "4") (pinfunction "VSS_4") (pintype "input"))
      (node (ref "IC117") (pin "4") (pinfunction "VSS_4") (pintype "input"))
      (node (ref "IC118") (pin "4") (pinfunction "VSS_4") (pintype "input"))
      (node (ref "IC119") (pin "4") (pinfunction "VSS_4") (pintype "input"))
      (node (ref "IC12") (pin "2") (pinfunction "GND_2") (pintype "input"))
      (node (ref "IC120") (pin "4") (pinfunction "VSS_4") (pintype "input"))
      (node (ref "IC121") (pin "4") (pinfunction "VSS_4") (pintype "input"))
      (node (ref "IC122") (pin "4") (pinfunction "VSS_4") (pintype "input"))
      (node (ref "IC123") (pin "4") (pinfunction "VSS_4") (pintype "input"))
      (node (ref "IC124") (pin "4") (pinfunction "VSS_4") (pintype "input"))
      (node (ref "IC125") (pin "4") (pinfunction "VSS_4") (pintype "input"))
      (node (ref "IC126") (pin "4") (pinfunction "VSS_4") (pintype "input"))
      (node (ref "IC127") (pin "4") (pinfunction "VSS_4") (pintype "input"))
      (node (ref "IC128") (pin "4") (pinfunction "VSS_4") (pintype "input"))
      (node (ref "IC129") (pin "4") (pinfunction "VSS_4") (pintype "input"))
      (node (ref "IC13") (pin "2") (pinfunction "GND_2") (pintype "input"))
      (node (ref "IC130") (pin "4") (pinfunction "VSS_4") (pintype "input"))
      (node (ref "IC131") (pin "4") (pinfunction "VSS_4") (pintype "input"))
      (node (ref "IC132") (pin "4") (pinfunction "VSS_4") (pintype "input"))
      (node (ref "IC133") (pin "4") (pinfunction "VSS_4") (pintype "input"))
      (node (ref "IC134") (pin "4") (pinfunction "VSS_4") (pintype "input"))
      (node (ref "IC135") (pin "4") (pinfunction "VSS_4") (pintype "input"))
      (node (ref "IC136") (pin "4") (pinfunction "VSS_4") (pintype "input"))
      (node (ref "IC137") (pin "4") (pinfunction "VSS_4") (pintype "input"))
      (node (ref "IC138") (pin "4") (pinfunction "VSS_4") (pintype "input"))
      (node (ref "IC139") (pin "4") (pinfunction "VSS_4") (pintype "input"))
      (node (ref "IC14") (pin "2") (pinfunction "GND_2") (pintype "input"))
      (node (ref "IC140") (pin "4") (pinfunction "VSS_4") (pintype "input"))
      (node (ref "IC141") (pin "4") (pinfunction "VSS_4") (pintype "input"))
      (node (ref "IC142") (pin "4") (pinfunction "VSS_4") (pintype "input"))
      (node (ref "IC143") (pin "4") (pinfunction "VSS_4") (pintype "input"))
      (node (ref "IC144") (pin "4") (pinfunction "VSS_4") (pintype "input"))
      (node (ref "IC145") (pin "4") (pinfunction "VSS_4") (pintype "input"))
      (node (ref "IC146") (pin "4") (pinfunction "VSS_4") (pintype "input"))
      (node (ref "IC147") (pin "4") (pinfunction "VSS_4") (pintype "input"))
      (node (ref "IC148") (pin "4") (pinfunction "VSS_4") (pintype "input"))
      (node (ref "IC149") (pin "4") (pinfunction "VSS_4") (pintype "input"))
      (node (ref "IC15") (pin "4") (pinfunction "GND_4") (pintype "input"))
      (node (ref "IC15") (pin "5") (pinfunction "A2_5") (pintype "input"))
      (node (ref "IC15") (pin "6") (pinfunction "A1_6") (pintype "input"))
      (node (ref "IC15") (pin "7") (pinfunction "A0_7") (pintype "input"))
      (node (ref "IC150") (pin "4") (pinfunction "VSS_4") (pintype "input"))
      (node (ref "IC151") (pin "4") (pinfunction "VSS_4") (pintype "input"))
      (node (ref "IC152") (pin "4") (pinfunction "VSS_4") (pintype "input"))
      (node (ref "IC153") (pin "4") (pinfunction "VSS_4") (pintype "input"))
      (node (ref "IC154") (pin "4") (pinfunction "VSS_4") (pintype "input"))
      (node (ref "IC155") (pin "4") (pinfunction "VSS_4") (pintype "input"))
      (node (ref "IC156") (pin "4") (pinfunction "VSS_4") (pintype "input"))
      (node (ref "IC157") (pin "4") (pinfunction "VSS_4") (pintype "input"))
      (node (ref "IC158") (pin "4") (pinfunction "VSS_4") (pintype "input"))
      (node (ref "IC159") (pin "4") (pinfunction "VSS_4") (pintype "input"))
      (node (ref "IC16") (pin "2") (pinfunction "GND_2") (pintype "input"))
      (node (ref "IC160") (pin "4") (pinfunction "VSS_4") (pintype "input"))
      (node (ref "IC161") (pin "4") (pinfunction "VSS_4") (pintype "input"))
      (node (ref "IC162") (pin "4") (pinfunction "VSS_4") (pintype "input"))
      (node (ref "IC163") (pin "4") (pinfunction "VSS_4") (pintype "input"))
      (node (ref "IC164") (pin "4") (pinfunction "VSS_4") (pintype "input"))
      (node (ref "IC165") (pin "4") (pinfunction "VSS_4") (pintype "input"))
      (node (ref "IC166") (pin "4") (pinfunction "VSS_4") (pintype "input"))
      (node (ref "IC167") (pin "4") (pinfunction "VSS_4") (pintype "input"))
      (node (ref "IC168") (pin "4") (pinfunction "VSS_4") (pintype "input"))
      (node (ref "IC169") (pin "4") (pinfunction "VSS_4") (pintype "input"))
      (node (ref "IC17") (pin "2") (pinfunction "GND_2") (pintype "input"))
      (node (ref "IC170") (pin "4") (pinfunction "VSS_4") (pintype "input"))
      (node (ref "IC171") (pin "4") (pinfunction "VSS_4") (pintype "input"))
      (node (ref "IC172") (pin "4") (pinfunction "VSS_4") (pintype "input"))
      (node (ref "IC173") (pin "4") (pinfunction "VSS_4") (pintype "input"))
      (node (ref "IC174") (pin "4") (pinfunction "VSS_4") (pintype "input"))
      (node (ref "IC175") (pin "4") (pinfunction "VSS_4") (pintype "input"))
      (node (ref "IC176") (pin "4") (pinfunction "VSS_4") (pintype "input"))
      (node (ref "IC177") (pin "4") (pinfunction "VSS_4") (pintype "input"))
      (node (ref "IC178") (pin "4") (pinfunction "VSS_4") (pintype "input"))
      (node (ref "IC179") (pin "4") (pinfunction "VSS_4") (pintype "input"))
      (node (ref "IC18") (pin "2") (pinfunction "GND_2") (pintype "input"))
      (node (ref "IC180") (pin "4") (pinfunction "VSS_4") (pintype "input"))
      (node (ref "IC181") (pin "4") (pinfunction "VSS_4") (pintype "input"))
      (node (ref "IC182") (pin "4") (pinfunction "VSS_4") (pintype "input"))
      (node (ref "IC183") (pin "4") (pinfunction "VSS_4") (pintype "input"))
      (node (ref "IC184") (pin "4") (pinfunction "VSS_4") (pintype "input"))
      (node (ref "IC185") (pin "4") (pinfunction "VSS_4") (pintype "input"))
      (node (ref "IC186") (pin "4") (pinfunction "VSS_4") (pintype "input"))
      (node (ref "IC187") (pin "4") (pinfunction "VSS_4") (pintype "input"))
      (node (ref "IC188") (pin "4") (pinfunction "VSS_4") (pintype "input"))
      (node (ref "IC189") (pin "4") (pinfunction "VSS_4") (pintype "input"))
      (node (ref "IC19") (pin "2") (pinfunction "GND_2") (pintype "input"))
      (node (ref "IC190") (pin "4") (pinfunction "VSS_4") (pintype "input"))
      (node (ref "IC191") (pin "4") (pinfunction "VSS_4") (pintype "input"))
      (node (ref "IC192") (pin "4") (pinfunction "VSS_4") (pintype "input"))
      (node (ref "IC193") (pin "4") (pinfunction "VSS_4") (pintype "input"))
      (node (ref "IC194") (pin "4") (pinfunction "VSS_4") (pintype "input"))
      (node (ref "IC195") (pin "4") (pinfunction "VSS_4") (pintype "input"))
      (node (ref "IC196") (pin "4") (pinfunction "VSS_4") (pintype "input"))
      (node (ref "IC197") (pin "4") (pinfunction "VSS_4") (pintype "input"))
      (node (ref "IC198") (pin "4") (pinfunction "VSS_4") (pintype "input"))
      (node (ref "IC199") (pin "4") (pinfunction "VSS_4") (pintype "input"))
      (node (ref "IC2") (pin "2") (pinfunction "GND_2") (pintype "input"))
      (node (ref "IC20") (pin "2") (pinfunction "GND_2") (pintype "input"))
      (node (ref "IC200") (pin "4") (pinfunction "VSS_4") (pintype "input"))
      (node (ref "IC201") (pin "4") (pinfunction "VSS_4") (pintype "input"))
      (node (ref "IC202") (pin "4") (pinfunction "VSS_4") (pintype "input"))
      (node (ref "IC203") (pin "4") (pinfunction "VSS_4") (pintype "input"))
      (node (ref "IC204") (pin "4") (pinfunction "VSS_4") (pintype "input"))
      (node (ref "IC205") (pin "4") (pinfunction "VSS_4") (pintype "input"))
      (node (ref "IC206") (pin "4") (pinfunction "VSS_4") (pintype "input"))
      (node (ref "IC207") (pin "4") (pinfunction "VSS_4") (pintype "input"))
      (node (ref "IC208") (pin "4") (pinfunction "VSS_4") (pintype "input"))
      (node (ref "IC209") (pin "4") (pinfunction "VSS_4") (pintype "input"))
      (node (ref "IC21") (pin "3") (pinfunction "VBUS/GND1_3") (pintype "input"))
      (node (ref "IC21") (pin "6") (pinfunction "GND2_6") (pintype "input"))
      (node (ref "IC21") (pin "MNT1") (pinfunction "MNT1_MNT1") (pintype "passive"))
      (node (ref "IC21") (pin "MNT2") (pinfunction "MNT2_MNT2") (pintype "passive"))
      (node (ref "IC210") (pin "4") (pinfunction "VSS_4") (pintype "input"))
      (node (ref "IC211") (pin "4") (pinfunction "VSS_4") (pintype "input"))
      (node (ref "IC212") (pin "4") (pinfunction "VSS_4") (pintype "input"))
      (node (ref "IC213") (pin "4") (pinfunction "VSS_4") (pintype "input"))
      (node (ref "IC214") (pin "4") (pinfunction "VSS_4") (pintype "input"))
      (node (ref "IC215") (pin "4") (pinfunction "VSS_4") (pintype "input"))
      (node (ref "IC216") (pin "4") (pinfunction "VSS_4") (pintype "input"))
      (node (ref "IC217") (pin "4") (pinfunction "VSS_4") (pintype "input"))
      (node (ref "IC218") (pin "4") (pinfunction "VSS_4") (pintype "input"))
      (node (ref "IC219") (pin "4") (pinfunction "VSS_4") (pintype "input"))
      (node (ref "IC22") (pin "3") (pinfunction "VBUS/GND1_3") (pintype "input"))
      (node (ref "IC22") (pin "6") (pinfunction "GND2_6") (pintype "input"))
      (node (ref "IC22") (pin "MNT1") (pinfunction "MNT1_MNT1") (pintype "passive"))
      (node (ref "IC22") (pin "MNT2") (pinfunction "MNT2_MNT2") (pintype "passive"))
      (node (ref "IC220") (pin "4") (pinfunction "VSS_4") (pintype "input"))
      (node (ref "IC221") (pin "4") (pinfunction "VSS_4") (pintype "input"))
      (node (ref "IC222") (pin "4") (pinfunction "VSS_4") (pintype "input"))
      (node (ref "IC223") (pin "4") (pinfunction "VSS_4") (pintype "input"))
      (node (ref "IC224") (pin "4") (pinfunction "VSS_4") (pintype "input"))
      (node (ref "IC225") (pin "4") (pinfunction "VSS_4") (pintype "input"))
      (node (ref "IC226") (pin "4") (pinfunction "VSS_4") (pintype "input"))
      (node (ref "IC227") (pin "4") (pinfunction "VSS_4") (pintype "input"))
      (node (ref "IC228") (pin "4") (pinfunction "VSS_4") (pintype "input"))
      (node (ref "IC229") (pin "4") (pinfunction "VSS_4") (pintype "input"))
      (node (ref "IC23") (pin "1") (pinfunction "NC_1") (pintype "passive"))
      (node (ref "IC23") (pin "13") (pinfunction "GND_13") (pintype "input"))
      (node (ref "IC23") (pin "14") (pinfunction "A1_14") (pintype "input"))
      (node (ref "IC23") (pin "7") (pinfunction "DB_7") (pintype "passive"))
      (node (ref "IC230") (pin "4") (pinfunction "VSS_4") (pintype "input"))
      (node (ref "IC231") (pin "4") (pinfunction "VSS_4") (pintype "input"))
      (node (ref "IC232") (pin "4") (pinfunction "VSS_4") (pintype "input"))
      (node (ref "IC233") (pin "4") (pinfunction "VSS_4") (pintype "input"))
      (node (ref "IC234") (pin "4") (pinfunction "VSS_4") (pintype "input"))
      (node (ref "IC235") (pin "4") (pinfunction "VSS_4") (pintype "input"))
      (node (ref "IC236") (pin "4") (pinfunction "VSS_4") (pintype "input"))
      (node (ref "IC237") (pin "4") (pinfunction "VSS_4") (pintype "input"))
      (node (ref "IC238") (pin "4") (pinfunction "VSS_4") (pintype "input"))
      (node (ref "IC239") (pin "4") (pinfunction "VSS_4") (pintype "input"))
      (node (ref "IC24") (pin "2") (pinfunction "GND_2") (pintype "input"))
      (node (ref "IC24") (pin "4") (pinfunction "ADD0_4") (pintype "input"))
      (node (ref "IC240") (pin "4") (pinfunction "VSS_4") (pintype "input"))
      (node (ref "IC241") (pin "4") (pinfunction "VSS_4") (pintype "input"))
      (node (ref "IC242") (pin "4") (pinfunction "VSS_4") (pintype "input"))
      (node (ref "IC243") (pin "4") (pinfunction "VSS_4") (pintype "input"))
      (node (ref "IC244") (pin "4") (pinfunction "VSS_4") (pintype "input"))
      (node (ref "IC245") (pin "4") (pinfunction "VSS_4") (pintype "input"))
      (node (ref "IC246") (pin "4") (pinfunction "VSS_4") (pintype "input"))
      (node (ref "IC247") (pin "4") (pinfunction "VSS_4") (pintype "input"))
      (node (ref "IC248") (pin "4") (pinfunction "VSS_4") (pintype "input"))
      (node (ref "IC249") (pin "4") (pinfunction "VSS_4") (pintype "input"))
      (node (ref "IC25") (pin "3") (pinfunction "GND_3") (pintype "input"))
      (node (ref "IC25") (pin "PAD") (pinfunction "GND_PAD") (pintype "input"))
      (node (ref "IC250") (pin "4") (pinfunction "VSS_4") (pintype "input"))
      (node (ref "IC251") (pin "4") (pinfunction "VSS_4") (pintype "input"))
      (node (ref "IC252") (pin "4") (pinfunction "VSS_4") (pintype "input"))
      (node (ref "IC253") (pin "4") (pinfunction "VSS_4") (pintype "input"))
      (node (ref "IC254") (pin "4") (pinfunction "VSS_4") (pintype "input"))
      (node (ref "IC255") (pin "4") (pinfunction "VSS_4") (pintype "input"))
      (node (ref "IC256") (pin "4") (pinfunction "VSS_4") (pintype "input"))
      (node (ref "IC257") (pin "4") (pinfunction "VSS_4") (pintype "input"))
      (node (ref "IC258") (pin "4") (pinfunction "VSS_4") (pintype "input"))
      (node (ref "IC259") (pin "4") (pinfunction "VSS_4") (pintype "input"))
      (node (ref "IC260") (pin "4") (pinfunction "VSS_4") (pintype "input"))
      (node (ref "IC261") (pin "4") (pinfunction "VSS_4") (pintype "input"))
      (node (ref "IC262") (pin "4") (pinfunction "VSS_4") (pintype "input"))
      (node (ref "IC263") (pin "4") (pinfunction "VSS_4") (pintype "input"))
      (node (ref "IC264") (pin "4") (pinfunction "VSS_4") (pintype "input"))
      (node (ref "IC265") (pin "4") (pinfunction "VSS_4") (pintype "input"))
      (node (ref "IC266") (pin "4") (pinfunction "VSS_4") (pintype "input"))
      (node (ref "IC267") (pin "4") (pinfunction "VSS_4") (pintype "input"))
      (node (ref "IC268") (pin "4") (pinfunction "VSS_4") (pintype "input"))
      (node (ref "IC269") (pin "4") (pinfunction "VSS_4") (pintype "input"))
      (node (ref "IC270") (pin "4") (pinfunction "VSS_4") (pintype "input"))
      (node (ref "IC271") (pin "4") (pinfunction "VSS_4") (pintype "input"))
      (node (ref "IC272") (pin "4") (pinfunction "VSS_4") (pintype "input"))
      (node (ref "IC273") (pin "4") (pinfunction "VSS_4") (pintype "input"))
      (node (ref "IC274") (pin "4") (pinfunction "VSS_4") (pintype "input"))
      (node (ref "IC275") (pin "4") (pinfunction "VSS_4") (pintype "input"))
      (node (ref "IC276") (pin "4") (pinfunction "VSS_4") (pintype "input"))
      (node (ref "IC277") (pin "4") (pinfunction "VSS_4") (pintype "input"))
      (node (ref "IC278") (pin "4") (pinfunction "VSS_4") (pintype "input"))
      (node (ref "IC279") (pin "4") (pinfunction "VSS_4") (pintype "input"))
      (node (ref "IC280") (pin "4") (pinfunction "VSS_4") (pintype "input"))
      (node (ref "IC281") (pin "4") (pinfunction "VSS_4") (pintype "input"))
      (node (ref "IC282") (pin "4") (pinfunction "VSS_4") (pintype "input"))
      (node (ref "IC283") (pin "4") (pinfunction "VSS_4") (pintype "input"))
      (node (ref "IC284") (pin "4") (pinfunction "VSS_4") (pintype "input"))
      (node (ref "IC285") (pin "4") (pinfunction "VSS_4") (pintype "input"))
      (node (ref "IC286") (pin "4") (pinfunction "VSS_4") (pintype "input"))
      (node (ref "IC287") (pin "4") (pinfunction "VSS_4") (pintype "input"))
      (node (ref "IC288") (pin "4") (pinfunction "VSS_4") (pintype "input"))
      (node (ref "IC289") (pin "4") (pinfunction "VSS_4") (pintype "input"))
      (node (ref "IC290") (pin "4") (pinfunction "VSS_4") (pintype "input"))
      (node (ref "IC291") (pin "4") (pinfunction "VSS_4") (pintype "input"))
      (node (ref "IC292") (pin "4") (pinfunction "VSS_4") (pintype "input"))
      (node (ref "IC293") (pin "4") (pinfunction "VSS_4") (pintype "input"))
      (node (ref "IC294") (pin "4") (pinfunction "VSS_4") (pintype "input"))
      (node (ref "IC295") (pin "4") (pinfunction "VSS_4") (pintype "input"))
      (node (ref "IC296") (pin "4") (pinfunction "VSS_4") (pintype "input"))
      (node (ref "IC297") (pin "4") (pinfunction "VSS_4") (pintype "input"))
      (node (ref "IC298") (pin "4") (pinfunction "VSS_4") (pintype "input"))
      (node (ref "IC299") (pin "4") (pinfunction "VSS_4") (pintype "input"))
      (node (ref "IC3") (pin "4") (pinfunction "GND_4") (pintype "input"))
      (node (ref "IC3") (pin "PAD") (pinfunction "GND_PAD") (pintype "input"))
      (node (ref "IC300") (pin "4") (pinfunction "VSS_4") (pintype "input"))
      (node (ref "IC301") (pin "4") (pinfunction "VSS_4") (pintype "input"))
      (node (ref "IC302") (pin "4") (pinfunction "VSS_4") (pintype "input"))
      (node (ref "IC303") (pin "4") (pinfunction "VSS_4") (pintype "input"))
      (node (ref "IC304") (pin "4") (pinfunction "VSS_4") (pintype "input"))
      (node (ref "IC305") (pin "4") (pinfunction "VSS_4") (pintype "input"))
      (node (ref "IC306") (pin "4") (pinfunction "VSS_4") (pintype "input"))
      (node (ref "IC307") (pin "4") (pinfunction "VSS_4") (pintype "input"))
      (node (ref "IC308") (pin "4") (pinfunction "VSS_4") (pintype "input"))
      (node (ref "IC309") (pin "4") (pinfunction "VSS_4") (pintype "input"))
      (node (ref "IC310") (pin "4") (pinfunction "VSS_4") (pintype "input"))
      (node (ref "IC311") (pin "4") (pinfunction "VSS_4") (pintype "input"))
      (node (ref "IC312") (pin "4") (pinfunction "VSS_4") (pintype "input"))
      (node (ref "IC313") (pin "4") (pinfunction "VSS_4") (pintype "input"))
      (node (ref "IC314") (pin "4") (pinfunction "VSS_4") (pintype "input"))
      (node (ref "IC315") (pin "4") (pinfunction "VSS_4") (pintype "input"))
      (node (ref "IC316") (pin "4") (pinfunction "VSS_4") (pintype "input"))
      (node (ref "IC317") (pin "4") (pinfunction "VSS_4") (pintype "input"))
      (node (ref "IC318") (pin "4") (pinfunction "VSS_4") (pintype "input"))
      (node (ref "IC319") (pin "4") (pinfunction "VSS_4") (pintype "input"))
      (node (ref "IC320") (pin "4") (pinfunction "VSS_4") (pintype "input"))
      (node (ref "IC321") (pin "4") (pinfunction "VSS_4") (pintype "input"))
      (node (ref "IC322") (pin "4") (pinfunction "VSS_4") (pintype "input"))
      (node (ref "IC323") (pin "4") (pinfunction "VSS_4") (pintype "input"))
      (node (ref "IC324") (pin "4") (pinfunction "VSS_4") (pintype "input"))
      (node (ref "IC325") (pin "4") (pinfunction "VSS_4") (pintype "input"))
      (node (ref "IC326") (pin "4") (pinfunction "VSS_4") (pintype "input"))
      (node (ref "IC327") (pin "4") (pinfunction "VSS_4") (pintype "input"))
      (node (ref "IC328") (pin "4") (pinfunction "VSS_4") (pintype "input"))
      (node (ref "IC329") (pin "4") (pinfunction "VSS_4") (pintype "input"))
      (node (ref "IC330") (pin "4") (pinfunction "VSS_4") (pintype "input"))
      (node (ref "IC331") (pin "4") (pinfunction "VSS_4") (pintype "input"))
      (node (ref "IC332") (pin "4") (pinfunction "VSS_4") (pintype "input"))
      (node (ref "IC4") (pin "4") (pinfunction "GND_4") (pintype "input"))
      (node (ref "IC4") (pin "6") (pinfunction "-IN_6") (pintype "input"))
      (node (ref "IC4") (pin "PAD") (pinfunction "GND_PAD") (pintype "input"))
      (node (ref "IC5") (pin "4") (pinfunction "GND_4") (pintype "input"))
      (node (ref "IC5") (pin "6") (pinfunction "-IN_6") (pintype "input"))
      (node (ref "IC5") (pin "PAD") (pinfunction "GND_PAD") (pintype "input"))
      (node (ref "IC6") (pin "2") (pinfunction "1_2") (pintype "passive"))
      (node (ref "IC6") (pin "3") (pinfunction "E_3") (pintype "passive"))
      (node (ref "IC6") (pin "5") (pinfunction "1_5") (pintype "passive"))
      (node (ref "IC6") (pin "6") (pinfunction "C_6") (pintype "passive"))
      (node (ref "IC7") (pin "12") (pinfunction "GND_12") (pintype "input"))
      (node (ref "IC7") (pin "2") (pinfunction "AVSSVCSEL_2") (pintype "input"))
      (node (ref "IC7") (pin "3") (pinfunction "GND_3") (pintype "input"))
      (node (ref "IC7") (pin "4") (pinfunction "GND_4") (pintype "input"))
      (node (ref "IC7") (pin "6") (pinfunction "GND_6") (pintype "input"))
      (node (ref "IC8") (pin "2") (pinfunction "GND_2") (pintype "input"))
      (node (ref "IC9") (pin "1") (pinfunction "CLK_1") (pintype "input"))
      (node (ref "IC9") (pin "10") (pinfunction "~{PRE}_10") (pintype "input"))
      (node (ref "IC9") (pin "11") (pinfunction "J_11") (pintype "input"))
      (node (ref "IC9") (pin "12") (pinfunction "K_12") (pintype "input"))
      (node (ref "IC9") (pin "13") (pinfunction "CLK_13") (pintype "input"))
      (node (ref "IC9") (pin "14") (pinfunction "~{CLR}_14") (pintype "input"))
      (node (ref "IC9") (pin "2") (pinfunction "K_2") (pintype "input"))
      (node (ref "IC9") (pin "3") (pinfunction "J_3") (pintype "input"))
      (node (ref "IC9") (pin "8") (pinfunction "GND_8") (pintype "input"))
      (node (ref "R18") (pin "1") (pinfunction "1_1") (pintype "passive"))
      (node (ref "R3") (pin "1") (pinfunction "1_1") (pintype "passive"))
      (node (ref "R4") (pin "1") (pinfunction "1_1") (pintype "passive"))
      (node (ref "R45") (pin "1") (pinfunction "1_1") (pintype "passive"))
      (node (ref "R49") (pin "1") (pinfunction "1_1") (pintype "passive"))
      (node (ref "R5") (pin "1") (pinfunction "1_1") (pintype "passive"))
      (node (ref "R6") (pin "1") (pinfunction "1_1") (pintype "passive"))
      (node (ref "R65") (pin "1") (pinfunction "1_1") (pintype "passive"))
      (node (ref "R70") (pin "1") (pinfunction "1_1") (pintype "passive"))
      (node (ref "SW1") (pin "1") (pinfunction "1A_1") (pintype "passive"))
      (node (ref "SW1") (pin "2") (pinfunction "1A_2") (pintype "passive"))
      (node (ref "T10") (pin "2") (pinfunction "S_2") (pintype "passive"))
      (node (ref "T2") (pin "2") (pinfunction "S_2") (pintype "passive"))
      (node (ref "T3") (pin "2") (pinfunction "S_2") (pintype "passive"))
      (node (ref "T6") (pin "2") (pinfunction "S_2") (pintype "passive"))
      (node (ref "T7") (pin "2") (pinfunction "S_2") (pintype "passive"))
      (node (ref "T8") (pin "2") (pinfunction "S_2") (pintype "passive"))
      (node (ref "TP1") (pin "TP") (pinfunction "TP_TP") (pintype "input"))
      (node (ref "X1") (pin "01") (pinfunction "1_01") (pintype "passive"))
      (node (ref "X1") (pin "02") (pinfunction "2_02") (pintype "passive"))
      (node (ref "X1") (pin "06") (pinfunction "6_06") (pintype "passive"))
      (node (ref "X1") (pin "07") (pinfunction "7_07") (pintype "passive"))
      (node (ref "X1") (pin "13") (pinfunction "13_13") (pintype "passive"))
      (node (ref "X1") (pin "19") (pinfunction "19_19") (pintype "passive"))
      (node (ref "X1") (pin "21") (pinfunction "21_21") (pintype "passive"))
      (node (ref "X1") (pin "26") (pinfunction "26_26") (pintype "passive"))
      (node (ref "X1") (pin "28") (pinfunction "28_28") (pintype "passive"))
      (node (ref "X1") (pin "32") (pinfunction "32_32") (pintype "passive"))
      (node (ref "X1") (pin "33") (pinfunction "33_33") (pintype "passive"))
      (node (ref "X1") (pin "39") (pinfunction "39_39") (pintype "passive"))
      (node (ref "X1") (pin "40") (pinfunction "40_40") (pintype "passive"))
      (node (ref "X2") (pin "01") (pinfunction "1_01") (pintype "passive"))
      (node (ref "X2") (pin "03") (pinfunction "3_03") (pintype "passive"))
      (node (ref "X2") (pin "05") (pinfunction "5_05") (pintype "passive"))
      (node (ref "X2") (pin "07") (pinfunction "7_07") (pintype "passive"))
      (node (ref "X2") (pin "09") (pinfunction "9_09") (pintype "passive"))
      (node (ref "X2") (pin "10") (pinfunction "10_10") (pintype "passive"))
      (node (ref "X2") (pin "11") (pinfunction "11_11") (pintype "passive"))
      (node (ref "X2") (pin "18") (pinfunction "18_18") (pintype "passive"))
      (node (ref "X2") (pin "24") (pinfunction "24_24") (pintype "passive"))
      (node (ref "X2") (pin "25") (pinfunction "25_25") (pintype "passive"))
      (node (ref "X2") (pin "28") (pinfunction "28_28") (pintype "passive"))
      (node (ref "X2") (pin "31") (pinfunction "31_31") (pintype "passive"))
      (node (ref "X2") (pin "34") (pinfunction "34_34") (pintype "passive"))
      (node (ref "X2") (pin "35") (pinfunction "35_35") (pintype "passive"))
      (node (ref "X2") (pin "37") (pinfunction "37_37") (pintype "passive"))
      (node (ref "X2") (pin "39") (pinfunction "39_39") (pintype "passive"))
      (node (ref "X2") (pin "40") (pinfunction "40_40") (pintype "passive"))
      (node (ref "X3") (pin "12") (pinfunction "12_12") (pintype "bidirectional"))
      (node (ref "X3") (pin "15") (pinfunction "15_15") (pintype "bidirectional"))
      (node (ref "X3") (pin "16") (pinfunction "16_16") (pintype "bidirectional"))
      (node (ref "X3") (pin "22") (pinfunction "22_22") (pintype "bidirectional"))
      (node (ref "X3") (pin "23") (pinfunction "23_23") (pintype "bidirectional"))
      (node (ref "X3") (pin "25") (pinfunction "25_25") (pintype "bidirectional"))
      (node (ref "X3") (pin "3") (pinfunction "3_3") (pintype "bidirectional"))
      (node (ref "X3") (pin "6") (pinfunction "6_6") (pintype "bidirectional"))
      (node (ref "X3") (pin "9") (pinfunction "9_9") (pintype "bidirectional"))
      (node (ref "X4") (pin "1") (pinfunction "1_1") (pintype "passive"))
      (node (ref "X4") (pin "11") (pinfunction "11_11") (pintype "passive"))
      (node (ref "X4") (pin "12") (pinfunction "12_12") (pintype "passive"))
      (node (ref "X4") (pin "2") (pinfunction "2_2") (pintype "passive"))
      (node (ref "X4") (pin "Z1") (pinfunction "Z1_Z1") (pintype "passive"))
      (node (ref "X4") (pin "Z2") (pinfunction "Z2_Z2") (pintype "passive"))
      (node (ref "X5") (pin "13") (pinfunction "13_13") (pintype "passive"))
      (node (ref "X5") (pin "16") (pinfunction "16_16") (pintype "passive"))
      (node (ref "X5") (pin "19") (pinfunction "19_19") (pintype "passive"))
      (node (ref "X5") (pin "22") (pinfunction "22_22") (pintype "passive"))
      (node (ref "X5") (pin "25") (pinfunction "25_25") (pintype "passive"))
      (node (ref "X5") (pin "28") (pinfunction "28_28") (pintype "passive"))
      (node (ref "X5") (pin "5") (pinfunction "5_5") (pintype "passive"))
      (node (ref "X5") (pin "9") (pinfunction "9_9") (pintype "passive"))
      (node (ref "X5") (pin "S1") (pinfunction "S_S1") (pintype "passive"))
      (node (ref "X5") (pin "S2") (pinfunction "S_S2") (pintype "passive"))
      (node (ref "X5") (pin "S3") (pinfunction "S_S3") (pintype "passive"))
      (node (ref "X5") (pin "S4") (pinfunction "S_S4") (pintype "passive"))
    )
    (net (code "42") (name "HEAT_CAM_ARESET_N_2V8") (class "Default")
      (node (ref "IC20") (pin "4") (pinfunction "I/O3_4") (pintype "passive"))
      (node (ref "X2") (pin "23") (pinfunction "23_23") (pintype "passive"))
      (node (ref "X4") (pin "5") (pinfunction "5_5") (pintype "passive"))
    )
    (net (code "43") (name "HEAT_CAM_FPA_EN_2V8") (class "Default")
      (node (ref "IC19") (pin "6") (pinfunction "I/O4_6") (pintype "passive"))
      (node (ref "X2") (pin "13") (pinfunction "13_13") (pintype "passive"))
      (node (ref "X4") (pin "10") (pinfunction "10_10") (pintype "passive"))
    )
    (net (code "44") (name "HEAT_CAM_MISO_2V8") (class "Default")
      (node (ref "IC19") (pin "1") (pinfunction "I/O1_1") (pintype "passive"))
      (node (ref "R87") (pin "2") (pinfunction "2_2") (pintype "passive"))
      (node (ref "X2") (pin "19") (pinfunction "19_19") (pintype "passive"))
    )
    (net (code "45") (name "HEAT_CAM_MOSI_2V8") (class "Default")
      (node (ref "IC19") (pin "3") (pinfunction "I/O2_3") (pintype "passive"))
      (node (ref "X2") (pin "17") (pinfunction "17_17") (pintype "passive"))
      (node (ref "X4") (pin "8") (pinfunction "8_8") (pintype "passive"))
    )
    (net (code "46") (name "HEAT_CAM_SCLK_2V8") (class "Default")
      (node (ref "IC19") (pin "4") (pinfunction "I/O3_4") (pintype "passive"))
      (node (ref "X2") (pin "15") (pinfunction "15_15") (pintype "passive"))
      (node (ref "X4") (pin "9") (pinfunction "9_9") (pintype "passive"))
    )
    (net (code "47") (name "HEAT_CAM_SCT_NSS_2V8") (class "Default")
      (node (ref "IC20") (pin "6") (pinfunction "I/O4_6") (pintype "passive"))
      (node (ref "X2") (pin "21") (pinfunction "21_21") (pintype "passive"))
      (node (ref "X4") (pin "6") (pinfunction "6_6") (pintype "passive"))
    )
    (net (code "48") (name "IR_PHOTOTRANSITOR") (class "Default")
      (node (ref "IC6") (pin "4") (pinfunction "C_4") (pintype "passive"))
      (node (ref "R36") (pin "1") (pinfunction "1_1") (pintype "passive"))
      (node (ref "R53") (pin "2") (pinfunction "2_2") (pintype "passive"))
      (node (ref "R61") (pin "1") (pinfunction "1_1") (pintype "passive"))
    )
    (net (code "49") (name "MUX_VDD") (class "Default")
      (node (ref "C36") (pin "1") (pinfunction "1_1") (pintype "passive"))
      (node (ref "IC23") (pin "12") (pinfunction "VDD_12") (pintype "input"))
      (node (ref "IC23") (pin "16") (pinfunction "EN_16") (pintype "input"))
      (node (ref "R77") (pin "1") (pinfunction "1_1") (pintype "passive"))
    )
    (net (code "50") (name "Net-(C78-Pad1)") (class "Default")
      (node (ref "C78") (pin "1") (pinfunction "1_1") (pintype "passive"))
      (node (ref "R16") (pin "1") (pinfunction "1_1") (pintype "passive"))
      (node (ref "X5") (pin "10") (pinfunction "10_10") (pintype "passive"))
      (node (ref "X5") (pin "12") (pinfunction "12_12") (pintype "passive"))
      (node (ref "X5") (pin "14") (pinfunction "14_14") (pintype "passive"))
    )
    (net (code "51") (name "Net-(D1-PadC)") (class "Default")
      (node (ref "D1") (pin "C") (pinfunction "C_C") (pintype "passive"))
      (node (ref "R62") (pin "2") (pinfunction "2_2") (pintype "passive"))
    )
    (net (code "52") (name "Net-(D2-PadC)") (class "Default")
      (node (ref "D2") (pin "C") (pinfunction "C_C") (pintype "passive"))
      (node (ref "R67") (pin "2") (pinfunction "2_2") (pintype "passive"))
    )
    (net (code "53") (name "Net-(D100A-A-Pad2)") (class "Default")
      (node (ref "D100") (pin "2") (pinfunction "A_2") (pintype "passive"))
      (node (ref "D100") (pin "3") (pinfunction "A_3") (pintype "passive"))
      (node (ref "D112") (pin "1") (pinfunction "C_1") (pintype "passive"))
      (node (ref "D112") (pin "4") (pinfunction "C_4") (pintype "passive"))
    )
    (net (code "54") (name "Net-(D100A-C-Pad1)") (class "Default")
      (node (ref "D100") (pin "1") (pinfunction "C_1") (pintype "passive"))
      (node (ref "D100") (pin "4") (pinfunction "C_4") (pintype "passive"))
      (node (ref "D101") (pin "2") (pinfunction "A_2") (pintype "passive"))
      (node (ref "D101") (pin "3") (pinfunction "A_3") (pintype "passive"))
    )
    (net (code "55") (name "Net-(D101A-C-Pad1)") (class "Default")
      (node (ref "D101") (pin "1") (pinfunction "C_1") (pintype "passive"))
      (node (ref "D101") (pin "4") (pinfunction "C_4") (pintype "passive"))
      (node (ref "D102") (pin "2") (pinfunction "A_2") (pintype "passive"))
      (node (ref "D102") (pin "3") (pinfunction "A_3") (pintype "passive"))
    )
    (net (code "56") (name "Net-(D102A-C-Pad1)") (class "Default")
      (node (ref "D102") (pin "1") (pinfunction "C_1") (pintype "passive"))
      (node (ref "D102") (pin "4") (pinfunction "C_4") (pintype "passive"))
      (node (ref "D103") (pin "2") (pinfunction "A_2") (pintype "passive"))
      (node (ref "D103") (pin "3") (pinfunction "A_3") (pintype "passive"))
    )
    (net (code "57") (name "Net-(D103A-C-Pad1)") (class "Default")
      (node (ref "D103") (pin "1") (pinfunction "C_1") (pintype "passive"))
      (node (ref "D103") (pin "4") (pinfunction "C_4") (pintype "passive"))
      (node (ref "D104") (pin "2") (pinfunction "A_2") (pintype "passive"))
      (node (ref "D104") (pin "3") (pinfunction "A_3") (pintype "passive"))
    )
    (net (code "58") (name "Net-(D104A-C-Pad1)") (class "Default")
      (node (ref "D104") (pin "1") (pinfunction "C_1") (pintype "passive"))
      (node (ref "D104") (pin "4") (pinfunction "C_4") (pintype "passive"))
      (node (ref "D105") (pin "2") (pinfunction "A_2") (pintype "passive"))
      (node (ref "D105") (pin "3") (pinfunction "A_3") (pintype "passive"))
    )
    (net (code "59") (name "Net-(D106A-A-Pad2)") (class "Default")
      (node (ref "D106") (pin "2") (pinfunction "A_2") (pintype "passive"))
      (node (ref "D106") (pin "3") (pinfunction "A_3") (pintype "passive"))
      (node (ref "R7") (pin "1") (pinfunction "1_1") (pintype "passive"))
      (node (ref "R83") (pin "1") (pinfunction "1_1") (pintype "passive"))
      (node (ref "R84") (pin "1") (pinfunction "1_1") (pintype "passive"))
    )
    (net (code "60") (name "Net-(D106A-C-Pad1)") (class "Default")
      (node (ref "D106") (pin "1") (pinfunction "C_1") (pintype "passive"))
      (node (ref "D106") (pin "4") (pinfunction "C_4") (pintype "passive"))
      (node (ref "D107") (pin "2") (pinfunction "A_2") (pintype "passive"))
      (node (ref "D107") (pin "3") (pinfunction "A_3") (pintype "passive"))
    )
    (net (code "61") (name "Net-(D107A-C-Pad1)") (class "Default")
      (node (ref "D107") (pin "1") (pinfunction "C_1") (pintype "passive"))
      (node (ref "D107") (pin "4") (pinfunction "C_4") (pintype "passive"))
      (node (ref "D108") (pin "2") (pinfunction "A_2") (pintype "passive"))
      (node (ref "D108") (pin "3") (pinfunction "A_3") (pintype "passive"))
    )
    (net (code "62") (name "Net-(D108A-C-Pad1)") (class "Default")
      (node (ref "D108") (pin "1") (pinfunction "C_1") (pintype "passive"))
      (node (ref "D108") (pin "4") (pinfunction "C_4") (pintype "passive"))
      (node (ref "D109") (pin "2") (pinfunction "A_2") (pintype "passive"))
      (node (ref "D109") (pin "3") (pinfunction "A_3") (pintype "passive"))
    )
    (net (code "63") (name "Net-(D109A-C-Pad1)") (class "Default")
      (node (ref "D109") (pin "1") (pinfunction "C_1") (pintype "passive"))
      (node (ref "D109") (pin "4") (pinfunction "C_4") (pintype "passive"))
      (node (ref "D110") (pin "2") (pinfunction "A_2") (pintype "passive"))
      (node (ref "D110") (pin "3") (pinfunction "A_3") (pintype "passive"))
    )
    (net (code "64") (name "Net-(D110A-C-Pad1)") (class "Default")
      (node (ref "D110") (pin "1") (pinfunction "C_1") (pintype "passive"))
      (node (ref "D110") (pin "4") (pinfunction "C_4") (pintype "passive"))
      (node (ref "D111") (pin "2") (pinfunction "A_2") (pintype "passive"))
      (node (ref "D111") (pin "3") (pinfunction "A_3") (pintype "passive"))
    )
    (net (code "65") (name "Net-(D111A-C-Pad1)") (class "Default")
      (node (ref "D111") (pin "1") (pinfunction "C_1") (pintype "passive"))
      (node (ref "D111") (pin "4") (pinfunction "C_4") (pintype "passive"))
      (node (ref "D112") (pin "2") (pinfunction "A_2") (pintype "passive"))
      (node (ref "D112") (pin "3") (pinfunction "A_3") (pintype "passive"))
    )
    (net (code "66") (name "Net-(D200-PadA)") (class "Default")
      (node (ref "D200") (pin "A") (pinfunction "A_A") (pintype "passive"))
      (node (ref "D201") (pin "C") (pinfunction "C_C") (pintype "passive"))
    )
    (net (code "67") (name "Net-(D201-PadA)") (class "Default")
      (node (ref "D201") (pin "A") (pinfunction "A_A") (pintype "passive"))
      (node (ref "D202") (pin "C") (pinfunction "C_C") (pintype "passive"))
    )
    (net (code "68") (name "Net-(D202-PadA)") (class "Default")
      (node (ref "D202") (pin "A") (pinfunction "A_A") (pintype "passive"))
      (node (ref "D203") (pin "C") (pinfunction "C_C") (pintype "passive"))
    )
    (net (code "69") (name "Net-(D203-PadA)") (class "Default")
      (node (ref "D203") (pin "A") (pinfunction "A_A") (pintype "passive"))
      (node (ref "D204") (pin "C") (pinfunction "C_C") (pintype "passive"))
    )
    (net (code "70") (name "Net-(D204-PadA)") (class "Default")
      (node (ref "D204") (pin "A") (pinfunction "A_A") (pintype "passive"))
      (node (ref "D205") (pin "C") (pinfunction "C_C") (pintype "passive"))
    )
    (net (code "71") (name "Net-(D205-PadA)") (class "Default")
      (node (ref "D205") (pin "A") (pinfunction "A_A") (pintype "passive"))
      (node (ref "D206") (pin "C") (pinfunction "C_C") (pintype "passive"))
    )
    (net (code "72") (name "Net-(D206-PadA)") (class "Default")
      (node (ref "D206") (pin "A") (pinfunction "A_A") (pintype "passive"))
      (node (ref "D215") (pin "C") (pinfunction "C_C") (pintype "passive"))
    )
    (net (code "73") (name "Net-(D207-PadA)") (class "Default")
      (node (ref "D207") (pin "A") (pinfunction "A_A") (pintype "passive"))
      (node (ref "D208") (pin "C") (pinfunction "C_C") (pintype "passive"))
    )
    (net (code "74") (name "Net-(D208-PadA)") (class "Default")
      (node (ref "D208") (pin "A") (pinfunction "A_A") (pintype "passive"))
      (node (ref "D209") (pin "C") (pinfunction "C_C") (pintype "passive"))
    )
    (net (code "75") (name "Net-(D209-PadA)") (class "Default")
      (node (ref "D209") (pin "A") (pinfunction "A_A") (pintype "passive"))
      (node (ref "D210") (pin "C") (pinfunction "C_C") (pintype "passive"))
    )
    (net (code "76") (name "Net-(D210-PadA)") (class "Default")
      (node (ref "D210") (pin "A") (pinfunction "A_A") (pintype "passive"))
      (node (ref "D211") (pin "C") (pinfunction "C_C") (pintype "passive"))
    )
    (net (code "77") (name "Net-(D211-PadA)") (class "Default")
      (node (ref "D211") (pin "A") (pinfunction "A_A") (pintype "passive"))
      (node (ref "D212") (pin "C") (pinfunction "C_C") (pintype "passive"))
    )
    (net (code "78") (name "Net-(D212-PadA)") (class "Default")
      (node (ref "D212") (pin "A") (pinfunction "A_A") (pintype "passive"))
      (node (ref "D213") (pin "C") (pinfunction "C_C") (pintype "passive"))
    )
    (net (code "79") (name "Net-(D213-PadA)") (class "Default")
      (node (ref "D213") (pin "A") (pinfunction "A_A") (pintype "passive"))
      (node (ref "D214") (pin "C") (pinfunction "C_C") (pintype "passive"))
    )
    (net (code "80") (name "Net-(D214-PadA)") (class "Default")
      (node (ref "D214") (pin "A") (pinfunction "A_A") (pintype "passive"))
      (node (ref "R34") (pin "1") (pinfunction "1_1") (pintype "passive"))
      (node (ref "R35") (pin "1") (pinfunction "1_1") (pintype "passive"))
    )
    (net (code "81") (name "Net-(D215-PadA)") (class "Default")
      (node (ref "D215") (pin "A") (pinfunction "A_A") (pintype "passive"))
      (node (ref "R20") (pin "1") (pinfunction "1_1") (pintype "passive"))
      (node (ref "R22") (pin "1") (pinfunction "1_1") (pintype "passive"))
    )
    (net (code "82") (name "Net-(D250-PadA)") (class "Default")
      (node (ref "D250") (pin "A") (pinfunction "A_A") (pintype "passive"))
      (node (ref "D251") (pin "C") (pinfunction "C_C") (pintype "passive"))
    )
    (net (code "83") (name "Net-(D251-PadA)") (class "Default")
      (node (ref "D251") (pin "A") (pinfunction "A_A") (pintype "passive"))
      (node (ref "D252") (pin "C") (pinfunction "C_C") (pintype "passive"))
    )
    (net (code "84") (name "Net-(D252-PadA)") (class "Default")
      (node (ref "D252") (pin "A") (pinfunction "A_A") (pintype "passive"))
      (node (ref "D253") (pin "C") (pinfunction "C_C") (pintype "passive"))
    )
    (net (code "85") (name "Net-(D253-PadA)") (class "Default")
      (node (ref "D253") (pin "A") (pinfunction "A_A") (pintype "passive"))
      (node (ref "D254") (pin "C") (pinfunction "C_C") (pintype "passive"))
    )
    (net (code "86") (name "Net-(D254-PadA)") (class "Default")
      (node (ref "D254") (pin "A") (pinfunction "A_A") (pintype "passive"))
      (node (ref "D255") (pin "C") (pinfunction "C_C") (pintype "passive"))
    )
    (net (code "87") (name "Net-(D255-PadA)") (class "Default")
      (node (ref "D255") (pin "A") (pinfunction "A_A") (pintype "passive"))
      (node (ref "D256") (pin "C") (pinfunction "C_C") (pintype "passive"))
    )
    (net (code "88") (name "Net-(D256-PadA)") (class "Default")
      (node (ref "D256") (pin "A") (pinfunction "A_A") (pintype "passive"))
      (node (ref "D265") (pin "C") (pinfunction "C_C") (pintype "passive"))
    )
    (net (code "89") (name "Net-(D257-PadA)") (class "Default")
      (node (ref "D257") (pin "A") (pinfunction "A_A") (pintype "passive"))
      (node (ref "D258") (pin "C") (pinfunction "C_C") (pintype "passive"))
    )
    (net (code "90") (name "Net-(D258-PadA)") (class "Default")
      (node (ref "D258") (pin "A") (pinfunction "A_A") (pintype "passive"))
      (node (ref "D259") (pin "C") (pinfunction "C_C") (pintype "passive"))
    )
    (net (code "91") (name "Net-(D259-PadA)") (class "Default")
      (node (ref "D259") (pin "A") (pinfunction "A_A") (pintype "passive"))
      (node (ref "D260") (pin "C") (pinfunction "C_C") (pintype "passive"))
    )
    (net (code "92") (name "Net-(D260-PadA)") (class "Default")
      (node (ref "D260") (pin "A") (pinfunction "A_A") (pintype "passive"))
      (node (ref "D261") (pin "C") (pinfunction "C_C") (pintype "passive"))
    )
    (net (code "93") (name "Net-(D261-PadA)") (class "Default")
      (node (ref "D261") (pin "A") (pinfunction "A_A") (pintype "passive"))
      (node (ref "D262") (pin "C") (pinfunction "C_C") (pintype "passive"))
    )
    (net (code "94") (name "Net-(D262-PadA)") (class "Default")
      (node (ref "D262") (pin "A") (pinfunction "A_A") (pintype "passive"))
      (node (ref "D263") (pin "C") (pinfunction "C_C") (pintype "passive"))
    )
    (net (code "95") (name "Net-(D263-PadA)") (class "Default")
      (node (ref "D263") (pin "A") (pinfunction "A_A") (pintype "passive"))
      (node (ref "D264") (pin "C") (pinfunction "C_C") (pintype "passive"))
    )
    (net (code "96") (name "Net-(D264-PadA)") (class "Default")
      (node (ref "D264") (pin "A") (pinfunction "A_A") (pintype "passive"))
      (node (ref "R73") (pin "1") (pinfunction "1_1") (pintype "passive"))
      (node (ref "R75") (pin "1") (pinfunction "1_1") (pintype "passive"))
    )
    (net (code "97") (name "Net-(D265-PadA)") (class "Default")
      (node (ref "D265") (pin "A") (pinfunction "A_A") (pintype "passive"))
      (node (ref "R52") (pin "1") (pinfunction "1_1") (pintype "passive"))
      (node (ref "R57") (pin "1") (pinfunction "1_1") (pintype "passive"))
    )
    (net (code "98") (name "Net-(D300-PadA)") (class "Default")
      (node (ref "D300") (pin "A") (pinfunction "A_A") (pintype "passive"))
      (node (ref "D301") (pin "C") (pinfunction "C_C") (pintype "passive"))
    )
    (net (code "99") (name "Net-(D300-PadC)") (class "Default")
      (node (ref "D300") (pin "C") (pinfunction "C_C") (pintype "passive"))
      (node (ref "D307") (pin "A") (pinfunction "A_A") (pintype "passive"))
    )
    (net (code "100") (name "Net-(D301-PadA)") (class "Default")
      (node (ref "D301") (pin "A") (pinfunction "A_A") (pintype "passive"))
      (node (ref "D302") (pin "C") (pinfunction "C_C") (pintype "passive"))
    )
    (net (code "101") (name "Net-(D302-PadA)") (class "Default")
      (node (ref "D302") (pin "A") (pinfunction "A_A") (pintype "passive"))
      (node (ref "D303") (pin "C") (pinfunction "C_C") (pintype "passive"))
    )
    (net (code "102") (name "Net-(D303-PadA)") (class "Default")
      (node (ref "D303") (pin "A") (pinfunction "A_A") (pintype "passive"))
      (node (ref "D304") (pin "C") (pinfunction "C_C") (pintype "passive"))
    )
    (net (code "103") (name "Net-(D304-PadA)") (class "Default")
      (node (ref "D304") (pin "A") (pinfunction "A_A") (pintype "passive"))
      (node (ref "D305") (pin "C") (pinfunction "C_C") (pintype "passive"))
    )
    (net (code "104") (name "Net-(D305-PadA)") (class "Default")
      (node (ref "D305") (pin "A") (pinfunction "A_A") (pintype "passive"))
      (node (ref "R15") (pin "1") (pinfunction "1_1") (pintype "passive"))
      (node (ref "R8") (pin "1") (pinfunction "1_1") (pintype "passive"))
    )
    (net (code "105") (name "Net-(D306-PadA)") (class "Default")
      (node (ref "D306") (pin "A") (pinfunction "A_A") (pintype "passive"))
      (node (ref "D307") (pin "C") (pinfunction "C_C") (pintype "passive"))
    )
    (net (code "106") (name "Net-(D308-PadA)") (class "Default")
      (node (ref "D308") (pin "A") (pinfunction "A_A") (pintype "passive"))
      (node (ref "D309") (pin "C") (pinfunction "C_C") (pintype "passive"))
    )
    (net (code "107") (name "Net-(D309-PadA)") (class "Default")
      (node (ref "D309") (pin "A") (pinfunction "A_A") (pintype "passive"))
      (node (ref "D310") (pin "C") (pinfunction "C_C") (pintype "passive"))
    )
    (net (code "108") (name "Net-(D310-PadA)") (class "Default")
      (node (ref "D310") (pin "A") (pinfunction "A_A") (pintype "passive"))
      (node (ref "D311") (pin "C") (pinfunction "C_C") (pintype "passive"))
    )
    (net (code "109") (name "Net-(D311-PadA)") (class "Default")
      (node (ref "D311") (pin "A") (pinfunction "A_A") (pintype "passive"))
      (node (ref "D312") (pin "C") (pinfunction "C_C") (pintype "passive"))
    )
    (net (code "110") (name "Net-(D312-PadA)") (class "Default")
      (node (ref "D312") (pin "A") (pinfunction "A_A") (pintype "passive"))
      (node (ref "D313") (pin "C") (pinfunction "C_C") (pintype "passive"))
    )
    (net (code "111") (name "Net-(D313-PadA)") (class "Default")
      (node (ref "D313") (pin "A") (pinfunction "A_A") (pintype "passive"))
      (node (ref "D314") (pin "C") (pinfunction "C_C") (pintype "passive"))
    )
    (net (code "112") (name "Net-(D314-PadA)") (class "Default")
      (node (ref "D314") (pin "A") (pinfunction "A_A") (pintype "passive"))
      (node (ref "D315") (pin "C") (pinfunction "C_C") (pintype "passive"))
    )
    (net (code "113") (name "Net-(D315-PadA)") (class "Default")
      (node (ref "D315") (pin "A") (pinfunction "A_A") (pintype "passive"))
      (node (ref "R25") (pin "1") (pinfunction "1_1") (pintype "passive"))
      (node (ref "R29") (pin "1") (pinfunction "1_1") (pintype "passive"))
    )
    (net (code "114") (name "Net-(D350-PadA)") (class "Default")
      (node (ref "D350") (pin "A") (pinfunction "A_A") (pintype "passive"))
      (node (ref "D351") (pin "C") (pinfunction "C_C") (pintype "passive"))
    )
    (net (code "115") (name "Net-(D350-PadC)") (class "Default")
      (node (ref "D350") (pin "C") (pinfunction "C_C") (pintype "passive"))
      (node (ref "D357") (pin "A") (pinfunction "A_A") (pintype "passive"))
    )
    (net (code "116") (name "Net-(D351-PadA)") (class "Default")
      (node (ref "D351") (pin "A") (pinfunction "A_A") (pintype "passive"))
      (node (ref "D352") (pin "C") (pinfunction "C_C") (pintype "passive"))
    )
    (net (code "117") (name "Net-(D352-PadA)") (class "Default")
      (node (ref "D352") (pin "A") (pinfunction "A_A") (pintype "passive"))
      (node (ref "D353") (pin "C") (pinfunction "C_C") (pintype "passive"))
    )
    (net (code "118") (name "Net-(D353-PadA)") (class "Default")
      (node (ref "D353") (pin "A") (pinfunction "A_A") (pintype "passive"))
      (node (ref "D354") (pin "C") (pinfunction "C_C") (pintype "passive"))
    )
    (net (code "119") (name "Net-(D354-PadA)") (class "Default")
      (node (ref "D354") (pin "A") (pinfunction "A_A") (pintype "passive"))
      (node (ref "D355") (pin "C") (pinfunction "C_C") (pintype "passive"))
    )
    (net (code "120") (name "Net-(D355-PadA)") (class "Default")
      (node (ref "D355") (pin "A") (pinfunction "A_A") (pintype "passive"))
      (node (ref "R43") (pin "1") (pinfunction "1_1") (pintype "passive"))
      (node (ref "R46") (pin "1") (pinfunction "1_1") (pintype "passive"))
    )
    (net (code "121") (name "Net-(D356-PadA)") (class "Default")
      (node (ref "D356") (pin "A") (pinfunction "A_A") (pintype "passive"))
      (node (ref "D357") (pin "C") (pinfunction "C_C") (pintype "passive"))
    )
    (net (code "122") (name "Net-(D358-PadA)") (class "Default")
      (node (ref "D358") (pin "A") (pinfunction "A_A") (pintype "passive"))
      (node (ref "D359") (pin "C") (pinfunction "C_C") (pintype "passive"))
    )
    (net (code "123") (name "Net-(D359-PadA)") (class "Default")
      (node (ref "D359") (pin "A") (pinfunction "A_A") (pintype "passive"))
      (node (ref "D360") (pin "C") (pinfunction "C_C") (pintype "passive"))
    )
    (net (code "124") (name "Net-(D360-PadA)") (class "Default")
      (node (ref "D360") (pin "A") (pinfunction "A_A") (pintype "passive"))
      (node (ref "D361") (pin "C") (pinfunction "C_C") (pintype "passive"))
    )
    (net (code "125") (name "Net-(D361-PadA)") (class "Default")
      (node (ref "D361") (pin "A") (pinfunction "A_A") (pintype "passive"))
      (node (ref "D362") (pin "C") (pinfunction "C_C") (pintype "passive"))
    )
    (net (code "126") (name "Net-(D362-PadA)") (class "Default")
      (node (ref "D362") (pin "A") (pinfunction "A_A") (pintype "passive"))
      (node (ref "D363") (pin "C") (pinfunction "C_C") (pintype "passive"))
    )
    (net (code "127") (name "Net-(D363-PadA)") (class "Default")
      (node (ref "D363") (pin "A") (pinfunction "A_A") (pintype "passive"))
      (node (ref "D364") (pin "C") (pinfunction "C_C") (pintype "passive"))
    )
    (net (code "128") (name "Net-(D364-PadA)") (class "Default")
      (node (ref "D364") (pin "A") (pinfunction "A_A") (pintype "passive"))
      (node (ref "D365") (pin "C") (pinfunction "C_C") (pintype "passive"))
    )
    (net (code "129") (name "Net-(D365-PadA)") (class "Default")
      (node (ref "D365") (pin "A") (pinfunction "A_A") (pintype "passive"))
      (node (ref "R66") (pin "1") (pinfunction "1_1") (pintype "passive"))
      (node (ref "R69") (pin "1") (pinfunction "1_1") (pintype "passive"))
    )
    (net (code "130") (name "Net-(IC1-OUT)") (class "Default")
      (node (ref "IC1") (pin "5") (pinfunction "OUT_5") (pintype "output"))
      (node (ref "R21") (pin "1") (pinfunction "1_1") (pintype "passive"))
    )
    (net (code "131") (name "Net-(IC1-VDD)") (class "Default")
      (node (ref "C3") (pin "1") (pinfunction "1_1") (pintype "passive"))
      (node (ref "IC1") (pin "1") (pinfunction "VDD_1") (pintype "input"))
      (node (ref "R1") (pin "2") (pinfunction "2_2") (pintype "passive"))
    )
    (net (code "132") (name "Net-(IC2-OUT)") (class "Default")
      (node (ref "IC2") (pin "5") (pinfunction "OUT_5") (pintype "output"))
      (node (ref "R23") (pin "1") (pinfunction "1_1") (pintype "passive"))
    )
    (net (code "133") (name "Net-(IC2-VDD)") (class "Default")
      (node (ref "C5") (pin "1") (pinfunction "1_1") (pintype "passive"))
      (node (ref "IC2") (pin "1") (pinfunction "VDD_1") (pintype "input"))
      (node (ref "R9") (pin "2") (pinfunction "2_2") (pintype "passive"))
    )
    (net (code "134") (name "Net-(IC3A-+IN)") (class "Default")
      (node (ref "C11") (pin "2") (pinfunction "2_2") (pintype "passive"))
      (node (ref "IC3") (pin "3") (pinfunction "+IN_3") (pintype "input"))
      (node (ref "IC3") (pin "5") (pinfunction "+IN_5") (pintype "input"))
      (node (ref "IC4") (pin "3") (pinfunction "+IN_3") (pintype "input"))
      (node (ref "IC4") (pin "5") (pinfunction "+IN_5") (pintype "input"))
      (node (ref "IC5") (pin "3") (pinfunction "+IN_3") (pintype "input"))
      (node (ref "IC5") (pin "5") (pinfunction "+IN_5") (pintype "input"))
      (node (ref "R17") (pin "1") (pinfunction "1_1") (pintype "passive"))
      (node (ref "R18") (pin "2") (pinfunction "2_2") (pintype "passive"))
    )
    (net (code "135") (name "Net-(IC3A--IN)") (class "Default")
      (node (ref "C6") (pin "1") (pinfunction "1_1") (pintype "passive"))
      (node (ref "IC3") (pin "2") (pinfunction "-IN_2") (pintype "input"))
      (node (ref "R10") (pin "2") (pinfunction "2_2") (pintype "passive"))
    )
    (net (code "136") (name "Net-(IC3A-OUT)") (class "Default")
      (node (ref "IC3") (pin "1") (pinfunction "OUT_1") (pintype "output"))
      (node (ref "IC3") (pin "7") (pinfunction "OUT_7") (pintype "output"))
      (node (ref "IC4") (pin "1") (pinfunction "OUT_1") (pintype "output"))
      (node (ref "IC5") (pin "1") (pinfunction "OUT_1") (pintype "output"))
      (node (ref "IC5") (pin "7") (pinfunction "OUT_7") (pintype "output"))
      (node (ref "R24") (pin "1") (pinfunction "1_1") (pintype "passive"))
    )
    (net (code "137") (name "Net-(IC3B--IN)") (class "Default")
      (node (ref "C7") (pin "1") (pinfunction "1_1") (pintype "passive"))
      (node (ref "IC3") (pin "6") (pinfunction "-IN_6") (pintype "input"))
      (node (ref "R11") (pin "2") (pinfunction "2_2") (pintype "passive"))
    )
    (net (code "138") (name "Net-(IC3C-VCC)") (class "Default")
      (node (ref "C17") (pin "1") (pinfunction "1_1") (pintype "passive"))
      (node (ref "IC3") (pin "8") (pinfunction "VCC_8") (pintype "input"))
      (node (ref "R26") (pin "1") (pinfunction "1_1") (pintype "passive"))
    )
    (net (code "139") (name "Net-(IC4A--IN)") (class "Default")
      (node (ref "C8") (pin "1") (pinfunction "1_1") (pintype "passive"))
      (node (ref "IC4") (pin "2") (pinfunction "-IN_2") (pintype "input"))
      (node (ref "R12") (pin "2") (pinfunction "2_2") (pintype "passive"))
    )
    (net (code "140") (name "Net-(IC4C-VCC)") (class "Default")
      (node (ref "C18") (pin "1") (pinfunction "1_1") (pintype "passive"))
      (node (ref "IC4") (pin "8") (pinfunction "VCC_8") (pintype "input"))
      (node (ref "R27") (pin "1") (pinfunction "1_1") (pintype "passive"))
    )
    (net (code "141") (name "Net-(IC5A--IN)") (class "Default")
      (node (ref "C9") (pin "1") (pinfunction "1_1") (pintype "passive"))
      (node (ref "IC5") (pin "2") (pinfunction "-IN_2") (pintype "input"))
      (node (ref "R13") (pin "2") (pinfunction "2_2") (pintype "passive"))
    )
    (net (code "142") (name "Net-(IC5C-VCC)") (class "Default")
      (node (ref "C19") (pin "1") (pinfunction "1_1") (pintype "passive"))
      (node (ref "IC5") (pin "8") (pinfunction "VCC_8") (pintype "input"))
      (node (ref "R28") (pin "1") (pinfunction "1_1") (pintype "passive"))
    )
    (net (code "143") (name "Net-(IC7-AVDD)") (class "Default")
      (node (ref "C57") (pin "1") (pinfunction "1_1") (pintype "passive"))
      (node (ref "C58") (pin "1") (pinfunction "1_1") (pintype "passive"))
      (node (ref "IC7") (pin "1") (pinfunction "AVDDVCSEL_1") (pintype "input"))
      (node (ref "IC7") (pin "11") (pinfunction "AVDD_11") (pintype "input"))
      (node (ref "R19") (pin "2") (pinfunction "2_2") (pintype "passive"))
      (node (ref "R2") (pin "2") (pinfunction "2_2") (pintype "passive"))
    )
    (net (code "144") (name "Net-(IC7-SCL)") (class "Default")
      (node (ref "IC7") (pin "10") (pinfunction "SCL_10") (pintype "input"))
      (node (ref "R32") (pin "1") (pinfunction "1_1") (pintype "passive"))
    )
    (net (code "145") (name "Net-(IC7-SDA)") (class "Default")
      (node (ref "IC7") (pin "9") (pinfunction "SDA_9") (pintype "open_collector"))
      (node (ref "R30") (pin "1") (pinfunction "1_1") (pintype "passive"))
    )
    (net (code "146") (name "Net-(IC7-XSHUT)") (class "Default")
      (node (ref "IC7") (pin "5") (pinfunction "XSHUT_5") (pintype "input"))
      (node (ref "R2") (pin "1") (pinfunction "1_1") (pintype "passive"))
    )
    (net (code "147") (name "Net-(IC8-OUT)") (class "Default")
      (node (ref "IC8") (pin "5") (pinfunction "OUT_5") (pintype "output"))
      (node (ref "R54") (pin "1") (pinfunction "1_1") (pintype "passive"))
      (node (ref "TP5") (pin "TP") (pinfunction "TP_TP") (pintype "input"))
    )
    (net (code "148") (name "Net-(IC8-VDD)") (class "Default")
      (node (ref "C24") (pin "1") (pinfunction "1_1") (pintype "passive"))
      (node (ref "IC8") (pin "1") (pinfunction "VDD_1") (pintype "input"))
      (node (ref "R38") (pin "2") (pinfunction "2_2") (pintype "passive"))
    )
    (net (code "149") (name "Net-(IC9A-Q)") (class "Default")
      (node (ref "IC9") (pin "5") (pinfunction "Q_5") (pintype "output"))
      (node (ref "R55") (pin "1") (pinfunction "1_1") (pintype "passive"))
    )
    (net (code "150") (name "Net-(IC9A-~{PRE})") (class "Default")
      (node (ref "C23") (pin "1") (pinfunction "1_1") (pintype "passive"))
      (node (ref "IC9") (pin "4") (pinfunction "~{PRE}_4") (pintype "input"))
      (node (ref "R37") (pin "2") (pinfunction "2_2") (pintype "passive"))
      (node (ref "R40") (pin "1") (pinfunction "1_1") (pintype "passive"))
    )
    (net (code "151") (name "Net-(IC9A-~{Q})") (class "Default")
      (node (ref "IC9") (pin "6") (pinfunction "~{Q}_6") (pintype "output"))
      (node (ref "R56") (pin "1") (pinfunction "1_1") (pintype "passive"))
    )
    (net (code "152") (name "Net-(IC9C-VCC)") (class "Default")
      (node (ref "C34") (pin "1") (pinfunction "1_1") (pintype "passive"))
      (node (ref "IC9") (pin "16") (pinfunction "VCC_16") (pintype "input"))
      (node (ref "R76") (pin "1") (pinfunction "1_1") (pintype "passive"))
    )
    (net (code "153") (name "Net-(IC10-OUT)") (class "Default")
      (node (ref "IC10") (pin "5") (pinfunction "OUT_5") (pintype "output"))
      (node (ref "R59") (pin "1") (pinfunction "1_1") (pintype "passive"))
    )
    (net (code "154") (name "Net-(IC10-VDD)") (class "Default")
      (node (ref "C26") (pin "1") (pinfunction "1_1") (pintype "passive"))
      (node (ref "IC10") (pin "1") (pinfunction "VDD_1") (pintype "input"))
      (node (ref "R44") (pin "2") (pinfunction "2_2") (pintype "passive"))
    )
    (net (code "155") (name "Net-(IC11A-+IN)") (class "Default")
      (node (ref "IC11") (pin "3") (pinfunction "+IN_3") (pintype "input"))
      (node (ref "R63") (pin "2") (pinfunction "2_2") (pintype "passive"))
      (node (ref "R65") (pin "2") (pinfunction "2_2") (pintype "passive"))
    )
    (net (code "156") (name "Net-(IC11A--IN)") (class "Default")
      (node (ref "C31") (pin "1") (pinfunction "1_1") (pintype "passive"))
      (node (ref "IC11") (pin "2") (pinfunction "-IN_2") (pintype "input"))
      (node (ref "R61") (pin "2") (pinfunction "2_2") (pintype "passive"))
      (node (ref "R68") (pin "1") (pinfunction "1_1") (pintype "passive"))
      (node (ref "R86") (pin "2") (pinfunction "2_2") (pintype "passive"))
    )
    (net (code "157") (name "Net-(IC11B-+IN)") (class "Default")
      (node (ref "IC11") (pin "5") (pinfunction "+IN_5") (pintype "input"))
      (node (ref "R42") (pin "2") (pinfunction "2_2") (pintype "passive"))
      (node (ref "R45") (pin "2") (pinfunction "2_2") (pintype "passive"))
    )
    (net (code "158") (name "Net-(IC11B--IN)") (class "Default")
      (node (ref "IC11") (pin "6") (pinfunction "-IN_6") (pintype "input"))
      (node (ref "R41") (pin "2") (pinfunction "2_2") (pintype "passive"))
      (node (ref "R48") (pin "1") (pinfunction "1_1") (pintype "passive"))
      (node (ref "R85") (pin "2") (pinfunction "2_2") (pintype "passive"))
    )
    (net (code "159") (name "Net-(IC11B-OUT)") (class "Default")
      (node (ref "IC11") (pin "7") (pinfunction "OUT_7") (pintype "output"))
      (node (ref "R48") (pin "2") (pinfunction "2_2") (pintype "passive"))
      (node (ref "R58") (pin "1") (pinfunction "1_1") (pintype "passive"))
    )
    (net (code "160") (name "Net-(IC11C-VCC)") (class "Default")
      (node (ref "C35") (pin "1") (pinfunction "1_1") (pintype "passive"))
      (node (ref "IC11") (pin "8") (pinfunction "VCC_8") (pintype "input"))
      (node (ref "R74") (pin "1") (pinfunction "1_1") (pintype "passive"))
    )
    (net (code "161") (name "Net-(IC13-OUT)") (class "Default")
      (node (ref "IC13") (pin "5") (pinfunction "OUT_5") (pintype "output"))
      (node (ref "R80") (pin "1") (pinfunction "1_1") (pintype "passive"))
      (node (ref "TP18") (pin "TP") (pinfunction "TP_TP") (pintype "input"))
    )
    (net (code "162") (name "Net-(IC13-VDD)") (class "Default")
      (node (ref "C38") (pin "1") (pinfunction "1_1") (pintype "passive"))
      (node (ref "IC13") (pin "1") (pinfunction "VDD_1") (pintype "input"))
      (node (ref "R78") (pin "2") (pinfunction "2_2") (pintype "passive"))
    )
    (net (code "163") (name "Net-(IC15-SCL)") (class "Default")
      (node (ref "IC15") (pin "2") (pinfunction "SCL_2") (pintype "input"))
      (node (ref "IC24") (pin "1") (pinfunction "SCL_1") (pintype "input"))
      (node (ref "R82") (pin "1") (pinfunction "1_1") (pintype "passive"))
    )
    (net (code "164") (name "Net-(IC15-SDA)") (class "Default")
      (node (ref "IC15") (pin "1") (pinfunction "SDA_1") (pintype "open_collector"))
      (node (ref "IC24") (pin "6") (pinfunction "SDA_6") (pintype "open_collector"))
      (node (ref "R81") (pin "1") (pinfunction "1_1") (pintype "passive"))
    )
    (net (code "165") (name "Net-(IC15-VCC)") (class "Default")
      (node (ref "C40") (pin "1") (pinfunction "1_1") (pintype "passive"))
      (node (ref "IC15") (pin "8") (pinfunction "VCC_8") (pintype "input"))
      (node (ref "IC24") (pin "5") (pinfunction "V+_5") (pintype "input"))
      (node (ref "R79") (pin "1") (pinfunction "1_1") (pintype "passive"))
    )
    (net (code "166") (name "Net-(IC23-A0)") (class "Default")
      (node (ref "IC23") (pin "15") (pinfunction "A0_15") (pintype "input"))
      (node (ref "R50") (pin "2") (pinfunction "2_2") (pintype "passive"))
    )
    (net (code "167") (name "Net-(IC23-DA)") (class "Default")
      (node (ref "IC23") (pin "6") (pinfunction "DA_6") (pintype "passive"))
      (node (ref "R51") (pin "2") (pinfunction "2_2") (pintype "passive"))
    )
    (net (code "168") (name "Net-(IC25-DNC1)") (class "Default")
      (node (ref "IC25") (pin "4") (pinfunction "DNC1_4") (pintype "output"))
      (node (ref "R70") (pin "2") (pinfunction "2_2") (pintype "passive"))
    )
    (net (code "169") (name "Net-(IC25-SCL)") (class "Default")
      (node (ref "IC25") (pin "5") (pinfunction "SCL_5") (pintype "bidirectional"))
      (node (ref "R39") (pin "1") (pinfunction "1_1") (pintype "passive"))
    )
    (net (code "170") (name "Net-(IC25-SDA)") (class "Default")
      (node (ref "IC25") (pin "6") (pinfunction "SDA_6") (pintype "bidirectional"))
      (node (ref "R33") (pin "1") (pinfunction "1_1") (pintype "passive"))
    )
    (net (code "171") (name "Net-(IC25-TEST)") (class "Default")
      (node (ref "IC25") (pin "1") (pinfunction "TEST_1") (pintype "input"))
      (node (ref "R49") (pin "2") (pinfunction "2_2") (pintype "passive"))
      (node (ref "R71") (pin "1") (pinfunction "1_1") (pintype "passive"))
    )
    (net (code "172") (name "Net-(IC25-VCC)") (class "Default")
      (node (ref "C59") (pin "1") (pinfunction "1_1") (pintype "passive"))
      (node (ref "IC25") (pin "2") (pinfunction "VCC_2") (pintype "input"))
      (node (ref "R71") (pin "2") (pinfunction "2_2") (pintype "passive"))
      (node (ref "R72") (pin "2") (pinfunction "2_2") (pintype "passive"))
    )
    (net (code "173") (name "Net-(IC100-DOUT)") (class "Default")
      (node (ref "IC100") (pin "3") (pinfunction "DOUT_3") (pintype "output"))
      (node (ref "IC101") (pin "1") (pinfunction "DIN_1") (pintype "input"))
    )
    (net (code "174") (name "Net-(IC101-DOUT)") (class "Default")
      (node (ref "IC101") (pin "3") (pinfunction "DOUT_3") (pintype "output"))
      (node (ref "IC102") (pin "1") (pinfunction "DIN_1") (pintype "input"))
    )
    (net (code "175") (name "Net-(IC102-DOUT)") (class "Default")
      (node (ref "IC102") (pin "3") (pinfunction "DOUT_3") (pintype "output"))
      (node (ref "IC103") (pin "1") (pinfunction "DIN_1") (pintype "input"))
    )
    (net (code "176") (name "Net-(IC103-DOUT)") (class "Default")
      (node (ref "IC103") (pin "3") (pinfunction "DOUT_3") (pintype "output"))
      (node (ref "IC104") (pin "1") (pinfunction "DIN_1") (pintype "input"))
    )
    (net (code "177") (name "Net-(IC105-DOUT)") (class "Default")
      (node (ref "IC105") (pin "3") (pinfunction "DOUT_3") (pintype "output"))
      (node (ref "IC106") (pin "1") (pinfunction "DIN_1") (pintype "input"))
    )
    (net (code "178") (name "Net-(IC106-DOUT)") (class "Default")
      (node (ref "IC106") (pin "3") (pinfunction "DOUT_3") (pintype "output"))
      (node (ref "IC107") (pin "1") (pinfunction "DIN_1") (pintype "input"))
    )
    (net (code "179") (name "Net-(IC107-DOUT)") (class "Default")
      (node (ref "IC107") (pin "3") (pinfunction "DOUT_3") (pintype "output"))
      (node (ref "IC108") (pin "1") (pinfunction "DIN_1") (pintype "input"))
    )
    (net (code "180") (name "Net-(IC108-DOUT)") (class "Default")
      (node (ref "IC108") (pin "3") (pinfunction "DOUT_3") (pintype "output"))
      (node (ref "IC109") (pin "1") (pinfunction "DIN_1") (pintype "input"))
    )
    (net (code "181") (name "Net-(IC110-DOUT)") (class "Default")
      (node (ref "IC110") (pin "3") (pinfunction "DOUT_3") (pintype "output"))
      (node (ref "IC111") (pin "1") (pinfunction "DIN_1") (pintype "input"))
    )
    (net (code "182") (name "Net-(IC111-DOUT)") (class "Default")
      (node (ref "IC111") (pin "3") (pinfunction "DOUT_3") (pintype "output"))
      (node (ref "IC112") (pin "1") (pinfunction "DIN_1") (pintype "input"))
    )
    (net (code "183") (name "Net-(IC112-DOUT)") (class "Default")
      (node (ref "IC112") (pin "3") (pinfunction "DOUT_3") (pintype "output"))
      (node (ref "IC113") (pin "1") (pinfunction "DIN_1") (pintype "input"))
    )
    (net (code "184") (name "Net-(IC113-DOUT)") (class "Default")
      (node (ref "IC113") (pin "3") (pinfunction "DOUT_3") (pintype "output"))
      (node (ref "IC114") (pin "1") (pinfunction "DIN_1") (pintype "input"))
    )
    (net (code "185") (name "Net-(IC115-DOUT)") (class "Default")
      (node (ref "IC115") (pin "3") (pinfunction "DOUT_3") (pintype "output"))
      (node (ref "IC116") (pin "1") (pinfunction "DIN_1") (pintype "input"))
    )
    (net (code "186") (name "Net-(IC116-DOUT)") (class "Default")
      (node (ref "IC116") (pin "3") (pinfunction "DOUT_3") (pintype "output"))
      (node (ref "IC117") (pin "1") (pinfunction "DIN_1") (pintype "input"))
    )
    (net (code "187") (name "Net-(IC117-DOUT)") (class "Default")
      (node (ref "IC117") (pin "3") (pinfunction "DOUT_3") (pintype "output"))
      (node (ref "IC118") (pin "1") (pinfunction "DIN_1") (pintype "input"))
    )
    (net (code "188") (name "Net-(IC118-DOUT)") (class "Default")
      (node (ref "IC118") (pin "3") (pinfunction "DOUT_3") (pintype "output"))
      (node (ref "IC119") (pin "1") (pinfunction "DIN_1") (pintype "input"))
    )
    (net (code "189") (name "Net-(IC120-DOUT)") (class "Default")
      (node (ref "IC120") (pin "3") (pinfunction "DOUT_3") (pintype "output"))
      (node (ref "IC121") (pin "1") (pinfunction "DIN_1") (pintype "input"))
    )
    (net (code "190") (name "Net-(IC121-DOUT)") (class "Default")
      (node (ref "IC121") (pin "3") (pinfunction "DOUT_3") (pintype "output"))
      (node (ref "IC122") (pin "1") (pinfunction "DIN_1") (pintype "input"))
    )
    (net (code "191") (name "Net-(IC122-DOUT)") (class "Default")
      (node (ref "IC122") (pin "3") (pinfunction "DOUT_3") (pintype "output"))
      (node (ref "IC123") (pin "1") (pinfunction "DIN_1") (pintype "input"))
    )
    (net (code "192") (name "Net-(IC123-DOUT)") (class "Default")
      (node (ref "IC123") (pin "3") (pinfunction "DOUT_3") (pintype "output"))
      (node (ref "IC124") (pin "1") (pinfunction "DIN_1") (pintype "input"))
    )
    (net (code "193") (name "Net-(IC125-DOUT)") (class "Default")
      (node (ref "IC125") (pin "3") (pinfunction "DOUT_3") (pintype "output"))
      (node (ref "IC126") (pin "1") (pinfunction "DIN_1") (pintype "input"))
    )
    (net (code "194") (name "Net-(IC126-DOUT)") (class "Default")
      (node (ref "IC126") (pin "3") (pinfunction "DOUT_3") (pintype "output"))
      (node (ref "IC127") (pin "1") (pinfunction "DIN_1") (pintype "input"))
    )
    (net (code "195") (name "Net-(IC127-DOUT)") (class "Default")
      (node (ref "IC127") (pin "3") (pinfunction "DOUT_3") (pintype "output"))
      (node (ref "IC128") (pin "1") (pinfunction "DIN_1") (pintype "input"))
    )
    (net (code "196") (name "Net-(IC128-DOUT)") (class "Default")
      (node (ref "IC128") (pin "3") (pinfunction "DOUT_3") (pintype "output"))
      (node (ref "IC129") (pin "1") (pinfunction "DIN_1") (pintype "input"))
    )
    (net (code "197") (name "Net-(IC130-DOUT)") (class "Default")
      (node (ref "IC130") (pin "3") (pinfunction "DOUT_3") (pintype "output"))
      (node (ref "IC131") (pin "1") (pinfunction "DIN_1") (pintype "input"))
    )
    (net (code "198") (name "Net-(IC131-DOUT)") (class "Default")
      (node (ref "IC131") (pin "3") (pinfunction "DOUT_3") (pintype "output"))
      (node (ref "IC132") (pin "1") (pinfunction "DIN_1") (pintype "input"))
    )
    (net (code "199") (name "Net-(IC132-DOUT)") (class "Default")
      (node (ref "IC132") (pin "3") (pinfunction "DOUT_3") (pintype "output"))
      (node (ref "IC133") (pin "1") (pinfunction "DIN_1") (pintype "input"))
    )
    (net (code "200") (name "Net-(IC133-DOUT)") (class "Default")
      (node (ref "IC133") (pin "3") (pinfunction "DOUT_3") (pintype "output"))
      (node (ref "IC134") (pin "1") (pinfunction "DIN_1") (pintype "input"))
    )
    (net (code "201") (name "Net-(IC135-DOUT)") (class "Default")
      (node (ref "IC135") (pin "3") (pinfunction "DOUT_3") (pintype "output"))
      (node (ref "IC136") (pin "1") (pinfunction "DIN_1") (pintype "input"))
    )
    (net (code "202") (name "Net-(IC136-DOUT)") (class "Default")
      (node (ref "IC136") (pin "3") (pinfunction "DOUT_3") (pintype "output"))
      (node (ref "IC137") (pin "1") (pinfunction "DIN_1") (pintype "input"))
    )
    (net (code "203") (name "Net-(IC137-DOUT)") (class "Default")
      (node (ref "IC137") (pin "3") (pinfunction "DOUT_3") (pintype "output"))
      (node (ref "IC138") (pin "1") (pinfunction "DIN_1") (pintype "input"))
    )
    (net (code "204") (name "Net-(IC138-DOUT)") (class "Default")
      (node (ref "IC138") (pin "3") (pinfunction "DOUT_3") (pintype "output"))
      (node (ref "IC139") (pin "1") (pinfunction "DIN_1") (pintype "input"))
    )
    (net (code "205") (name "Net-(IC140-DOUT)") (class "Default")
      (node (ref "IC140") (pin "3") (pinfunction "DOUT_3") (pintype "output"))
      (node (ref "IC141") (pin "1") (pinfunction "DIN_1") (pintype "input"))
    )
    (net (code "206") (name "Net-(IC141-DOUT)") (class "Default")
      (node (ref "IC141") (pin "3") (pinfunction "DOUT_3") (pintype "output"))
      (node (ref "IC142") (pin "1") (pinfunction "DIN_1") (pintype "input"))
    )
    (net (code "207") (name "Net-(IC142-DOUT)") (class "Default")
      (node (ref "IC142") (pin "3") (pinfunction "DOUT_3") (pintype "output"))
      (node (ref "IC143") (pin "1") (pinfunction "DIN_1") (pintype "input"))
    )
    (net (code "208") (name "Net-(IC143-DOUT)") (class "Default")
      (node (ref "IC143") (pin "3") (pinfunction "DOUT_3") (pintype "output"))
      (node (ref "IC144") (pin "1") (pinfunction "DIN_1") (pintype "input"))
    )
    (net (code "209") (name "Net-(IC145-DOUT)") (class "Default")
      (node (ref "IC145") (pin "3") (pinfunction "DOUT_3") (pintype "output"))
      (node (ref "IC146") (pin "1") (pinfunction "DIN_1") (pintype "input"))
    )
    (net (code "210") (name "Net-(IC146-DOUT)") (class "Default")
      (node (ref "IC146") (pin "3") (pinfunction "DOUT_3") (pintype "output"))
      (node (ref "IC147") (pin "1") (pinfunction "DIN_1") (pintype "input"))
    )
    (net (code "211") (name "Net-(IC147-DOUT)") (class "Default")
      (node (ref "IC147") (pin "3") (pinfunction "DOUT_3") (pintype "output"))
      (node (ref "IC148") (pin "1") (pinfunction "DIN_1") (pintype "input"))
    )
    (net (code "212") (name "Net-(IC148-DOUT)") (class "Default")
      (node (ref "IC148") (pin "3") (pinfunction "DOUT_3") (pintype "output"))
      (node (ref "IC149") (pin "1") (pinfunction "DIN_1") (pintype "input"))
    )
    (net (code "213") (name "Net-(IC150-DOUT)") (class "Default")
      (node (ref "IC150") (pin "3") (pinfunction "DOUT_3") (pintype "output"))
      (node (ref "IC151") (pin "1") (pinfunction "DIN_1") (pintype "input"))
    )
    (net (code "214") (name "Net-(IC151-DOUT)") (class "Default")
      (node (ref "IC151") (pin "3") (pinfunction "DOUT_3") (pintype "output"))
      (node (ref "IC152") (pin "1") (pinfunction "DIN_1") (pintype "input"))
    )
    (net (code "215") (name "Net-(IC152-DOUT)") (class "Default")
      (node (ref "IC152") (pin "3") (pinfunction "DOUT_3") (pintype "output"))
      (node (ref "IC153") (pin "1") (pinfunction "DIN_1") (pintype "input"))
    )
    (net (code "216") (name "Net-(IC153-DOUT)") (class "Default")
      (node (ref "IC153") (pin "3") (pinfunction "DOUT_3") (pintype "output"))
      (node (ref "IC154") (pin "1") (pinfunction "DIN_1") (pintype "input"))
    )
    (net (code "217") (name "Net-(IC156-DOUT)") (class "Default")
      (node (ref "IC156") (pin "3") (pinfunction "DOUT_3") (pintype "output"))
      (node (ref "IC157") (pin "1") (pinfunction "DIN_1") (pintype "input"))
    )
    (net (code "218") (name "Net-(IC157-DOUT)") (class "Default")
      (node (ref "IC157") (pin "3") (pinfunction "DOUT_3") (pintype "output"))
      (node (ref "IC158") (pin "1") (pinfunction "DIN_1") (pintype "input"))
    )
    (net (code "219") (name "Net-(IC158-DOUT)") (class "Default")
      (node (ref "IC158") (pin "3") (pinfunction "DOUT_3") (pintype "output"))
      (node (ref "IC159") (pin "1") (pinfunction "DIN_1") (pintype "input"))
    )
    (net (code "220") (name "Net-(IC159-DOUT)") (class "Default")
      (node (ref "IC159") (pin "3") (pinfunction "DOUT_3") (pintype "output"))
      (node (ref "IC160") (pin "1") (pinfunction "DIN_1") (pintype "input"))
    )
    (net (code "221") (name "Net-(IC161-DOUT)") (class "Default")
      (node (ref "IC161") (pin "3") (pinfunction "DOUT_3") (pintype "output"))
      (node (ref "IC162") (pin "1") (pinfunction "DIN_1") (pintype "input"))
    )
    (net (code "222") (name "Net-(IC162-DOUT)") (class "Default")
      (node (ref "IC162") (pin "3") (pinfunction "DOUT_3") (pintype "output"))
      (node (ref "IC163") (pin "1") (pinfunction "DIN_1") (pintype "input"))
    )
    (net (code "223") (name "Net-(IC163-DOUT)") (class "Default")
      (node (ref "IC163") (pin "3") (pinfunction "DOUT_3") (pintype "output"))
      (node (ref "IC164") (pin "1") (pinfunction "DIN_1") (pintype "input"))
    )
    (net (code "224") (name "Net-(IC164-DOUT)") (class "Default")
      (node (ref "IC164") (pin "3") (pinfunction "DOUT_3") (pintype "output"))
      (node (ref "IC165") (pin "1") (pinfunction "DIN_1") (pintype "input"))
    )
    (net (code "225") (name "Net-(IC166-DOUT)") (class "Default")
      (node (ref "IC166") (pin "3") (pinfunction "DOUT_3") (pintype "output"))
      (node (ref "IC167") (pin "1") (pinfunction "DIN_1") (pintype "input"))
    )
    (net (code "226") (name "Net-(IC167-DOUT)") (class "Default")
      (node (ref "IC167") (pin "3") (pinfunction "DOUT_3") (pintype "output"))
      (node (ref "IC168") (pin "1") (pinfunction "DIN_1") (pintype "input"))
    )
    (net (code "227") (name "Net-(IC168-DOUT)") (class "Default")
      (node (ref "IC168") (pin "3") (pinfunction "DOUT_3") (pintype "output"))
      (node (ref "IC169") (pin "1") (pinfunction "DIN_1") (pintype "input"))
    )
    (net (code "228") (name "Net-(IC169-DOUT)") (class "Default")
      (node (ref "IC169") (pin "3") (pinfunction "DOUT_3") (pintype "output"))
      (node (ref "IC170") (pin "1") (pinfunction "DIN_1") (pintype "input"))
    )
    (net (code "229") (name "Net-(IC171-DOUT)") (class "Default")
      (node (ref "IC171") (pin "3") (pinfunction "DOUT_3") (pintype "output"))
      (node (ref "IC172") (pin "1") (pinfunction "DIN_1") (pintype "input"))
    )
    (net (code "230") (name "Net-(IC172-DOUT)") (class "Default")
      (node (ref "IC172") (pin "3") (pinfunction "DOUT_3") (pintype "output"))
      (node (ref "IC173") (pin "1") (pinfunction "DIN_1") (pintype "input"))
    )
    (net (code "231") (name "Net-(IC173-DOUT)") (class "Default")
      (node (ref "IC173") (pin "3") (pinfunction "DOUT_3") (pintype "output"))
      (node (ref "IC174") (pin "1") (pinfunction "DIN_1") (pintype "input"))
    )
    (net (code "232") (name "Net-(IC174-DOUT)") (class "Default")
      (node (ref "IC174") (pin "3") (pinfunction "DOUT_3") (pintype "output"))
      (node (ref "IC175") (pin "1") (pinfunction "DIN_1") (pintype "input"))
    )
    (net (code "233") (name "Net-(IC176-DOUT)") (class "Default")
      (node (ref "IC176") (pin "3") (pinfunction "DOUT_3") (pintype "output"))
      (node (ref "IC177") (pin "1") (pinfunction "DIN_1") (pintype "input"))
    )
    (net (code "234") (name "Net-(IC177-DOUT)") (class "Default")
      (node (ref "IC177") (pin "3") (pinfunction "DOUT_3") (pintype "output"))
      (node (ref "IC178") (pin "1") (pinfunction "DIN_1") (pintype "input"))
    )
    (net (code "235") (name "Net-(IC178-DOUT)") (class "Default")
      (node (ref "IC178") (pin "3") (pinfunction "DOUT_3") (pintype "output"))
      (node (ref "IC179") (pin "1") (pinfunction "DIN_1") (pintype "input"))
    )
    (net (code "236") (name "Net-(IC179-DOUT)") (class "Default")
      (node (ref "IC179") (pin "3") (pinfunction "DOUT_3") (pintype "output"))
      (node (ref "IC180") (pin "1") (pinfunction "DIN_1") (pintype "input"))
    )
    (net (code "237") (name "Net-(IC181-DOUT)") (class "Default")
      (node (ref "IC181") (pin "3") (pinfunction "DOUT_3") (pintype "output"))
      (node (ref "IC182") (pin "1") (pinfunction "DIN_1") (pintype "input"))
    )
    (net (code "238") (name "Net-(IC182-DOUT)") (class "Default")
      (node (ref "IC182") (pin "3") (pinfunction "DOUT_3") (pintype "output"))
      (node (ref "IC183") (pin "1") (pinfunction "DIN_1") (pintype "input"))
    )
    (net (code "239") (name "Net-(IC183-DOUT)") (class "Default")
      (node (ref "IC183") (pin "3") (pinfunction "DOUT_3") (pintype "output"))
      (node (ref "IC184") (pin "1") (pinfunction "DIN_1") (pintype "input"))
    )
    (net (code "240") (name "Net-(IC184-DOUT)") (class "Default")
      (node (ref "IC184") (pin "3") (pinfunction "DOUT_3") (pintype "output"))
      (node (ref "IC185") (pin "1") (pinfunction "DIN_1") (pintype "input"))
    )
    (net (code "241") (name "Net-(IC186-DOUT)") (class "Default")
      (node (ref "IC186") (pin "3") (pinfunction "DOUT_3") (pintype "output"))
      (node (ref "IC187") (pin "1") (pinfunction "DIN_1") (pintype "input"))
    )
    (net (code "242") (name "Net-(IC187-DOUT)") (class "Default")
      (node (ref "IC187") (pin "3") (pinfunction "DOUT_3") (pintype "output"))
      (node (ref "IC188") (pin "1") (pinfunction "DIN_1") (pintype "input"))
    )
    (net (code "243") (name "Net-(IC188-DOUT)") (class "Default")
      (node (ref "IC188") (pin "3") (pinfunction "DOUT_3") (pintype "output"))
      (node (ref "IC189") (pin "1") (pinfunction "DIN_1") (pintype "input"))
    )
    (net (code "244") (name "Net-(IC189-DOUT)") (class "Default")
      (node (ref "IC189") (pin "3") (pinfunction "DOUT_3") (pintype "output"))
      (node (ref "IC190") (pin "1") (pinfunction "DIN_1") (pintype "input"))
    )
    (net (code "245") (name "Net-(IC191-DOUT)") (class "Default")
      (node (ref "IC191") (pin "3") (pinfunction "DOUT_3") (pintype "output"))
      (node (ref "IC192") (pin "1") (pinfunction "DIN_1") (pintype "input"))
    )
    (net (code "246") (name "Net-(IC192-DOUT)") (class "Default")
      (node (ref "IC192") (pin "3") (pinfunction "DOUT_3") (pintype "output"))
      (node (ref "IC193") (pin "1") (pinfunction "DIN_1") (pintype "input"))
    )
    (net (code "247") (name "Net-(IC193-DOUT)") (class "Default")
      (node (ref "IC193") (pin "3") (pinfunction "DOUT_3") (pintype "output"))
      (node (ref "IC194") (pin "1") (pinfunction "DIN_1") (pintype "input"))
    )
    (net (code "248") (name "Net-(IC194-DOUT)") (class "Default")
      (node (ref "IC194") (pin "3") (pinfunction "DOUT_3") (pintype "output"))
      (node (ref "IC195") (pin "1") (pinfunction "DIN_1") (pintype "input"))
    )
    (net (code "249") (name "Net-(IC196-DOUT)") (class "Default")
      (node (ref "IC196") (pin "3") (pinfunction "DOUT_3") (pintype "output"))
      (node (ref "IC197") (pin "1") (pinfunction "DIN_1") (pintype "input"))
    )
    (net (code "250") (name "Net-(IC197-DOUT)") (class "Default")
      (node (ref "IC197") (pin "3") (pinfunction "DOUT_3") (pintype "output"))
      (node (ref "IC198") (pin "1") (pinfunction "DIN_1") (pintype "input"))
    )
    (net (code "251") (name "Net-(IC198-DOUT)") (class "Default")
      (node (ref "IC198") (pin "3") (pinfunction "DOUT_3") (pintype "output"))
      (node (ref "IC199") (pin "1") (pinfunction "DIN_1") (pintype "input"))
    )
    (net (code "252") (name "Net-(IC199-DOUT)") (class "Default")
      (node (ref "IC199") (pin "3") (pinfunction "DOUT_3") (pintype "output"))
      (node (ref "IC200") (pin "1") (pinfunction "DIN_1") (pintype "input"))
    )
    (net (code "253") (name "Net-(IC201-DOUT)") (class "Default")
      (node (ref "IC201") (pin "3") (pinfunction "DOUT_3") (pintype "output"))
      (node (ref "IC202") (pin "1") (pinfunction "DIN_1") (pintype "input"))
    )
    (net (code "254") (name "Net-(IC202-DOUT)") (class "Default")
      (node (ref "IC202") (pin "3") (pinfunction "DOUT_3") (pintype "output"))
      (node (ref "IC203") (pin "1") (pinfunction "DIN_1") (pintype "input"))
    )
    (net (code "255") (name "Net-(IC203-DOUT)") (class "Default")
      (node (ref "IC203") (pin "3") (pinfunction "DOUT_3") (pintype "output"))
      (node (ref "IC204") (pin "1") (pinfunction "DIN_1") (pintype "input"))
    )
    (net (code "256") (name "Net-(IC204-DOUT)") (class "Default")
      (node (ref "IC204") (pin "3") (pinfunction "DOUT_3") (pintype "output"))
      (node (ref "IC205") (pin "1") (pinfunction "DIN_1") (pintype "input"))
    )
    (net (code "257") (name "Net-(IC206-DOUT)") (class "Default")
      (node (ref "IC206") (pin "3") (pinfunction "DOUT_3") (pintype "output"))
      (node (ref "IC207") (pin "1") (pinfunction "DIN_1") (pintype "input"))
    )
    (net (code "258") (name "Net-(IC207-DOUT)") (class "Default")
      (node (ref "IC207") (pin "3") (pinfunction "DOUT_3") (pintype "output"))
      (node (ref "IC208") (pin "1") (pinfunction "DIN_1") (pintype "input"))
    )
    (net (code "259") (name "Net-(IC208-DOUT)") (class "Default")
      (node (ref "IC208") (pin "3") (pinfunction "DOUT_3") (pintype "output"))
      (node (ref "IC209") (pin "1") (pinfunction "DIN_1") (pintype "input"))
    )
    (net (code "260") (name "Net-(IC209-DOUT)") (class "Default")
      (node (ref "IC209") (pin "3") (pinfunction "DOUT_3") (pintype "output"))
      (node (ref "IC210") (pin "1") (pinfunction "DIN_1") (pintype "input"))
    )
    (net (code "261") (name "Net-(IC212-DOUT)") (class "Default")
      (node (ref "IC212") (pin "3") (pinfunction "DOUT_3") (pintype "output"))
      (node (ref "IC213") (pin "1") (pinfunction "DIN_1") (pintype "input"))
    )
    (net (code "262") (name "Net-(IC213-DOUT)") (class "Default")
      (node (ref "IC213") (pin "3") (pinfunction "DOUT_3") (pintype "output"))
      (node (ref "IC214") (pin "1") (pinfunction "DIN_1") (pintype "input"))
    )
    (net (code "263") (name "Net-(IC214-DOUT)") (class "Default")
      (node (ref "IC214") (pin "3") (pinfunction "DOUT_3") (pintype "output"))
      (node (ref "IC215") (pin "1") (pinfunction "DIN_1") (pintype "input"))
    )
    (net (code "264") (name "Net-(IC215-DOUT)") (class "Default")
      (node (ref "IC215") (pin "3") (pinfunction "DOUT_3") (pintype "output"))
      (node (ref "IC216") (pin "1") (pinfunction "DIN_1") (pintype "input"))
    )
    (net (code "265") (name "Net-(IC217-DOUT)") (class "Default")
      (node (ref "IC217") (pin "3") (pinfunction "DOUT_3") (pintype "output"))
      (node (ref "IC218") (pin "1") (pinfunction "DIN_1") (pintype "input"))
    )
    (net (code "266") (name "Net-(IC218-DOUT)") (class "Default")
      (node (ref "IC218") (pin "3") (pinfunction "DOUT_3") (pintype "output"))
      (node (ref "IC219") (pin "1") (pinfunction "DIN_1") (pintype "input"))
    )
    (net (code "267") (name "Net-(IC219-DOUT)") (class "Default")
      (node (ref "IC219") (pin "3") (pinfunction "DOUT_3") (pintype "output"))
      (node (ref "IC220") (pin "1") (pinfunction "DIN_1") (pintype "input"))
    )
    (net (code "268") (name "Net-(IC220-DOUT)") (class "Default")
      (node (ref "IC220") (pin "3") (pinfunction "DOUT_3") (pintype "output"))
      (node (ref "IC221") (pin "1") (pinfunction "DIN_1") (pintype "input"))
    )
    (net (code "269") (name "Net-(IC222-DOUT)") (class "Default")
      (node (ref "IC222") (pin "3") (pinfunction "DOUT_3") (pintype "output"))
      (node (ref "IC223") (pin "1") (pinfunction "DIN_1") (pintype "input"))
    )
    (net (code "270") (name "Net-(IC223-DOUT)") (class "Default")
      (node (ref "IC223") (pin "3") (pinfunction "DOUT_3") (pintype "output"))
      (node (ref "IC224") (pin "1") (pinfunction "DIN_1") (pintype "input"))
    )
    (net (code "271") (name "Net-(IC224-DOUT)") (class "Default")
      (node (ref "IC224") (pin "3") (pinfunction "DOUT_3") (pintype "output"))
      (node (ref "IC225") (pin "1") (pinfunction "DIN_1") (pintype "input"))
    )
    (net (code "272") (name "Net-(IC225-DOUT)") (class "Default")
      (node (ref "IC225") (pin "3") (pinfunction "DOUT_3") (pintype "output"))
      (node (ref "IC226") (pin "1") (pinfunction "DIN_1") (pintype "input"))
    )
    (net (code "273") (name "Net-(IC227-DOUT)") (class "Default")
      (node (ref "IC227") (pin "3") (pinfunction "DOUT_3") (pintype "output"))
      (node (ref "IC228") (pin "1") (pinfunction "DIN_1") (pintype "input"))
    )
    (net (code "274") (name "Net-(IC228-DOUT)") (class "Default")
      (node (ref "IC228") (pin "3") (pinfunction "DOUT_3") (pintype "output"))
      (node (ref "IC229") (pin "1") (pinfunction "DIN_1") (pintype "input"))
    )
    (net (code "275") (name "Net-(IC229-DOUT)") (class "Default")
      (node (ref "IC229") (pin "3") (pinfunction "DOUT_3") (pintype "output"))
      (node (ref "IC230") (pin "1") (pinfunction "DIN_1") (pintype "input"))
    )
    (net (code "276") (name "Net-(IC230-DOUT)") (class "Default")
      (node (ref "IC230") (pin "3") (pinfunction "DOUT_3") (pintype "output"))
      (node (ref "IC231") (pin "1") (pinfunction "DIN_1") (pintype "input"))
    )
    (net (code "277") (name "Net-(IC232-DOUT)") (class "Default")
      (node (ref "IC232") (pin "3") (pinfunction "DOUT_3") (pintype "output"))
      (node (ref "IC233") (pin "1") (pinfunction "DIN_1") (pintype "input"))
    )
    (net (code "278") (name "Net-(IC233-DOUT)") (class "Default")
      (node (ref "IC233") (pin "3") (pinfunction "DOUT_3") (pintype "output"))
      (node (ref "IC234") (pin "1") (pinfunction "DIN_1") (pintype "input"))
    )
    (net (code "279") (name "Net-(IC234-DOUT)") (class "Default")
      (node (ref "IC234") (pin "3") (pinfunction "DOUT_3") (pintype "output"))
      (node (ref "IC235") (pin "1") (pinfunction "DIN_1") (pintype "input"))
    )
    (net (code "280") (name "Net-(IC235-DOUT)") (class "Default")
      (node (ref "IC235") (pin "3") (pinfunction "DOUT_3") (pintype "output"))
      (node (ref "IC236") (pin "1") (pinfunction "DIN_1") (pintype "input"))
    )
    (net (code "281") (name "Net-(IC237-DOUT)") (class "Default")
      (node (ref "IC237") (pin "3") (pinfunction "DOUT_3") (pintype "output"))
      (node (ref "IC238") (pin "1") (pinfunction "DIN_1") (pintype "input"))
    )
    (net (code "282") (name "Net-(IC238-DOUT)") (class "Default")
      (node (ref "IC238") (pin "3") (pinfunction "DOUT_3") (pintype "output"))
      (node (ref "IC239") (pin "1") (pinfunction "DIN_1") (pintype "input"))
    )
    (net (code "283") (name "Net-(IC239-DOUT)") (class "Default")
      (node (ref "IC239") (pin "3") (pinfunction "DOUT_3") (pintype "output"))
      (node (ref "IC240") (pin "1") (pinfunction "DIN_1") (pintype "input"))
    )
    (net (code "284") (name "Net-(IC240-DOUT)") (class "Default")
      (node (ref "IC240") (pin "3") (pinfunction "DOUT_3") (pintype "output"))
      (node (ref "IC241") (pin "1") (pinfunction "DIN_1") (pintype "input"))
    )
    (net (code "285") (name "Net-(IC242-DOUT)") (class "Default")
      (node (ref "IC242") (pin "3") (pinfunction "DOUT_3") (pintype "output"))
      (node (ref "IC243") (pin "1") (pinfunction "DIN_1") (pintype "input"))
    )
    (net (code "286") (name "Net-(IC243-DOUT)") (class "Default")
      (node (ref "IC243") (pin "3") (pinfunction "DOUT_3") (pintype "output"))
      (node (ref "IC244") (pin "1") (pinfunction "DIN_1") (pintype "input"))
    )
    (net (code "287") (name "Net-(IC244-DOUT)") (class "Default")
      (node (ref "IC244") (pin "3") (pinfunction "DOUT_3") (pintype "output"))
      (node (ref "IC245") (pin "1") (pinfunction "DIN_1") (pintype "input"))
    )
    (net (code "288") (name "Net-(IC245-DOUT)") (class "Default")
      (node (ref "IC245") (pin "3") (pinfunction "DOUT_3") (pintype "output"))
      (node (ref "IC246") (pin "1") (pinfunction "DIN_1") (pintype "input"))
    )
    (net (code "289") (name "Net-(IC247-DOUT)") (class "Default")
      (node (ref "IC247") (pin "3") (pinfunction "DOUT_3") (pintype "output"))
      (node (ref "IC248") (pin "1") (pinfunction "DIN_1") (pintype "input"))
    )
    (net (code "290") (name "Net-(IC248-DOUT)") (class "Default")
      (node (ref "IC248") (pin "3") (pinfunction "DOUT_3") (pintype "output"))
      (node (ref "IC249") (pin "1") (pinfunction "DIN_1") (pintype "input"))
    )
    (net (code "291") (name "Net-(IC249-DOUT)") (class "Default")
      (node (ref "IC249") (pin "3") (pinfunction "DOUT_3") (pintype "output"))
      (node (ref "IC250") (pin "1") (pinfunction "DIN_1") (pintype "input"))
    )
    (net (code "292") (name "Net-(IC250-DOUT)") (class "Default")
      (node (ref "IC250") (pin "3") (pinfunction "DOUT_3") (pintype "output"))
      (node (ref "IC251") (pin "1") (pinfunction "DIN_1") (pintype "input"))
    )
    (net (code "293") (name "Net-(IC252-DOUT)") (class "Default")
      (node (ref "IC252") (pin "3") (pinfunction "DOUT_3") (pintype "output"))
      (node (ref "IC253") (pin "1") (pinfunction "DIN_1") (pintype "input"))
    )
    (net (code "294") (name "Net-(IC253-DOUT)") (class "Default")
      (node (ref "IC253") (pin "3") (pinfunction "DOUT_3") (pintype "output"))
      (node (ref "IC254") (pin "1") (pinfunction "DIN_1") (pintype "input"))
    )
    (net (code "295") (name "Net-(IC254-DOUT)") (class "Default")
      (node (ref "IC254") (pin "3") (pinfunction "DOUT_3") (pintype "output"))
      (node (ref "IC255") (pin "1") (pinfunction "DIN_1") (pintype "input"))
    )
    (net (code "296") (name "Net-(IC255-DOUT)") (class "Default")
      (node (ref "IC255") (pin "3") (pinfunction "DOUT_3") (pintype "output"))
      (node (ref "IC256") (pin "1") (pinfunction "DIN_1") (pintype "input"))
    )
    (net (code "297") (name "Net-(IC257-DOUT)") (class "Default")
      (node (ref "IC257") (pin "3") (pinfunction "DOUT_3") (pintype "output"))
      (node (ref "IC258") (pin "1") (pinfunction "DIN_1") (pintype "input"))
    )
    (net (code "298") (name "Net-(IC258-DOUT)") (class "Default")
      (node (ref "IC258") (pin "3") (pinfunction "DOUT_3") (pintype "output"))
      (node (ref "IC259") (pin "1") (pinfunction "DIN_1") (pintype "input"))
    )
    (net (code "299") (name "Net-(IC259-DOUT)") (class "Default")
      (node (ref "IC259") (pin "3") (pinfunction "DOUT_3") (pintype "output"))
      (node (ref "IC260") (pin "1") (pinfunction "DIN_1") (pintype "input"))
    )
    (net (code "300") (name "Net-(IC260-DOUT)") (class "Default")
      (node (ref "IC260") (pin "3") (pinfunction "DOUT_3") (pintype "output"))
      (node (ref "IC261") (pin "1") (pinfunction "DIN_1") (pintype "input"))
    )
    (net (code "301") (name "Net-(IC262-DOUT)") (class "Default")
      (node (ref "IC262") (pin "3") (pinfunction "DOUT_3") (pintype "output"))
      (node (ref "IC263") (pin "1") (pinfunction "DIN_1") (pintype "input"))
    )
    (net (code "302") (name "Net-(IC263-DOUT)") (class "Default")
      (node (ref "IC263") (pin "3") (pinfunction "DOUT_3") (pintype "output"))
      (node (ref "IC264") (pin "1") (pinfunction "DIN_1") (pintype "input"))
    )
    (net (code "303") (name "Net-(IC264-DOUT)") (class "Default")
      (node (ref "IC264") (pin "3") (pinfunction "DOUT_3") (pintype "output"))
      (node (ref "IC265") (pin "1") (pinfunction "DIN_1") (pintype "input"))
    )
    (net (code "304") (name "Net-(IC265-DOUT)") (class "Default")
      (node (ref "IC265") (pin "3") (pinfunction "DOUT_3") (pintype "output"))
      (node (ref "IC266") (pin "1") (pinfunction "DIN_1") (pintype "input"))
    )
    (net (code "305") (name "Net-(IC268-DOUT)") (class "Default")
      (node (ref "IC268") (pin "3") (pinfunction "DOUT_3") (pintype "output"))
      (node (ref "IC269") (pin "1") (pinfunction "DIN_1") (pintype "input"))
    )
    (net (code "306") (name "Net-(IC269-DOUT)") (class "Default")
      (node (ref "IC269") (pin "3") (pinfunction "DOUT_3") (pintype "output"))
      (node (ref "IC270") (pin "1") (pinfunction "DIN_1") (pintype "input"))
    )
    (net (code "307") (name "Net-(IC270-DOUT)") (class "Default")
      (node (ref "IC270") (pin "3") (pinfunction "DOUT_3") (pintype "output"))
      (node (ref "IC271") (pin "1") (pinfunction "DIN_1") (pintype "input"))
    )
    (net (code "308") (name "Net-(IC271-DOUT)") (class "Default")
      (node (ref "IC271") (pin "3") (pinfunction "DOUT_3") (pintype "output"))
      (node (ref "IC272") (pin "1") (pinfunction "DIN_1") (pintype "input"))
    )
    (net (code "309") (name "Net-(IC273-DOUT)") (class "Default")
      (node (ref "IC273") (pin "3") (pinfunction "DOUT_3") (pintype "output"))
      (node (ref "IC274") (pin "1") (pinfunction "DIN_1") (pintype "input"))
    )
    (net (code "310") (name "Net-(IC274-DOUT)") (class "Default")
      (node (ref "IC274") (pin "3") (pinfunction "DOUT_3") (pintype "output"))
      (node (ref "IC275") (pin "1") (pinfunction "DIN_1") (pintype "input"))
    )
    (net (code "311") (name "Net-(IC275-DOUT)") (class "Default")
      (node (ref "IC275") (pin "3") (pinfunction "DOUT_3") (pintype "output"))
      (node (ref "IC276") (pin "1") (pinfunction "DIN_1") (pintype "input"))
    )
    (net (code "312") (name "Net-(IC276-DOUT)") (class "Default")
      (node (ref "IC276") (pin "3") (pinfunction "DOUT_3") (pintype "output"))
      (node (ref "IC277") (pin "1") (pinfunction "DIN_1") (pintype "input"))
    )
    (net (code "313") (name "Net-(IC278-DOUT)") (class "Default")
      (node (ref "IC278") (pin "3") (pinfunction "DOUT_3") (pintype "output"))
      (node (ref "IC279") (pin "1") (pinfunction "DIN_1") (pintype "input"))
    )
    (net (code "314") (name "Net-(IC279-DOUT)") (class "Default")
      (node (ref "IC279") (pin "3") (pinfunction "DOUT_3") (pintype "output"))
      (node (ref "IC280") (pin "1") (pinfunction "DIN_1") (pintype "input"))
    )
    (net (code "315") (name "Net-(IC280-DOUT)") (class "Default")
      (node (ref "IC280") (pin "3") (pinfunction "DOUT_3") (pintype "output"))
      (node (ref "IC281") (pin "1") (pinfunction "DIN_1") (pintype "input"))
    )
    (net (code "316") (name "Net-(IC281-DOUT)") (class "Default")
      (node (ref "IC281") (pin "3") (pinfunction "DOUT_3") (pintype "output"))
      (node (ref "IC282") (pin "1") (pinfunction "DIN_1") (pintype "input"))
    )
    (net (code "317") (name "Net-(IC283-DOUT)") (class "Default")
      (node (ref "IC283") (pin "3") (pinfunction "DOUT_3") (pintype "output"))
      (node (ref "IC284") (pin "1") (pinfunction "DIN_1") (pintype "input"))
    )
    (net (code "318") (name "Net-(IC284-DOUT)") (class "Default")
      (node (ref "IC284") (pin "3") (pinfunction "DOUT_3") (pintype "output"))
      (node (ref "IC285") (pin "1") (pinfunction "DIN_1") (pintype "input"))
    )
    (net (code "319") (name "Net-(IC285-DOUT)") (class "Default")
      (node (ref "IC285") (pin "3") (pinfunction "DOUT_3") (pintype "output"))
      (node (ref "IC286") (pin "1") (pinfunction "DIN_1") (pintype "input"))
    )
    (net (code "320") (name "Net-(IC286-DOUT)") (class "Default")
      (node (ref "IC286") (pin "3") (pinfunction "DOUT_3") (pintype "output"))
      (node (ref "IC287") (pin "1") (pinfunction "DIN_1") (pintype "input"))
    )
    (net (code "321") (name "Net-(IC288-DOUT)") (class "Default")
      (node (ref "IC288") (pin "3") (pinfunction "DOUT_3") (pintype "output"))
      (node (ref "IC289") (pin "1") (pinfunction "DIN_1") (pintype "input"))
    )
    (net (code "322") (name "Net-(IC289-DOUT)") (class "Default")
      (node (ref "IC289") (pin "3") (pinfunction "DOUT_3") (pintype "output"))
      (node (ref "IC290") (pin "1") (pinfunction "DIN_1") (pintype "input"))
    )
    (net (code "323") (name "Net-(IC290-DOUT)") (class "Default")
      (node (ref "IC290") (pin "3") (pinfunction "DOUT_3") (pintype "output"))
      (node (ref "IC291") (pin "1") (pinfunction "DIN_1") (pintype "input"))
    )
    (net (code "324") (name "Net-(IC291-DOUT)") (class "Default")
      (node (ref "IC291") (pin "3") (pinfunction "DOUT_3") (pintype "output"))
      (node (ref "IC292") (pin "1") (pinfunction "DIN_1") (pintype "input"))
    )
    (net (code "325") (name "Net-(IC293-DOUT)") (class "Default")
      (node (ref "IC293") (pin "3") (pinfunction "DOUT_3") (pintype "output"))
      (node (ref "IC294") (pin "1") (pinfunction "DIN_1") (pintype "input"))
    )
    (net (code "326") (name "Net-(IC294-DOUT)") (class "Default")
      (node (ref "IC294") (pin "3") (pinfunction "DOUT_3") (pintype "output"))
      (node (ref "IC295") (pin "1") (pinfunction "DIN_1") (pintype "input"))
    )
    (net (code "327") (name "Net-(IC295-DOUT)") (class "Default")
      (node (ref "IC295") (pin "3") (pinfunction "DOUT_3") (pintype "output"))
      (node (ref "IC296") (pin "1") (pinfunction "DIN_1") (pintype "input"))
    )
    (net (code "328") (name "Net-(IC296-DOUT)") (class "Default")
      (node (ref "IC296") (pin "3") (pinfunction "DOUT_3") (pintype "output"))
      (node (ref "IC297") (pin "1") (pinfunction "DIN_1") (pintype "input"))
    )
    (net (code "329") (name "Net-(IC298-DOUT)") (class "Default")
      (node (ref "IC298") (pin "3") (pinfunction "DOUT_3") (pintype "output"))
      (node (ref "IC299") (pin "1") (pinfunction "DIN_1") (pintype "input"))
    )
    (net (code "330") (name "Net-(IC299-DOUT)") (class "Default")
      (node (ref "IC299") (pin "3") (pinfunction "DOUT_3") (pintype "output"))
      (node (ref "IC300") (pin "1") (pinfunction "DIN_1") (pintype "input"))
    )
    (net (code "331") (name "Net-(IC300-DOUT)") (class "Default")
      (node (ref "IC300") (pin "3") (pinfunction "DOUT_3") (pintype "output"))
      (node (ref "IC301") (pin "1") (pinfunction "DIN_1") (pintype "input"))
    )
    (net (code "332") (name "Net-(IC301-DOUT)") (class "Default")
      (node (ref "IC301") (pin "3") (pinfunction "DOUT_3") (pintype "output"))
      (node (ref "IC302") (pin "1") (pinfunction "DIN_1") (pintype "input"))
    )
    (net (code "333") (name "Net-(IC303-DOUT)") (class "Default")
      (node (ref "IC303") (pin "3") (pinfunction "DOUT_3") (pintype "output"))
      (node (ref "IC304") (pin "1") (pinfunction "DIN_1") (pintype "input"))
    )
    (net (code "334") (name "Net-(IC304-DOUT)") (class "Default")
      (node (ref "IC304") (pin "3") (pinfunction "DOUT_3") (pintype "output"))
      (node (ref "IC305") (pin "1") (pinfunction "DIN_1") (pintype "input"))
    )
    (net (code "335") (name "Net-(IC305-DOUT)") (class "Default")
      (node (ref "IC305") (pin "3") (pinfunction "DOUT_3") (pintype "output"))
      (node (ref "IC306") (pin "1") (pinfunction "DIN_1") (pintype "input"))
    )
    (net (code "336") (name "Net-(IC306-DOUT)") (class "Default")
      (node (ref "IC306") (pin "3") (pinfunction "DOUT_3") (pintype "output"))
      (node (ref "IC307") (pin "1") (pinfunction "DIN_1") (pintype "input"))
    )
    (net (code "337") (name "Net-(IC308-DOUT)") (class "Default")
      (node (ref "IC308") (pin "3") (pinfunction "DOUT_3") (pintype "output"))
      (node (ref "IC309") (pin "1") (pinfunction "DIN_1") (pintype "input"))
    )
    (net (code "338") (name "Net-(IC309-DOUT)") (class "Default")
      (node (ref "IC309") (pin "3") (pinfunction "DOUT_3") (pintype "output"))
      (node (ref "IC310") (pin "1") (pinfunction "DIN_1") (pintype "input"))
    )
    (net (code "339") (name "Net-(IC310-DOUT)") (class "Default")
      (node (ref "IC310") (pin "3") (pinfunction "DOUT_3") (pintype "output"))
      (node (ref "IC311") (pin "1") (pinfunction "DIN_1") (pintype "input"))
    )
    (net (code "340") (name "Net-(IC311-DOUT)") (class "Default")
      (node (ref "IC311") (pin "3") (pinfunction "DOUT_3") (pintype "output"))
      (node (ref "IC312") (pin "1") (pinfunction "DIN_1") (pintype "input"))
    )
    (net (code "341") (name "Net-(IC313-DOUT)") (class "Default")
      (node (ref "IC313") (pin "3") (pinfunction "DOUT_3") (pintype "output"))
      (node (ref "IC314") (pin "1") (pinfunction "DIN_1") (pintype "input"))
    )
    (net (code "342") (name "Net-(IC314-DOUT)") (class "Default")
      (node (ref "IC314") (pin "3") (pinfunction "DOUT_3") (pintype "output"))
      (node (ref "IC315") (pin "1") (pinfunction "DIN_1") (pintype "input"))
    )
    (net (code "343") (name "Net-(IC315-DOUT)") (class "Default")
      (node (ref "IC315") (pin "3") (pinfunction "DOUT_3") (pintype "output"))
      (node (ref "IC316") (pin "1") (pinfunction "DIN_1") (pintype "input"))
    )
    (net (code "344") (name "Net-(IC316-DOUT)") (class "Default")
      (node (ref "IC316") (pin "3") (pinfunction "DOUT_3") (pintype "output"))
      (node (ref "IC317") (pin "1") (pinfunction "DIN_1") (pintype "input"))
    )
    (net (code "345") (name "Net-(IC318-DOUT)") (class "Default")
      (node (ref "IC318") (pin "3") (pinfunction "DOUT_3") (pintype "output"))
      (node (ref "IC319") (pin "1") (pinfunction "DIN_1") (pintype "input"))
    )
    (net (code "346") (name "Net-(IC319-DOUT)") (class "Default")
      (node (ref "IC319") (pin "3") (pinfunction "DOUT_3") (pintype "output"))
      (node (ref "IC320") (pin "1") (pinfunction "DIN_1") (pintype "input"))
    )
    (net (code "347") (name "Net-(IC320-DOUT)") (class "Default")
      (node (ref "IC320") (pin "3") (pinfunction "DOUT_3") (pintype "output"))
      (node (ref "IC321") (pin "1") (pinfunction "DIN_1") (pintype "input"))
    )
    (net (code "348") (name "Net-(IC321-DOUT)") (class "Default")
      (node (ref "IC321") (pin "3") (pinfunction "DOUT_3") (pintype "output"))
      (node (ref "IC322") (pin "1") (pinfunction "DIN_1") (pintype "input"))
    )
    (net (code "349") (name "Net-(IC324-DOUT)") (class "Default")
      (node (ref "IC324") (pin "3") (pinfunction "DOUT_3") (pintype "output"))
      (node (ref "IC325") (pin "1") (pinfunction "DIN_1") (pintype "input"))
    )
    (net (code "350") (name "Net-(IC325-DOUT)") (class "Default")
      (node (ref "IC325") (pin "3") (pinfunction "DOUT_3") (pintype "output"))
      (node (ref "IC326") (pin "1") (pinfunction "DIN_1") (pintype "input"))
    )
    (net (code "351") (name "Net-(IC326-DOUT)") (class "Default")
      (node (ref "IC326") (pin "3") (pinfunction "DOUT_3") (pintype "output"))
      (node (ref "IC327") (pin "1") (pinfunction "DIN_1") (pintype "input"))
    )
    (net (code "352") (name "Net-(IC327-DOUT)") (class "Default")
      (node (ref "IC327") (pin "3") (pinfunction "DOUT_3") (pintype "output"))
      (node (ref "IC328") (pin "1") (pinfunction "DIN_1") (pintype "input"))
    )
    (net (code "353") (name "Net-(IC329-DOUT)") (class "Default")
      (node (ref "IC329") (pin "3") (pinfunction "DOUT_3") (pintype "output"))
      (node (ref "IC330") (pin "1") (pinfunction "DIN_1") (pintype "input"))
    )
    (net (code "354") (name "Net-(IC330-DOUT)") (class "Default")
      (node (ref "IC330") (pin "3") (pinfunction "DOUT_3") (pintype "output"))
      (node (ref "IC331") (pin "1") (pinfunction "DIN_1") (pintype "input"))
    )
    (net (code "355") (name "Net-(IC331-DOUT)") (class "Default")
      (node (ref "IC331") (pin "3") (pinfunction "DOUT_3") (pintype "output"))
      (node (ref "IC332") (pin "1") (pinfunction "DIN_1") (pintype "input"))
    )
    (net (code "356") (name "Net-(R47-Pad2)") (class "Default")
      (node (ref "R47") (pin "2") (pinfunction "2_2") (pintype "passive"))
      (node (ref "X5") (pin "11") (pinfunction "11_11") (pintype "passive"))
    )
    (net (code "357") (name "Net-(R87-Pad1)") (class "Default")
      (node (ref "R87") (pin "1") (pinfunction "1_1") (pintype "passive"))
      (node (ref "X4") (pin "7") (pinfunction "7_7") (pintype "passive"))
    )
    (net (code "358") (name "Net-(T2-D)") (class "Default")
      (node (ref "D306") (pin "C") (pinfunction "C_C") (pintype "passive"))
      (node (ref "D308") (pin "C") (pinfunction "C_C") (pintype "passive"))
      (node (ref "T2") (pin "3") (pinfunction "D_3") (pintype "passive"))
    )
    (net (code "359") (name "Net-(T2-G)") (class "Default")
      (node (ref "R21") (pin "2") (pinfunction "2_2") (pintype "passive"))
      (node (ref "T2") (pin "1") (pinfunction "G_1") (pintype "passive"))
      (node (ref "TP15") (pin "TP") (pinfunction "TP_TP") (pintype "input"))
    )
    (net (code "360") (name "Net-(T3-D)") (class "Default")
      (node (ref "D200") (pin "C") (pinfunction "C_C") (pintype "passive"))
      (node (ref "D207") (pin "C") (pinfunction "C_C") (pintype "passive"))
      (node (ref "T3") (pin "3") (pinfunction "D_3") (pintype "passive"))
    )
    (net (code "361") (name "Net-(T3-G)") (class "Default")
      (node (ref "R23") (pin "2") (pinfunction "2_2") (pintype "passive"))
      (node (ref "T3") (pin "1") (pinfunction "G_1") (pintype "passive"))
      (node (ref "TP6") (pin "TP") (pinfunction "TP_TP") (pintype "input"))
    )
    (net (code "362") (name "Net-(T6-D)") (class "Default")
      (node (ref "D356") (pin "C") (pinfunction "C_C") (pintype "passive"))
      (node (ref "D358") (pin "C") (pinfunction "C_C") (pintype "passive"))
      (node (ref "T6") (pin "3") (pinfunction "D_3") (pintype "passive"))
    )
    (net (code "363") (name "Net-(T6-G)") (class "Default")
      (node (ref "R54") (pin "2") (pinfunction "2_2") (pintype "passive"))
      (node (ref "T6") (pin "1") (pinfunction "G_1") (pintype "passive"))
    )
    (net (code "364") (name "Net-(T7-D)") (class "Default")
      (node (ref "D250") (pin "C") (pinfunction "C_C") (pintype "passive"))
      (node (ref "D257") (pin "C") (pinfunction "C_C") (pintype "passive"))
      (node (ref "T7") (pin "3") (pinfunction "D_3") (pintype "passive"))
    )
    (net (code "365") (name "Net-(T7-G)") (class "Default")
      (node (ref "R59") (pin "2") (pinfunction "2_2") (pintype "passive"))
      (node (ref "T7") (pin "1") (pinfunction "G_1") (pintype "passive"))
      (node (ref "TP16") (pin "TP") (pinfunction "TP_TP") (pintype "input"))
    )
    (net (code "366") (name "Net-(T10-D)") (class "Default")
      (node (ref "D105") (pin "1") (pinfunction "C_1") (pintype "passive"))
      (node (ref "D105") (pin "4") (pinfunction "C_4") (pintype "passive"))
      (node (ref "T10") (pin "3") (pinfunction "D_3") (pintype "passive"))
    )
    (net (code "367") (name "Net-(T10-G)") (class "Default")
      (node (ref "R80") (pin "2") (pinfunction "2_2") (pintype "passive"))
      (node (ref "T10") (pin "1") (pinfunction "G_1") (pintype "passive"))
    )
    (net (code "368") (name "PVCC_DISABLE") (class "Default")
      (node (ref "R56") (pin "2") (pinfunction "2_2") (pintype "passive"))
      (node (ref "R64") (pin "1") (pinfunction "1_1") (pintype "passive"))
      (node (ref "R67") (pin "1") (pinfunction "1_1") (pintype "passive"))
      (node (ref "TP12") (pin "TP") (pinfunction "TP_TP") (pintype "input"))
    )
    (net (code "369") (name "RBG_DOUT_END") (class "Default")
      (node (ref "IC323") (pin "3") (pinfunction "DOUT_3") (pintype "output"))
      (node (ref "TP9") (pin "TP") (pinfunction "TP_TP") (pintype "input"))
    )
    (net (code "370") (name "RGB_DOUT_4") (class "Default")
      (node (ref "IC104") (pin "3") (pinfunction "DOUT_3") (pintype "output"))
      (node (ref "IC105") (pin "1") (pinfunction "DIN_1") (pintype "input"))
    )
    (net (code "371") (name "RGB_DOUT_9") (class "Default")
      (node (ref "IC109") (pin "3") (pinfunction "DOUT_3") (pintype "output"))
      (node (ref "IC110") (pin "1") (pinfunction "DIN_1") (pintype "input"))
    )
    (net (code "372") (name "RGB_DOUT_14") (class "Default")
      (node (ref "IC114") (pin "3") (pinfunction "DOUT_3") (pintype "output"))
      (node (ref "IC115") (pin "1") (pinfunction "DIN_1") (pintype "input"))
    )
    (net (code "373") (name "RGB_DOUT_19") (class "Default")
      (node (ref "IC119") (pin "3") (pinfunction "DOUT_3") (pintype "output"))
      (node (ref "IC120") (pin "1") (pinfunction "DIN_1") (pintype "input"))
    )
    (net (code "374") (name "RGB_DOUT_24") (class "Default")
      (node (ref "IC124") (pin "3") (pinfunction "DOUT_3") (pintype "output"))
      (node (ref "IC125") (pin "1") (pinfunction "DIN_1") (pintype "input"))
    )
    (net (code "375") (name "RGB_DOUT_29") (class "Default")
      (node (ref "IC129") (pin "3") (pinfunction "DOUT_3") (pintype "output"))
      (node (ref "IC130") (pin "1") (pinfunction "DIN_1") (pintype "input"))
    )
    (net (code "376") (name "RGB_DOUT_34") (class "Default")
      (node (ref "IC134") (pin "3") (pinfunction "DOUT_3") (pintype "output"))
      (node (ref "IC135") (pin "1") (pinfunction "DIN_1") (pintype "input"))
    )
    (net (code "377") (name "RGB_DOUT_39") (class "Default")
      (node (ref "IC139") (pin "3") (pinfunction "DOUT_3") (pintype "output"))
      (node (ref "IC140") (pin "1") (pinfunction "DIN_1") (pintype "input"))
    )
    (net (code "378") (name "RGB_DOUT_44") (class "Default")
      (node (ref "IC144") (pin "3") (pinfunction "DOUT_3") (pintype "output"))
      (node (ref "IC145") (pin "1") (pinfunction "DIN_1") (pintype "input"))
    )
    (net (code "379") (name "RGB_DOUT_49") (class "Default")
      (node (ref "IC149") (pin "3") (pinfunction "DOUT_3") (pintype "output"))
      (node (ref "IC150") (pin "1") (pinfunction "DIN_1") (pintype "input"))
    )
    (net (code "380") (name "RGB_DOUT_54") (class "Default")
      (node (ref "IC154") (pin "3") (pinfunction "DOUT_3") (pintype "output"))
      (node (ref "IC155") (pin "1") (pinfunction "DIN_1") (pintype "input"))
    )
    (net (code "381") (name "RGB_DOUT_55") (class "Default")
      (node (ref "IC155") (pin "3") (pinfunction "DOUT_3") (pintype "output"))
      (node (ref "IC156") (pin "1") (pinfunction "DIN_1") (pintype "input"))
    )
    (net (code "382") (name "RGB_DOUT_60") (class "Default")
      (node (ref "IC160") (pin "3") (pinfunction "DOUT_3") (pintype "output"))
      (node (ref "IC161") (pin "1") (pinfunction "DIN_1") (pintype "input"))
    )
    (net (code "383") (name "RGB_DOUT_65") (class "Default")
      (node (ref "IC165") (pin "3") (pinfunction "DOUT_3") (pintype "output"))
      (node (ref "IC166") (pin "1") (pinfunction "DIN_1") (pintype "input"))
    )
    (net (code "384") (name "RGB_DOUT_70") (class "Default")
      (node (ref "IC170") (pin "3") (pinfunction "DOUT_3") (pintype "output"))
      (node (ref "IC171") (pin "1") (pinfunction "DIN_1") (pintype "input"))
    )
    (net (code "385") (name "RGB_DOUT_75") (class "Default")
      (node (ref "IC175") (pin "3") (pinfunction "DOUT_3") (pintype "output"))
      (node (ref "IC176") (pin "1") (pinfunction "DIN_1") (pintype "input"))
    )
    (net (code "386") (name "RGB_DOUT_80") (class "Default")
      (node (ref "IC180") (pin "3") (pinfunction "DOUT_3") (pintype "output"))
      (node (ref "IC181") (pin "1") (pinfunction "DIN_1") (pintype "input"))
    )
    (net (code "387") (name "RGB_DOUT_85") (class "Default")
      (node (ref "IC185") (pin "3") (pinfunction "DOUT_3") (pintype "output"))
      (node (ref "IC186") (pin "1") (pinfunction "DIN_1") (pintype "input"))
    )
    (net (code "388") (name "RGB_DOUT_90") (class "Default")
      (node (ref "IC190") (pin "3") (pinfunction "DOUT_3") (pintype "output"))
      (node (ref "IC191") (pin "1") (pinfunction "DIN_1") (pintype "input"))
    )
    (net (code "389") (name "RGB_DOUT_95") (class "Default")
      (node (ref "IC195") (pin "3") (pinfunction "DOUT_3") (pintype "output"))
      (node (ref "IC196") (pin "1") (pinfunction "DIN_1") (pintype "input"))
    )
    (net (code "390") (name "RGB_DOUT_100") (class "Default")
      (node (ref "IC200") (pin "3") (pinfunction "DOUT_3") (pintype "output"))
      (node (ref "IC201") (pin "1") (pinfunction "DIN_1") (pintype "input"))
    )
    (net (code "391") (name "RGB_DOUT_105") (class "Default")
      (node (ref "IC205") (pin "3") (pinfunction "DOUT_3") (pintype "output"))
      (node (ref "IC206") (pin "1") (pinfunction "DIN_1") (pintype "input"))
    )
    (net (code "392") (name "RGB_DOUT_110") (class "Default")
      (node (ref "IC210") (pin "3") (pinfunction "DOUT_3") (pintype "output"))
      (node (ref "IC211") (pin "1") (pinfunction "DIN_1") (pintype "input"))
    )
    (net (code "393") (name "RGB_DOUT_111") (class "Default")
      (node (ref "IC211") (pin "3") (pinfunction "DOUT_3") (pintype "output"))
      (node (ref "IC212") (pin "1") (pinfunction "DIN_1") (pintype "input"))
    )
    (net (code "394") (name "RGB_DOUT_116") (class "Default")
      (node (ref "IC216") (pin "3") (pinfunction "DOUT_3") (pintype "output"))
      (node (ref "IC217") (pin "1") (pinfunction "DIN_1") (pintype "input"))
    )
    (net (code "395") (name "RGB_DOUT_121") (class "Default")
      (node (ref "IC221") (pin "3") (pinfunction "DOUT_3") (pintype "output"))
      (node (ref "IC222") (pin "1") (pinfunction "DIN_1") (pintype "input"))
    )
    (net (code "396") (name "RGB_DOUT_126") (class "Default")
      (node (ref "IC226") (pin "3") (pinfunction "DOUT_3") (pintype "output"))
      (node (ref "IC227") (pin "1") (pinfunction "DIN_1") (pintype "input"))
    )
    (net (code "397") (name "RGB_DOUT_131") (class "Default")
      (node (ref "IC231") (pin "3") (pinfunction "DOUT_3") (pintype "output"))
      (node (ref "IC232") (pin "1") (pinfunction "DIN_1") (pintype "input"))
    )
    (net (code "398") (name "RGB_DOUT_136") (class "Default")
      (node (ref "IC236") (pin "3") (pinfunction "DOUT_3") (pintype "output"))
      (node (ref "IC237") (pin "1") (pinfunction "DIN_1") (pintype "input"))
    )
    (net (code "399") (name "RGB_DOUT_141") (class "Default")
      (node (ref "IC241") (pin "3") (pinfunction "DOUT_3") (pintype "output"))
      (node (ref "IC242") (pin "1") (pinfunction "DIN_1") (pintype "input"))
    )
    (net (code "400") (name "RGB_DOUT_146") (class "Default")
      (node (ref "IC246") (pin "3") (pinfunction "DOUT_3") (pintype "output"))
      (node (ref "IC247") (pin "1") (pinfunction "DIN_1") (pintype "input"))
    )
    (net (code "401") (name "RGB_DOUT_151") (class "Default")
      (node (ref "IC251") (pin "3") (pinfunction "DOUT_3") (pintype "output"))
      (node (ref "IC252") (pin "1") (pinfunction "DIN_1") (pintype "input"))
    )
    (net (code "402") (name "RGB_DOUT_156") (class "Default")
      (node (ref "IC256") (pin "3") (pinfunction "DOUT_3") (pintype "output"))
      (node (ref "IC257") (pin "1") (pinfunction "DIN_1") (pintype "input"))
    )
    (net (code "403") (name "RGB_DOUT_161") (class "Default")
      (node (ref "IC261") (pin "3") (pinfunction "DOUT_3") (pintype "output"))
      (node (ref "IC262") (pin "1") (pinfunction "DIN_1") (pintype "input"))
    )
    (net (code "404") (name "RGB_DOUT_166") (class "Default")
      (node (ref "IC266") (pin "3") (pinfunction "DOUT_3") (pintype "output"))
      (node (ref "IC267") (pin "1") (pinfunction "DIN_1") (pintype "input"))
    )
    (net (code "405") (name "RGB_DOUT_167") (class "Default")
      (node (ref "IC267") (pin "3") (pinfunction "DOUT_3") (pintype "output"))
      (node (ref "IC268") (pin "1") (pinfunction "DIN_1") (pintype "input"))
    )
    (net (code "406") (name "RGB_DOUT_172") (class "Default")
      (node (ref "IC272") (pin "3") (pinfunction "DOUT_3") (pintype "output"))
      (node (ref "IC273") (pin "1") (pinfunction "DIN_1") (pintype "input"))
    )
    (net (code "407") (name "RGB_DOUT_177") (class "Default")
      (node (ref "IC277") (pin "3") (pinfunction "DOUT_3") (pintype "output"))
      (node (ref "IC278") (pin "1") (pinfunction "DIN_1") (pintype "input"))
    )
    (net (code "408") (name "RGB_DOUT_182") (class "Default")
      (node (ref "IC282") (pin "3") (pinfunction "DOUT_3") (pintype "output"))
      (node (ref "IC283") (pin "1") (pinfunction "DIN_1") (pintype "input"))
    )
    (net (code "409") (name "RGB_DOUT_187") (class "Default")
      (node (ref "IC287") (pin "3") (pinfunction "DOUT_3") (pintype "output"))
      (node (ref "IC288") (pin "1") (pinfunction "DIN_1") (pintype "input"))
    )
    (net (code "410") (name "RGB_DOUT_192") (class "Default")
      (node (ref "IC292") (pin "3") (pinfunction "DOUT_3") (pintype "output"))
      (node (ref "IC293") (pin "1") (pinfunction "DIN_1") (pintype "input"))
    )
    (net (code "411") (name "RGB_DOUT_197") (class "Default")
      (node (ref "IC297") (pin "3") (pinfunction "DOUT_3") (pintype "output"))
      (node (ref "IC298") (pin "1") (pinfunction "DIN_1") (pintype "input"))
    )
    (net (code "412") (name "RGB_DOUT_202") (class "Default")
      (node (ref "IC302") (pin "3") (pinfunction "DOUT_3") (pintype "output"))
      (node (ref "IC303") (pin "1") (pinfunction "DIN_1") (pintype "input"))
    )
    (net (code "413") (name "RGB_DOUT_207") (class "Default")
      (node (ref "IC307") (pin "3") (pinfunction "DOUT_3") (pintype "output"))
      (node (ref "IC308") (pin "1") (pinfunction "DIN_1") (pintype "input"))
    )
    (net (code "414") (name "RGB_DOUT_212") (class "Default")
      (node (ref "IC312") (pin "3") (pinfunction "DOUT_3") (pintype "output"))
      (node (ref "IC313") (pin "1") (pinfunction "DIN_1") (pintype "input"))
    )
    (net (code "415") (name "RGB_DOUT_217") (class "Default")
      (node (ref "IC317") (pin "3") (pinfunction "DOUT_3") (pintype "output"))
      (node (ref "IC318") (pin "1") (pinfunction "DIN_1") (pintype "input"))
    )
    (net (code "416") (name "RGB_DOUT_222") (class "Default")
      (node (ref "IC322") (pin "3") (pinfunction "DOUT_3") (pintype "output"))
      (node (ref "IC323") (pin "1") (pinfunction "DIN_1") (pintype "input"))
    )
    (net (code "417") (name "RGB_DOUT_228") (class "Default")
      (node (ref "IC328") (pin "3") (pinfunction "DOUT_3") (pintype "output"))
      (node (ref "IC329") (pin "1") (pinfunction "DIN_1") (pintype "input"))
    )
    (net (code "418") (name "RGB_DOUT_232") (class "Default")
      (node (ref "IC100") (pin "1") (pinfunction "DIN_1") (pintype "input"))
      (node (ref "IC332") (pin "3") (pinfunction "DOUT_3") (pintype "output"))
    )
    (net (code "419") (name "RGB_LED_UC->FU_5V") (class "Default")
      (node (ref "C10") (pin "1") (pinfunction "1_1") (pintype "passive"))
      (node (ref "IC17") (pin "4") (pinfunction "I/O3_4") (pintype "passive"))
      (node (ref "IC324") (pin "1") (pinfunction "DIN_1") (pintype "input"))
      (node (ref "TP8") (pin "TP") (pinfunction "TP_TP") (pintype "input"))
      (node (ref "X1") (pin "24") (pinfunction "24_24") (pintype "passive"))
    )
    (net (code "420") (name "UC_CAM3_TOF_TRIGGER_TO_SENSOR_1V8") (class "Default")
      (node (ref "IC16") (pin "1") (pinfunction "I/O1_1") (pintype "passive"))
      (node (ref "X2") (pin "26") (pinfunction "26_26") (pintype "passive"))
      (node (ref "X5") (pin "18") (pinfunction "18_18") (pintype "passive"))
    )
    (net (code "421") (name "UC_FU_740NM_3V3") (class "Default")
      (node (ref "IC13") (pin "3") (pinfunction "IN+_3") (pintype "input"))
      (node (ref "IC14") (pin "1") (pinfunction "I/O1_1") (pintype "passive"))
      (node (ref "TP19") (pin "TP") (pinfunction "TP_TP") (pintype "input"))
      (node (ref "X1") (pin "35") (pinfunction "35_35") (pintype "passive"))
    )
    (net (code "422") (name "UC_FU_850NM_LEFT_3V3") (class "Default")
      (node (ref "IC17") (pin "3") (pinfunction "I/O2_3") (pintype "passive"))
      (node (ref "IC2") (pin "3") (pinfunction "IN+_3") (pintype "input"))
      (node (ref "R12") (pin "1") (pinfunction "1_1") (pintype "passive"))
      (node (ref "R5") (pin "2") (pinfunction "2_2") (pintype "passive"))
      (node (ref "TP20") (pin "TP") (pinfunction "TP_TP") (pintype "input"))
      (node (ref "X1") (pin "37") (pinfunction "37_37") (pintype "passive"))
    )
    (net (code "423") (name "UC_FU_850NM_RIGHT_3V3") (class "Default")
      (node (ref "IC10") (pin "3") (pinfunction "IN+_3") (pintype "input"))
      (node (ref "IC20") (pin "3") (pinfunction "I/O2_3") (pintype "passive"))
      (node (ref "R13") (pin "1") (pinfunction "1_1") (pintype "passive"))
      (node (ref "R6") (pin "2") (pinfunction "2_2") (pintype "passive"))
      (node (ref "TP21") (pin "TP") (pinfunction "TP_TP") (pintype "input"))
      (node (ref "X2") (pin "12") (pinfunction "12_12") (pintype "passive"))
    )
    (net (code "424") (name "UC_FU_940NM_LEFT_3V3") (class "Default")
      (node (ref "IC1") (pin "3") (pinfunction "IN+_3") (pintype "input"))
      (node (ref "IC17") (pin "1") (pinfunction "I/O1_1") (pintype "passive"))
      (node (ref "R10") (pin "1") (pinfunction "1_1") (pintype "passive"))
      (node (ref "R3") (pin "2") (pinfunction "2_2") (pintype "passive"))
      (node (ref "R50") (pin "1") (pinfunction "1_1") (pintype "passive"))
      (node (ref "TP14") (pin "TP") (pinfunction "TP_TP") (pintype "input"))
      (node (ref "X1") (pin "38") (pinfunction "38_38") (pintype "passive"))
    )
    (net (code "425") (name "UC_FU_940NM_RIGHT_3V3") (class "Default")
      (node (ref "IC20") (pin "1") (pinfunction "I/O1_1") (pintype "passive"))
      (node (ref "IC8") (pin "3") (pinfunction "IN+_3") (pintype "input"))
      (node (ref "R11") (pin "1") (pinfunction "1_1") (pintype "passive"))
      (node (ref "R4") (pin "2") (pinfunction "2_2") (pintype "passive"))
      (node (ref "TP17") (pin "TP") (pinfunction "TP_TP") (pintype "input"))
      (node (ref "X2") (pin "14") (pinfunction "14_14") (pintype "passive"))
    )
    (net (code "426") (name "unconnected-(IC4B-OUT-Pad7)") (class "Default")
      (node (ref "IC4") (pin "7") (pinfunction "OUT_7") (pintype "output"))
    )
    (net (code "427") (name "unconnected-(IC6A-A-Pad1)") (class "Default")
      (node (ref "IC6") (pin "1") (pinfunction "A_1") (pintype "passive"))
    )
    (net (code "428") (name "unconnected-(IC7-DNC-Pad8)") (class "Default")
      (node (ref "IC7") (pin "8") (pinfunction "DNC_8") (pintype "output"))
    )
    (net (code "429") (name "unconnected-(IC7-GPIO1-Pad7)") (class "Default")
      (node (ref "IC7") (pin "7") (pinfunction "GPIO1_7") (pintype "open_collector"))
    )
    (net (code "430") (name "unconnected-(IC9B-Q-Pad9)") (class "Default")
      (node (ref "IC9") (pin "9") (pinfunction "Q_9") (pintype "output"))
    )
    (net (code "431") (name "unconnected-(IC9B-~{Q}-Pad7)") (class "Default")
      (node (ref "IC9") (pin "7") (pinfunction "~{Q}_7") (pintype "output"))
    )
    (net (code "432") (name "unconnected-(IC15-ALERT-Pad3)") (class "Default")
      (node (ref "IC15") (pin "3") (pinfunction "ALERT_3") (pintype "open_collector"))
    )
    (net (code "433") (name "unconnected-(IC16-I{slash}O2-Pad3)") (class "Default")
      (node (ref "IC16") (pin "3") (pinfunction "I/O2_3") (pintype "passive"))
    )
    (net (code "434") (name "unconnected-(IC16-I{slash}O3-Pad4)") (class "Default")
      (node (ref "IC16") (pin "4") (pinfunction "I/O3_4") (pintype "passive"))
    )
    (net (code "435") (name "unconnected-(IC16-I{slash}O4-Pad6)") (class "Default")
      (node (ref "IC16") (pin "6") (pinfunction "I/O4_6") (pintype "passive"))
    )
    (net (code "436") (name "unconnected-(IC17-I{slash}O4-Pad6)") (class "Default")
      (node (ref "IC17") (pin "6") (pinfunction "I/O4_6") (pintype "passive"))
    )
    (net (code "437") (name "unconnected-(IC23-S1B-Pad11)") (class "Default")
      (node (ref "IC23") (pin "11") (pinfunction "S1B_11") (pintype "passive"))
    )
    (net (code "438") (name "unconnected-(IC23-S2B-Pad10)") (class "Default")
      (node (ref "IC23") (pin "10") (pinfunction "S2B_10") (pintype "passive"))
    )
    (net (code "439") (name "unconnected-(IC23-S3A-Pad4)") (class "Default")
      (node (ref "IC23") (pin "4") (pinfunction "S3A_4") (pintype "passive"))
    )
    (net (code "440") (name "unconnected-(IC23-S3B-Pad9)") (class "Default")
      (node (ref "IC23") (pin "9") (pinfunction "S3B_9") (pintype "passive"))
    )
    (net (code "441") (name "unconnected-(IC23-S4A-Pad5)") (class "Default")
      (node (ref "IC23") (pin "5") (pinfunction "S4A_5") (pintype "passive"))
    )
    (net (code "442") (name "unconnected-(IC23-S4B-Pad8)") (class "Default")
      (node (ref "IC23") (pin "8") (pinfunction "S4B_8") (pintype "passive"))
    )
    (net (code "443") (name "unconnected-(IC24-ALERT-Pad3)") (class "Default")
      (node (ref "IC24") (pin "3") (pinfunction "ALERT_3") (pintype "open_collector"))
    )
    (net (code "444") (name "unconnected-(IC25-DNC2-Pad7)") (class "Default")
      (node (ref "IC25") (pin "7") (pinfunction "DNC2_7") (pintype "output"))
    )
    (net (code "445") (name "unconnected-(IC25-DNC3-Pad8)") (class "Default")
      (node (ref "IC25") (pin "8") (pinfunction "DNC3_8") (pintype "output"))
    )
    (net (code "446") (name "unconnected-(X3-Pad13)") (class "Default")
      (node (ref "X3") (pin "13") (pinfunction "13_13") (pintype "bidirectional"))
    )
    (net (code "447") (name "unconnected-(X3-Pad14)") (class "Default")
      (node (ref "X3") (pin "14") (pinfunction "14_14") (pintype "bidirectional"))
    )
    (net (code "448") (name "unconnected-(X3-Pad17)") (class "Default")
      (node (ref "X3") (pin "17") (pinfunction "17_17") (pintype "bidirectional"))
    )
    (net (code "449") (name "unconnected-(X3-Pad18)") (class "Default")
      (node (ref "X3") (pin "18") (pinfunction "18_18") (pintype "bidirectional"))
    )
    (net (code "450") (name "unconnected-(X3-Pad19)") (class "Default")
      (node (ref "X3") (pin "19") (pinfunction "19_19") (pintype "bidirectional"))
    )
    (net (code "451") (name "unconnected-(X3-Pad20)") (class "Default")
      (node (ref "X3") (pin "20") (pinfunction "20_20") (pintype "bidirectional"))
    )
    (net (code "452") (name "unconnected-(X3-Pad29)") (class "Default")
      (node (ref "X3") (pin "29") (pinfunction "29_29") (pintype "bidirectional"))
    )
    (net (code "453") (name "unconnected-(X3-Pad30)") (class "Default")
      (node (ref "X3") (pin "30") (pinfunction "30_30") (pintype "bidirectional"))
    )
    (net (code "454") (name "unconnected-(X5-Pad7)") (class "Default")
      (node (ref "X5") (pin "7") (pinfunction "7_7") (pintype "passive"))
    )
    (net (code "455") (name "unconnected-(X5-Pad20)") (class "Default")
      (node (ref "X5") (pin "20") (pinfunction "20_20") (pintype "passive"))
    )
  )
)
